# 280103_Worldcoin_Front_Unit_5_2.net
KiCad netlist of a schematic drawn in EAGLE
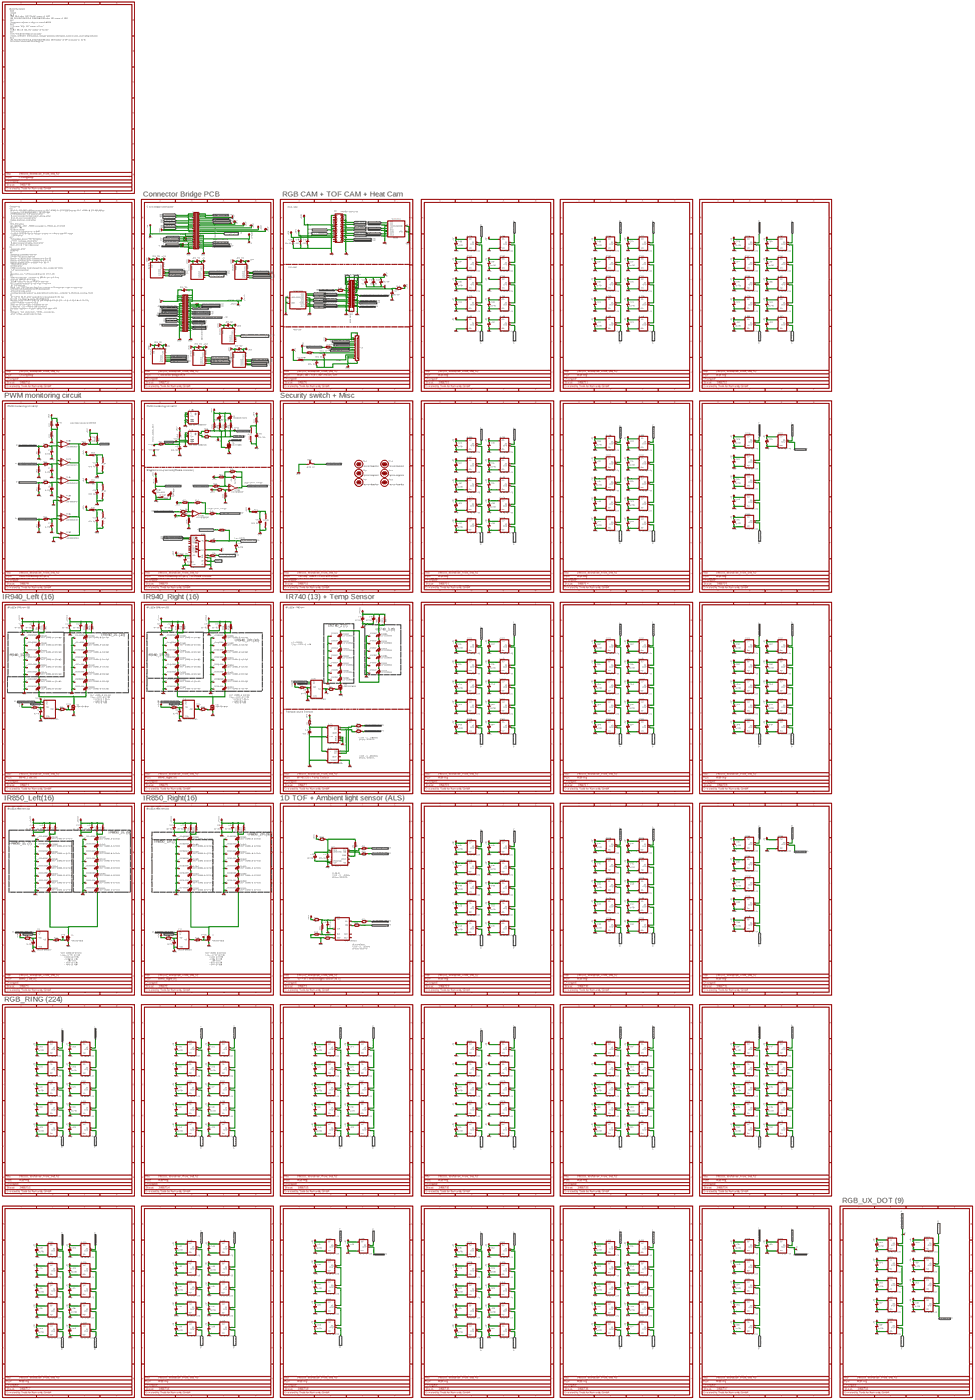
[diagram p0: schematic, sheet 1, overview]
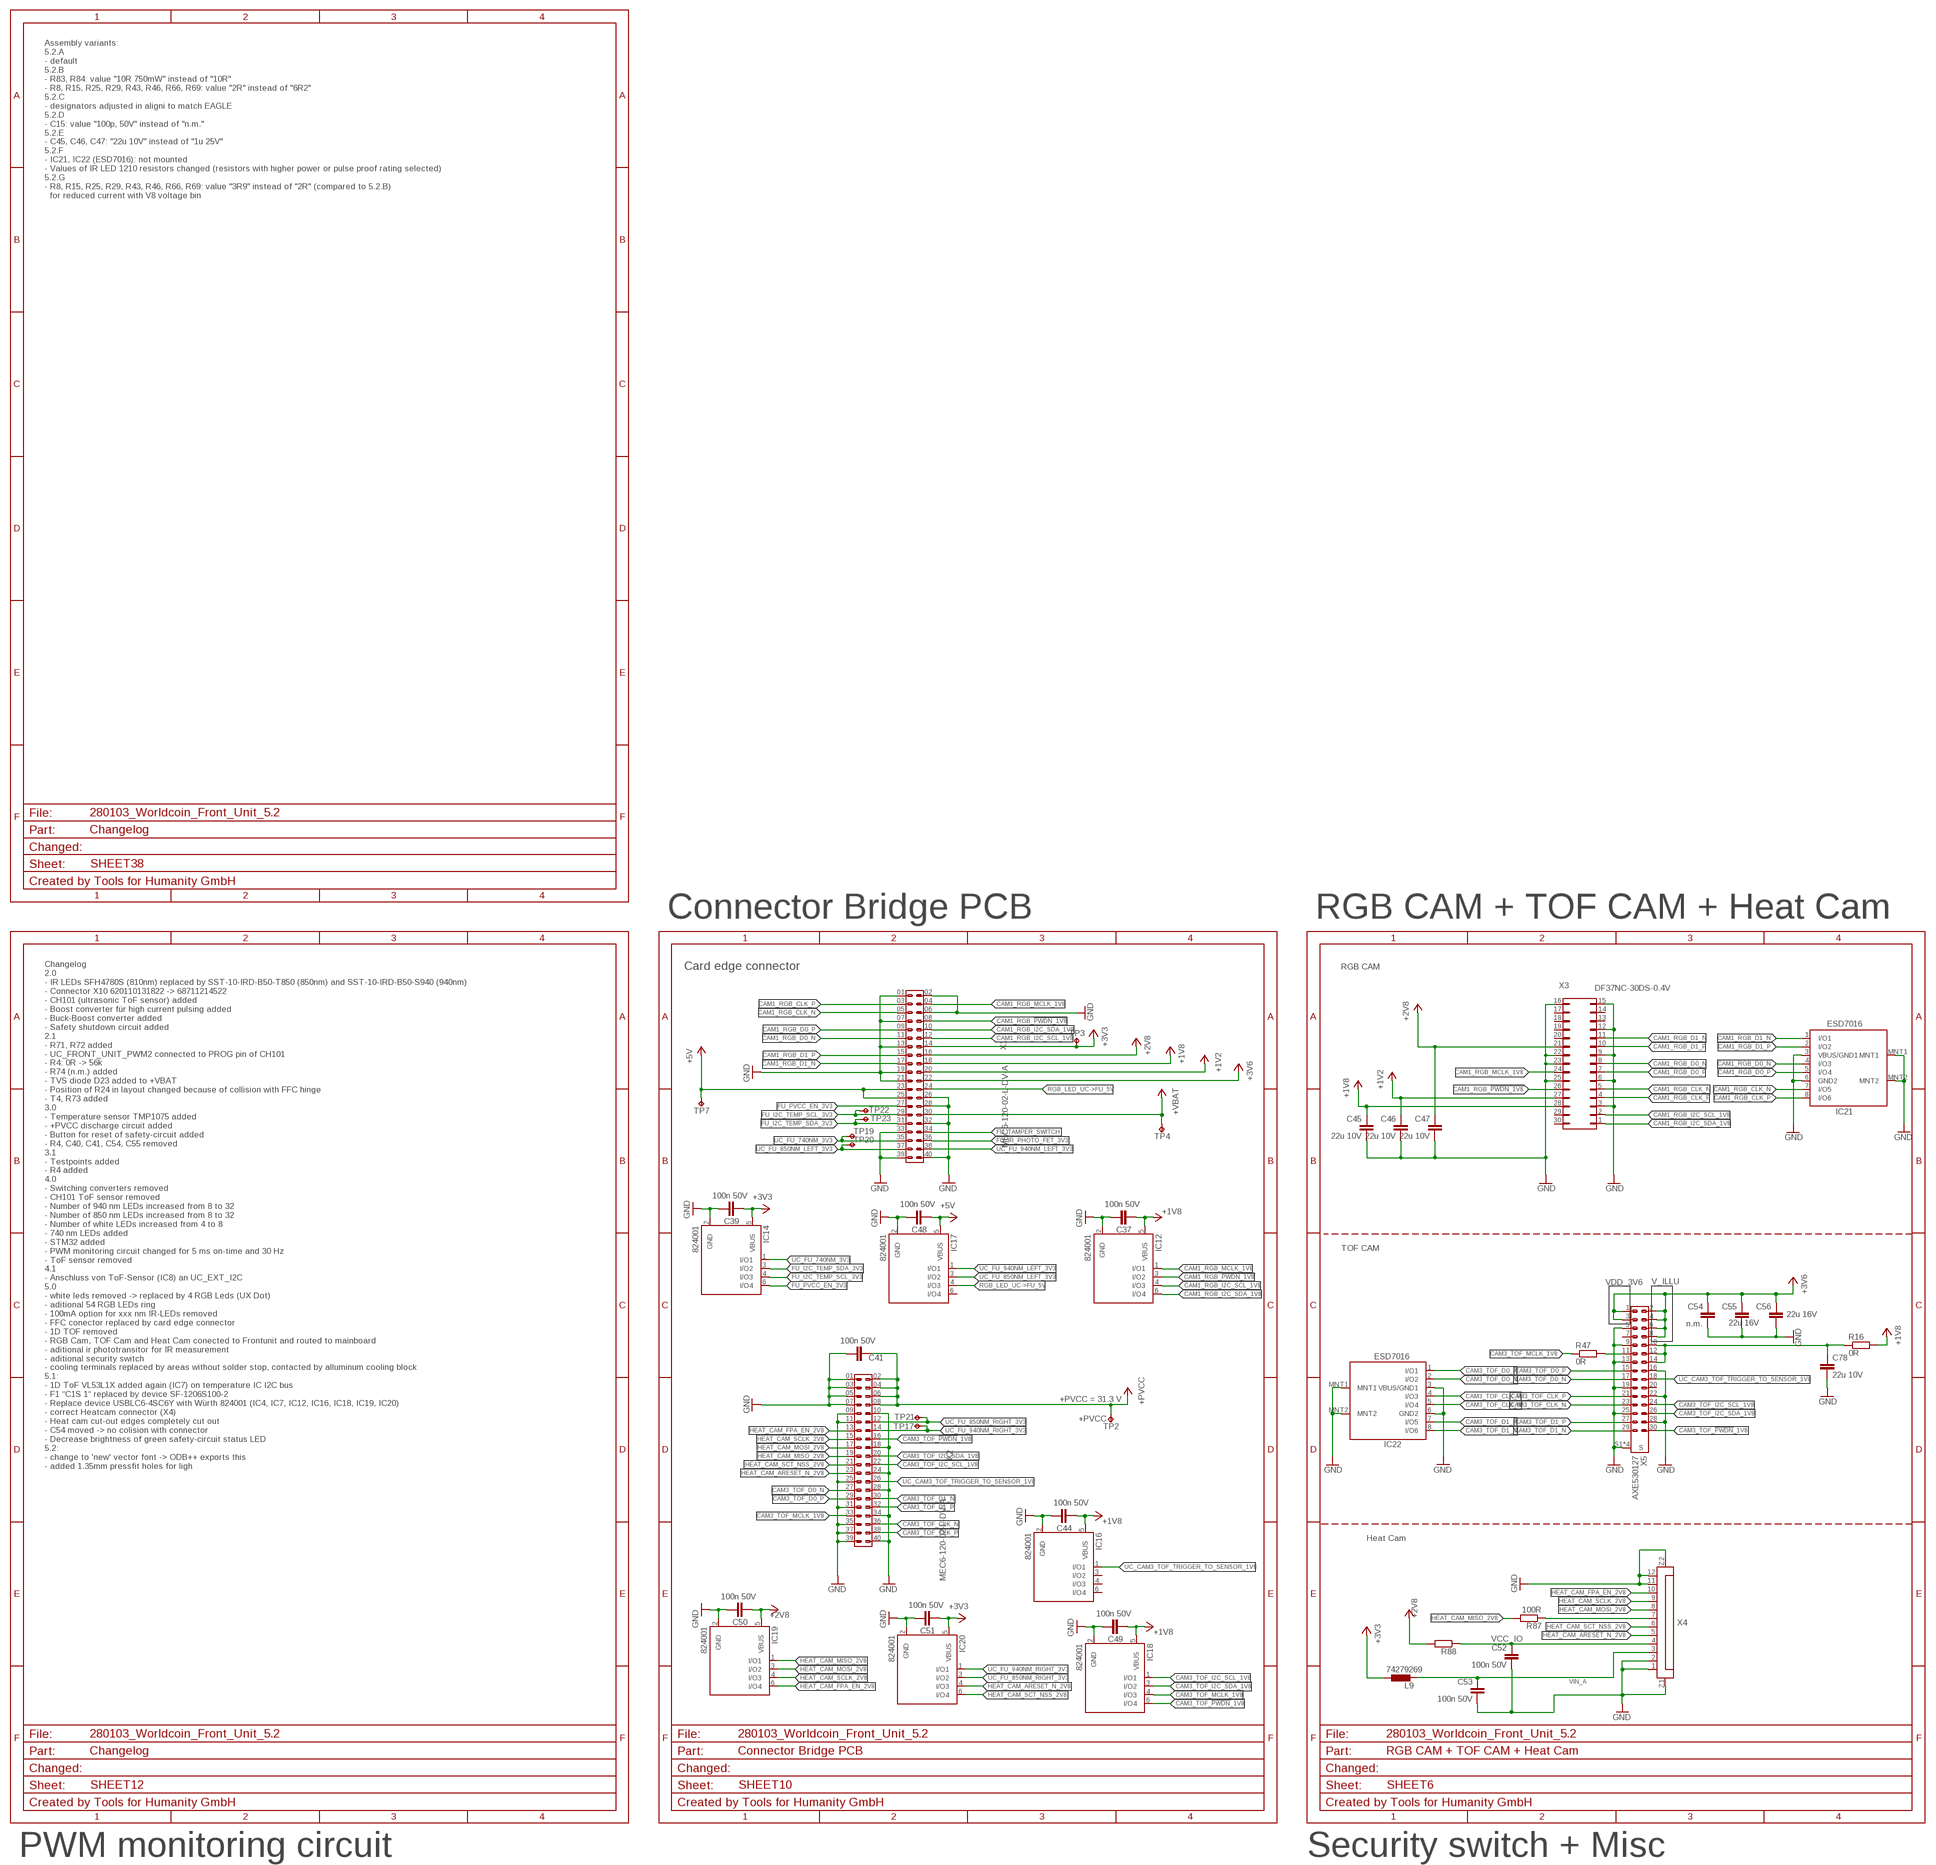
[diagram p1: schematic, sheet 1, part 1 of 8]
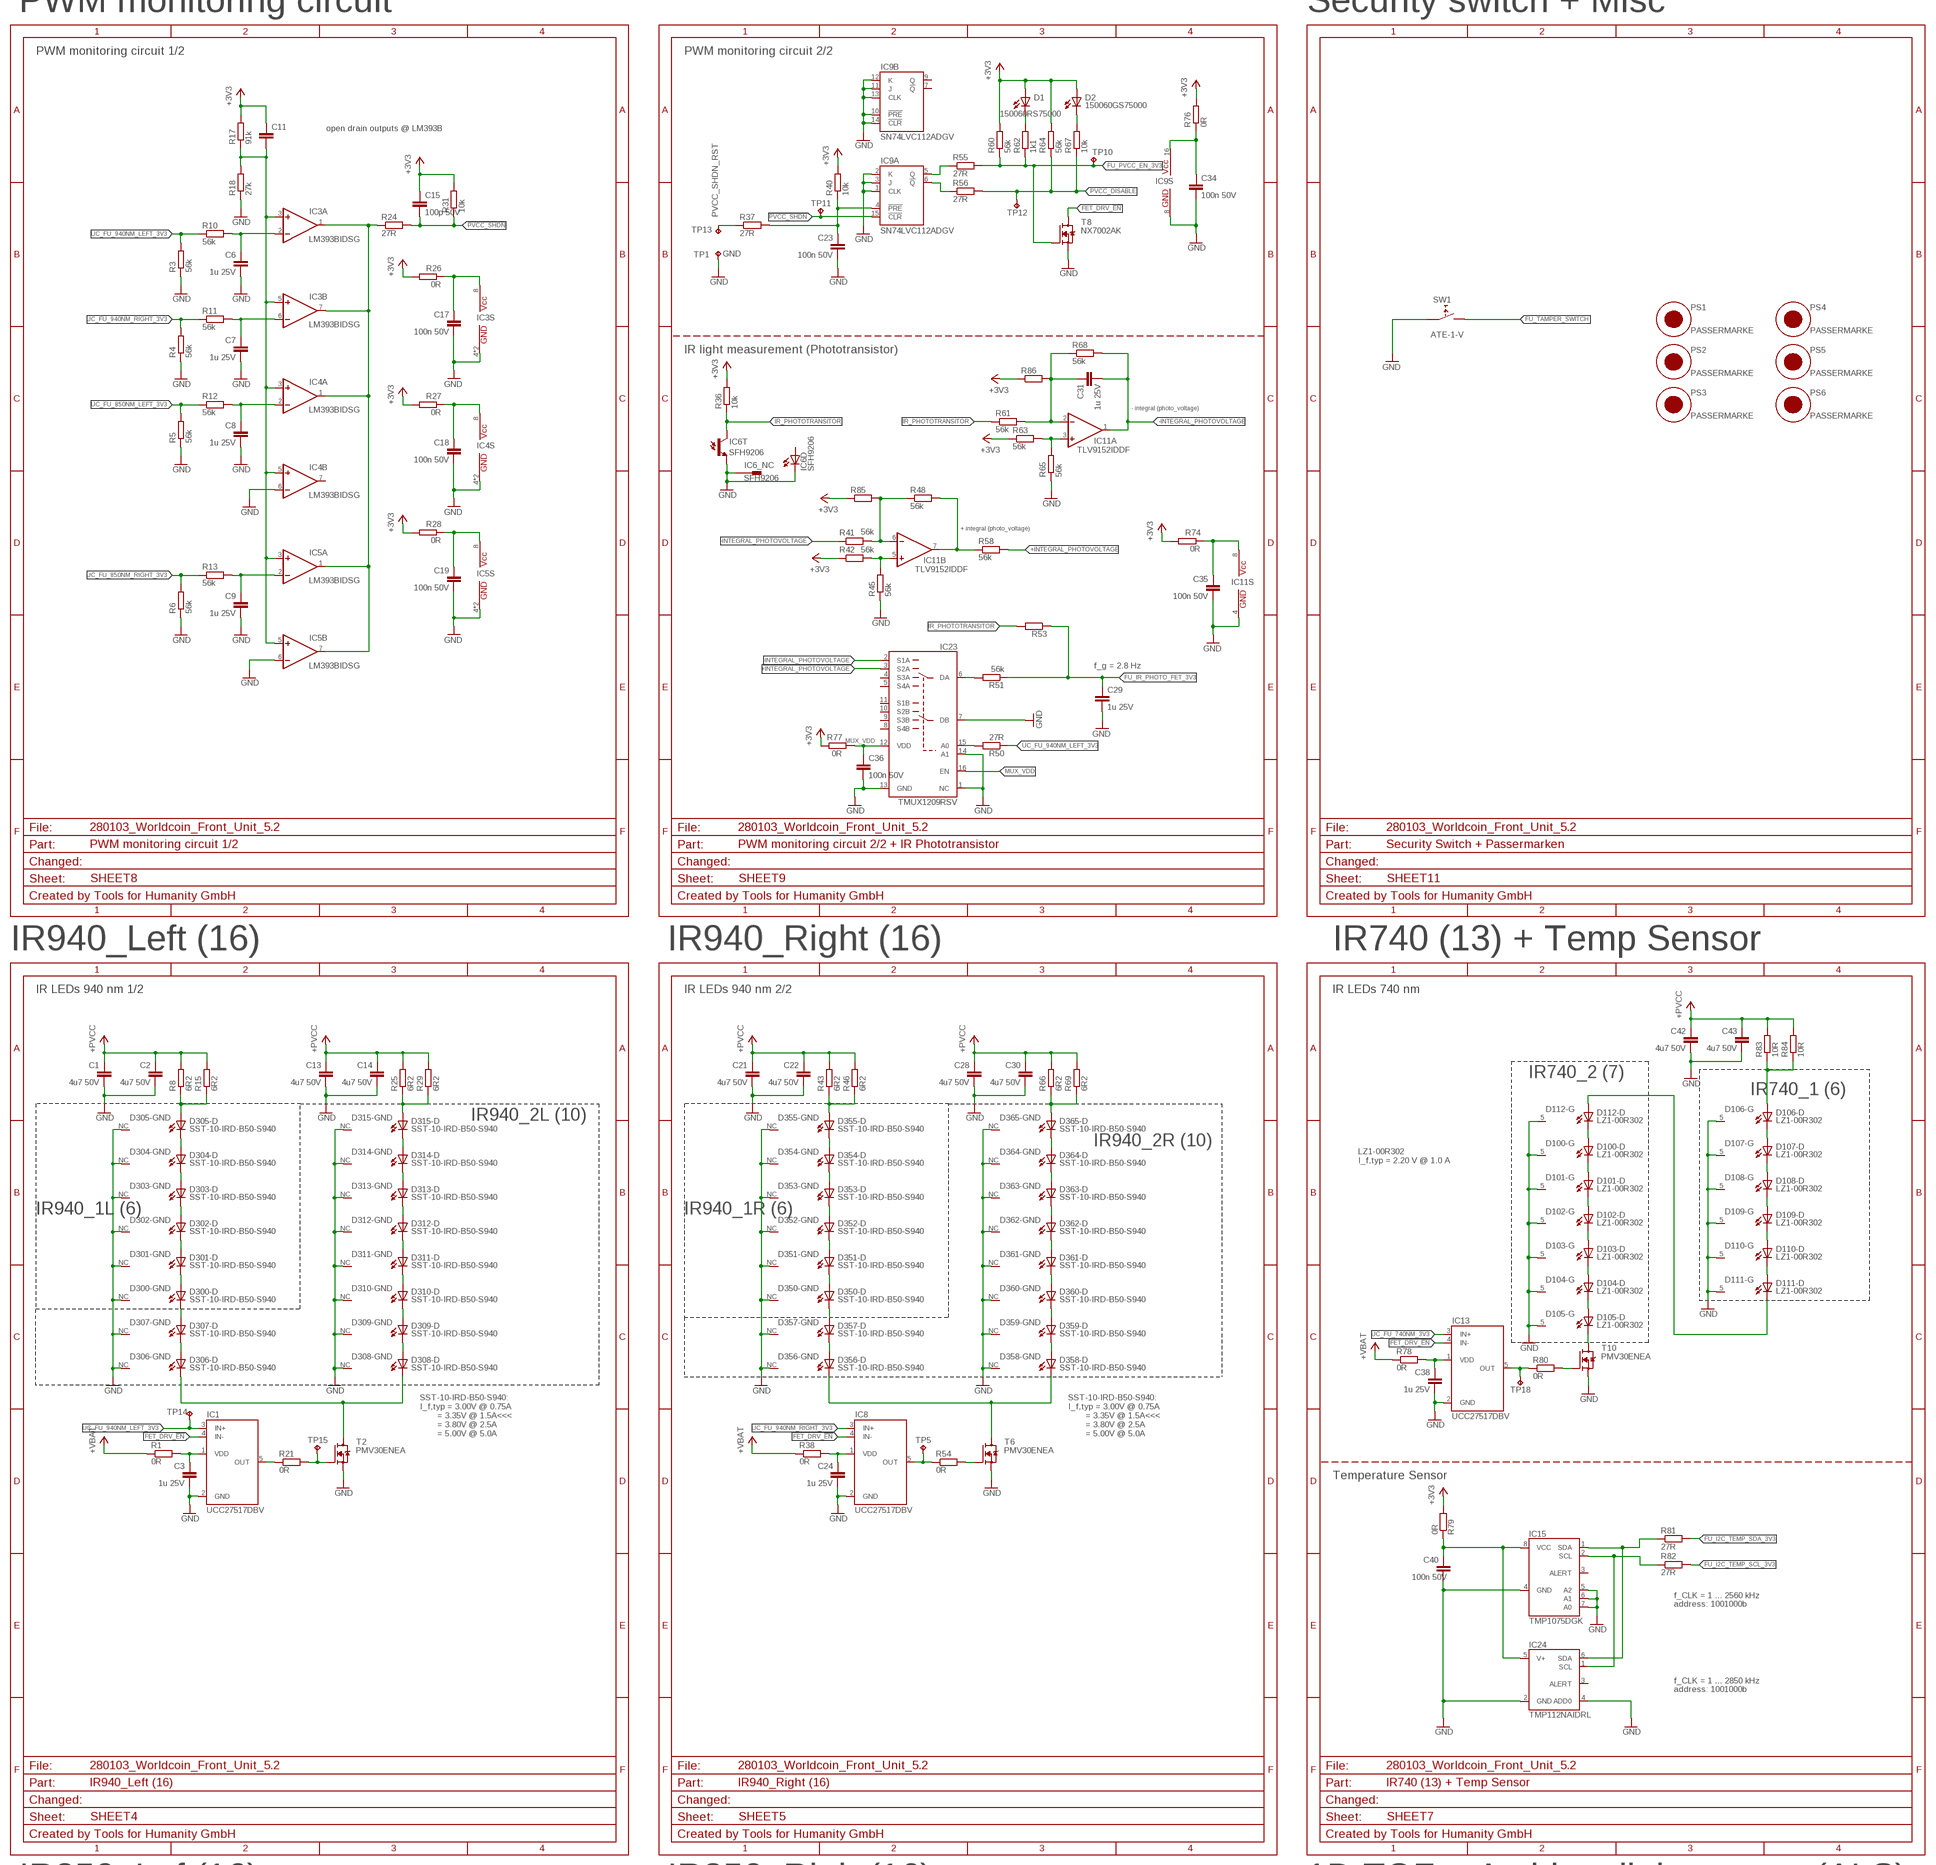
[diagram p2: schematic, sheet 1, part 2 of 8]
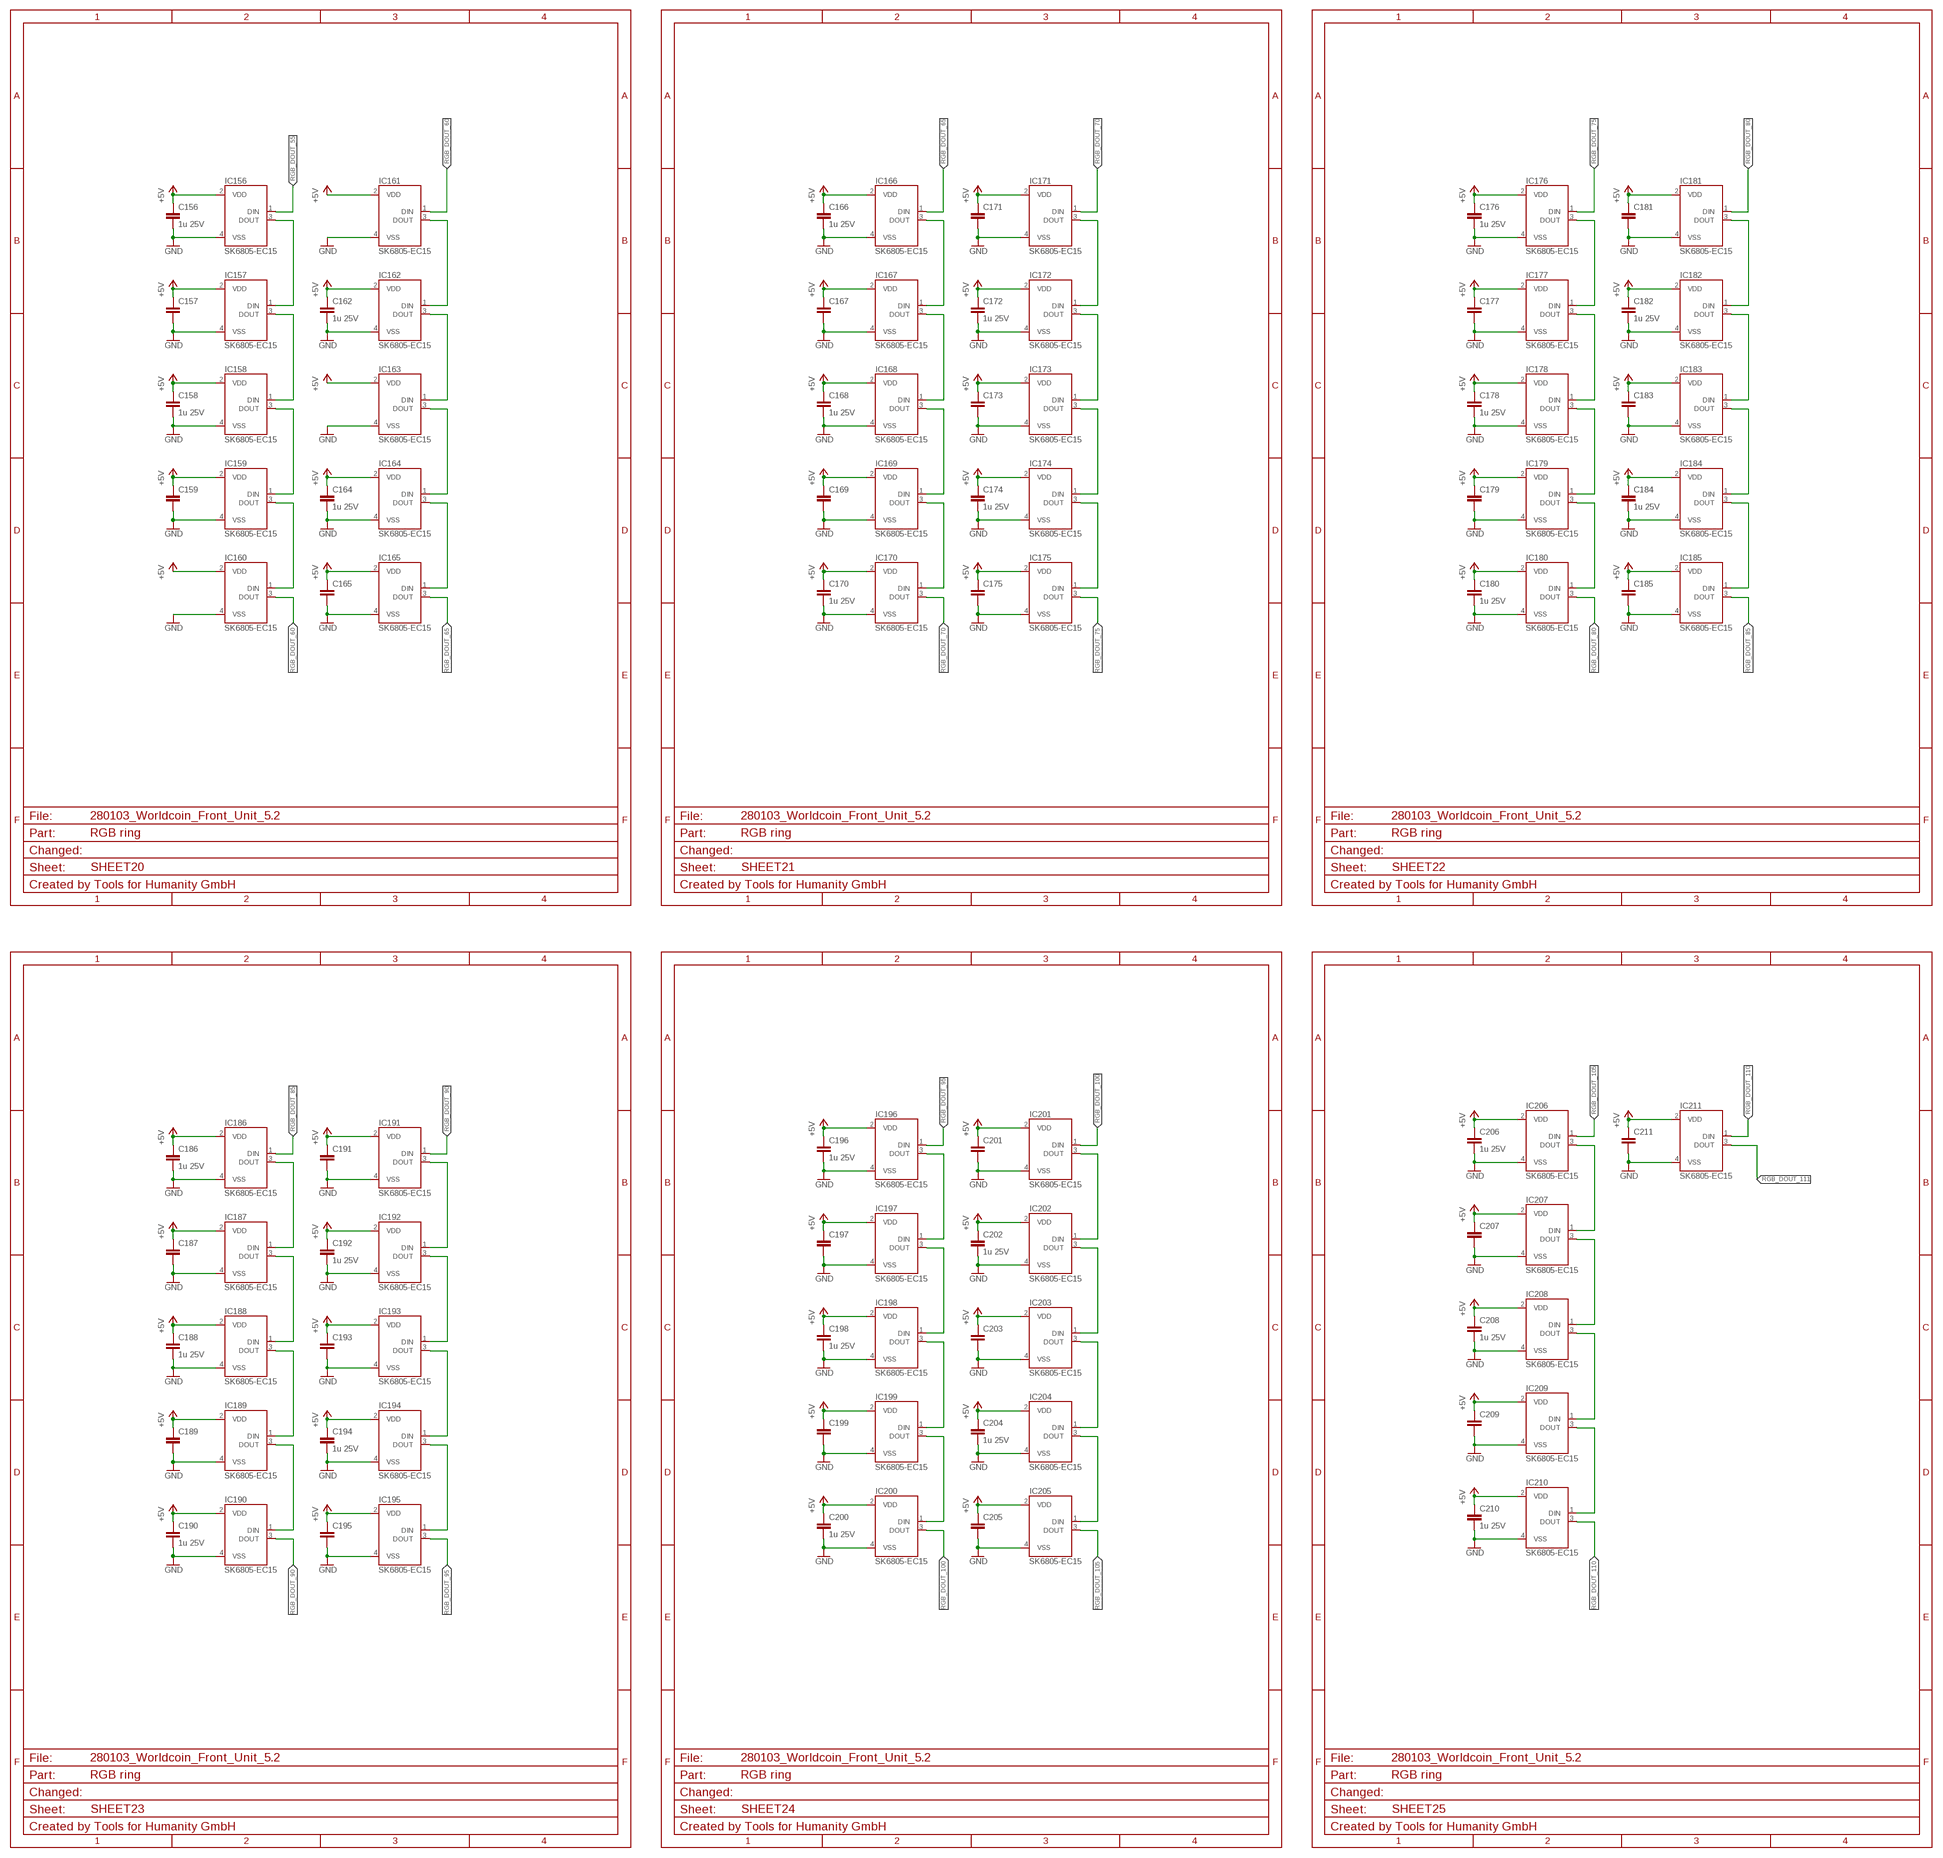
[diagram p3: schematic, sheet 1, part 3 of 8]
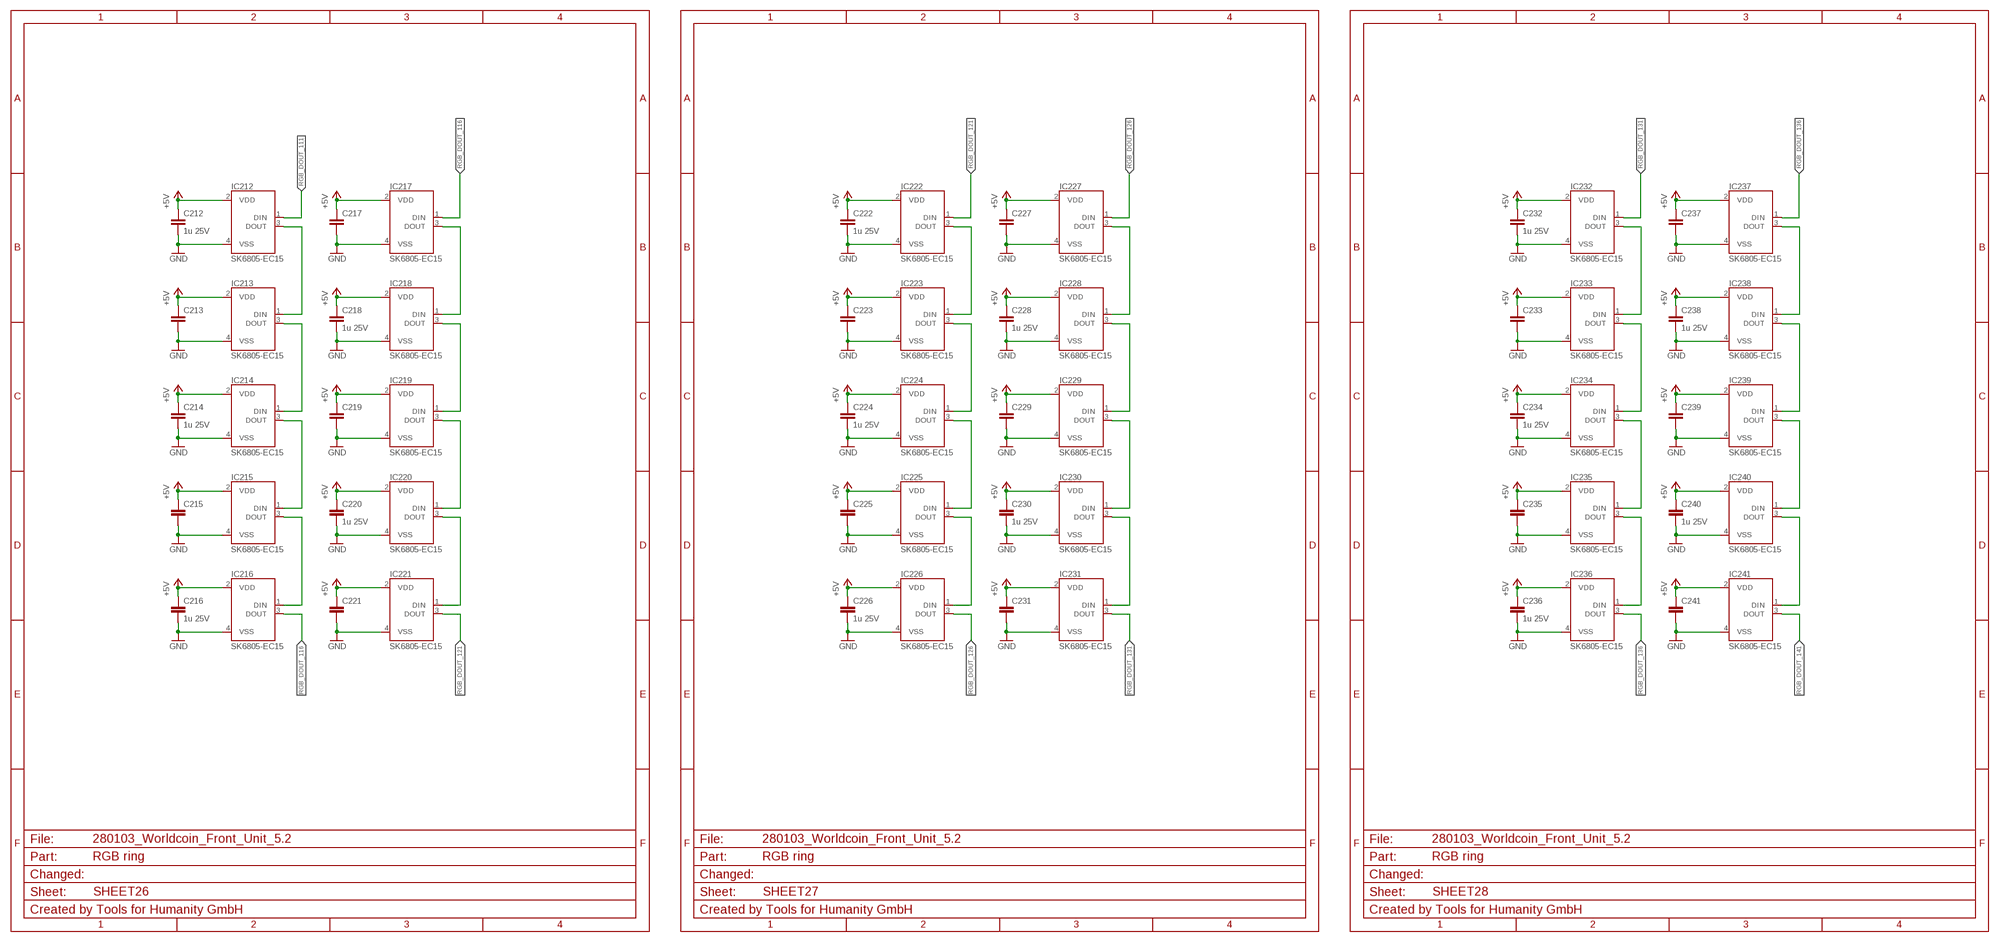
[diagram p4: schematic, sheet 1, part 4 of 8]
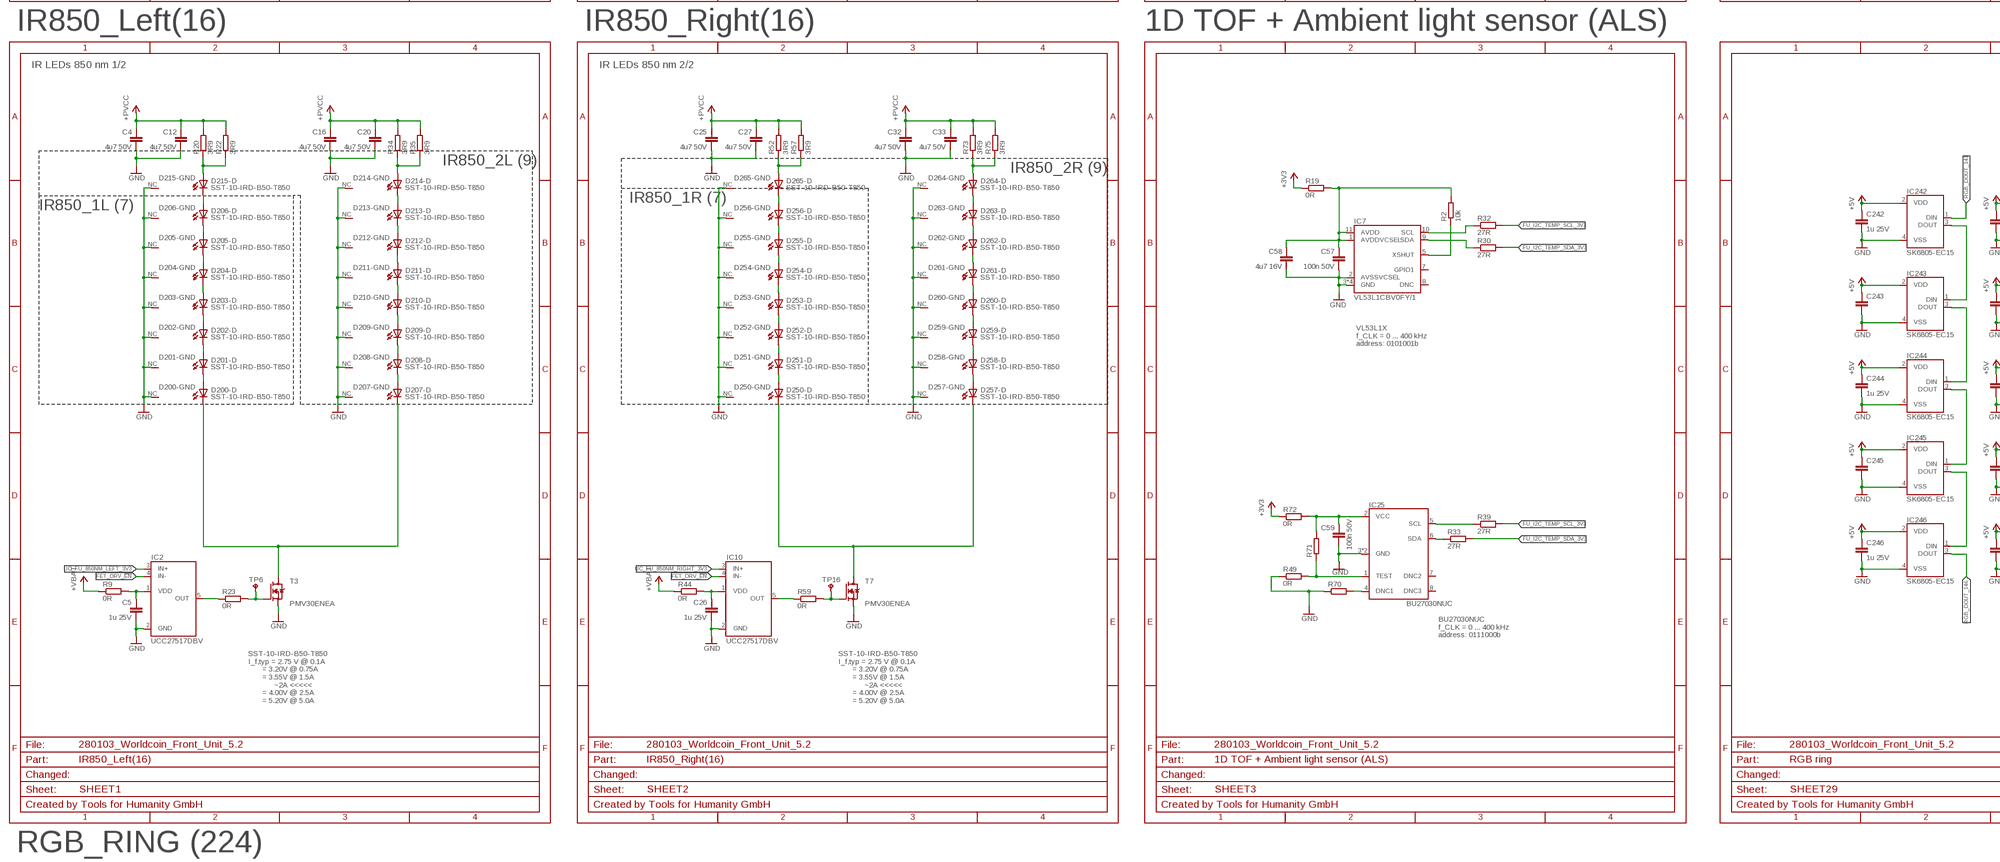
[diagram p5: schematic, sheet 1, part 5 of 8]
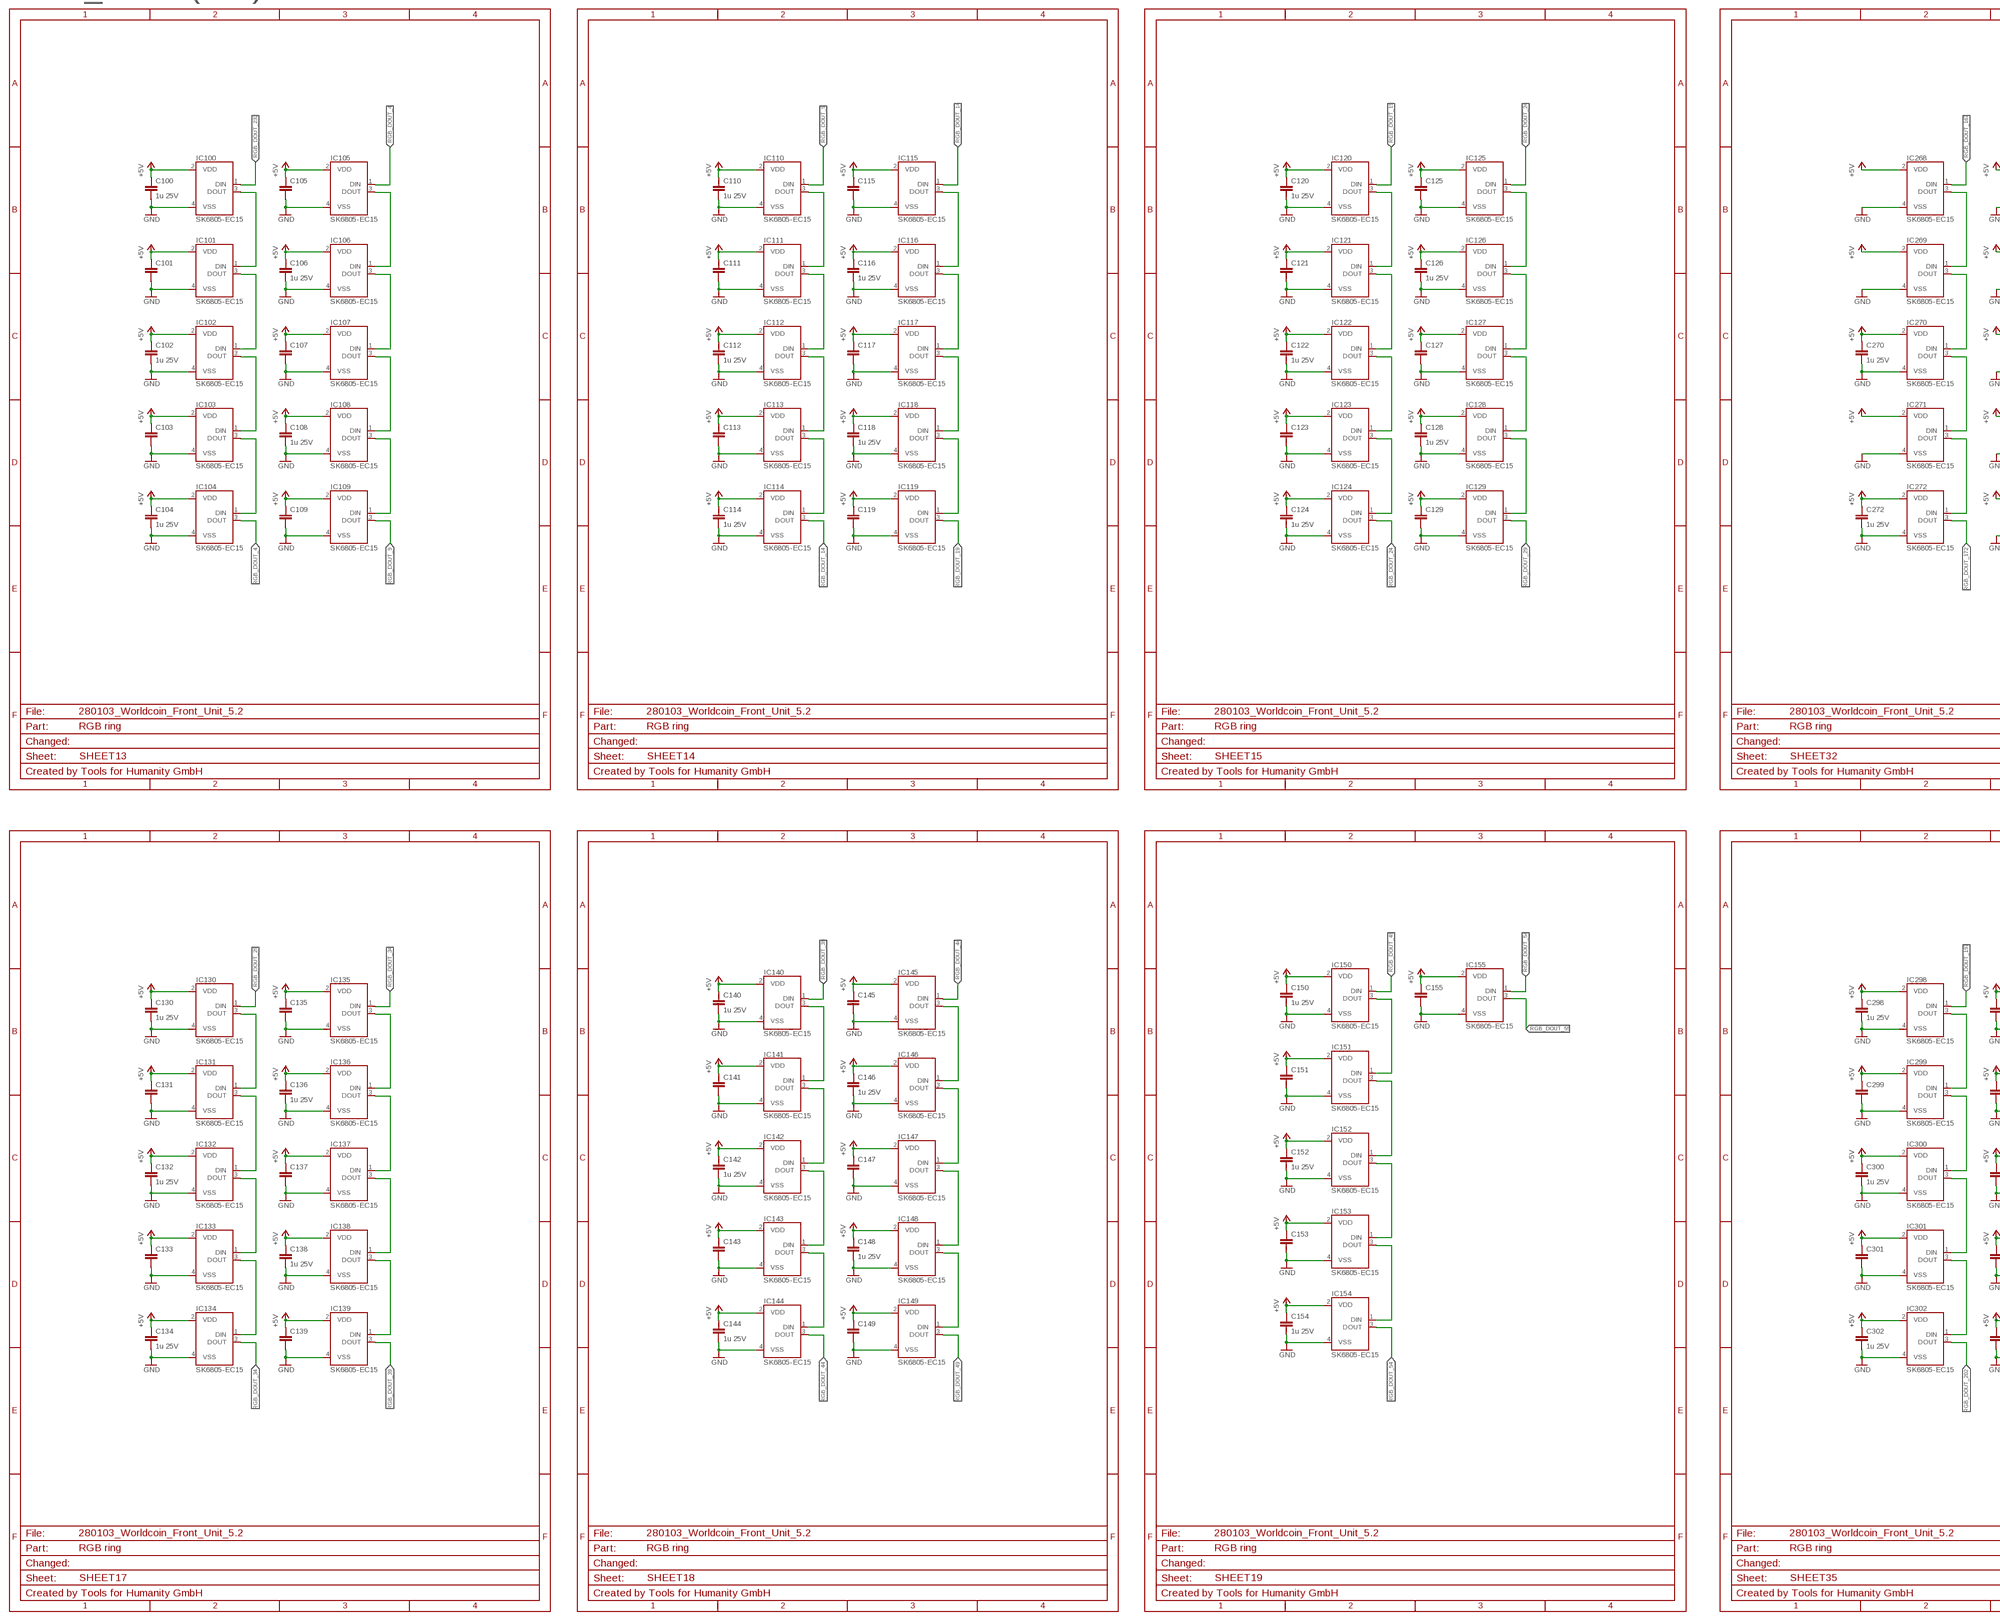
[diagram p6: schematic, sheet 1, part 6 of 8]
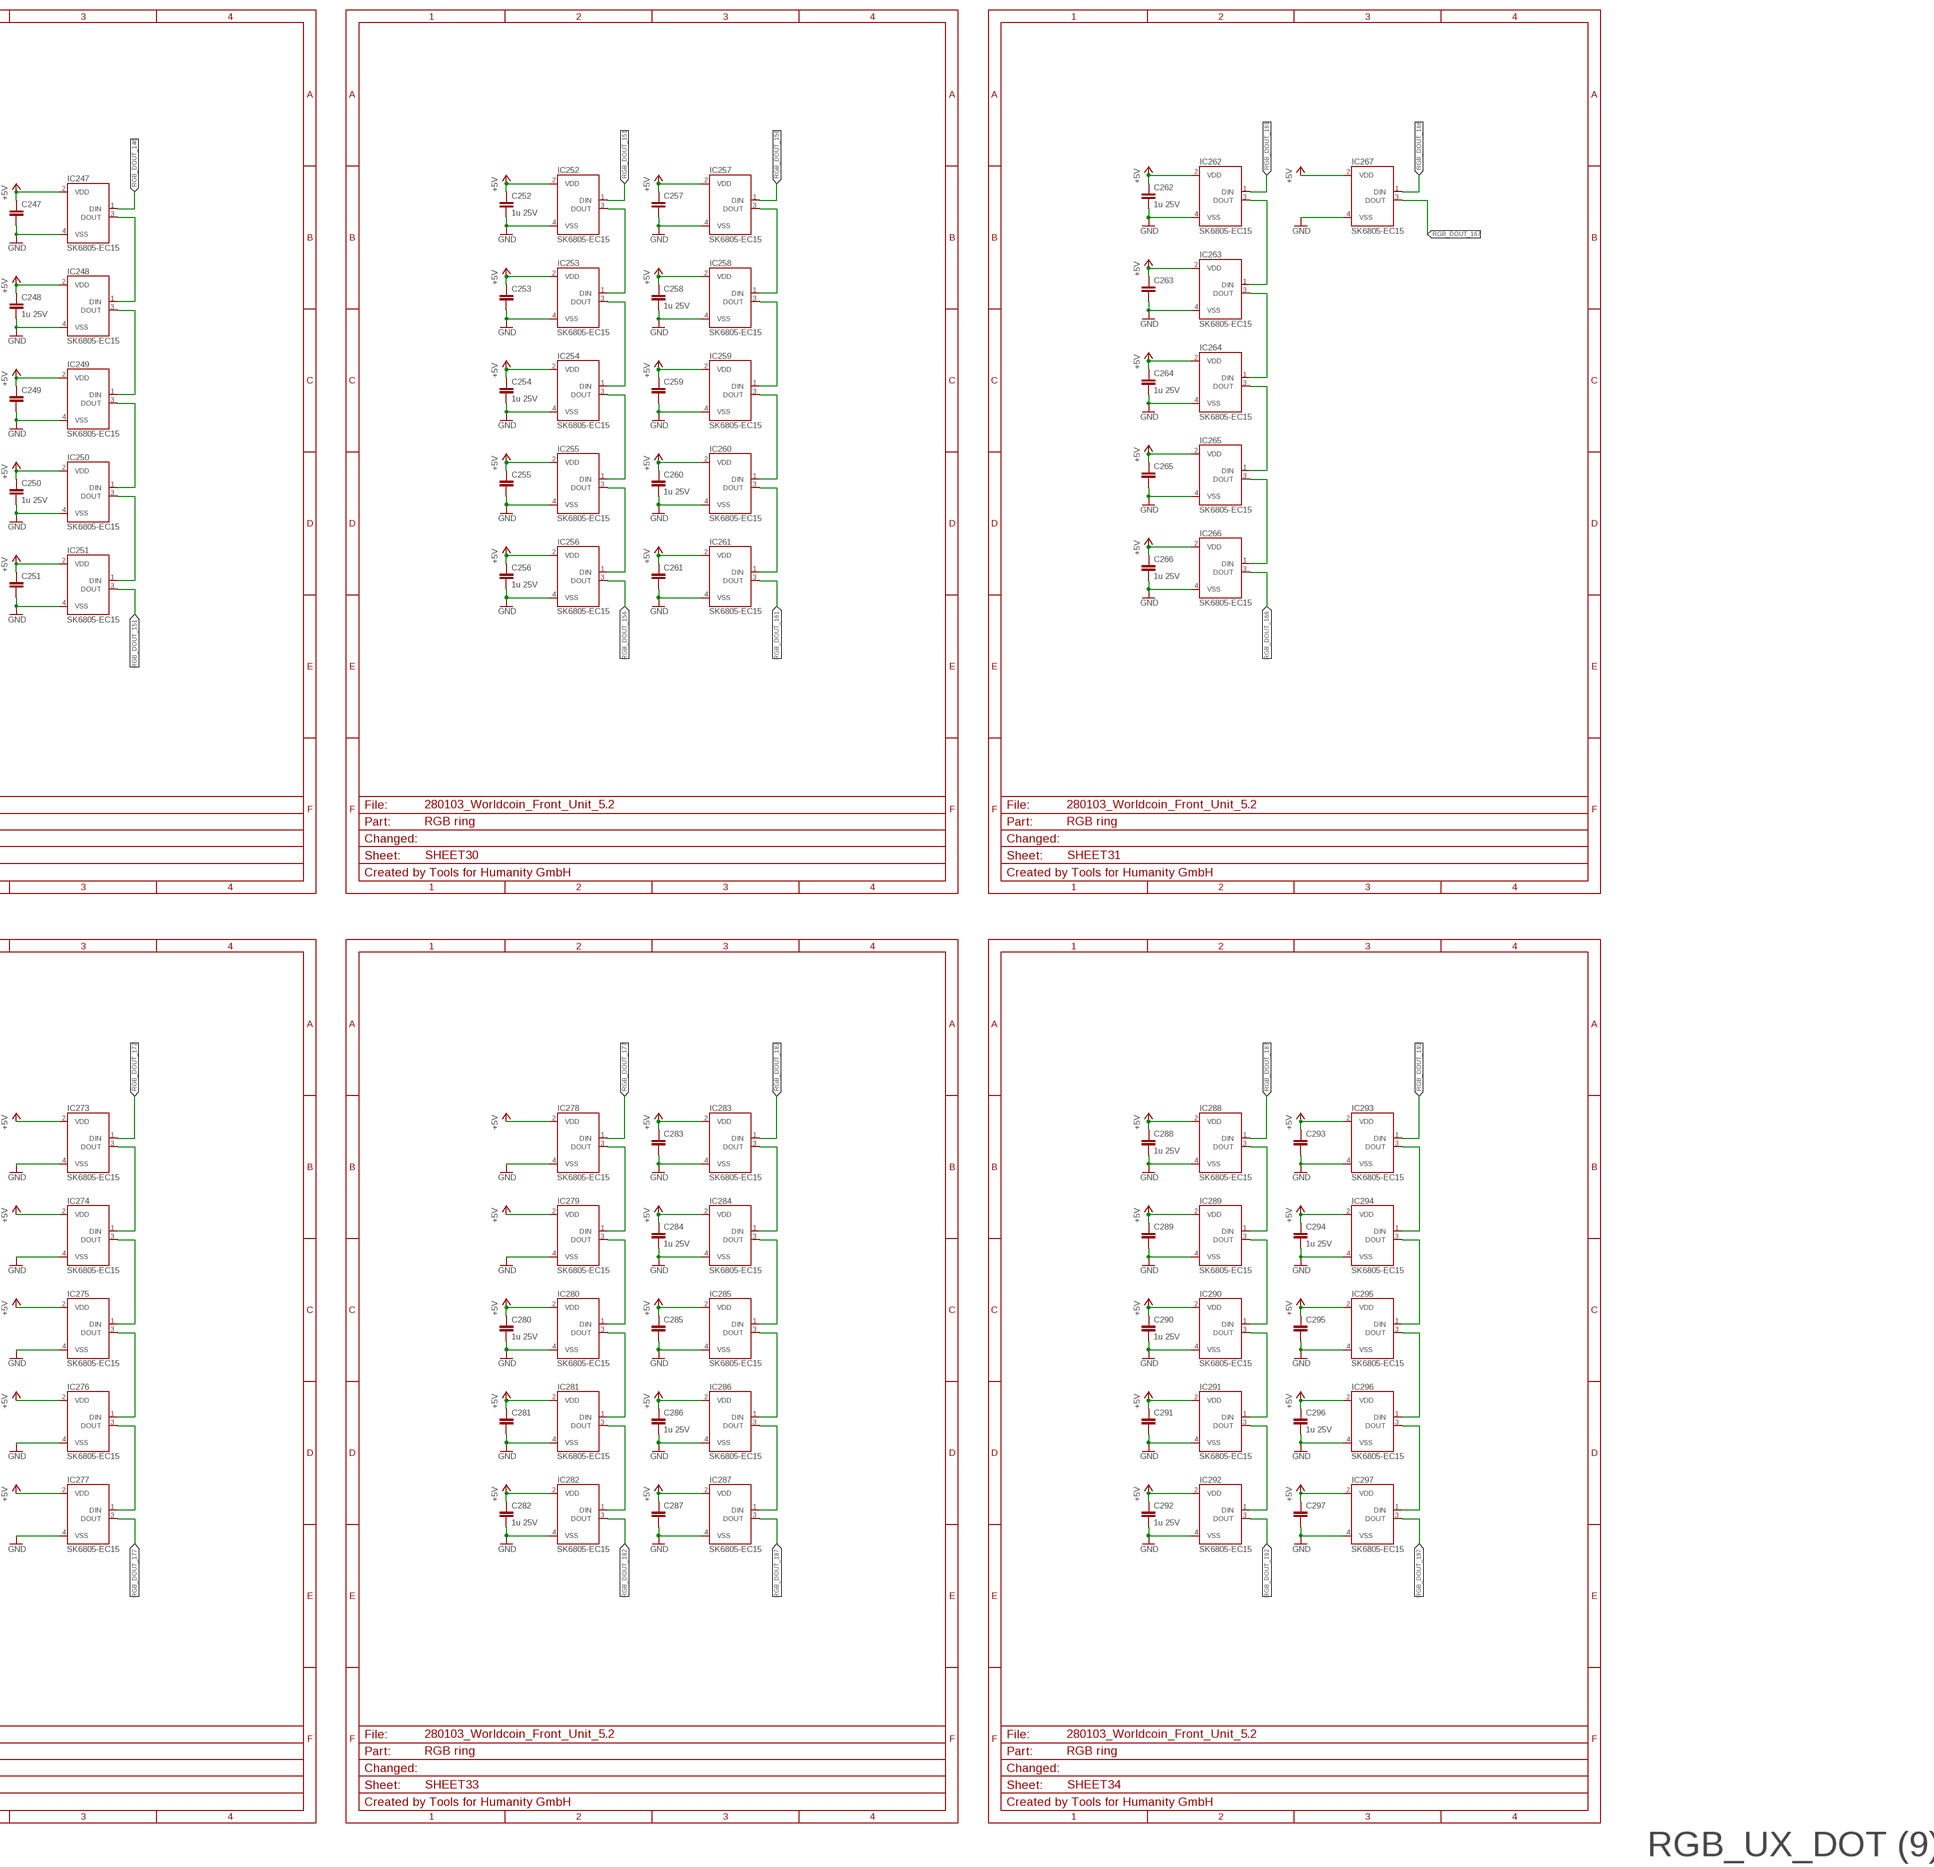
[diagram p7: schematic, sheet 1, part 7 of 8]
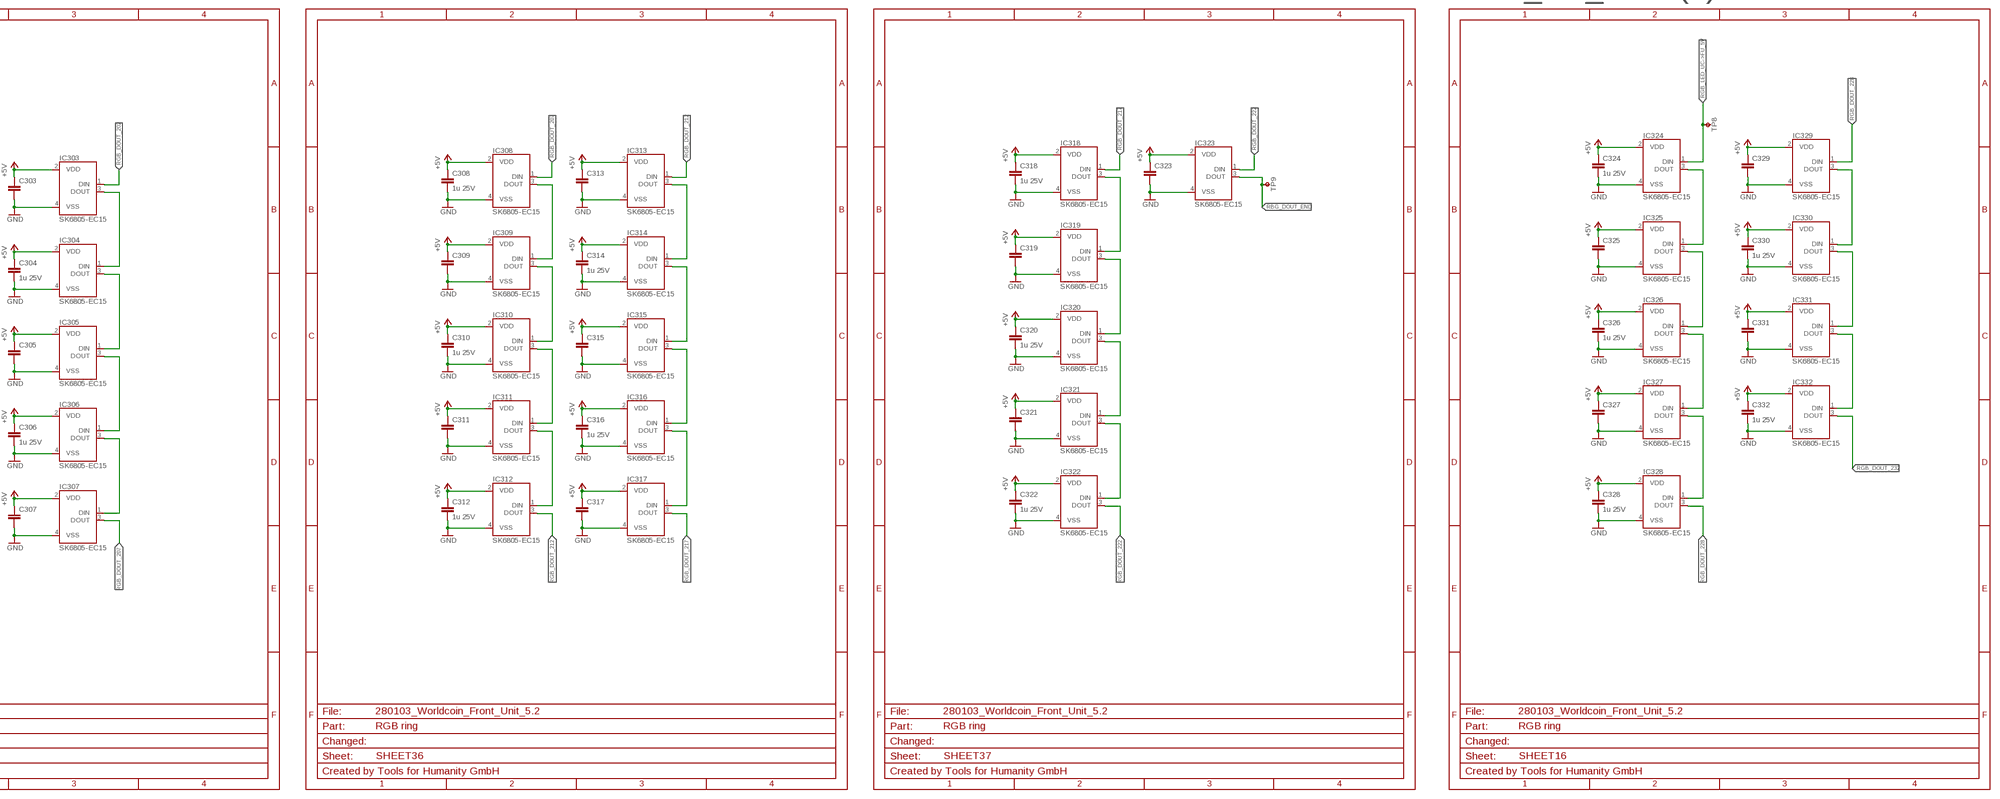
[diagram p8: schematic, sheet 1, part 8 of 8]

(export (version "E")
  (design (tool "Eeschema 10.0.6"))
  (components
    (comp (ref "C1")
      (value "4u7 50V")
      (footprint "eagle-import:C1210")
      (fields (field (name "TOLERANCE") "±20 %") (field (name "VOLTAGE") "50.0 V"))
      (libsource (lib "eagle-import") (part "C-EU-C1210"))
    )
    (comp (ref "C2")
      (value "4u7 50V")
      (footprint "eagle-import:C1210")
      (fields (field (name "TOLERANCE") "±20 %") (field (name "VOLTAGE") "50.0 V"))
      (libsource (lib "eagle-import") (part "C-EU-C1210"))
    )
    (comp (ref "C3")
      (value "1u 25V")
      (footprint "eagle-import:C0805")
      (fields
        (field (name "MANUFACTURER") "free choice")
        (field (name "TOLERANCE") "±20 %")
        (field (name "VOLTAGE") "25.0 V")
      )
      (libsource (lib "eagle-import") (part "C-EU-C0805-1U"))
    )
    (comp (ref "C4")
      (value "4u7 50V")
      (footprint "eagle-import:C1210")
      (fields (field (name "TOLERANCE") "±20 %") (field (name "VOLTAGE") "50.0 V"))
      (libsource (lib "eagle-import") (part "C-EU-C1210"))
    )
    (comp (ref "C5")
      (value "1u 25V")
      (footprint "eagle-import:C0805")
      (fields
        (field (name "MANUFACTURER") "free choice")
        (field (name "TOLERANCE") "±20 %")
        (field (name "VOLTAGE") "25.0 V")
      )
      (libsource (lib "eagle-import") (part "C-EU-C0805-1U"))
    )
    (comp (ref "C6")
      (value "1u 25V")
      (footprint "eagle-import:C0805")
      (fields
        (field (name "MANUFACTURER") "free choice")
        (field (name "TOLERANCE") "±20 %")
        (field (name "VOLTAGE") "25.0 V")
      )
      (libsource (lib "eagle-import") (part "C-EU-C0805-1U"))
    )
    (comp (ref "C7")
      (value "1u 25V")
      (footprint "eagle-import:C0805")
      (fields
        (field (name "MANUFACTURER") "free choice")
        (field (name "TOLERANCE") "±20 %")
        (field (name "VOLTAGE") "25.0 V")
      )
      (libsource (lib "eagle-import") (part "C-EU-C0805-1U"))
    )
    (comp (ref "C8")
      (value "1u 25V")
      (footprint "eagle-import:C0805")
      (fields
        (field (name "MANUFACTURER") "free choice")
        (field (name "TOLERANCE") "±20 %")
        (field (name "VOLTAGE") "25.0 V")
      )
      (libsource (lib "eagle-import") (part "C-EU-C0805-1U"))
    )
    (comp (ref "C9")
      (value "1u 25V")
      (footprint "eagle-import:C0805")
      (fields
        (field (name "MANUFACTURER") "free choice")
        (field (name "TOLERANCE") "±20 %")
        (field (name "VOLTAGE") "25.0 V")
      )
      (libsource (lib "eagle-import") (part "C-EU-C0805-1U"))
    )
    (comp (ref "C11")
      (value "C-EU-C0603")
      (footprint "eagle-import:C0603")
      (fields (field (name "TOLERANCE") "±20 %") (field (name "VOLTAGE") "50.0 V"))
      (libsource (lib "eagle-import") (part "C-EU-C0603"))
    )
    (comp (ref "C12")
      (value "4u7 50V")
      (footprint "eagle-import:C1210")
      (fields (field (name "TOLERANCE") "±20 %") (field (name "VOLTAGE") "50.0 V"))
      (libsource (lib "eagle-import") (part "C-EU-C1210"))
    )
    (comp (ref "C13")
      (value "4u7 50V")
      (footprint "eagle-import:C1210")
      (fields (field (name "TOLERANCE") "±20 %") (field (name "VOLTAGE") "50.0 V"))
      (libsource (lib "eagle-import") (part "C-EU-C1210"))
    )
    (comp (ref "C14")
      (value "4u7 50V")
      (footprint "eagle-import:C1210")
      (fields (field (name "TOLERANCE") "±20 %") (field (name "VOLTAGE") "50.0 V"))
      (libsource (lib "eagle-import") (part "C-EU-C1210"))
    )
    (comp (ref "C15")
      (value "100p 50V")
      (footprint "eagle-import:C0603")
      (fields
        (field (name "MANUFACTURER") "free choice")
        (field (name "TOLERANCE") "±10 %")
        (field (name "VOLTAGE") "50.0 V")
      )
      (libsource (lib "eagle-import") (part "C-EU-C0603-100P"))
    )
    (comp (ref "C16")
      (value "4u7 50V")
      (footprint "eagle-import:C1210")
      (fields (field (name "TOLERANCE") "±20 %") (field (name "VOLTAGE") "50.0 V"))
      (libsource (lib "eagle-import") (part "C-EU-C1210"))
    )
    (comp (ref "C17")
      (value "100n 50V")
      (footprint "eagle-import:C0603")
      (fields
        (field (name "MANUFACTURER") "free choice")
        (field (name "TOLERANCE") "±20 %")
        (field (name "VOLTAGE") "50.0 V")
      )
      (libsource (lib "eagle-import") (part "C-EU-C0603-100N"))
    )
    (comp (ref "C18")
      (value "100n 50V")
      (footprint "eagle-import:C0603")
      (fields
        (field (name "MANUFACTURER") "free choice")
        (field (name "TOLERANCE") "±20 %")
        (field (name "VOLTAGE") "50.0 V")
      )
      (libsource (lib "eagle-import") (part "C-EU-C0603-100N"))
    )
    (comp (ref "C19")
      (value "100n 50V")
      (footprint "eagle-import:C0603")
      (fields
        (field (name "MANUFACTURER") "free choice")
        (field (name "TOLERANCE") "±20 %")
        (field (name "VOLTAGE") "50.0 V")
      )
      (libsource (lib "eagle-import") (part "C-EU-C0603-100N"))
    )
    (comp (ref "C20")
      (value "4u7 50V")
      (footprint "eagle-import:C1210")
      (fields (field (name "TOLERANCE") "±20 %") (field (name "VOLTAGE") "50.0 V"))
      (libsource (lib "eagle-import") (part "C-EU-C1210"))
    )
    (comp (ref "C21")
      (value "4u7 50V")
      (footprint "eagle-import:C1210")
      (fields (field (name "TOLERANCE") "±20 %") (field (name "VOLTAGE") "50.0 V"))
      (libsource (lib "eagle-import") (part "C-EU-C1210"))
    )
    (comp (ref "C22")
      (value "4u7 50V")
      (footprint "eagle-import:C1210")
      (fields (field (name "TOLERANCE") "±20 %") (field (name "VOLTAGE") "50.0 V"))
      (libsource (lib "eagle-import") (part "C-EU-C1210"))
    )
    (comp (ref "C23")
      (value "100n 50V")
      (footprint "eagle-import:C0603")
      (fields
        (field (name "MANUFACTURER") "free choice")
        (field (name "TOLERANCE") "±20 %")
        (field (name "VOLTAGE") "50.0 V")
      )
      (libsource (lib "eagle-import") (part "C-EU-C0603-100N"))
    )
    (comp (ref "C24")
      (value "1u 25V")
      (footprint "eagle-import:C0805")
      (fields
        (field (name "MANUFACTURER") "free choice")
        (field (name "TOLERANCE") "±20 %")
        (field (name "VOLTAGE") "25.0 V")
      )
      (libsource (lib "eagle-import") (part "C-EU-C0805-1U"))
    )
    (comp (ref "C25")
      (value "4u7 50V")
      (footprint "eagle-import:C1210")
      (fields (field (name "TOLERANCE") "±20 %") (field (name "VOLTAGE") "50.0 V"))
      (libsource (lib "eagle-import") (part "C-EU-C1210"))
    )
    (comp (ref "C26")
      (value "1u 25V")
      (footprint "eagle-import:C0805")
      (fields
        (field (name "MANUFACTURER") "free choice")
        (field (name "TOLERANCE") "±20 %")
        (field (name "VOLTAGE") "25.0 V")
      )
      (libsource (lib "eagle-import") (part "C-EU-C0805-1U"))
    )
    (comp (ref "C27")
      (value "4u7 50V")
      (footprint "eagle-import:C1210")
      (fields (field (name "TOLERANCE") "±20 %") (field (name "VOLTAGE") "50.0 V"))
      (libsource (lib "eagle-import") (part "C-EU-C1210"))
    )
    (comp (ref "C28")
      (value "4u7 50V")
      (footprint "eagle-import:C1210")
      (fields (field (name "TOLERANCE") "±20 %") (field (name "VOLTAGE") "50.0 V"))
      (libsource (lib "eagle-import") (part "C-EU-C1210"))
    )
    (comp (ref "C29")
      (value "1u 25V")
      (footprint "eagle-import:C0805")
      (fields
        (field (name "MANUFACTURER") "free choice")
        (field (name "TOLERANCE") "±20 %")
        (field (name "VOLTAGE") "25.0 V")
      )
      (libsource (lib "eagle-import") (part "C-EU-C0805-1U"))
    )
    (comp (ref "C30")
      (value "4u7 50V")
      (footprint "eagle-import:C1210")
      (fields (field (name "TOLERANCE") "±20 %") (field (name "VOLTAGE") "50.0 V"))
      (libsource (lib "eagle-import") (part "C-EU-C1210"))
    )
    (comp (ref "C31")
      (value "1u 25V")
      (footprint "eagle-import:C0805")
      (fields
        (field (name "MANUFACTURER") "free choice")
        (field (name "TOLERANCE") "±20 %")
        (field (name "VOLTAGE") "25.0 V")
      )
      (libsource (lib "eagle-import") (part "C-EU-C0805-1U"))
    )
    (comp (ref "C32")
      (value "4u7 50V")
      (footprint "eagle-import:C1210")
      (fields (field (name "TOLERANCE") "±20 %") (field (name "VOLTAGE") "50.0 V"))
      (libsource (lib "eagle-import") (part "C-EU-C1210"))
    )
    (comp (ref "C33")
      (value "4u7 50V")
      (footprint "eagle-import:C1210")
      (fields (field (name "TOLERANCE") "±20 %") (field (name "VOLTAGE") "50.0 V"))
      (libsource (lib "eagle-import") (part "C-EU-C1210"))
    )
    (comp (ref "C34")
      (value "100n 50V")
      (footprint "eagle-import:C0603")
      (fields
        (field (name "MANUFACTURER") "free choice")
        (field (name "TOLERANCE") "±20 %")
        (field (name "VOLTAGE") "50.0 V")
      )
      (libsource (lib "eagle-import") (part "C-EU-C0603-100N"))
    )
    (comp (ref "C35")
      (value "100n 50V")
      (footprint "eagle-import:C0603")
      (fields
        (field (name "MANUFACTURER") "free choice")
        (field (name "TOLERANCE") "±20 %")
        (field (name "VOLTAGE") "50.0 V")
      )
      (libsource (lib "eagle-import") (part "C-EU-C0603-100N"))
    )
    (comp (ref "C36")
      (value "100n 50V")
      (footprint "eagle-import:C0603")
      (fields
        (field (name "MANUFACTURER") "free choice")
        (field (name "TOLERANCE") "±20 %")
        (field (name "VOLTAGE") "50.0 V")
      )
      (libsource (lib "eagle-import") (part "C-EU-C0603-100N"))
    )
    (comp (ref "C37")
      (value "100n 50V")
      (footprint "eagle-import:C0603")
      (fields
        (field (name "MANUFACTURER") "free choice")
        (field (name "TOLERANCE") "±20 %")
        (field (name "VOLTAGE") "50.0 V")
      )
      (libsource (lib "eagle-import") (part "C-EU-C0603-100N"))
    )
    (comp (ref "C38")
      (value "1u 25V")
      (footprint "eagle-import:C0805")
      (fields
        (field (name "MANUFACTURER") "free choice")
        (field (name "TOLERANCE") "±20 %")
        (field (name "VOLTAGE") "25.0 V")
      )
      (libsource (lib "eagle-import") (part "C-EU-C0805-1U"))
    )
    (comp (ref "C39")
      (value "100n 50V")
      (footprint "eagle-import:C0603")
      (fields
        (field (name "MANUFACTURER") "free choice")
        (field (name "TOLERANCE") "±20 %")
        (field (name "VOLTAGE") "50.0 V")
      )
      (libsource (lib "eagle-import") (part "C-EU-C0603-100N"))
    )
    (comp (ref "C40")
      (value "100n 50V")
      (footprint "eagle-import:C0603")
      (fields
        (field (name "MANUFACTURER") "free choice")
        (field (name "TOLERANCE") "±20 %")
        (field (name "VOLTAGE") "50.0 V")
      )
      (libsource (lib "eagle-import") (part "C-EU-C0603-100N"))
    )
    (comp (ref "C41")
      (value "100n 50V")
      (footprint "eagle-import:C0603")
      (fields
        (field (name "MANUFACTURER") "free choice")
        (field (name "TOLERANCE") "±20 %")
        (field (name "VOLTAGE") "50.0 V")
      )
      (libsource (lib "eagle-import") (part "C-EU-C0603-100N"))
    )
    (comp (ref "C42")
      (value "4u7 50V")
      (footprint "eagle-import:C1210")
      (fields (field (name "TOLERANCE") "±20 %") (field (name "VOLTAGE") "50.0 V"))
      (libsource (lib "eagle-import") (part "C-EU-C1210"))
    )
    (comp (ref "C43")
      (value "4u7 50V")
      (footprint "eagle-import:C1210")
      (fields (field (name "TOLERANCE") "±20 %") (field (name "VOLTAGE") "50.0 V"))
      (libsource (lib "eagle-import") (part "C-EU-C1210"))
    )
    (comp (ref "C44")
      (value "100n 50V")
      (footprint "eagle-import:C0603")
      (fields
        (field (name "MANUFACTURER") "free choice")
        (field (name "TOLERANCE") "±20 %")
        (field (name "VOLTAGE") "50.0 V")
      )
      (libsource (lib "eagle-import") (part "C-EU-C0603-100N"))
    )
    (comp (ref "C45")
      (value "22u 10V")
      (footprint "eagle-import:C0805")
      (fields
        (field (name "MANUFACTURER") "free choice")
        (field (name "TOLERANCE") "±20 %")
        (field (name "VOLTAGE") "10.0 V")
      )
      (libsource (lib "eagle-import") (part "C-EU-C0805-22U"))
    )
    (comp (ref "C46")
      (value "22u 10V")
      (footprint "eagle-import:C0805")
      (fields
        (field (name "MANUFACTURER") "free choice")
        (field (name "TOLERANCE") "±20 %")
        (field (name "VOLTAGE") "10.0 V")
      )
      (libsource (lib "eagle-import") (part "C-EU-C0805-22U"))
    )
    (comp (ref "C47")
      (value "22u 10V")
      (footprint "eagle-import:C0805")
      (fields
        (field (name "MANUFACTURER") "free choice")
        (field (name "TOLERANCE") "±20 %")
        (field (name "VOLTAGE") "10.0 V")
      )
      (libsource (lib "eagle-import") (part "C-EU-C0805-22U"))
    )
    (comp (ref "C48")
      (value "100n 50V")
      (footprint "eagle-import:C0603")
      (fields
        (field (name "MANUFACTURER") "free choice")
        (field (name "TOLERANCE") "±20 %")
        (field (name "VOLTAGE") "50.0 V")
      )
      (libsource (lib "eagle-import") (part "C-EU-C0603-100N"))
    )
    (comp (ref "C49")
      (value "100n 50V")
      (footprint "eagle-import:C0603")
      (fields
        (field (name "MANUFACTURER") "free choice")
        (field (name "TOLERANCE") "±20 %")
        (field (name "VOLTAGE") "50.0 V")
      )
      (libsource (lib "eagle-import") (part "C-EU-C0603-100N"))
    )
    (comp (ref "C50")
      (value "100n 50V")
      (footprint "eagle-import:C0603")
      (fields
        (field (name "MANUFACTURER") "free choice")
        (field (name "TOLERANCE") "±20 %")
        (field (name "VOLTAGE") "50.0 V")
      )
      (libsource (lib "eagle-import") (part "C-EU-C0603-100N"))
    )
    (comp (ref "C51")
      (value "100n 50V")
      (footprint "eagle-import:C0603")
      (fields
        (field (name "MANUFACTURER") "free choice")
        (field (name "TOLERANCE") "±20 %")
        (field (name "VOLTAGE") "50.0 V")
      )
      (libsource (lib "eagle-import") (part "C-EU-C0603-100N"))
    )
    (comp (ref "C52")
      (value "100n 50V")
      (footprint "eagle-import:C0603")
      (fields
        (field (name "MANUFACTURER") "free choice")
        (field (name "TOLERANCE") "±20 %")
        (field (name "VOLTAGE") "50.0 V")
      )
      (libsource (lib "eagle-import") (part "C-EU-C0603-100N"))
    )
    (comp (ref "C53")
      (value "100n 50V")
      (footprint "eagle-import:C0603")
      (fields
        (field (name "MANUFACTURER") "free choice")
        (field (name "TOLERANCE") "±20 %")
        (field (name "VOLTAGE") "50.0 V")
      )
      (libsource (lib "eagle-import") (part "C-EU-C0603-100N"))
    )
    (comp (ref "C54")
      (value "n.m.")
      (footprint "eagle-import:C1206")
      (fields (field (name "TOLERANCE") "±20 %") (field (name "VOLTAGE") "6V3"))
      (libsource (lib "eagle-import") (part "C-EU-C1206"))
    )
    (comp (ref "C55")
      (value "22u 16V")
      (footprint "eagle-import:C1206")
      (fields
        (field (name "MANUFACTURER") "free choice")
        (field (name "TOLERANCE") "±20 %")
        (field (name "VOLTAGE") "16.0 V")
      )
      (libsource (lib "eagle-import") (part "C-EU-C1206-22U"))
    )
    (comp (ref "C56")
      (value "22u 16V")
      (footprint "eagle-import:C1206")
      (fields
        (field (name "MANUFACTURER") "free choice")
        (field (name "TOLERANCE") "±20 %")
        (field (name "VOLTAGE") "16.0 V")
      )
      (libsource (lib "eagle-import") (part "C-EU-C1206-22U"))
    )
    (comp (ref "C57")
      (value "100n 50V")
      (footprint "eagle-import:C0603")
      (fields
        (field (name "MANUFACTURER") "free choice")
        (field (name "TOLERANCE") "±20 %")
        (field (name "VOLTAGE") "50.0 V")
      )
      (libsource (lib "eagle-import") (part "C-EU-C0603-100N"))
    )
    (comp (ref "C58")
      (value "4u7 16V")
      (footprint "eagle-import:C0805")
      (fields
        (field (name "MANUFACTURER") "free choice")
        (field (name "TOLERANCE") "±20 %")
        (field (name "VOLTAGE") "16.0 V")
      )
      (libsource (lib "eagle-import") (part "C-EU-C0805-4U7"))
    )
    (comp (ref "C59")
      (value "100n 50V")
      (footprint "eagle-import:C0603")
      (fields
        (field (name "MANUFACTURER") "free choice")
        (field (name "TOLERANCE") "±20 %")
        (field (name "VOLTAGE") "50.0 V")
      )
      (libsource (lib "eagle-import") (part "C-EU-C0603-100N"))
    )
    (comp (ref "C78")
      (value "22u 10V")
      (footprint "eagle-import:C0805")
      (fields
        (field (name "MANUFACTURER") "free choice")
        (field (name "TOLERANCE") "±20 %")
        (field (name "VOLTAGE") "10.0 V")
      )
      (libsource (lib "eagle-import") (part "C-EU-C0805-22U"))
    )
    (comp (ref "C100")
      (value "1u 25V")
      (footprint "eagle-import:C0603")
      (fields
        (field (name "MANUFACTURER") "free choice")
        (field (name "TOLERANCE") "±20 %")
        (field (name "VOLTAGE") "25.0 V")
      )
      (libsource (lib "eagle-import") (part "C-EU-C0603-1U"))
    )
    (comp (ref "C101")
      (value "C-EU-C0603")
      (footprint "eagle-import:C0603")
      (fields (field (name "TOLERANCE") "±20 %") (field (name "VOLTAGE") "25.0 V"))
      (libsource (lib "eagle-import") (part "C-EU-C0603"))
    )
    (comp (ref "C102")
      (value "1u 25V")
      (footprint "eagle-import:C0603")
      (fields
        (field (name "MANUFACTURER") "free choice")
        (field (name "TOLERANCE") "±20 %")
        (field (name "VOLTAGE") "25.0 V")
      )
      (libsource (lib "eagle-import") (part "C-EU-C0603-1U"))
    )
    (comp (ref "C103")
      (value "C-EU-C0603")
      (footprint "eagle-import:C0603")
      (fields (field (name "TOLERANCE") "±20 %") (field (name "VOLTAGE") "25.0 V"))
      (libsource (lib "eagle-import") (part "C-EU-C0603"))
    )
    (comp (ref "C104")
      (value "1u 25V")
      (footprint "eagle-import:C0603")
      (fields
        (field (name "MANUFACTURER") "free choice")
        (field (name "TOLERANCE") "±20 %")
        (field (name "VOLTAGE") "25.0 V")
      )
      (libsource (lib "eagle-import") (part "C-EU-C0603-1U"))
    )
    (comp (ref "C105")
      (value "C-EU-C0603")
      (footprint "eagle-import:C0603")
      (fields (field (name "TOLERANCE") "±20 %") (field (name "VOLTAGE") "25.0 V"))
      (libsource (lib "eagle-import") (part "C-EU-C0603"))
    )
    (comp (ref "C106")
      (value "1u 25V")
      (footprint "eagle-import:C0603")
      (fields
        (field (name "MANUFACTURER") "free choice")
        (field (name "TOLERANCE") "±20 %")
        (field (name "VOLTAGE") "25.0 V")
      )
      (libsource (lib "eagle-import") (part "C-EU-C0603-1U"))
    )
    (comp (ref "C107")
      (value "C-EU-C0603")
      (footprint "eagle-import:C0603")
      (fields (field (name "TOLERANCE") "±20 %") (field (name "VOLTAGE") "25.0 V"))
      (libsource (lib "eagle-import") (part "C-EU-C0603"))
    )
    (comp (ref "C108")
      (value "1u 25V")
      (footprint "eagle-import:C0603")
      (fields
        (field (name "MANUFACTURER") "free choice")
        (field (name "TOLERANCE") "±20 %")
        (field (name "VOLTAGE") "25.0 V")
      )
      (libsource (lib "eagle-import") (part "C-EU-C0603-1U"))
    )
    (comp (ref "C109")
      (value "C-EU-C0603")
      (footprint "eagle-import:C0603")
      (fields (field (name "TOLERANCE") "±20 %") (field (name "VOLTAGE") "25.0 V"))
      (libsource (lib "eagle-import") (part "C-EU-C0603"))
    )
    (comp (ref "C110")
      (value "1u 25V")
      (footprint "eagle-import:C0603")
      (fields
        (field (name "MANUFACTURER") "free choice")
        (field (name "TOLERANCE") "±20 %")
        (field (name "VOLTAGE") "25.0 V")
      )
      (libsource (lib "eagle-import") (part "C-EU-C0603-1U"))
    )
    (comp (ref "C111")
      (value "C-EU-C0603")
      (footprint "eagle-import:C0603")
      (fields (field (name "TOLERANCE") "±20 %") (field (name "VOLTAGE") "25.0 V"))
      (libsource (lib "eagle-import") (part "C-EU-C0603"))
    )
    (comp (ref "C112")
      (value "1u 25V")
      (footprint "eagle-import:C0603")
      (fields
        (field (name "MANUFACTURER") "free choice")
        (field (name "TOLERANCE") "±20 %")
        (field (name "VOLTAGE") "25.0 V")
      )
      (libsource (lib "eagle-import") (part "C-EU-C0603-1U"))
    )
    (comp (ref "C113")
      (value "C-EU-C0603")
      (footprint "eagle-import:C0603")
      (fields (field (name "TOLERANCE") "±20 %") (field (name "VOLTAGE") "25.0 V"))
      (libsource (lib "eagle-import") (part "C-EU-C0603"))
    )
    (comp (ref "C114")
      (value "1u 25V")
      (footprint "eagle-import:C0603")
      (fields
        (field (name "MANUFACTURER") "free choice")
        (field (name "TOLERANCE") "±20 %")
        (field (name "VOLTAGE") "25.0 V")
      )
      (libsource (lib "eagle-import") (part "C-EU-C0603-1U"))
    )
    (comp (ref "C115")
      (value "C-EU-C0603")
      (footprint "eagle-import:C0603")
      (fields (field (name "TOLERANCE") "±20 %") (field (name "VOLTAGE") "25.0 V"))
      (libsource (lib "eagle-import") (part "C-EU-C0603"))
    )
    (comp (ref "C116")
      (value "1u 25V")
      (footprint "eagle-import:C0603")
      (fields
        (field (name "MANUFACTURER") "free choice")
        (field (name "TOLERANCE") "±20 %")
        (field (name "VOLTAGE") "25.0 V")
      )
      (libsource (lib "eagle-import") (part "C-EU-C0603-1U"))
    )
    (comp (ref "C117")
      (value "C-EU-C0603")
      (footprint "eagle-import:C0603")
      (fields (field (name "TOLERANCE") "±20 %") (field (name "VOLTAGE") "25.0 V"))
      (libsource (lib "eagle-import") (part "C-EU-C0603"))
    )
    (comp (ref "C118")
      (value "1u 25V")
      (footprint "eagle-import:C0603")
      (fields
        (field (name "MANUFACTURER") "free choice")
        (field (name "TOLERANCE") "±20 %")
        (field (name "VOLTAGE") "25.0 V")
      )
      (libsource (lib "eagle-import") (part "C-EU-C0603-1U"))
    )
    (comp (ref "C119")
      (value "C-EU-C0603")
      (footprint "eagle-import:C0603")
      (fields (field (name "TOLERANCE") "±20 %") (field (name "VOLTAGE") "25.0 V"))
      (libsource (lib "eagle-import") (part "C-EU-C0603"))
    )
    (comp (ref "C120")
      (value "1u 25V")
      (footprint "eagle-import:C0603")
      (fields
        (field (name "MANUFACTURER") "free choice")
        (field (name "TOLERANCE") "±20 %")
        (field (name "VOLTAGE") "25.0 V")
      )
      (libsource (lib "eagle-import") (part "C-EU-C0603-1U"))
    )
    (comp (ref "C121")
      (value "C-EU-C0603")
      (footprint "eagle-import:C0603")
      (fields (field (name "TOLERANCE") "±20 %") (field (name "VOLTAGE") "25.0 V"))
      (libsource (lib "eagle-import") (part "C-EU-C0603"))
    )
    (comp (ref "C122")
      (value "1u 25V")
      (footprint "eagle-import:C0603")
      (fields
        (field (name "MANUFACTURER") "free choice")
        (field (name "TOLERANCE") "±20 %")
        (field (name "VOLTAGE") "25.0 V")
      )
      (libsource (lib "eagle-import") (part "C-EU-C0603-1U"))
    )
    (comp (ref "C123")
      (value "C-EU-C0603")
      (footprint "eagle-import:C0603")
      (fields (field (name "TOLERANCE") "±20 %") (field (name "VOLTAGE") "25.0 V"))
      (libsource (lib "eagle-import") (part "C-EU-C0603"))
    )
    (comp (ref "C124")
      (value "1u 25V")
      (footprint "eagle-import:C0603")
      (fields
        (field (name "MANUFACTURER") "free choice")
        (field (name "TOLERANCE") "±20 %")
        (field (name "VOLTAGE") "25.0 V")
      )
      (libsource (lib "eagle-import") (part "C-EU-C0603-1U"))
    )
    (comp (ref "C125")
      (value "C-EU-C0603")
      (footprint "eagle-import:C0603")
      (fields (field (name "TOLERANCE") "±20 %") (field (name "VOLTAGE") "25.0 V"))
      (libsource (lib "eagle-import") (part "C-EU-C0603"))
    )
    (comp (ref "C126")
      (value "1u 25V")
      (footprint "eagle-import:C0603")
      (fields
        (field (name "MANUFACTURER") "free choice")
        (field (name "TOLERANCE") "±20 %")
        (field (name "VOLTAGE") "25.0 V")
      )
      (libsource (lib "eagle-import") (part "C-EU-C0603-1U"))
    )
    (comp (ref "C127")
      (value "C-EU-C0603")
      (footprint "eagle-import:C0603")
      (fields (field (name "TOLERANCE") "±20 %") (field (name "VOLTAGE") "25.0 V"))
      (libsource (lib "eagle-import") (part "C-EU-C0603"))
    )
    (comp (ref "C128")
      (value "1u 25V")
      (footprint "eagle-import:C0603")
      (fields
        (field (name "MANUFACTURER") "free choice")
        (field (name "TOLERANCE") "±20 %")
        (field (name "VOLTAGE") "25.0 V")
      )
      (libsource (lib "eagle-import") (part "C-EU-C0603-1U"))
    )
    (comp (ref "C129")
      (value "C-EU-C0603")
      (footprint "eagle-import:C0603")
      (fields (field (name "TOLERANCE") "±20 %") (field (name "VOLTAGE") "25.0 V"))
      (libsource (lib "eagle-import") (part "C-EU-C0603"))
    )
    (comp (ref "C130")
      (value "1u 25V")
      (footprint "eagle-import:C0603")
      (fields
        (field (name "MANUFACTURER") "free choice")
        (field (name "TOLERANCE") "±20 %")
        (field (name "VOLTAGE") "25.0 V")
      )
      (libsource (lib "eagle-import") (part "C-EU-C0603-1U"))
    )
    (comp (ref "C131")
      (value "C-EU-C0603")
      (footprint "eagle-import:C0603")
      (fields (field (name "TOLERANCE") "±20 %") (field (name "VOLTAGE") "25.0 V"))
      (libsource (lib "eagle-import") (part "C-EU-C0603"))
    )
    (comp (ref "C132")
      (value "1u 25V")
      (footprint "eagle-import:C0603")
      (fields
        (field (name "MANUFACTURER") "free choice")
        (field (name "TOLERANCE") "±20 %")
        (field (name "VOLTAGE") "25.0 V")
      )
      (libsource (lib "eagle-import") (part "C-EU-C0603-1U"))
    )
    (comp (ref "C133")
      (value "C-EU-C0603")
      (footprint "eagle-import:C0603")
      (fields (field (name "TOLERANCE") "±20 %") (field (name "VOLTAGE") "25.0 V"))
      (libsource (lib "eagle-import") (part "C-EU-C0603"))
    )
    (comp (ref "C134")
      (value "1u 25V")
      (footprint "eagle-import:C0603")
      (fields
        (field (name "MANUFACTURER") "free choice")
        (field (name "TOLERANCE") "±20 %")
        (field (name "VOLTAGE") "25.0 V")
      )
      (libsource (lib "eagle-import") (part "C-EU-C0603-1U"))
    )
    (comp (ref "C135")
      (value "C-EU-C0603")
      (footprint "eagle-import:C0603")
      (fields (field (name "TOLERANCE") "±20 %") (field (name "VOLTAGE") "25.0 V"))
      (libsource (lib "eagle-import") (part "C-EU-C0603"))
    )
    (comp (ref "C136")
      (value "1u 25V")
      (footprint "eagle-import:C0603")
      (fields
        (field (name "MANUFACTURER") "free choice")
        (field (name "TOLERANCE") "±20 %")
        (field (name "VOLTAGE") "25.0 V")
      )
      (libsource (lib "eagle-import") (part "C-EU-C0603-1U"))
    )
    (comp (ref "C137")
      (value "C-EU-C0603")
      (footprint "eagle-import:C0603")
      (fields (field (name "TOLERANCE") "±20 %") (field (name "VOLTAGE") "25.0 V"))
      (libsource (lib "eagle-import") (part "C-EU-C0603"))
    )
    (comp (ref "C138")
      (value "1u 25V")
      (footprint "eagle-import:C0603")
      (fields
        (field (name "MANUFACTURER") "free choice")
        (field (name "TOLERANCE") "±20 %")
        (field (name "VOLTAGE") "25.0 V")
      )
      (libsource (lib "eagle-import") (part "C-EU-C0603-1U"))
    )
    (comp (ref "C139")
      (value "C-EU-C0603")
      (footprint "eagle-import:C0603")
      (fields (field (name "TOLERANCE") "±20 %") (field (name "VOLTAGE") "25.0 V"))
      (libsource (lib "eagle-import") (part "C-EU-C0603"))
    )
    (comp (ref "C140")
      (value "1u 25V")
      (footprint "eagle-import:C0603")
      (fields
        (field (name "MANUFACTURER") "free choice")
        (field (name "TOLERANCE") "±20 %")
        (field (name "VOLTAGE") "25.0 V")
      )
      (libsource (lib "eagle-import") (part "C-EU-C0603-1U"))
    )
    (comp (ref "C141")
      (value "C-EU-C0603")
      (footprint "eagle-import:C0603")
      (fields (field (name "TOLERANCE") "±20 %") (field (name "VOLTAGE") "25.0 V"))
      (libsource (lib "eagle-import") (part "C-EU-C0603"))
    )
    (comp (ref "C142")
      (value "1u 25V")
      (footprint "eagle-import:C0603")
      (fields
        (field (name "MANUFACTURER") "free choice")
        (field (name "TOLERANCE") "±20 %")
        (field (name "VOLTAGE") "25.0 V")
      )
      (libsource (lib "eagle-import") (part "C-EU-C0603-1U"))
    )
    (comp (ref "C143")
      (value "C-EU-C0603")
      (footprint "eagle-import:C0603")
      (fields (field (name "TOLERANCE") "±20 %") (field (name "VOLTAGE") "25.0 V"))
      (libsource (lib "eagle-import") (part "C-EU-C0603"))
    )
    (comp (ref "C144")
      (value "1u 25V")
      (footprint "eagle-import:C0603")
      (fields
        (field (name "MANUFACTURER") "free choice")
        (field (name "TOLERANCE") "±20 %")
        (field (name "VOLTAGE") "25.0 V")
      )
      (libsource (lib "eagle-import") (part "C-EU-C0603-1U"))
    )
    (comp (ref "C145")
      (value "C-EU-C0603")
      (footprint "eagle-import:C0603")
      (fields (field (name "TOLERANCE") "±20 %") (field (name "VOLTAGE") "25.0 V"))
      (libsource (lib "eagle-import") (part "C-EU-C0603"))
    )
    (comp (ref "C146")
      (value "1u 25V")
      (footprint "eagle-import:C0603")
      (fields
        (field (name "MANUFACTURER") "free choice")
        (field (name "TOLERANCE") "±20 %")
        (field (name "VOLTAGE") "25.0 V")
      )
      (libsource (lib "eagle-import") (part "C-EU-C0603-1U"))
    )
    (comp (ref "C147")
      (value "C-EU-C0603")
      (footprint "eagle-import:C0603")
      (fields (field (name "TOLERANCE") "±20 %") (field (name "VOLTAGE") "25.0 V"))
      (libsource (lib "eagle-import") (part "C-EU-C0603"))
    )
    (comp (ref "C148")
      (value "1u 25V")
      (footprint "eagle-import:C0603")
      (fields
        (field (name "MANUFACTURER") "free choice")
        (field (name "TOLERANCE") "±20 %")
        (field (name "VOLTAGE") "25.0 V")
      )
      (libsource (lib "eagle-import") (part "C-EU-C0603-1U"))
    )
    (comp (ref "C149")
      (value "C-EU-C0603")
      (footprint "eagle-import:C0603")
      (fields (field (name "TOLERANCE") "±20 %") (field (name "VOLTAGE") "25.0 V"))
      (libsource (lib "eagle-import") (part "C-EU-C0603"))
    )
    (comp (ref "C150")
      (value "1u 25V")
      (footprint "eagle-import:C0603")
      (fields
        (field (name "MANUFACTURER") "free choice")
        (field (name "TOLERANCE") "±20 %")
        (field (name "VOLTAGE") "25.0 V")
      )
      (libsource (lib "eagle-import") (part "C-EU-C0603-1U"))
    )
    (comp (ref "C151")
      (value "C-EU-C0603")
      (footprint "eagle-import:C0603")
      (fields (field (name "TOLERANCE") "±20 %") (field (name "VOLTAGE") "25.0 V"))
      (libsource (lib "eagle-import") (part "C-EU-C0603"))
    )
    (comp (ref "C152")
      (value "1u 25V")
      (footprint "eagle-import:C0603")
      (fields
        (field (name "MANUFACTURER") "free choice")
        (field (name "TOLERANCE") "±20 %")
        (field (name "VOLTAGE") "25.0 V")
      )
      (libsource (lib "eagle-import") (part "C-EU-C0603-1U"))
    )
    (comp (ref "C153")
      (value "C-EU-C0603")
      (footprint "eagle-import:C0603")
      (fields (field (name "TOLERANCE") "±20 %") (field (name "VOLTAGE") "25.0 V"))
      (libsource (lib "eagle-import") (part "C-EU-C0603"))
    )
    (comp (ref "C154")
      (value "1u 25V")
      (footprint "eagle-import:C0603")
      (fields
        (field (name "MANUFACTURER") "free choice")
        (field (name "TOLERANCE") "±20 %")
        (field (name "VOLTAGE") "25.0 V")
      )
      (libsource (lib "eagle-import") (part "C-EU-C0603-1U"))
    )
    (comp (ref "C155")
      (value "C-EU-C0603")
      (footprint "eagle-import:C0603")
      (fields (field (name "TOLERANCE") "±20 %") (field (name "VOLTAGE") "25.0 V"))
      (libsource (lib "eagle-import") (part "C-EU-C0603"))
    )
    (comp (ref "C156")
      (value "1u 25V")
      (footprint "eagle-import:C0603")
      (fields
        (field (name "MANUFACTURER") "free choice")
        (field (name "TOLERANCE") "±20 %")
        (field (name "VOLTAGE") "25.0 V")
      )
      (libsource (lib "eagle-import") (part "C-EU-C0603-1U"))
    )
    (comp (ref "C157")
      (value "C-EU-C0603")
      (footprint "eagle-import:C0603")
      (fields (field (name "TOLERANCE") "±20 %") (field (name "VOLTAGE") "25.0 V"))
      (libsource (lib "eagle-import") (part "C-EU-C0603"))
    )
    (comp (ref "C158")
      (value "1u 25V")
      (footprint "eagle-import:C0603")
      (fields
        (field (name "MANUFACTURER") "free choice")
        (field (name "TOLERANCE") "±20 %")
        (field (name "VOLTAGE") "25.0 V")
      )
      (libsource (lib "eagle-import") (part "C-EU-C0603-1U"))
    )
    (comp (ref "C159")
      (value "C-EU-C0603")
      (footprint "eagle-import:C0603")
      (fields (field (name "TOLERANCE") "±20 %") (field (name "VOLTAGE") "25.0 V"))
      (libsource (lib "eagle-import") (part "C-EU-C0603"))
    )
    (comp (ref "C162")
      (value "1u 25V")
      (footprint "eagle-import:C0603")
      (fields
        (field (name "MANUFACTURER") "free choice")
        (field (name "TOLERANCE") "±20 %")
        (field (name "VOLTAGE") "25.0 V")
      )
      (libsource (lib "eagle-import") (part "C-EU-C0603-1U"))
    )
    (comp (ref "C164")
      (value "1u 25V")
      (footprint "eagle-import:C0603")
      (fields
        (field (name "MANUFACTURER") "free choice")
        (field (name "TOLERANCE") "±20 %")
        (field (name "VOLTAGE") "25.0 V")
      )
      (libsource (lib "eagle-import") (part "C-EU-C0603-1U"))
    )
    (comp (ref "C165")
      (value "C-EU-C0603")
      (footprint "eagle-import:C0603")
      (fields (field (name "TOLERANCE") "±20 %") (field (name "VOLTAGE") "25.0 V"))
      (libsource (lib "eagle-import") (part "C-EU-C0603"))
    )
    (comp (ref "C166")
      (value "1u 25V")
      (footprint "eagle-import:C0603")
      (fields
        (field (name "MANUFACTURER") "free choice")
        (field (name "TOLERANCE") "±20 %")
        (field (name "VOLTAGE") "25.0 V")
      )
      (libsource (lib "eagle-import") (part "C-EU-C0603-1U"))
    )
    (comp (ref "C167")
      (value "C-EU-C0603")
      (footprint "eagle-import:C0603")
      (fields (field (name "TOLERANCE") "±20 %") (field (name "VOLTAGE") "25.0 V"))
      (libsource (lib "eagle-import") (part "C-EU-C0603"))
    )
    (comp (ref "C168")
      (value "1u 25V")
      (footprint "eagle-import:C0603")
      (fields
        (field (name "MANUFACTURER") "free choice")
        (field (name "TOLERANCE") "±20 %")
        (field (name "VOLTAGE") "25.0 V")
      )
      (libsource (lib "eagle-import") (part "C-EU-C0603-1U"))
    )
    (comp (ref "C169")
      (value "C-EU-C0603")
      (footprint "eagle-import:C0603")
      (fields (field (name "TOLERANCE") "±20 %") (field (name "VOLTAGE") "25.0 V"))
      (libsource (lib "eagle-import") (part "C-EU-C0603"))
    )
    (comp (ref "C170")
      (value "1u 25V")
      (footprint "eagle-import:C0603")
      (fields
        (field (name "MANUFACTURER") "free choice")
        (field (name "TOLERANCE") "±20 %")
        (field (name "VOLTAGE") "25.0 V")
      )
      (libsource (lib "eagle-import") (part "C-EU-C0603-1U"))
    )
    (comp (ref "C171")
      (value "C-EU-C0603")
      (footprint "eagle-import:C0603")
      (fields (field (name "TOLERANCE") "±20 %") (field (name "VOLTAGE") "25.0 V"))
      (libsource (lib "eagle-import") (part "C-EU-C0603"))
    )
    (comp (ref "C172")
      (value "1u 25V")
      (footprint "eagle-import:C0603")
      (fields
        (field (name "MANUFACTURER") "free choice")
        (field (name "TOLERANCE") "±20 %")
        (field (name "VOLTAGE") "25.0 V")
      )
      (libsource (lib "eagle-import") (part "C-EU-C0603-1U"))
    )
    (comp (ref "C173")
      (value "C-EU-C0603")
      (footprint "eagle-import:C0603")
      (fields (field (name "TOLERANCE") "±20 %") (field (name "VOLTAGE") "25.0 V"))
      (libsource (lib "eagle-import") (part "C-EU-C0603"))
    )
    (comp (ref "C174")
      (value "1u 25V")
      (footprint "eagle-import:C0603")
      (fields
        (field (name "MANUFACTURER") "free choice")
        (field (name "TOLERANCE") "±20 %")
        (field (name "VOLTAGE") "25.0 V")
      )
      (libsource (lib "eagle-import") (part "C-EU-C0603-1U"))
    )
    (comp (ref "C175")
      (value "C-EU-C0603")
      (footprint "eagle-import:C0603")
      (fields (field (name "TOLERANCE") "±20 %") (field (name "VOLTAGE") "25.0 V"))
      (libsource (lib "eagle-import") (part "C-EU-C0603"))
    )
    (comp (ref "C176")
      (value "1u 25V")
      (footprint "eagle-import:C0603")
      (fields
        (field (name "MANUFACTURER") "free choice")
        (field (name "TOLERANCE") "±20 %")
        (field (name "VOLTAGE") "25.0 V")
      )
      (libsource (lib "eagle-import") (part "C-EU-C0603-1U"))
    )
    (comp (ref "C177")
      (value "C-EU-C0603")
      (footprint "eagle-import:C0603")
      (fields (field (name "TOLERANCE") "±20 %") (field (name "VOLTAGE") "25.0 V"))
      (libsource (lib "eagle-import") (part "C-EU-C0603"))
    )
    (comp (ref "C178")
      (value "1u 25V")
      (footprint "eagle-import:C0603")
      (fields
        (field (name "MANUFACTURER") "free choice")
        (field (name "TOLERANCE") "±20 %")
        (field (name "VOLTAGE") "25.0 V")
      )
      (libsource (lib "eagle-import") (part "C-EU-C0603-1U"))
    )
    (comp (ref "C179")
      (value "C-EU-C0603")
      (footprint "eagle-import:C0603")
      (fields (field (name "TOLERANCE") "±20 %") (field (name "VOLTAGE") "25.0 V"))
      (libsource (lib "eagle-import") (part "C-EU-C0603"))
    )
    (comp (ref "C180")
      (value "1u 25V")
      (footprint "eagle-import:C0603")
      (fields
        (field (name "MANUFACTURER") "free choice")
        (field (name "TOLERANCE") "±20 %")
        (field (name "VOLTAGE") "25.0 V")
      )
      (libsource (lib "eagle-import") (part "C-EU-C0603-1U"))
    )
    (comp (ref "C181")
      (value "C-EU-C0603")
      (footprint "eagle-import:C0603")
      (fields (field (name "TOLERANCE") "±20 %") (field (name "VOLTAGE") "25.0 V"))
      (libsource (lib "eagle-import") (part "C-EU-C0603"))
    )
    (comp (ref "C182")
      (value "1u 25V")
      (footprint "eagle-import:C0603")
      (fields
        (field (name "MANUFACTURER") "free choice")
        (field (name "TOLERANCE") "±20 %")
        (field (name "VOLTAGE") "25.0 V")
      )
      (libsource (lib "eagle-import") (part "C-EU-C0603-1U"))
    )
    (comp (ref "C183")
      (value "C-EU-C0603")
      (footprint "eagle-import:C0603")
      (fields (field (name "TOLERANCE") "±20 %") (field (name "VOLTAGE") "25.0 V"))
      (libsource (lib "eagle-import") (part "C-EU-C0603"))
    )
    (comp (ref "C184")
      (value "1u 25V")
      (footprint "eagle-import:C0603")
      (fields
        (field (name "MANUFACTURER") "free choice")
        (field (name "TOLERANCE") "±20 %")
        (field (name "VOLTAGE") "25.0 V")
      )
      (libsource (lib "eagle-import") (part "C-EU-C0603-1U"))
    )
    (comp (ref "C185")
      (value "C-EU-C0603")
      (footprint "eagle-import:C0603")
      (fields (field (name "TOLERANCE") "±20 %") (field (name "VOLTAGE") "25.0 V"))
      (libsource (lib "eagle-import") (part "C-EU-C0603"))
    )
    (comp (ref "C186")
      (value "1u 25V")
      (footprint "eagle-import:C0603")
      (fields
        (field (name "MANUFACTURER") "free choice")
        (field (name "TOLERANCE") "±20 %")
        (field (name "VOLTAGE") "25.0 V")
      )
      (libsource (lib "eagle-import") (part "C-EU-C0603-1U"))
    )
    (comp (ref "C187")
      (value "C-EU-C0603")
      (footprint "eagle-import:C0603")
      (fields (field (name "TOLERANCE") "±20 %") (field (name "VOLTAGE") "25.0 V"))
      (libsource (lib "eagle-import") (part "C-EU-C0603"))
    )
    (comp (ref "C188")
      (value "1u 25V")
      (footprint "eagle-import:C0603")
      (fields
        (field (name "MANUFACTURER") "free choice")
        (field (name "TOLERANCE") "±20 %")
        (field (name "VOLTAGE") "25.0 V")
      )
      (libsource (lib "eagle-import") (part "C-EU-C0603-1U"))
    )
    (comp (ref "C189")
      (value "C-EU-C0603")
      (footprint "eagle-import:C0603")
      (fields (field (name "TOLERANCE") "±20 %") (field (name "VOLTAGE") "25.0 V"))
      (libsource (lib "eagle-import") (part "C-EU-C0603"))
    )
    (comp (ref "C190")
      (value "1u 25V")
      (footprint "eagle-import:C0603")
      (fields
        (field (name "MANUFACTURER") "free choice")
        (field (name "TOLERANCE") "±20 %")
        (field (name "VOLTAGE") "25.0 V")
      )
      (libsource (lib "eagle-import") (part "C-EU-C0603-1U"))
    )
    (comp (ref "C191")
      (value "C-EU-C0603")
      (footprint "eagle-import:C0603")
      (fields (field (name "TOLERANCE") "±20 %") (field (name "VOLTAGE") "25.0 V"))
      (libsource (lib "eagle-import") (part "C-EU-C0603"))
    )
    (comp (ref "C192")
      (value "1u 25V")
      (footprint "eagle-import:C0603")
      (fields
        (field (name "MANUFACTURER") "free choice")
        (field (name "TOLERANCE") "±20 %")
        (field (name "VOLTAGE") "25.0 V")
      )
      (libsource (lib "eagle-import") (part "C-EU-C0603-1U"))
    )
    (comp (ref "C193")
      (value "C-EU-C0603")
      (footprint "eagle-import:C0603")
      (fields (field (name "TOLERANCE") "±20 %") (field (name "VOLTAGE") "25.0 V"))
      (libsource (lib "eagle-import") (part "C-EU-C0603"))
    )
    (comp (ref "C194")
      (value "1u 25V")
      (footprint "eagle-import:C0603")
      (fields
        (field (name "MANUFACTURER") "free choice")
        (field (name "TOLERANCE") "±20 %")
        (field (name "VOLTAGE") "25.0 V")
      )
      (libsource (lib "eagle-import") (part "C-EU-C0603-1U"))
    )
    (comp (ref "C195")
      (value "C-EU-C0603")
      (footprint "eagle-import:C0603")
      (fields (field (name "TOLERANCE") "±20 %") (field (name "VOLTAGE") "25.0 V"))
      (libsource (lib "eagle-import") (part "C-EU-C0603"))
    )
    (comp (ref "C196")
      (value "1u 25V")
      (footprint "eagle-import:C0603")
      (fields
        (field (name "MANUFACTURER") "free choice")
        (field (name "TOLERANCE") "±20 %")
        (field (name "VOLTAGE") "25.0 V")
      )
      (libsource (lib "eagle-import") (part "C-EU-C0603-1U"))
    )
    (comp (ref "C197")
      (value "C-EU-C0603")
      (footprint "eagle-import:C0603")
      (fields (field (name "TOLERANCE") "±20 %") (field (name "VOLTAGE") "25.0 V"))
      (libsource (lib "eagle-import") (part "C-EU-C0603"))
    )
    (comp (ref "C198")
      (value "1u 25V")
      (footprint "eagle-import:C0603")
      (fields
        (field (name "MANUFACTURER") "free choice")
        (field (name "TOLERANCE") "±20 %")
        (field (name "VOLTAGE") "25.0 V")
      )
      (libsource (lib "eagle-import") (part "C-EU-C0603-1U"))
    )
    (comp (ref "C199")
      (value "C-EU-C0603")
      (footprint "eagle-import:C0603")
      (fields (field (name "TOLERANCE") "±20 %") (field (name "VOLTAGE") "25.0 V"))
      (libsource (lib "eagle-import") (part "C-EU-C0603"))
    )
    (comp (ref "C200")
      (value "1u 25V")
      (footprint "eagle-import:C0603")
      (fields
        (field (name "MANUFACTURER") "free choice")
        (field (name "TOLERANCE") "±20 %")
        (field (name "VOLTAGE") "25.0 V")
      )
      (libsource (lib "eagle-import") (part "C-EU-C0603-1U"))
    )
    (comp (ref "C201")
      (value "C-EU-C0603")
      (footprint "eagle-import:C0603")
      (fields (field (name "TOLERANCE") "±20 %") (field (name "VOLTAGE") "25.0 V"))
      (libsource (lib "eagle-import") (part "C-EU-C0603"))
    )
    (comp (ref "C202")
      (value "1u 25V")
      (footprint "eagle-import:C0603")
      (fields
        (field (name "MANUFACTURER") "free choice")
        (field (name "TOLERANCE") "±20 %")
        (field (name "VOLTAGE") "25.0 V")
      )
      (libsource (lib "eagle-import") (part "C-EU-C0603-1U"))
    )
    (comp (ref "C203")
      (value "C-EU-C0603")
      (footprint "eagle-import:C0603")
      (fields (field (name "TOLERANCE") "±20 %") (field (name "VOLTAGE") "25.0 V"))
      (libsource (lib "eagle-import") (part "C-EU-C0603"))
    )
    (comp (ref "C204")
      (value "1u 25V")
      (footprint "eagle-import:C0603")
      (fields
        (field (name "MANUFACTURER") "free choice")
        (field (name "TOLERANCE") "±20 %")
        (field (name "VOLTAGE") "25.0 V")
      )
      (libsource (lib "eagle-import") (part "C-EU-C0603-1U"))
    )
    (comp (ref "C205")
      (value "C-EU-C0603")
      (footprint "eagle-import:C0603")
      (fields (field (name "TOLERANCE") "±20 %") (field (name "VOLTAGE") "25.0 V"))
      (libsource (lib "eagle-import") (part "C-EU-C0603"))
    )
    (comp (ref "C206")
      (value "1u 25V")
      (footprint "eagle-import:C0603")
      (fields
        (field (name "MANUFACTURER") "free choice")
        (field (name "TOLERANCE") "±20 %")
        (field (name "VOLTAGE") "25.0 V")
      )
      (libsource (lib "eagle-import") (part "C-EU-C0603-1U"))
    )
    (comp (ref "C207")
      (value "C-EU-C0603")
      (footprint "eagle-import:C0603")
      (fields (field (name "TOLERANCE") "±20 %") (field (name "VOLTAGE") "25.0 V"))
      (libsource (lib "eagle-import") (part "C-EU-C0603"))
    )
    (comp (ref "C208")
      (value "1u 25V")
      (footprint "eagle-import:C0603")
      (fields
        (field (name "MANUFACTURER") "free choice")
        (field (name "TOLERANCE") "±20 %")
        (field (name "VOLTAGE") "25.0 V")
      )
      (libsource (lib "eagle-import") (part "C-EU-C0603-1U"))
    )
    (comp (ref "C209")
      (value "C-EU-C0603")
      (footprint "eagle-import:C0603")
      (fields (field (name "TOLERANCE") "±20 %") (field (name "VOLTAGE") "25.0 V"))
      (libsource (lib "eagle-import") (part "C-EU-C0603"))
    )
    (comp (ref "C210")
      (value "1u 25V")
      (footprint "eagle-import:C0603")
      (fields
        (field (name "MANUFACTURER") "free choice")
        (field (name "TOLERANCE") "±20 %")
        (field (name "VOLTAGE") "25.0 V")
      )
      (libsource (lib "eagle-import") (part "C-EU-C0603-1U"))
    )
    (comp (ref "C211")
      (value "C-EU-C0603")
      (footprint "eagle-import:C0603")
      (fields (field (name "TOLERANCE") "±20 %") (field (name "VOLTAGE") "25.0 V"))
      (libsource (lib "eagle-import") (part "C-EU-C0603"))
    )
    (comp (ref "C212")
      (value "1u 25V")
      (footprint "eagle-import:C0603")
      (fields
        (field (name "MANUFACTURER") "free choice")
        (field (name "TOLERANCE") "±20 %")
        (field (name "VOLTAGE") "25.0 V")
      )
      (libsource (lib "eagle-import") (part "C-EU-C0603-1U"))
    )
    (comp (ref "C213")
      (value "C-EU-C0603")
      (footprint "eagle-import:C0603")
      (fields (field (name "TOLERANCE") "±20 %") (field (name "VOLTAGE") "25.0 V"))
      (libsource (lib "eagle-import") (part "C-EU-C0603"))
    )
    (comp (ref "C214")
      (value "1u 25V")
      (footprint "eagle-import:C0603")
      (fields
        (field (name "MANUFACTURER") "free choice")
        (field (name "TOLERANCE") "±20 %")
        (field (name "VOLTAGE") "25.0 V")
      )
      (libsource (lib "eagle-import") (part "C-EU-C0603-1U"))
    )
    (comp (ref "C215")
      (value "C-EU-C0603")
      (footprint "eagle-import:C0603")
      (fields (field (name "TOLERANCE") "±20 %") (field (name "VOLTAGE") "25.0 V"))
      (libsource (lib "eagle-import") (part "C-EU-C0603"))
    )
    (comp (ref "C216")
      (value "1u 25V")
      (footprint "eagle-import:C0603")
      (fields
        (field (name "MANUFACTURER") "free choice")
        (field (name "TOLERANCE") "±20 %")
        (field (name "VOLTAGE") "25.0 V")
      )
      (libsource (lib "eagle-import") (part "C-EU-C0603-1U"))
    )
    (comp (ref "C217")
      (value "C-EU-C0603")
      (footprint "eagle-import:C0603")
      (fields (field (name "TOLERANCE") "±20 %") (field (name "VOLTAGE") "25.0 V"))
      (libsource (lib "eagle-import") (part "C-EU-C0603"))
    )
    (comp (ref "C218")
      (value "1u 25V")
      (footprint "eagle-import:C0603")
      (fields
        (field (name "MANUFACTURER") "free choice")
        (field (name "TOLERANCE") "±20 %")
        (field (name "VOLTAGE") "25.0 V")
      )
      (libsource (lib "eagle-import") (part "C-EU-C0603-1U"))
    )
    (comp (ref "C219")
      (value "C-EU-C0603")
      (footprint "eagle-import:C0603")
      (fields (field (name "TOLERANCE") "±20 %") (field (name "VOLTAGE") "25.0 V"))
      (libsource (lib "eagle-import") (part "C-EU-C0603"))
    )
    (comp (ref "C220")
      (value "1u 25V")
      (footprint "eagle-import:C0603")
      (fields
        (field (name "MANUFACTURER") "free choice")
        (field (name "TOLERANCE") "±20 %")
        (field (name "VOLTAGE") "25.0 V")
      )
      (libsource (lib "eagle-import") (part "C-EU-C0603-1U"))
    )
    (comp (ref "C221")
      (value "C-EU-C0603")
      (footprint "eagle-import:C0603")
      (fields (field (name "TOLERANCE") "±20 %") (field (name "VOLTAGE") "25.0 V"))
      (libsource (lib "eagle-import") (part "C-EU-C0603"))
    )
    (comp (ref "C222")
      (value "1u 25V")
      (footprint "eagle-import:C0603")
      (fields
        (field (name "MANUFACTURER") "free choice")
        (field (name "TOLERANCE") "±20 %")
        (field (name "VOLTAGE") "25.0 V")
      )
      (libsource (lib "eagle-import") (part "C-EU-C0603-1U"))
    )
    (comp (ref "C223")
      (value "C-EU-C0603")
      (footprint "eagle-import:C0603")
      (fields (field (name "TOLERANCE") "±20 %") (field (name "VOLTAGE") "25.0 V"))
      (libsource (lib "eagle-import") (part "C-EU-C0603"))
    )
    (comp (ref "C224")
      (value "1u 25V")
      (footprint "eagle-import:C0603")
      (fields
        (field (name "MANUFACTURER") "free choice")
        (field (name "TOLERANCE") "±20 %")
        (field (name "VOLTAGE") "25.0 V")
      )
      (libsource (lib "eagle-import") (part "C-EU-C0603-1U"))
    )
    (comp (ref "C225")
      (value "C-EU-C0603")
      (footprint "eagle-import:C0603")
      (fields (field (name "TOLERANCE") "±20 %") (field (name "VOLTAGE") "25.0 V"))
      (libsource (lib "eagle-import") (part "C-EU-C0603"))
    )
    (comp (ref "C226")
      (value "1u 25V")
      (footprint "eagle-import:C0603")
      (fields
        (field (name "MANUFACTURER") "free choice")
        (field (name "TOLERANCE") "±20 %")
        (field (name "VOLTAGE") "25.0 V")
      )
      (libsource (lib "eagle-import") (part "C-EU-C0603-1U"))
    )
    (comp (ref "C227")
      (value "C-EU-C0603")
      (footprint "eagle-import:C0603")
      (fields (field (name "TOLERANCE") "±20 %") (field (name "VOLTAGE") "25.0 V"))
      (libsource (lib "eagle-import") (part "C-EU-C0603"))
    )
    (comp (ref "C228")
      (value "1u 25V")
      (footprint "eagle-import:C0603")
      (fields
        (field (name "MANUFACTURER") "free choice")
        (field (name "TOLERANCE") "±20 %")
        (field (name "VOLTAGE") "25.0 V")
      )
      (libsource (lib "eagle-import") (part "C-EU-C0603-1U"))
    )
    (comp (ref "C229")
      (value "C-EU-C0603")
      (footprint "eagle-import:C0603")
      (fields (field (name "TOLERANCE") "±20 %") (field (name "VOLTAGE") "25.0 V"))
      (libsource (lib "eagle-import") (part "C-EU-C0603"))
    )
    (comp (ref "C230")
      (value "1u 25V")
      (footprint "eagle-import:C0603")
      (fields
        (field (name "MANUFACTURER") "free choice")
        (field (name "TOLERANCE") "±20 %")
        (field (name "VOLTAGE") "25.0 V")
      )
      (libsource (lib "eagle-import") (part "C-EU-C0603-1U"))
    )
    (comp (ref "C231")
      (value "C-EU-C0603")
      (footprint "eagle-import:C0603")
      (fields (field (name "TOLERANCE") "±20 %") (field (name "VOLTAGE") "25.0 V"))
      (libsource (lib "eagle-import") (part "C-EU-C0603"))
    )
    (comp (ref "C232")
      (value "1u 25V")
      (footprint "eagle-import:C0603")
      (fields
        (field (name "MANUFACTURER") "free choice")
        (field (name "TOLERANCE") "±20 %")
        (field (name "VOLTAGE") "25.0 V")
      )
      (libsource (lib "eagle-import") (part "C-EU-C0603-1U"))
    )
    (comp (ref "C233")
      (value "C-EU-C0603")
      (footprint "eagle-import:C0603")
      (fields (field (name "TOLERANCE") "±20 %") (field (name "VOLTAGE") "25.0 V"))
      (libsource (lib "eagle-import") (part "C-EU-C0603"))
    )
    (comp (ref "C234")
      (value "1u 25V")
      (footprint "eagle-import:C0603")
      (fields
        (field (name "MANUFACTURER") "free choice")
        (field (name "TOLERANCE") "±20 %")
        (field (name "VOLTAGE") "25.0 V")
      )
      (libsource (lib "eagle-import") (part "C-EU-C0603-1U"))
    )
    (comp (ref "C235")
      (value "C-EU-C0603")
      (footprint "eagle-import:C0603")
      (fields (field (name "TOLERANCE") "±20 %") (field (name "VOLTAGE") "25.0 V"))
      (libsource (lib "eagle-import") (part "C-EU-C0603"))
    )
    (comp (ref "C236")
      (value "1u 25V")
      (footprint "eagle-import:C0603")
      (fields
        (field (name "MANUFACTURER") "free choice")
        (field (name "TOLERANCE") "±20 %")
        (field (name "VOLTAGE") "25.0 V")
      )
      (libsource (lib "eagle-import") (part "C-EU-C0603-1U"))
    )
    (comp (ref "C237")
      (value "C-EU-C0603")
      (footprint "eagle-import:C0603")
      (fields (field (name "TOLERANCE") "±20 %") (field (name "VOLTAGE") "25.0 V"))
      (libsource (lib "eagle-import") (part "C-EU-C0603"))
    )
    (comp (ref "C238")
      (value "1u 25V")
      (footprint "eagle-import:C0603")
      (fields
        (field (name "MANUFACTURER") "free choice")
        (field (name "TOLERANCE") "±20 %")
        (field (name "VOLTAGE") "25.0 V")
      )
      (libsource (lib "eagle-import") (part "C-EU-C0603-1U"))
    )
    (comp (ref "C239")
      (value "C-EU-C0603")
      (footprint "eagle-import:C0603")
      (fields (field (name "TOLERANCE") "±20 %") (field (name "VOLTAGE") "25.0 V"))
      (libsource (lib "eagle-import") (part "C-EU-C0603"))
    )
    (comp (ref "C240")
      (value "1u 25V")
      (footprint "eagle-import:C0603")
      (fields
        (field (name "MANUFACTURER") "free choice")
        (field (name "TOLERANCE") "±20 %")
        (field (name "VOLTAGE") "25.0 V")
      )
      (libsource (lib "eagle-import") (part "C-EU-C0603-1U"))
    )
    (comp (ref "C241")
      (value "C-EU-C0603")
      (footprint "eagle-import:C0603")
      (fields (field (name "TOLERANCE") "±20 %") (field (name "VOLTAGE") "25.0 V"))
      (libsource (lib "eagle-import") (part "C-EU-C0603"))
    )
    (comp (ref "C242")
      (value "1u 25V")
      (footprint "eagle-import:C0603")
      (fields
        (field (name "MANUFACTURER") "free choice")
        (field (name "TOLERANCE") "±20 %")
        (field (name "VOLTAGE") "25.0 V")
      )
      (libsource (lib "eagle-import") (part "C-EU-C0603-1U"))
    )
    (comp (ref "C243")
      (value "C-EU-C0603")
      (footprint "eagle-import:C0603")
      (fields (field (name "TOLERANCE") "±20 %") (field (name "VOLTAGE") "25.0 V"))
      (libsource (lib "eagle-import") (part "C-EU-C0603"))
    )
    (comp (ref "C244")
      (value "1u 25V")
      (footprint "eagle-import:C0603")
      (fields
        (field (name "MANUFACTURER") "free choice")
        (field (name "TOLERANCE") "±20 %")
        (field (name "VOLTAGE") "25.0 V")
      )
      (libsource (lib "eagle-import") (part "C-EU-C0603-1U"))
    )
    (comp (ref "C245")
      (value "C-EU-C0603")
      (footprint "eagle-import:C0603")
      (fields (field (name "TOLERANCE") "±20 %") (field (name "VOLTAGE") "25.0 V"))
      (libsource (lib "eagle-import") (part "C-EU-C0603"))
    )
    (comp (ref "C246")
      (value "1u 25V")
      (footprint "eagle-import:C0603")
      (fields
        (field (name "MANUFACTURER") "free choice")
        (field (name "TOLERANCE") "±20 %")
        (field (name "VOLTAGE") "25.0 V")
      )
      (libsource (lib "eagle-import") (part "C-EU-C0603-1U"))
    )
    (comp (ref "C247")
      (value "C-EU-C0603")
      (footprint "eagle-import:C0603")
      (fields (field (name "TOLERANCE") "±20 %") (field (name "VOLTAGE") "25.0 V"))
      (libsource (lib "eagle-import") (part "C-EU-C0603"))
    )
    (comp (ref "C248")
      (value "1u 25V")
      (footprint "eagle-import:C0603")
      (fields
        (field (name "MANUFACTURER") "free choice")
        (field (name "TOLERANCE") "±20 %")
        (field (name "VOLTAGE") "25.0 V")
      )
      (libsource (lib "eagle-import") (part "C-EU-C0603-1U"))
    )
    (comp (ref "C249")
      (value "C-EU-C0603")
      (footprint "eagle-import:C0603")
      (fields (field (name "TOLERANCE") "±20 %") (field (name "VOLTAGE") "25.0 V"))
      (libsource (lib "eagle-import") (part "C-EU-C0603"))
    )
    (comp (ref "C250")
      (value "1u 25V")
      (footprint "eagle-import:C0603")
      (fields
        (field (name "MANUFACTURER") "free choice")
        (field (name "TOLERANCE") "±20 %")
        (field (name "VOLTAGE") "25.0 V")
      )
      (libsource (lib "eagle-import") (part "C-EU-C0603-1U"))
    )
    (comp (ref "C251")
      (value "C-EU-C0603")
      (footprint "eagle-import:C0603")
      (fields (field (name "TOLERANCE") "±20 %") (field (name "VOLTAGE") "25.0 V"))
      (libsource (lib "eagle-import") (part "C-EU-C0603"))
    )
    (comp (ref "C252")
      (value "1u 25V")
      (footprint "eagle-import:C0603")
      (fields
        (field (name "MANUFACTURER") "free choice")
        (field (name "TOLERANCE") "±20 %")
        (field (name "VOLTAGE") "25.0 V")
      )
      (libsource (lib "eagle-import") (part "C-EU-C0603-1U"))
    )
    (comp (ref "C253")
      (value "C-EU-C0603")
      (footprint "eagle-import:C0603")
      (fields (field (name "TOLERANCE") "±20 %") (field (name "VOLTAGE") "25.0 V"))
      (libsource (lib "eagle-import") (part "C-EU-C0603"))
    )
    (comp (ref "C254")
      (value "1u 25V")
      (footprint "eagle-import:C0603")
      (fields
        (field (name "MANUFACTURER") "free choice")
        (field (name "TOLERANCE") "±20 %")
        (field (name "VOLTAGE") "25.0 V")
      )
      (libsource (lib "eagle-import") (part "C-EU-C0603-1U"))
    )
    (comp (ref "C255")
      (value "C-EU-C0603")
      (footprint "eagle-import:C0603")
      (fields (field (name "TOLERANCE") "±20 %") (field (name "VOLTAGE") "25.0 V"))
      (libsource (lib "eagle-import") (part "C-EU-C0603"))
    )
    (comp (ref "C256")
      (value "1u 25V")
      (footprint "eagle-import:C0603")
      (fields
        (field (name "MANUFACTURER") "free choice")
        (field (name "TOLERANCE") "±20 %")
        (field (name "VOLTAGE") "25.0 V")
      )
      (libsource (lib "eagle-import") (part "C-EU-C0603-1U"))
    )
    (comp (ref "C257")
      (value "C-EU-C0603")
      (footprint "eagle-import:C0603")
      (fields (field (name "TOLERANCE") "±20 %") (field (name "VOLTAGE") "25.0 V"))
      (libsource (lib "eagle-import") (part "C-EU-C0603"))
    )
    (comp (ref "C258")
      (value "1u 25V")
      (footprint "eagle-import:C0603")
      (fields
        (field (name "MANUFACTURER") "free choice")
        (field (name "TOLERANCE") "±20 %")
        (field (name "VOLTAGE") "25.0 V")
      )
      (libsource (lib "eagle-import") (part "C-EU-C0603-1U"))
    )
    (comp (ref "C259")
      (value "C-EU-C0603")
      (footprint "eagle-import:C0603")
      (fields (field (name "TOLERANCE") "±20 %") (field (name "VOLTAGE") "25.0 V"))
      (libsource (lib "eagle-import") (part "C-EU-C0603"))
    )
    (comp (ref "C260")
      (value "1u 25V")
      (footprint "eagle-import:C0603")
      (fields
        (field (name "MANUFACTURER") "free choice")
        (field (name "TOLERANCE") "±20 %")
        (field (name "VOLTAGE") "25.0 V")
      )
      (libsource (lib "eagle-import") (part "C-EU-C0603-1U"))
    )
    (comp (ref "C261")
      (value "C-EU-C0603")
      (footprint "eagle-import:C0603")
      (fields (field (name "TOLERANCE") "±20 %") (field (name "VOLTAGE") "25.0 V"))
      (libsource (lib "eagle-import") (part "C-EU-C0603"))
    )
    (comp (ref "C262")
      (value "1u 25V")
      (footprint "eagle-import:C0603")
      (fields
        (field (name "MANUFACTURER") "free choice")
        (field (name "TOLERANCE") "±20 %")
        (field (name "VOLTAGE") "25.0 V")
      )
      (libsource (lib "eagle-import") (part "C-EU-C0603-1U"))
    )
    (comp (ref "C263")
      (value "C-EU-C0603")
      (footprint "eagle-import:C0603")
      (fields (field (name "TOLERANCE") "±20 %") (field (name "VOLTAGE") "25.0 V"))
      (libsource (lib "eagle-import") (part "C-EU-C0603"))
    )
    (comp (ref "C264")
      (value "1u 25V")
      (footprint "eagle-import:C0603")
      (fields
        (field (name "MANUFACTURER") "free choice")
        (field (name "TOLERANCE") "±20 %")
        (field (name "VOLTAGE") "25.0 V")
      )
      (libsource (lib "eagle-import") (part "C-EU-C0603-1U"))
    )
    (comp (ref "C265")
      (value "C-EU-C0603")
      (footprint "eagle-import:C0603")
      (fields (field (name "TOLERANCE") "±20 %") (field (name "VOLTAGE") "25.0 V"))
      (libsource (lib "eagle-import") (part "C-EU-C0603"))
    )
    (comp (ref "C266")
      (value "1u 25V")
      (footprint "eagle-import:C0603")
      (fields
        (field (name "MANUFACTURER") "free choice")
        (field (name "TOLERANCE") "±20 %")
        (field (name "VOLTAGE") "25.0 V")
      )
      (libsource (lib "eagle-import") (part "C-EU-C0603-1U"))
    )
    (comp (ref "C270")
      (value "1u 25V")
      (footprint "eagle-import:C0603")
      (fields
        (field (name "MANUFACTURER") "free choice")
        (field (name "TOLERANCE") "±20 %")
        (field (name "VOLTAGE") "25.0 V")
      )
      (libsource (lib "eagle-import") (part "C-EU-C0603-1U"))
    )
    (comp (ref "C272")
      (value "1u 25V")
      (footprint "eagle-import:C0603")
      (fields
        (field (name "MANUFACTURER") "free choice")
        (field (name "TOLERANCE") "±20 %")
        (field (name "VOLTAGE") "25.0 V")
      )
      (libsource (lib "eagle-import") (part "C-EU-C0603-1U"))
    )
    (comp (ref "C280")
      (value "1u 25V")
      (footprint "eagle-import:C0603")
      (fields
        (field (name "MANUFACTURER") "free choice")
        (field (name "TOLERANCE") "±20 %")
        (field (name "VOLTAGE") "25.0 V")
      )
      (libsource (lib "eagle-import") (part "C-EU-C0603-1U"))
    )
    (comp (ref "C281")
      (value "C-EU-C0603")
      (footprint "eagle-import:C0603")
      (fields (field (name "TOLERANCE") "±20 %") (field (name "VOLTAGE") "25.0 V"))
      (libsource (lib "eagle-import") (part "C-EU-C0603"))
    )
    (comp (ref "C282")
      (value "1u 25V")
      (footprint "eagle-import:C0603")
      (fields
        (field (name "MANUFACTURER") "free choice")
        (field (name "TOLERANCE") "±20 %")
        (field (name "VOLTAGE") "25.0 V")
      )
      (libsource (lib "eagle-import") (part "C-EU-C0603-1U"))
    )
    (comp (ref "C283")
      (value "C-EU-C0603")
      (footprint "eagle-import:C0603")
      (fields (field (name "TOLERANCE") "±20 %") (field (name "VOLTAGE") "25.0 V"))
      (libsource (lib "eagle-import") (part "C-EU-C0603"))
    )
    (comp (ref "C284")
      (value "1u 25V")
      (footprint "eagle-import:C0603")
      (fields
        (field (name "MANUFACTURER") "free choice")
        (field (name "TOLERANCE") "±20 %")
        (field (name "VOLTAGE") "25.0 V")
      )
      (libsource (lib "eagle-import") (part "C-EU-C0603-1U"))
    )
    (comp (ref "C285")
      (value "C-EU-C0603")
      (footprint "eagle-import:C0603")
      (fields (field (name "TOLERANCE") "±20 %") (field (name "VOLTAGE") "25.0 V"))
      (libsource (lib "eagle-import") (part "C-EU-C0603"))
    )
    (comp (ref "C286")
      (value "1u 25V")
      (footprint "eagle-import:C0603")
      (fields
        (field (name "MANUFACTURER") "free choice")
        (field (name "TOLERANCE") "±20 %")
        (field (name "VOLTAGE") "25.0 V")
      )
      (libsource (lib "eagle-import") (part "C-EU-C0603-1U"))
    )
    (comp (ref "C287")
      (value "C-EU-C0603")
      (footprint "eagle-import:C0603")
      (fields (field (name "TOLERANCE") "±20 %") (field (name "VOLTAGE") "25.0 V"))
      (libsource (lib "eagle-import") (part "C-EU-C0603"))
    )
    (comp (ref "C288")
      (value "1u 25V")
      (footprint "eagle-import:C0603")
      (fields
        (field (name "MANUFACTURER") "free choice")
        (field (name "TOLERANCE") "±20 %")
        (field (name "VOLTAGE") "25.0 V")
      )
      (libsource (lib "eagle-import") (part "C-EU-C0603-1U"))
    )
    (comp (ref "C289")
      (value "C-EU-C0603")
      (footprint "eagle-import:C0603")
      (fields (field (name "TOLERANCE") "±20 %") (field (name "VOLTAGE") "25.0 V"))
      (libsource (lib "eagle-import") (part "C-EU-C0603"))
    )
    (comp (ref "C290")
      (value "1u 25V")
      (footprint "eagle-import:C0603")
      (fields
        (field (name "MANUFACTURER") "free choice")
        (field (name "TOLERANCE") "±20 %")
        (field (name "VOLTAGE") "25.0 V")
      )
      (libsource (lib "eagle-import") (part "C-EU-C0603-1U"))
    )
    (comp (ref "C291")
      (value "C-EU-C0603")
      (footprint "eagle-import:C0603")
      (fields (field (name "TOLERANCE") "±20 %") (field (name "VOLTAGE") "25.0 V"))
      (libsource (lib "eagle-import") (part "C-EU-C0603"))
    )
    (comp (ref "C292")
      (value "1u 25V")
      (footprint "eagle-import:C0603")
      (fields
        (field (name "MANUFACTURER") "free choice")
        (field (name "TOLERANCE") "±20 %")
        (field (name "VOLTAGE") "25.0 V")
      )
      (libsource (lib "eagle-import") (part "C-EU-C0603-1U"))
    )
    (comp (ref "C293")
      (value "C-EU-C0603")
      (footprint "eagle-import:C0603")
      (fields (field (name "TOLERANCE") "±20 %") (field (name "VOLTAGE") "25.0 V"))
      (libsource (lib "eagle-import") (part "C-EU-C0603"))
    )
    (comp (ref "C294")
      (value "1u 25V")
      (footprint "eagle-import:C0603")
      (fields
        (field (name "MANUFACTURER") "free choice")
        (field (name "TOLERANCE") "±20 %")
        (field (name "VOLTAGE") "25.0 V")
      )
      (libsource (lib "eagle-import") (part "C-EU-C0603-1U"))
    )
    (comp (ref "C295")
      (value "C-EU-C0603")
      (footprint "eagle-import:C0603")
      (fields (field (name "TOLERANCE") "±20 %") (field (name "VOLTAGE") "25.0 V"))
      (libsource (lib "eagle-import") (part "C-EU-C0603"))
    )
    (comp (ref "C296")
      (value "1u 25V")
      (footprint "eagle-import:C0603")
      (fields
        (field (name "MANUFACTURER") "free choice")
        (field (name "TOLERANCE") "±20 %")
        (field (name "VOLTAGE") "25.0 V")
      )
      (libsource (lib "eagle-import") (part "C-EU-C0603-1U"))
    )
    (comp (ref "C297")
      (value "C-EU-C0603")
      (footprint "eagle-import:C0603")
      (fields (field (name "TOLERANCE") "±20 %") (field (name "VOLTAGE") "25.0 V"))
      (libsource (lib "eagle-import") (part "C-EU-C0603"))
    )
    (comp (ref "C298")
      (value "1u 25V")
      (footprint "eagle-import:C0603")
      (fields
        (field (name "MANUFACTURER") "free choice")
        (field (name "TOLERANCE") "±20 %")
        (field (name "VOLTAGE") "25.0 V")
      )
      (libsource (lib "eagle-import") (part "C-EU-C0603-1U"))
    )
    (comp (ref "C299")
      (value "C-EU-C0603")
      (footprint "eagle-import:C0603")
      (fields (field (name "TOLERANCE") "±20 %") (field (name "VOLTAGE") "25.0 V"))
      (libsource (lib "eagle-import") (part "C-EU-C0603"))
    )
    (comp (ref "C300")
      (value "1u 25V")
      (footprint "eagle-import:C0603")
      (fields
        (field (name "MANUFACTURER") "free choice")
        (field (name "TOLERANCE") "±20 %")
        (field (name "VOLTAGE") "25.0 V")
      )
      (libsource (lib "eagle-import") (part "C-EU-C0603-1U"))
    )
    (comp (ref "C301")
      (value "C-EU-C0603")
      (footprint "eagle-import:C0603")
      (fields (field (name "TOLERANCE") "±20 %") (field (name "VOLTAGE") "25.0 V"))
      (libsource (lib "eagle-import") (part "C-EU-C0603"))
    )
    (comp (ref "C302")
      (value "1u 25V")
      (footprint "eagle-import:C0603")
      (fields
        (field (name "MANUFACTURER") "free choice")
        (field (name "TOLERANCE") "±20 %")
        (field (name "VOLTAGE") "25.0 V")
      )
      (libsource (lib "eagle-import") (part "C-EU-C0603-1U"))
    )
    (comp (ref "C303")
      (value "C-EU-C0603")
      (footprint "eagle-import:C0603")
      (fields (field (name "TOLERANCE") "±20 %") (field (name "VOLTAGE") "25.0 V"))
      (libsource (lib "eagle-import") (part "C-EU-C0603"))
    )
    (comp (ref "C304")
      (value "1u 25V")
      (footprint "eagle-import:C0603")
      (fields
        (field (name "MANUFACTURER") "free choice")
        (field (name "TOLERANCE") "±20 %")
        (field (name "VOLTAGE") "25.0 V")
      )
      (libsource (lib "eagle-import") (part "C-EU-C0603-1U"))
    )
    (comp (ref "C305")
      (value "C-EU-C0603")
      (footprint "eagle-import:C0603")
      (fields (field (name "TOLERANCE") "±20 %") (field (name "VOLTAGE") "25.0 V"))
      (libsource (lib "eagle-import") (part "C-EU-C0603"))
    )
    (comp (ref "C306")
      (value "1u 25V")
      (footprint "eagle-import:C0603")
      (fields
        (field (name "MANUFACTURER") "free choice")
        (field (name "TOLERANCE") "±20 %")
        (field (name "VOLTAGE") "25.0 V")
      )
      (libsource (lib "eagle-import") (part "C-EU-C0603-1U"))
    )
    (comp (ref "C307")
      (value "C-EU-C0603")
      (footprint "eagle-import:C0603")
      (fields (field (name "TOLERANCE") "±20 %") (field (name "VOLTAGE") "25.0 V"))
      (libsource (lib "eagle-import") (part "C-EU-C0603"))
    )
    (comp (ref "C308")
      (value "1u 25V")
      (footprint "eagle-import:C0603")
      (fields
        (field (name "MANUFACTURER") "free choice")
        (field (name "TOLERANCE") "±20 %")
        (field (name "VOLTAGE") "25.0 V")
      )
      (libsource (lib "eagle-import") (part "C-EU-C0603-1U"))
    )
    (comp (ref "C309")
      (value "C-EU-C0603")
      (footprint "eagle-import:C0603")
      (fields (field (name "TOLERANCE") "±20 %") (field (name "VOLTAGE") "25.0 V"))
      (libsource (lib "eagle-import") (part "C-EU-C0603"))
    )
    (comp (ref "C310")
      (value "1u 25V")
      (footprint "eagle-import:C0603")
      (fields
        (field (name "MANUFACTURER") "free choice")
        (field (name "TOLERANCE") "±20 %")
        (field (name "VOLTAGE") "25.0 V")
      )
      (libsource (lib "eagle-import") (part "C-EU-C0603-1U"))
    )
    (comp (ref "C311")
      (value "C-EU-C0603")
      (footprint "eagle-import:C0603")
      (fields (field (name "TOLERANCE") "±20 %") (field (name "VOLTAGE") "25.0 V"))
      (libsource (lib "eagle-import") (part "C-EU-C0603"))
    )
    (comp (ref "C312")
      (value "1u 25V")
      (footprint "eagle-import:C0603")
      (fields
        (field (name "MANUFACTURER") "free choice")
        (field (name "TOLERANCE") "±20 %")
        (field (name "VOLTAGE") "25.0 V")
      )
      (libsource (lib "eagle-import") (part "C-EU-C0603-1U"))
    )
    (comp (ref "C313")
      (value "C-EU-C0603")
      (footprint "eagle-import:C0603")
      (fields (field (name "TOLERANCE") "±20 %") (field (name "VOLTAGE") "25.0 V"))
      (libsource (lib "eagle-import") (part "C-EU-C0603"))
    )
    (comp (ref "C314")
      (value "1u 25V")
      (footprint "eagle-import:C0603")
      (fields
        (field (name "MANUFACTURER") "free choice")
        (field (name "TOLERANCE") "±20 %")
        (field (name "VOLTAGE") "25.0 V")
      )
      (libsource (lib "eagle-import") (part "C-EU-C0603-1U"))
    )
    (comp (ref "C315")
      (value "C-EU-C0603")
      (footprint "eagle-import:C0603")
      (fields (field (name "TOLERANCE") "±20 %") (field (name "VOLTAGE") "25.0 V"))
      (libsource (lib "eagle-import") (part "C-EU-C0603"))
    )
    (comp (ref "C316")
      (value "1u 25V")
      (footprint "eagle-import:C0603")
      (fields
        (field (name "MANUFACTURER") "free choice")
        (field (name "TOLERANCE") "±20 %")
        (field (name "VOLTAGE") "25.0 V")
      )
      (libsource (lib "eagle-import") (part "C-EU-C0603-1U"))
    )
    (comp (ref "C317")
      (value "C-EU-C0603")
      (footprint "eagle-import:C0603")
      (fields (field (name "TOLERANCE") "±20 %") (field (name "VOLTAGE") "25.0 V"))
      (libsource (lib "eagle-import") (part "C-EU-C0603"))
    )
    (comp (ref "C318")
      (value "1u 25V")
      (footprint "eagle-import:C0603")
      (fields
        (field (name "MANUFACTURER") "free choice")
        (field (name "TOLERANCE") "±20 %")
        (field (name "VOLTAGE") "25.0 V")
      )
      (libsource (lib "eagle-import") (part "C-EU-C0603-1U"))
    )
    (comp (ref "C319")
      (value "C-EU-C0603")
      (footprint "eagle-import:C0603")
      (fields (field (name "TOLERANCE") "±20 %") (field (name "VOLTAGE") "25.0 V"))
      (libsource (lib "eagle-import") (part "C-EU-C0603"))
    )
    (comp (ref "C320")
      (value "1u 25V")
      (footprint "eagle-import:C0603")
      (fields
        (field (name "MANUFACTURER") "free choice")
        (field (name "TOLERANCE") "±20 %")
        (field (name "VOLTAGE") "25.0 V")
      )
      (libsource (lib "eagle-import") (part "C-EU-C0603-1U"))
    )
    (comp (ref "C321")
      (value "C-EU-C0603")
      (footprint "eagle-import:C0603")
      (fields (field (name "TOLERANCE") "±20 %") (field (name "VOLTAGE") "25.0 V"))
      (libsource (lib "eagle-import") (part "C-EU-C0603"))
    )
    (comp (ref "C322")
      (value "1u 25V")
      (footprint "eagle-import:C0603")
      (fields
        (field (name "MANUFACTURER") "free choice")
        (field (name "TOLERANCE") "±20 %")
        (field (name "VOLTAGE") "25.0 V")
      )
      (libsource (lib "eagle-import") (part "C-EU-C0603-1U"))
    )
    (comp (ref "C323")
      (value "C-EU-C0603")
      (footprint "eagle-import:C0603")
      (fields (field (name "TOLERANCE") "±20 %") (field (name "VOLTAGE") "25.0 V"))
      (libsource (lib "eagle-import") (part "C-EU-C0603"))
    )
    (comp (ref "C324")
      (value "1u 25V")
      (footprint "eagle-import:C0603")
      (fields
        (field (name "MANUFACTURER") "free choice")
        (field (name "TOLERANCE") "±20 %")
        (field (name "VOLTAGE") "25.0 V")
      )
      (libsource (lib "eagle-import") (part "C-EU-C0603-1U"))
    )
    (comp (ref "C325")
      (value "C-EU-C0603")
      (footprint "eagle-import:C0603")
      (fields (field (name "TOLERANCE") "±20 %") (field (name "VOLTAGE") "25.0 V"))
      (libsource (lib "eagle-import") (part "C-EU-C0603"))
    )
    (comp (ref "C326")
      (value "1u 25V")
      (footprint "eagle-import:C0603")
      (fields
        (field (name "MANUFACTURER") "free choice")
        (field (name "TOLERANCE") "±20 %")
        (field (name "VOLTAGE") "25.0 V")
      )
      (libsource (lib "eagle-import") (part "C-EU-C0603-1U"))
    )
    (comp (ref "C327")
      (value "C-EU-C0603")
      (footprint "eagle-import:C0603")
      (fields (field (name "TOLERANCE") "±20 %") (field (name "VOLTAGE") "25.0 V"))
      (libsource (lib "eagle-import") (part "C-EU-C0603"))
    )
    (comp (ref "C328")
      (value "1u 25V")
      (footprint "eagle-import:C0603")
      (fields
        (field (name "MANUFACTURER") "free choice")
        (field (name "TOLERANCE") "±20 %")
        (field (name "VOLTAGE") "25.0 V")
      )
      (libsource (lib "eagle-import") (part "C-EU-C0603-1U"))
    )
    (comp (ref "C329")
      (value "C-EU-C0603")
      (footprint "eagle-import:C0603")
      (fields (field (name "TOLERANCE") "±20 %") (field (name "VOLTAGE") "25.0 V"))
      (libsource (lib "eagle-import") (part "C-EU-C0603"))
    )
    (comp (ref "C330")
      (value "1u 25V")
      (footprint "eagle-import:C0603")
      (fields
        (field (name "MANUFACTURER") "free choice")
        (field (name "TOLERANCE") "±20 %")
        (field (name "VOLTAGE") "25.0 V")
      )
      (libsource (lib "eagle-import") (part "C-EU-C0603-1U"))
    )
    (comp (ref "C331")
      (value "C-EU-C0603")
      (footprint "eagle-import:C0603")
      (fields (field (name "TOLERANCE") "±20 %") (field (name "VOLTAGE") "25.0 V"))
      (libsource (lib "eagle-import") (part "C-EU-C0603"))
    )
    (comp (ref "C332")
      (value "1u 25V")
      (footprint "eagle-import:C0603")
      (fields
        (field (name "MANUFACTURER") "free choice")
        (field (name "TOLERANCE") "±20 %")
        (field (name "VOLTAGE") "25.0 V")
      )
      (libsource (lib "eagle-import") (part "C-EU-C0603-1U"))
    )
    (comp (ref "D1")
      (value "150060RS75000")
      (footprint "eagle-import:WL-SMCW_0603_WE")
      (fields (field (name "MANUFACTURER") "Wuerth") (field (name "VOLTAGE") "5.0 V"))
      (libsource (lib "eagle-import") (part "150060RS75000"))
    )
    (comp (ref "D2")
      (value "150060GS75000")
      (footprint "eagle-import:WL-SMCW_0603_WE")
      (fields (field (name "MANUFACTURER") "Wuerth") (field (name "VOLTAGE") "5.0 V"))
      (libsource (lib "eagle-import") (part "150060GS75000"))
    )
    (comp (ref "D100")
      (value "LZ1-00R302")
      (footprint "eagle-import:LZ1_SMALL_LEDENGIN")
      (fields (field (name "MANUFACTURER") "Osram"))
      (libsource (lib "eagle-import") (part "LZ1-00R302-SMALL"))
    )
    (comp (ref "D101")
      (value "LZ1-00R302")
      (footprint "eagle-import:LZ1_SMALL_LEDENGIN")
      (fields (field (name "MANUFACTURER") "Osram"))
      (libsource (lib "eagle-import") (part "LZ1-00R302-SMALL"))
    )
    (comp (ref "D102")
      (value "LZ1-00R302")
      (footprint "eagle-import:LZ1_SMALL_LEDENGIN")
      (fields (field (name "MANUFACTURER") "Osram"))
      (libsource (lib "eagle-import") (part "LZ1-00R302-SMALL"))
    )
    (comp (ref "D103")
      (value "LZ1-00R302")
      (footprint "eagle-import:LZ1_SMALL_LEDENGIN")
      (fields (field (name "MANUFACTURER") "Osram"))
      (libsource (lib "eagle-import") (part "LZ1-00R302-SMALL"))
    )
    (comp (ref "D104")
      (value "LZ1-00R302")
      (footprint "eagle-import:LZ1_SMALL_LEDENGIN")
      (fields (field (name "MANUFACTURER") "Osram"))
      (libsource (lib "eagle-import") (part "LZ1-00R302-SMALL"))
    )
    (comp (ref "D105")
      (value "LZ1-00R302")
      (footprint "eagle-import:LZ1_SMALL_LEDENGIN")
      (fields (field (name "MANUFACTURER") "Osram"))
      (libsource (lib "eagle-import") (part "LZ1-00R302-SMALL"))
    )
    (comp (ref "D106")
      (value "LZ1-00R302")
      (footprint "eagle-import:LZ1_SMALL_LEDENGIN")
      (fields (field (name "MANUFACTURER") "Osram"))
      (libsource (lib "eagle-import") (part "LZ1-00R302-SMALL"))
    )
    (comp (ref "D107")
      (value "LZ1-00R302")
      (footprint "eagle-import:LZ1_SMALL_LEDENGIN")
      (fields (field (name "MANUFACTURER") "Osram"))
      (libsource (lib "eagle-import") (part "LZ1-00R302-SMALL"))
    )
    (comp (ref "D108")
      (value "LZ1-00R302")
      (footprint "eagle-import:LZ1_SMALL_LEDENGIN")
      (fields (field (name "MANUFACTURER") "Osram"))
      (libsource (lib "eagle-import") (part "LZ1-00R302-SMALL"))
    )
    (comp (ref "D109")
      (value "LZ1-00R302")
      (footprint "eagle-import:LZ1_SMALL_LEDENGIN")
      (fields (field (name "MANUFACTURER") "Osram"))
      (libsource (lib "eagle-import") (part "LZ1-00R302-SMALL"))
    )
    (comp (ref "D110")
      (value "LZ1-00R302")
      (footprint "eagle-import:LZ1_SMALL_LEDENGIN")
      (fields (field (name "MANUFACTURER") "Osram"))
      (libsource (lib "eagle-import") (part "LZ1-00R302-SMALL"))
    )
    (comp (ref "D111")
      (value "LZ1-00R302")
      (footprint "eagle-import:LZ1_SMALL_LEDENGIN")
      (fields (field (name "MANUFACTURER") "Osram"))
      (libsource (lib "eagle-import") (part "LZ1-00R302-SMALL"))
    )
    (comp (ref "D112")
      (value "LZ1-00R302")
      (footprint "eagle-import:LZ1_SMALL_LEDENGIN")
      (fields (field (name "MANUFACTURER") "Osram"))
      (libsource (lib "eagle-import") (part "LZ1-00R302-SMALL"))
    )
    (comp (ref "D200")
      (value "SST-10-IRD-B50-T850")
      (footprint "eagle-import:B50_LUMINUS")
      (fields (field (name "MANUFACTURER") "Luminus") (field (name "VOLTAGE") "5.0 V"))
      (libsource (lib "eagle-import") (part "SST-10-IRD-B50-T850"))
    )
    (comp (ref "D201")
      (value "SST-10-IRD-B50-T850")
      (footprint "eagle-import:B50_LUMINUS")
      (fields (field (name "MANUFACTURER") "Luminus") (field (name "VOLTAGE") "5.0 V"))
      (libsource (lib "eagle-import") (part "SST-10-IRD-B50-T850"))
    )
    (comp (ref "D202")
      (value "SST-10-IRD-B50-T850")
      (footprint "eagle-import:B50_LUMINUS")
      (fields (field (name "MANUFACTURER") "Luminus") (field (name "VOLTAGE") "5.0 V"))
      (libsource (lib "eagle-import") (part "SST-10-IRD-B50-T850"))
    )
    (comp (ref "D203")
      (value "SST-10-IRD-B50-T850")
      (footprint "eagle-import:B50_LUMINUS")
      (fields (field (name "MANUFACTURER") "Luminus") (field (name "VOLTAGE") "5.0 V"))
      (libsource (lib "eagle-import") (part "SST-10-IRD-B50-T850"))
    )
    (comp (ref "D204")
      (value "SST-10-IRD-B50-T850")
      (footprint "eagle-import:B50_LUMINUS")
      (fields (field (name "MANUFACTURER") "Luminus") (field (name "VOLTAGE") "5.0 V"))
      (libsource (lib "eagle-import") (part "SST-10-IRD-B50-T850"))
    )
    (comp (ref "D205")
      (value "SST-10-IRD-B50-T850")
      (footprint "eagle-import:B50_LUMINUS")
      (fields (field (name "MANUFACTURER") "Luminus") (field (name "VOLTAGE") "5.0 V"))
      (libsource (lib "eagle-import") (part "SST-10-IRD-B50-T850"))
    )
    (comp (ref "D206")
      (value "SST-10-IRD-B50-T850")
      (footprint "eagle-import:B50_LUMINUS")
      (fields (field (name "MANUFACTURER") "Luminus") (field (name "VOLTAGE") "5.0 V"))
      (libsource (lib "eagle-import") (part "SST-10-IRD-B50-T850"))
    )
    (comp (ref "D207")
      (value "SST-10-IRD-B50-T850")
      (footprint "eagle-import:B50_LUMINUS")
      (fields (field (name "MANUFACTURER") "Luminus") (field (name "VOLTAGE") "5.0 V"))
      (libsource (lib "eagle-import") (part "SST-10-IRD-B50-T850"))
    )
    (comp (ref "D208")
      (value "SST-10-IRD-B50-T850")
      (footprint "eagle-import:B50_LUMINUS")
      (fields (field (name "MANUFACTURER") "Luminus") (field (name "VOLTAGE") "5.0 V"))
      (libsource (lib "eagle-import") (part "SST-10-IRD-B50-T850"))
    )
    (comp (ref "D209")
      (value "SST-10-IRD-B50-T850")
      (footprint "eagle-import:B50_LUMINUS")
      (fields (field (name "MANUFACTURER") "Luminus") (field (name "VOLTAGE") "5.0 V"))
      (libsource (lib "eagle-import") (part "SST-10-IRD-B50-T850"))
    )
    (comp (ref "D210")
      (value "SST-10-IRD-B50-T850")
      (footprint "eagle-import:B50_LUMINUS")
      (fields (field (name "MANUFACTURER") "Luminus") (field (name "VOLTAGE") "5.0 V"))
      (libsource (lib "eagle-import") (part "SST-10-IRD-B50-T850"))
    )
    (comp (ref "D211")
      (value "SST-10-IRD-B50-T850")
      (footprint "eagle-import:B50_LUMINUS")
      (fields (field (name "MANUFACTURER") "Luminus") (field (name "VOLTAGE") "5.0 V"))
      (libsource (lib "eagle-import") (part "SST-10-IRD-B50-T850"))
    )
    (comp (ref "D212")
      (value "SST-10-IRD-B50-T850")
      (footprint "eagle-import:B50_LUMINUS")
      (fields (field (name "MANUFACTURER") "Luminus") (field (name "VOLTAGE") "5.0 V"))
      (libsource (lib "eagle-import") (part "SST-10-IRD-B50-T850"))
    )
    (comp (ref "D213")
      (value "SST-10-IRD-B50-T850")
      (footprint "eagle-import:B50_LUMINUS")
      (fields (field (name "MANUFACTURER") "Luminus") (field (name "VOLTAGE") "5.0 V"))
      (libsource (lib "eagle-import") (part "SST-10-IRD-B50-T850"))
    )
    (comp (ref "D214")
      (value "SST-10-IRD-B50-T850")
      (footprint "eagle-import:B50_LUMINUS")
      (fields (field (name "MANUFACTURER") "Luminus") (field (name "VOLTAGE") "5.0 V"))
      (libsource (lib "eagle-import") (part "SST-10-IRD-B50-T850"))
    )
    (comp (ref "D215")
      (value "SST-10-IRD-B50-T850")
      (footprint "eagle-import:B50_LUMINUS")
      (fields (field (name "MANUFACTURER") "Luminus") (field (name "VOLTAGE") "5.0 V"))
      (libsource (lib "eagle-import") (part "SST-10-IRD-B50-T850"))
    )
    (comp (ref "D250")
      (value "SST-10-IRD-B50-T850")
      (footprint "eagle-import:B50_LUMINUS")
      (fields (field (name "MANUFACTURER") "Luminus") (field (name "VOLTAGE") "5.0 V"))
      (libsource (lib "eagle-import") (part "SST-10-IRD-B50-T850"))
    )
    (comp (ref "D251")
      (value "SST-10-IRD-B50-T850")
      (footprint "eagle-import:B50_LUMINUS")
      (fields (field (name "MANUFACTURER") "Luminus") (field (name "VOLTAGE") "5.0 V"))
      (libsource (lib "eagle-import") (part "SST-10-IRD-B50-T850"))
    )
    (comp (ref "D252")
      (value "SST-10-IRD-B50-T850")
      (footprint "eagle-import:B50_LUMINUS")
      (fields (field (name "MANUFACTURER") "Luminus") (field (name "VOLTAGE") "5.0 V"))
      (libsource (lib "eagle-import") (part "SST-10-IRD-B50-T850"))
    )
    (comp (ref "D253")
      (value "SST-10-IRD-B50-T850")
      (footprint "eagle-import:B50_LUMINUS")
      (fields (field (name "MANUFACTURER") "Luminus") (field (name "VOLTAGE") "5.0 V"))
      (libsource (lib "eagle-import") (part "SST-10-IRD-B50-T850"))
    )
    (comp (ref "D254")
      (value "SST-10-IRD-B50-T850")
      (footprint "eagle-import:B50_LUMINUS")
      (fields (field (name "MANUFACTURER") "Luminus") (field (name "VOLTAGE") "5.0 V"))
      (libsource (lib "eagle-import") (part "SST-10-IRD-B50-T850"))
    )
    (comp (ref "D255")
      (value "SST-10-IRD-B50-T850")
      (footprint "eagle-import:B50_LUMINUS")
      (fields (field (name "MANUFACTURER") "Luminus") (field (name "VOLTAGE") "5.0 V"))
      (libsource (lib "eagle-import") (part "SST-10-IRD-B50-T850"))
    )
    (comp (ref "D256")
      (value "SST-10-IRD-B50-T850")
      (footprint "eagle-import:B50_LUMINUS")
      (fields (field (name "MANUFACTURER") "Luminus") (field (name "VOLTAGE") "5.0 V"))
      (libsource (lib "eagle-import") (part "SST-10-IRD-B50-T850"))
    )
    (comp (ref "D257")
      (value "SST-10-IRD-B50-T850")
      (footprint "eagle-import:B50_LUMINUS")
      (fields (field (name "MANUFACTURER") "Luminus") (field (name "VOLTAGE") "5.0 V"))
      (libsource (lib "eagle-import") (part "SST-10-IRD-B50-T850"))
    )
    (comp (ref "D258")
      (value "SST-10-IRD-B50-T850")
      (footprint "eagle-import:B50_LUMINUS")
      (fields (field (name "MANUFACTURER") "Luminus") (field (name "VOLTAGE") "5.0 V"))
      (libsource (lib "eagle-import") (part "SST-10-IRD-B50-T850"))
    )
    (comp (ref "D259")
      (value "SST-10-IRD-B50-T850")
      (footprint "eagle-import:B50_LUMINUS")
      (fields (field (name "MANUFACTURER") "Luminus") (field (name "VOLTAGE") "5.0 V"))
      (libsource (lib "eagle-import") (part "SST-10-IRD-B50-T850"))
    )
    (comp (ref "D260")
      (value "SST-10-IRD-B50-T850")
      (footprint "eagle-import:B50_LUMINUS")
      (fields (field (name "MANUFACTURER") "Luminus") (field (name "VOLTAGE") "5.0 V"))
      (libsource (lib "eagle-import") (part "SST-10-IRD-B50-T850"))
    )
    (comp (ref "D261")
      (value "SST-10-IRD-B50-T850")
      (footprint "eagle-import:B50_LUMINUS")
      (fields (field (name "MANUFACTURER") "Luminus") (field (name "VOLTAGE") "5.0 V"))
      (libsource (lib "eagle-import") (part "SST-10-IRD-B50-T850"))
    )
    (comp (ref "D262")
      (value "SST-10-IRD-B50-T850")
      (footprint "eagle-import:B50_LUMINUS")
      (fields (field (name "MANUFACTURER") "Luminus") (field (name "VOLTAGE") "5.0 V"))
      (libsource (lib "eagle-import") (part "SST-10-IRD-B50-T850"))
    )
    (comp (ref "D263")
      (value "SST-10-IRD-B50-T850")
      (footprint "eagle-import:B50_LUMINUS")
      (fields (field (name "MANUFACTURER") "Luminus") (field (name "VOLTAGE") "5.0 V"))
      (libsource (lib "eagle-import") (part "SST-10-IRD-B50-T850"))
    )
    (comp (ref "D264")
      (value "SST-10-IRD-B50-T850")
      (footprint "eagle-import:B50_LUMINUS")
      (fields (field (name "MANUFACTURER") "Luminus") (field (name "VOLTAGE") "5.0 V"))
      (libsource (lib "eagle-import") (part "SST-10-IRD-B50-T850"))
    )
    (comp (ref "D265")
      (value "SST-10-IRD-B50-T850")
      (footprint "eagle-import:B50_LUMINUS")
      (fields (field (name "MANUFACTURER") "Luminus") (field (name "VOLTAGE") "5.0 V"))
      (libsource (lib "eagle-import") (part "SST-10-IRD-B50-T850"))
    )
    (comp (ref "D300")
      (value "SST-10-IRD-B50-S940")
      (footprint "eagle-import:B50_LUMINUS")
      (fields (field (name "MANUFACTURER") "Luminus") (field (name "VOLTAGE") "5.0 V"))
      (libsource (lib "eagle-import") (part "SST-10-IRD-B50-S940"))
    )
    (comp (ref "D301")
      (value "SST-10-IRD-B50-S940")
      (footprint "eagle-import:B50_LUMINUS")
      (fields (field (name "MANUFACTURER") "Luminus") (field (name "VOLTAGE") "5.0 V"))
      (libsource (lib "eagle-import") (part "SST-10-IRD-B50-S940"))
    )
    (comp (ref "D302")
      (value "SST-10-IRD-B50-S940")
      (footprint "eagle-import:B50_LUMINUS")
      (fields (field (name "MANUFACTURER") "Luminus") (field (name "VOLTAGE") "5.0 V"))
      (libsource (lib "eagle-import") (part "SST-10-IRD-B50-S940"))
    )
    (comp (ref "D303")
      (value "SST-10-IRD-B50-S940")
      (footprint "eagle-import:B50_LUMINUS")
      (fields (field (name "MANUFACTURER") "Luminus") (field (name "VOLTAGE") "5.0 V"))
      (libsource (lib "eagle-import") (part "SST-10-IRD-B50-S940"))
    )
    (comp (ref "D304")
      (value "SST-10-IRD-B50-S940")
      (footprint "eagle-import:B50_LUMINUS")
      (fields (field (name "MANUFACTURER") "Luminus") (field (name "VOLTAGE") "5.0 V"))
      (libsource (lib "eagle-import") (part "SST-10-IRD-B50-S940"))
    )
    (comp (ref "D305")
      (value "SST-10-IRD-B50-S940")
      (footprint "eagle-import:B50_LUMINUS")
      (fields (field (name "MANUFACTURER") "Luminus") (field (name "VOLTAGE") "5.0 V"))
      (libsource (lib "eagle-import") (part "SST-10-IRD-B50-S940"))
    )
    (comp (ref "D306")
      (value "SST-10-IRD-B50-S940")
      (footprint "eagle-import:B50_LUMINUS")
      (fields (field (name "MANUFACTURER") "Luminus") (field (name "VOLTAGE") "5.0 V"))
      (libsource (lib "eagle-import") (part "SST-10-IRD-B50-S940"))
    )
    (comp (ref "D307")
      (value "SST-10-IRD-B50-S940")
      (footprint "eagle-import:B50_LUMINUS")
      (fields (field (name "MANUFACTURER") "Luminus") (field (name "VOLTAGE") "5.0 V"))
      (libsource (lib "eagle-import") (part "SST-10-IRD-B50-S940"))
    )
    (comp (ref "D308")
      (value "SST-10-IRD-B50-S940")
      (footprint "eagle-import:B50_LUMINUS")
      (fields (field (name "MANUFACTURER") "Luminus") (field (name "VOLTAGE") "5.0 V"))
      (libsource (lib "eagle-import") (part "SST-10-IRD-B50-S940"))
    )
    (comp (ref "D309")
      (value "SST-10-IRD-B50-S940")
      (footprint "eagle-import:B50_LUMINUS")
      (fields (field (name "MANUFACTURER") "Luminus") (field (name "VOLTAGE") "5.0 V"))
      (libsource (lib "eagle-import") (part "SST-10-IRD-B50-S940"))
    )
    (comp (ref "D310")
      (value "SST-10-IRD-B50-S940")
      (footprint "eagle-import:B50_LUMINUS")
      (fields (field (name "MANUFACTURER") "Luminus") (field (name "VOLTAGE") "5.0 V"))
      (libsource (lib "eagle-import") (part "SST-10-IRD-B50-S940"))
    )
    (comp (ref "D311")
      (value "SST-10-IRD-B50-S940")
      (footprint "eagle-import:B50_LUMINUS")
      (fields (field (name "MANUFACTURER") "Luminus") (field (name "VOLTAGE") "5.0 V"))
      (libsource (lib "eagle-import") (part "SST-10-IRD-B50-S940"))
    )
    (comp (ref "D312")
      (value "SST-10-IRD-B50-S940")
      (footprint "eagle-import:B50_LUMINUS")
      (fields (field (name "MANUFACTURER") "Luminus") (field (name "VOLTAGE") "5.0 V"))
      (libsource (lib "eagle-import") (part "SST-10-IRD-B50-S940"))
    )
    (comp (ref "D313")
      (value "SST-10-IRD-B50-S940")
      (footprint "eagle-import:B50_LUMINUS")
      (fields (field (name "MANUFACTURER") "Luminus") (field (name "VOLTAGE") "5.0 V"))
      (libsource (lib "eagle-import") (part "SST-10-IRD-B50-S940"))
    )
    (comp (ref "D314")
      (value "SST-10-IRD-B50-S940")
      (footprint "eagle-import:B50_LUMINUS")
      (fields (field (name "MANUFACTURER") "Luminus") (field (name "VOLTAGE") "5.0 V"))
      (libsource (lib "eagle-import") (part "SST-10-IRD-B50-S940"))
    )
    (comp (ref "D315")
      (value "SST-10-IRD-B50-S940")
      (footprint "eagle-import:B50_LUMINUS")
      (fields (field (name "MANUFACTURER") "Luminus") (field (name "VOLTAGE") "5.0 V"))
      (libsource (lib "eagle-import") (part "SST-10-IRD-B50-S940"))
    )
    (comp (ref "D350")
      (value "SST-10-IRD-B50-S940")
      (footprint "eagle-import:B50_LUMINUS")
      (fields (field (name "MANUFACTURER") "Luminus") (field (name "VOLTAGE") "5.0 V"))
      (libsource (lib "eagle-import") (part "SST-10-IRD-B50-S940"))
    )
    (comp (ref "D351")
      (value "SST-10-IRD-B50-S940")
      (footprint "eagle-import:B50_LUMINUS")
      (fields (field (name "MANUFACTURER") "Luminus") (field (name "VOLTAGE") "5.0 V"))
      (libsource (lib "eagle-import") (part "SST-10-IRD-B50-S940"))
    )
    (comp (ref "D352")
      (value "SST-10-IRD-B50-S940")
      (footprint "eagle-import:B50_LUMINUS")
      (fields (field (name "MANUFACTURER") "Luminus") (field (name "VOLTAGE") "5.0 V"))
      (libsource (lib "eagle-import") (part "SST-10-IRD-B50-S940"))
    )
    (comp (ref "D353")
      (value "SST-10-IRD-B50-S940")
      (footprint "eagle-import:B50_LUMINUS")
      (fields (field (name "MANUFACTURER") "Luminus") (field (name "VOLTAGE") "5.0 V"))
      (libsource (lib "eagle-import") (part "SST-10-IRD-B50-S940"))
    )
    (comp (ref "D354")
      (value "SST-10-IRD-B50-S940")
      (footprint "eagle-import:B50_LUMINUS")
      (fields (field (name "MANUFACTURER") "Luminus") (field (name "VOLTAGE") "5.0 V"))
      (libsource (lib "eagle-import") (part "SST-10-IRD-B50-S940"))
    )
    (comp (ref "D355")
      (value "SST-10-IRD-B50-S940")
      (footprint "eagle-import:B50_LUMINUS")
      (fields (field (name "MANUFACTURER") "Luminus") (field (name "VOLTAGE") "5.0 V"))
      (libsource (lib "eagle-import") (part "SST-10-IRD-B50-S940"))
    )
    (comp (ref "D356")
      (value "SST-10-IRD-B50-S940")
      (footprint "eagle-import:B50_LUMINUS")
      (fields (field (name "MANUFACTURER") "Luminus") (field (name "VOLTAGE") "5.0 V"))
      (libsource (lib "eagle-import") (part "SST-10-IRD-B50-S940"))
    )
    (comp (ref "D357")
      (value "SST-10-IRD-B50-S940")
      (footprint "eagle-import:B50_LUMINUS")
      (fields (field (name "MANUFACTURER") "Luminus") (field (name "VOLTAGE") "5.0 V"))
      (libsource (lib "eagle-import") (part "SST-10-IRD-B50-S940"))
    )
    (comp (ref "D358")
      (value "SST-10-IRD-B50-S940")
      (footprint "eagle-import:B50_LUMINUS")
      (fields (field (name "MANUFACTURER") "Luminus") (field (name "VOLTAGE") "5.0 V"))
      (libsource (lib "eagle-import") (part "SST-10-IRD-B50-S940"))
    )
    (comp (ref "D359")
      (value "SST-10-IRD-B50-S940")
      (footprint "eagle-import:B50_LUMINUS")
      (fields (field (name "MANUFACTURER") "Luminus") (field (name "VOLTAGE") "5.0 V"))
      (libsource (lib "eagle-import") (part "SST-10-IRD-B50-S940"))
    )
    (comp (ref "D360")
      (value "SST-10-IRD-B50-S940")
      (footprint "eagle-import:B50_LUMINUS")
      (fields (field (name "MANUFACTURER") "Luminus") (field (name "VOLTAGE") "5.0 V"))
      (libsource (lib "eagle-import") (part "SST-10-IRD-B50-S940"))
    )
    (comp (ref "D361")
      (value "SST-10-IRD-B50-S940")
      (footprint "eagle-import:B50_LUMINUS")
      (fields (field (name "MANUFACTURER") "Luminus") (field (name "VOLTAGE") "5.0 V"))
      (libsource (lib "eagle-import") (part "SST-10-IRD-B50-S940"))
    )
    (comp (ref "D362")
      (value "SST-10-IRD-B50-S940")
      (footprint "eagle-import:B50_LUMINUS")
      (fields (field (name "MANUFACTURER") "Luminus") (field (name "VOLTAGE") "5.0 V"))
      (libsource (lib "eagle-import") (part "SST-10-IRD-B50-S940"))
    )
    (comp (ref "D363")
      (value "SST-10-IRD-B50-S940")
      (footprint "eagle-import:B50_LUMINUS")
      (fields (field (name "MANUFACTURER") "Luminus") (field (name "VOLTAGE") "5.0 V"))
      (libsource (lib "eagle-import") (part "SST-10-IRD-B50-S940"))
    )
    (comp (ref "D364")
      (value "SST-10-IRD-B50-S940")
      (footprint "eagle-import:B50_LUMINUS")
      (fields (field (name "MANUFACTURER") "Luminus") (field (name "VOLTAGE") "5.0 V"))
      (libsource (lib "eagle-import") (part "SST-10-IRD-B50-S940"))
    )
    (comp (ref "D365")
      (value "SST-10-IRD-B50-S940")
      (footprint "eagle-import:B50_LUMINUS")
      (fields (field (name "MANUFACTURER") "Luminus") (field (name "VOLTAGE") "5.0 V"))
      (libsource (lib "eagle-import") (part "SST-10-IRD-B50-S940"))
    )
    (comp (ref "IC1")
      (value "UCC27517DBV")
      (footprint "eagle-import:DBV0005A_TI")
      (fields (field (name "MANUFACTURER") "TI") (field (name "VOLTAGE") "18.0 V"))
      (libsource (lib "eagle-import") (part "UCC27517DBV"))
    )
    (comp (ref "IC2")
      (value "UCC27517DBV")
      (footprint "eagle-import:DBV0005A_TI")
      (fields (field (name "MANUFACTURER") "TI") (field (name "VOLTAGE") "18.0 V"))
      (libsource (lib "eagle-import") (part "UCC27517DBV"))
    )
    (comp (ref "IC3")
      (value "LM393BIDSG")
      (footprint "eagle-import:DSG0008A_WSON_TI_NO_VIA")
      (fields (field (name "MANUFACTURER") "TI") (field (name "VOLTAGE") "36.0 V"))
      (libsource (lib "eagle-import") (part "LM393BIDSG_NO_VIA"))
    )
    (comp (ref "IC4")
      (value "LM393BIDSG")
      (footprint "eagle-import:DSG0008A_WSON_TI_NO_VIA")
      (fields (field (name "MANUFACTURER") "TI") (field (name "VOLTAGE") "36.0 V"))
      (libsource (lib "eagle-import") (part "LM393BIDSG_NO_VIA"))
    )
    (comp (ref "IC5")
      (value "LM393BIDSG")
      (footprint "eagle-import:DSG0008A_WSON_TI_NO_VIA")
      (fields (field (name "MANUFACTURER") "TI") (field (name "VOLTAGE") "36.0 V"))
      (libsource (lib "eagle-import") (part "LM393BIDSG_NO_VIA"))
    )
    (comp (ref "IC6")
      (value "SFH9206")
      (footprint "eagle-import:SO6_OSRAM")
      (fields (field (name "MANUFACTURER") "Osram"))
      (libsource (lib "eagle-import") (part "SFH9206"))
    )
    (comp (ref "IC7")
      (value "VL53L1CBV0FY/1")
      (footprint "eagle-import:VL53L1X_STM")
      (fields (field (name "MANUFACTURER") "STM") (field (name "VOLTAGE") "3.5 V"))
      (libsource (lib "eagle-import") (part "VL53L1CBV0FY/1"))
    )
    (comp (ref "IC8")
      (value "UCC27517DBV")
      (footprint "eagle-import:DBV0005A_TI")
      (fields (field (name "MANUFACTURER") "TI") (field (name "VOLTAGE") "18.0 V"))
      (libsource (lib "eagle-import") (part "UCC27517DBV"))
    )
    (comp (ref "IC9")
      (value "SN74LVC112ADGV")
      (footprint "eagle-import:TVSOP-16_TI")
      (fields (field (name "MANUFACTURER") "TI") (field (name "VOLTAGE") "3.6 V"))
      (libsource (lib "eagle-import") (part "SN74LVC112ADGV"))
    )
    (comp (ref "IC10")
      (value "UCC27517DBV")
      (footprint "eagle-import:DBV0005A_TI")
      (fields (field (name "MANUFACTURER") "TI") (field (name "VOLTAGE") "18.0 V"))
      (libsource (lib "eagle-import") (part "UCC27517DBV"))
    )
    (comp (ref "IC11")
      (value "TLV9152IDDF")
      (footprint "eagle-import:DDF0008A_TI")
      (fields (field (name "MANUFACTURER") "TI") (field (name "VOLTAGE") "16.0 V"))
      (libsource (lib "eagle-import") (part "TLV9152DDFI"))
    )
    (comp (ref "IC12")
      (value "824001")
      (footprint "eagle-import:SOT23-6L_WE")
      (fields (field (name "MANUFACTURER") "Wuerth") (field (name "VOLTAGE") "5.0 V"))
      (libsource (lib "eagle-import") (part "824001"))
    )
    (comp (ref "IC13")
      (value "UCC27517DBV")
      (footprint "eagle-import:DBV0005A_TI")
      (fields (field (name "MANUFACTURER") "TI") (field (name "VOLTAGE") "18.0 V"))
      (libsource (lib "eagle-import") (part "UCC27517DBV"))
    )
    (comp (ref "IC14")
      (value "824001")
      (footprint "eagle-import:SOT23-6L_WE")
      (fields (field (name "MANUFACTURER") "Wuerth") (field (name "VOLTAGE") "5.0 V"))
      (libsource (lib "eagle-import") (part "824001"))
    )
    (comp (ref "IC15")
      (value "TMP1075DGK")
      (footprint "eagle-import:S-PDSO-G8_DGK_VSSOP_TI")
      (fields (field (name "MANUFACTURER") "TI") (field (name "VOLTAGE") "5.5 V"))
      (libsource (lib "eagle-import") (part "TMP1075DGK"))
    )
    (comp (ref "IC16")
      (value "824001")
      (footprint "eagle-import:SOT23-6L_WE")
      (fields (field (name "MANUFACTURER") "Wuerth") (field (name "VOLTAGE") "5.0 V"))
      (libsource (lib "eagle-import") (part "824001"))
    )
    (comp (ref "IC17")
      (value "824001")
      (footprint "eagle-import:SOT23-6L_WE")
      (fields (field (name "MANUFACTURER") "Wuerth") (field (name "VOLTAGE") "5.0 V"))
      (libsource (lib "eagle-import") (part "824001"))
    )
    (comp (ref "IC18")
      (value "824001")
      (footprint "eagle-import:SOT23-6L_WE")
      (fields (field (name "MANUFACTURER") "Wuerth") (field (name "VOLTAGE") "5.0 V"))
      (libsource (lib "eagle-import") (part "824001"))
    )
    (comp (ref "IC19")
      (value "824001")
      (footprint "eagle-import:SOT23-6L_WE")
      (fields (field (name "MANUFACTURER") "Wuerth") (field (name "VOLTAGE") "5.0 V"))
      (libsource (lib "eagle-import") (part "824001"))
    )
    (comp (ref "IC20")
      (value "824001")
      (footprint "eagle-import:SOT23-6L_WE")
      (fields (field (name "MANUFACTURER") "Wuerth") (field (name "VOLTAGE") "5.0 V"))
      (libsource (lib "eagle-import") (part "824001"))
    )
    (comp (ref "IC21")
      (value "ESD7016")
      (footprint "eagle-import:UDFN8_3.3X1.0_0.4_ONSEMI")
      (fields (field (name "MANUFACTURER") "Onsemi"))
      (libsource (lib "eagle-import") (part "ESD7016"))
    )
    (comp (ref "IC22")
      (value "ESD7016")
      (footprint "eagle-import:UDFN8_3.3X1.0_0.4_ONSEMI")
      (fields (field (name "MANUFACTURER") "Onsemi"))
      (libsource (lib "eagle-import") (part "ESD7016"))
    )
    (comp (ref "IC23")
      (value "TMUX1209RSV")
      (footprint "eagle-import:RSV0016A_TI")
      (fields (field (name "MANUFACTURER") "TI") (field (name "VOLTAGE") "5.5 V"))
      (libsource (lib "eagle-import") (part "TMUX1209RSV"))
    )
    (comp (ref "IC24")
      (value "TMP112NAIDRL")
      (footprint "eagle-import:DRL0006A_TI")
      (fields (field (name "MANUFACTURER") "TI") (field (name "VOLTAGE") "3.6 V"))
      (libsource (lib "eagle-import") (part "TMP112DRLNAI"))
    )
    (comp (ref "IC25")
      (value "BU27030NUC")
      (footprint "eagle-import:WSON008X2120_ROHM")
      (fields (field (name "MANUFACTURER") "Rohm") (field (name "VOLTAGE") "3.6 V"))
      (libsource (lib "eagle-import") (part "BU27030NUC"))
    )
    (comp (ref "IC100")
      (value "SK6805-EC15")
      (footprint "eagle-import:SK6805-EC_IPIXEL")
      (fields (field (name "MANUFACTURER") "iPixel") (field (name "VOLTAGE") "5.5 V"))
      (libsource (lib "eagle-import") (part "SK6805-EC15"))
    )
    (comp (ref "IC101")
      (value "SK6805-EC15")
      (footprint "eagle-import:SK6805-EC_IPIXEL")
      (fields (field (name "MANUFACTURER") "iPixel") (field (name "VOLTAGE") "5.5 V"))
      (libsource (lib "eagle-import") (part "SK6805-EC15"))
    )
    (comp (ref "IC102")
      (value "SK6805-EC15")
      (footprint "eagle-import:SK6805-EC_IPIXEL")
      (fields (field (name "MANUFACTURER") "iPixel") (field (name "VOLTAGE") "5.5 V"))
      (libsource (lib "eagle-import") (part "SK6805-EC15"))
    )
    (comp (ref "IC103")
      (value "SK6805-EC15")
      (footprint "eagle-import:SK6805-EC_IPIXEL")
      (fields (field (name "MANUFACTURER") "iPixel") (field (name "VOLTAGE") "5.5 V"))
      (libsource (lib "eagle-import") (part "SK6805-EC15"))
    )
    (comp (ref "IC104")
      (value "SK6805-EC15")
      (footprint "eagle-import:SK6805-EC_IPIXEL")
      (fields (field (name "MANUFACTURER") "iPixel") (field (name "VOLTAGE") "5.5 V"))
      (libsource (lib "eagle-import") (part "SK6805-EC15"))
    )
    (comp (ref "IC105")
      (value "SK6805-EC15")
      (footprint "eagle-import:SK6805-EC_IPIXEL")
      (fields (field (name "MANUFACTURER") "iPixel") (field (name "VOLTAGE") "5.5 V"))
      (libsource (lib "eagle-import") (part "SK6805-EC15"))
    )
    (comp (ref "IC106")
      (value "SK6805-EC15")
      (footprint "eagle-import:SK6805-EC_IPIXEL")
      (fields (field (name "MANUFACTURER") "iPixel") (field (name "VOLTAGE") "5.5 V"))
      (libsource (lib "eagle-import") (part "SK6805-EC15"))
    )
    (comp (ref "IC107")
      (value "SK6805-EC15")
      (footprint "eagle-import:SK6805-EC_IPIXEL")
      (fields (field (name "MANUFACTURER") "iPixel") (field (name "VOLTAGE") "5.5 V"))
      (libsource (lib "eagle-import") (part "SK6805-EC15"))
    )
    (comp (ref "IC108")
      (value "SK6805-EC15")
      (footprint "eagle-import:SK6805-EC_IPIXEL")
      (fields (field (name "MANUFACTURER") "iPixel") (field (name "VOLTAGE") "5.5 V"))
      (libsource (lib "eagle-import") (part "SK6805-EC15"))
    )
    (comp (ref "IC109")
      (value "SK6805-EC15")
      (footprint "eagle-import:SK6805-EC_IPIXEL")
      (fields (field (name "MANUFACTURER") "iPixel") (field (name "VOLTAGE") "5.5 V"))
      (libsource (lib "eagle-import") (part "SK6805-EC15"))
    )
    (comp (ref "IC110")
      (value "SK6805-EC15")
      (footprint "eagle-import:SK6805-EC_IPIXEL")
      (fields (field (name "MANUFACTURER") "iPixel") (field (name "VOLTAGE") "5.5 V"))
      (libsource (lib "eagle-import") (part "SK6805-EC15"))
    )
    (comp (ref "IC111")
      (value "SK6805-EC15")
      (footprint "eagle-import:SK6805-EC_IPIXEL")
      (fields (field (name "MANUFACTURER") "iPixel") (field (name "VOLTAGE") "5.5 V"))
      (libsource (lib "eagle-import") (part "SK6805-EC15"))
    )
    (comp (ref "IC112")
      (value "SK6805-EC15")
      (footprint "eagle-import:SK6805-EC_IPIXEL")
      (fields (field (name "MANUFACTURER") "iPixel") (field (name "VOLTAGE") "5.5 V"))
      (libsource (lib "eagle-import") (part "SK6805-EC15"))
    )
    (comp (ref "IC113")
      (value "SK6805-EC15")
      (footprint "eagle-import:SK6805-EC_IPIXEL")
      (fields (field (name "MANUFACTURER") "iPixel") (field (name "VOLTAGE") "5.5 V"))
      (libsource (lib "eagle-import") (part "SK6805-EC15"))
    )
    (comp (ref "IC114")
      (value "SK6805-EC15")
      (footprint "eagle-import:SK6805-EC_IPIXEL")
      (fields (field (name "MANUFACTURER") "iPixel") (field (name "VOLTAGE") "5.5 V"))
      (libsource (lib "eagle-import") (part "SK6805-EC15"))
    )
    (comp (ref "IC115")
      (value "SK6805-EC15")
      (footprint "eagle-import:SK6805-EC_IPIXEL")
      (fields (field (name "MANUFACTURER") "iPixel") (field (name "VOLTAGE") "5.5 V"))
      (libsource (lib "eagle-import") (part "SK6805-EC15"))
    )
    (comp (ref "IC116")
      (value "SK6805-EC15")
      (footprint "eagle-import:SK6805-EC_IPIXEL")
      (fields (field (name "MANUFACTURER") "iPixel") (field (name "VOLTAGE") "5.5 V"))
      (libsource (lib "eagle-import") (part "SK6805-EC15"))
    )
    (comp (ref "IC117")
      (value "SK6805-EC15")
      (footprint "eagle-import:SK6805-EC_IPIXEL")
      (fields (field (name "MANUFACTURER") "iPixel") (field (name "VOLTAGE") "5.5 V"))
      (libsource (lib "eagle-import") (part "SK6805-EC15"))
    )
    (comp (ref "IC118")
      (value "SK6805-EC15")
      (footprint "eagle-import:SK6805-EC_IPIXEL")
      (fields (field (name "MANUFACTURER") "iPixel") (field (name "VOLTAGE") "5.5 V"))
      (libsource (lib "eagle-import") (part "SK6805-EC15"))
    )
    (comp (ref "IC119")
      (value "SK6805-EC15")
      (footprint "eagle-import:SK6805-EC_IPIXEL")
      (fields (field (name "MANUFACTURER") "iPixel") (field (name "VOLTAGE") "5.5 V"))
      (libsource (lib "eagle-import") (part "SK6805-EC15"))
    )
    (comp (ref "IC120")
      (value "SK6805-EC15")
      (footprint "eagle-import:SK6805-EC_IPIXEL")
      (fields (field (name "MANUFACTURER") "iPixel") (field (name "VOLTAGE") "5.5 V"))
      (libsource (lib "eagle-import") (part "SK6805-EC15"))
    )
    (comp (ref "IC121")
      (value "SK6805-EC15")
      (footprint "eagle-import:SK6805-EC_IPIXEL")
      (fields (field (name "MANUFACTURER") "iPixel") (field (name "VOLTAGE") "5.5 V"))
      (libsource (lib "eagle-import") (part "SK6805-EC15"))
    )
    (comp (ref "IC122")
      (value "SK6805-EC15")
      (footprint "eagle-import:SK6805-EC_IPIXEL")
      (fields (field (name "MANUFACTURER") "iPixel") (field (name "VOLTAGE") "5.5 V"))
      (libsource (lib "eagle-import") (part "SK6805-EC15"))
    )
    (comp (ref "IC123")
      (value "SK6805-EC15")
      (footprint "eagle-import:SK6805-EC_IPIXEL")
      (fields (field (name "MANUFACTURER") "iPixel") (field (name "VOLTAGE") "5.5 V"))
      (libsource (lib "eagle-import") (part "SK6805-EC15"))
    )
    (comp (ref "IC124")
      (value "SK6805-EC15")
      (footprint "eagle-import:SK6805-EC_IPIXEL")
      (fields (field (name "MANUFACTURER") "iPixel") (field (name "VOLTAGE") "5.5 V"))
      (libsource (lib "eagle-import") (part "SK6805-EC15"))
    )
    (comp (ref "IC125")
      (value "SK6805-EC15")
      (footprint "eagle-import:SK6805-EC_IPIXEL")
      (fields (field (name "MANUFACTURER") "iPixel") (field (name "VOLTAGE") "5.5 V"))
      (libsource (lib "eagle-import") (part "SK6805-EC15"))
    )
    (comp (ref "IC126")
      (value "SK6805-EC15")
      (footprint "eagle-import:SK6805-EC_IPIXEL")
      (fields (field (name "MANUFACTURER") "iPixel") (field (name "VOLTAGE") "5.5 V"))
      (libsource (lib "eagle-import") (part "SK6805-EC15"))
    )
    (comp (ref "IC127")
      (value "SK6805-EC15")
      (footprint "eagle-import:SK6805-EC_IPIXEL")
      (fields (field (name "MANUFACTURER") "iPixel") (field (name "VOLTAGE") "5.5 V"))
      (libsource (lib "eagle-import") (part "SK6805-EC15"))
    )
    (comp (ref "IC128")
      (value "SK6805-EC15")
      (footprint "eagle-import:SK6805-EC_IPIXEL")
      (fields (field (name "MANUFACTURER") "iPixel") (field (name "VOLTAGE") "5.5 V"))
      (libsource (lib "eagle-import") (part "SK6805-EC15"))
    )
    (comp (ref "IC129")
      (value "SK6805-EC15")
      (footprint "eagle-import:SK6805-EC_IPIXEL")
      (fields (field (name "MANUFACTURER") "iPixel") (field (name "VOLTAGE") "5.5 V"))
      (libsource (lib "eagle-import") (part "SK6805-EC15"))
    )
    (comp (ref "IC130")
      (value "SK6805-EC15")
      (footprint "eagle-import:SK6805-EC_IPIXEL")
      (fields (field (name "MANUFACTURER") "iPixel") (field (name "VOLTAGE") "5.5 V"))
      (libsource (lib "eagle-import") (part "SK6805-EC15"))
    )
    (comp (ref "IC131")
      (value "SK6805-EC15")
      (footprint "eagle-import:SK6805-EC_IPIXEL")
      (fields (field (name "MANUFACTURER") "iPixel") (field (name "VOLTAGE") "5.5 V"))
      (libsource (lib "eagle-import") (part "SK6805-EC15"))
    )
    (comp (ref "IC132")
      (value "SK6805-EC15")
      (footprint "eagle-import:SK6805-EC_IPIXEL")
      (fields (field (name "MANUFACTURER") "iPixel") (field (name "VOLTAGE") "5.5 V"))
      (libsource (lib "eagle-import") (part "SK6805-EC15"))
    )
    (comp (ref "IC133")
      (value "SK6805-EC15")
      (footprint "eagle-import:SK6805-EC_IPIXEL")
      (fields (field (name "MANUFACTURER") "iPixel") (field (name "VOLTAGE") "5.5 V"))
      (libsource (lib "eagle-import") (part "SK6805-EC15"))
    )
    (comp (ref "IC134")
      (value "SK6805-EC15")
      (footprint "eagle-import:SK6805-EC_IPIXEL")
      (fields (field (name "MANUFACTURER") "iPixel") (field (name "VOLTAGE") "5.5 V"))
      (libsource (lib "eagle-import") (part "SK6805-EC15"))
    )
    (comp (ref "IC135")
      (value "SK6805-EC15")
      (footprint "eagle-import:SK6805-EC_IPIXEL")
      (fields (field (name "MANUFACTURER") "iPixel") (field (name "VOLTAGE") "5.5 V"))
      (libsource (lib "eagle-import") (part "SK6805-EC15"))
    )
    (comp (ref "IC136")
      (value "SK6805-EC15")
      (footprint "eagle-import:SK6805-EC_IPIXEL")
      (fields (field (name "MANUFACTURER") "iPixel") (field (name "VOLTAGE") "5.5 V"))
      (libsource (lib "eagle-import") (part "SK6805-EC15"))
    )
    (comp (ref "IC137")
      (value "SK6805-EC15")
      (footprint "eagle-import:SK6805-EC_IPIXEL")
      (fields (field (name "MANUFACTURER") "iPixel") (field (name "VOLTAGE") "5.5 V"))
      (libsource (lib "eagle-import") (part "SK6805-EC15"))
    )
    (comp (ref "IC138")
      (value "SK6805-EC15")
      (footprint "eagle-import:SK6805-EC_IPIXEL")
      (fields (field (name "MANUFACTURER") "iPixel") (field (name "VOLTAGE") "5.5 V"))
      (libsource (lib "eagle-import") (part "SK6805-EC15"))
    )
    (comp (ref "IC139")
      (value "SK6805-EC15")
      (footprint "eagle-import:SK6805-EC_IPIXEL")
      (fields (field (name "MANUFACTURER") "iPixel") (field (name "VOLTAGE") "5.5 V"))
      (libsource (lib "eagle-import") (part "SK6805-EC15"))
    )
    (comp (ref "IC140")
      (value "SK6805-EC15")
      (footprint "eagle-import:SK6805-EC_IPIXEL")
      (fields (field (name "MANUFACTURER") "iPixel") (field (name "VOLTAGE") "5.5 V"))
      (libsource (lib "eagle-import") (part "SK6805-EC15"))
    )
    (comp (ref "IC141")
      (value "SK6805-EC15")
      (footprint "eagle-import:SK6805-EC_IPIXEL")
      (fields (field (name "MANUFACTURER") "iPixel") (field (name "VOLTAGE") "5.5 V"))
      (libsource (lib "eagle-import") (part "SK6805-EC15"))
    )
    (comp (ref "IC142")
      (value "SK6805-EC15")
      (footprint "eagle-import:SK6805-EC_IPIXEL")
      (fields (field (name "MANUFACTURER") "iPixel") (field (name "VOLTAGE") "5.5 V"))
      (libsource (lib "eagle-import") (part "SK6805-EC15"))
    )
    (comp (ref "IC143")
      (value "SK6805-EC15")
      (footprint "eagle-import:SK6805-EC_IPIXEL")
      (fields (field (name "MANUFACTURER") "iPixel") (field (name "VOLTAGE") "5.5 V"))
      (libsource (lib "eagle-import") (part "SK6805-EC15"))
    )
    (comp (ref "IC144")
      (value "SK6805-EC15")
      (footprint "eagle-import:SK6805-EC_IPIXEL")
      (fields (field (name "MANUFACTURER") "iPixel") (field (name "VOLTAGE") "5.5 V"))
      (libsource (lib "eagle-import") (part "SK6805-EC15"))
    )
    (comp (ref "IC145")
      (value "SK6805-EC15")
      (footprint "eagle-import:SK6805-EC_IPIXEL")
      (fields (field (name "MANUFACTURER") "iPixel") (field (name "VOLTAGE") "5.5 V"))
      (libsource (lib "eagle-import") (part "SK6805-EC15"))
    )
    (comp (ref "IC146")
      (value "SK6805-EC15")
      (footprint "eagle-import:SK6805-EC_IPIXEL")
      (fields (field (name "MANUFACTURER") "iPixel") (field (name "VOLTAGE") "5.5 V"))
      (libsource (lib "eagle-import") (part "SK6805-EC15"))
    )
    (comp (ref "IC147")
      (value "SK6805-EC15")
      (footprint "eagle-import:SK6805-EC_IPIXEL")
      (fields (field (name "MANUFACTURER") "iPixel") (field (name "VOLTAGE") "5.5 V"))
      (libsource (lib "eagle-import") (part "SK6805-EC15"))
    )
    (comp (ref "IC148")
      (value "SK6805-EC15")
      (footprint "eagle-import:SK6805-EC_IPIXEL")
      (fields (field (name "MANUFACTURER") "iPixel") (field (name "VOLTAGE") "5.5 V"))
      (libsource (lib "eagle-import") (part "SK6805-EC15"))
    )
    (comp (ref "IC149")
      (value "SK6805-EC15")
      (footprint "eagle-import:SK6805-EC_IPIXEL")
      (fields (field (name "MANUFACTURER") "iPixel") (field (name "VOLTAGE") "5.5 V"))
      (libsource (lib "eagle-import") (part "SK6805-EC15"))
    )
    (comp (ref "IC150")
      (value "SK6805-EC15")
      (footprint "eagle-import:SK6805-EC_IPIXEL")
      (fields (field (name "MANUFACTURER") "iPixel") (field (name "VOLTAGE") "5.5 V"))
      (libsource (lib "eagle-import") (part "SK6805-EC15"))
    )
    (comp (ref "IC151")
      (value "SK6805-EC15")
      (footprint "eagle-import:SK6805-EC_IPIXEL")
      (fields (field (name "MANUFACTURER") "iPixel") (field (name "VOLTAGE") "5.5 V"))
      (libsource (lib "eagle-import") (part "SK6805-EC15"))
    )
    (comp (ref "IC152")
      (value "SK6805-EC15")
      (footprint "eagle-import:SK6805-EC_IPIXEL")
      (fields (field (name "MANUFACTURER") "iPixel") (field (name "VOLTAGE") "5.5 V"))
      (libsource (lib "eagle-import") (part "SK6805-EC15"))
    )
    (comp (ref "IC153")
      (value "SK6805-EC15")
      (footprint "eagle-import:SK6805-EC_IPIXEL")
      (fields (field (name "MANUFACTURER") "iPixel") (field (name "VOLTAGE") "5.5 V"))
      (libsource (lib "eagle-import") (part "SK6805-EC15"))
    )
    (comp (ref "IC154")
      (value "SK6805-EC15")
      (footprint "eagle-import:SK6805-EC_IPIXEL")
      (fields (field (name "MANUFACTURER") "iPixel") (field (name "VOLTAGE") "5.5 V"))
      (libsource (lib "eagle-import") (part "SK6805-EC15"))
    )
    (comp (ref "IC155")
      (value "SK6805-EC15")
      (footprint "eagle-import:SK6805-EC_IPIXEL")
      (fields (field (name "MANUFACTURER") "iPixel") (field (name "VOLTAGE") "5.5 V"))
      (libsource (lib "eagle-import") (part "SK6805-EC15"))
    )
    (comp (ref "IC156")
      (value "SK6805-EC15")
      (footprint "eagle-import:SK6805-EC_IPIXEL")
      (fields (field (name "MANUFACTURER") "iPixel") (field (name "VOLTAGE") "5.5 V"))
      (libsource (lib "eagle-import") (part "SK6805-EC15"))
    )
    (comp (ref "IC157")
      (value "SK6805-EC15")
      (footprint "eagle-import:SK6805-EC_IPIXEL")
      (fields (field (name "MANUFACTURER") "iPixel") (field (name "VOLTAGE") "5.5 V"))
      (libsource (lib "eagle-import") (part "SK6805-EC15"))
    )
    (comp (ref "IC158")
      (value "SK6805-EC15")
      (footprint "eagle-import:SK6805-EC_IPIXEL")
      (fields (field (name "MANUFACTURER") "iPixel") (field (name "VOLTAGE") "5.5 V"))
      (libsource (lib "eagle-import") (part "SK6805-EC15"))
    )
    (comp (ref "IC159")
      (value "SK6805-EC15")
      (footprint "eagle-import:SK6805-EC_IPIXEL")
      (fields (field (name "MANUFACTURER") "iPixel") (field (name "VOLTAGE") "5.5 V"))
      (libsource (lib "eagle-import") (part "SK6805-EC15"))
    )
    (comp (ref "IC160")
      (value "SK6805-EC15")
      (footprint "eagle-import:SK6805-EC_IPIXEL")
      (fields (field (name "MANUFACTURER") "iPixel") (field (name "VOLTAGE") "5.5 V"))
      (libsource (lib "eagle-import") (part "SK6805-EC15"))
    )
    (comp (ref "IC161")
      (value "SK6805-EC15")
      (footprint "eagle-import:SK6805-EC_IPIXEL")
      (fields (field (name "MANUFACTURER") "iPixel") (field (name "VOLTAGE") "5.5 V"))
      (libsource (lib "eagle-import") (part "SK6805-EC15"))
    )
    (comp (ref "IC162")
      (value "SK6805-EC15")
      (footprint "eagle-import:SK6805-EC_IPIXEL")
      (fields (field (name "MANUFACTURER") "iPixel") (field (name "VOLTAGE") "5.5 V"))
      (libsource (lib "eagle-import") (part "SK6805-EC15"))
    )
    (comp (ref "IC163")
      (value "SK6805-EC15")
      (footprint "eagle-import:SK6805-EC_IPIXEL")
      (fields (field (name "MANUFACTURER") "iPixel") (field (name "VOLTAGE") "5.5 V"))
      (libsource (lib "eagle-import") (part "SK6805-EC15"))
    )
    (comp (ref "IC164")
      (value "SK6805-EC15")
      (footprint "eagle-import:SK6805-EC_IPIXEL")
      (fields (field (name "MANUFACTURER") "iPixel") (field (name "VOLTAGE") "5.5 V"))
      (libsource (lib "eagle-import") (part "SK6805-EC15"))
    )
    (comp (ref "IC165")
      (value "SK6805-EC15")
      (footprint "eagle-import:SK6805-EC_IPIXEL")
      (fields (field (name "MANUFACTURER") "iPixel") (field (name "VOLTAGE") "5.5 V"))
      (libsource (lib "eagle-import") (part "SK6805-EC15"))
    )
    (comp (ref "IC166")
      (value "SK6805-EC15")
      (footprint "eagle-import:SK6805-EC_IPIXEL")
      (fields (field (name "MANUFACTURER") "iPixel") (field (name "VOLTAGE") "5.5 V"))
      (libsource (lib "eagle-import") (part "SK6805-EC15"))
    )
    (comp (ref "IC167")
      (value "SK6805-EC15")
      (footprint "eagle-import:SK6805-EC_IPIXEL")
      (fields (field (name "MANUFACTURER") "iPixel") (field (name "VOLTAGE") "5.5 V"))
      (libsource (lib "eagle-import") (part "SK6805-EC15"))
    )
    (comp (ref "IC168")
      (value "SK6805-EC15")
      (footprint "eagle-import:SK6805-EC_IPIXEL")
      (fields (field (name "MANUFACTURER") "iPixel") (field (name "VOLTAGE") "5.5 V"))
      (libsource (lib "eagle-import") (part "SK6805-EC15"))
    )
    (comp (ref "IC169")
      (value "SK6805-EC15")
      (footprint "eagle-import:SK6805-EC_IPIXEL")
      (fields (field (name "MANUFACTURER") "iPixel") (field (name "VOLTAGE") "5.5 V"))
      (libsource (lib "eagle-import") (part "SK6805-EC15"))
    )
    (comp (ref "IC170")
      (value "SK6805-EC15")
      (footprint "eagle-import:SK6805-EC_IPIXEL")
      (fields (field (name "MANUFACTURER") "iPixel") (field (name "VOLTAGE") "5.5 V"))
      (libsource (lib "eagle-import") (part "SK6805-EC15"))
    )
    (comp (ref "IC171")
      (value "SK6805-EC15")
      (footprint "eagle-import:SK6805-EC_IPIXEL")
      (fields (field (name "MANUFACTURER") "iPixel") (field (name "VOLTAGE") "5.5 V"))
      (libsource (lib "eagle-import") (part "SK6805-EC15"))
    )
    (comp (ref "IC172")
      (value "SK6805-EC15")
      (footprint "eagle-import:SK6805-EC_IPIXEL")
      (fields (field (name "MANUFACTURER") "iPixel") (field (name "VOLTAGE") "5.5 V"))
      (libsource (lib "eagle-import") (part "SK6805-EC15"))
    )
    (comp (ref "IC173")
      (value "SK6805-EC15")
      (footprint "eagle-import:SK6805-EC_IPIXEL")
      (fields (field (name "MANUFACTURER") "iPixel") (field (name "VOLTAGE") "5.5 V"))
      (libsource (lib "eagle-import") (part "SK6805-EC15"))
    )
    (comp (ref "IC174")
      (value "SK6805-EC15")
      (footprint "eagle-import:SK6805-EC_IPIXEL")
      (fields (field (name "MANUFACTURER") "iPixel") (field (name "VOLTAGE") "5.5 V"))
      (libsource (lib "eagle-import") (part "SK6805-EC15"))
    )
    (comp (ref "IC175")
      (value "SK6805-EC15")
      (footprint "eagle-import:SK6805-EC_IPIXEL")
      (fields (field (name "MANUFACTURER") "iPixel") (field (name "VOLTAGE") "5.5 V"))
      (libsource (lib "eagle-import") (part "SK6805-EC15"))
    )
    (comp (ref "IC176")
      (value "SK6805-EC15")
      (footprint "eagle-import:SK6805-EC_IPIXEL")
      (fields (field (name "MANUFACTURER") "iPixel") (field (name "VOLTAGE") "5.5 V"))
      (libsource (lib "eagle-import") (part "SK6805-EC15"))
    )
    (comp (ref "IC177")
      (value "SK6805-EC15")
      (footprint "eagle-import:SK6805-EC_IPIXEL")
      (fields (field (name "MANUFACTURER") "iPixel") (field (name "VOLTAGE") "5.5 V"))
      (libsource (lib "eagle-import") (part "SK6805-EC15"))
    )
    (comp (ref "IC178")
      (value "SK6805-EC15")
      (footprint "eagle-import:SK6805-EC_IPIXEL")
      (fields (field (name "MANUFACTURER") "iPixel") (field (name "VOLTAGE") "5.5 V"))
      (libsource (lib "eagle-import") (part "SK6805-EC15"))
    )
    (comp (ref "IC179")
      (value "SK6805-EC15")
      (footprint "eagle-import:SK6805-EC_IPIXEL")
      (fields (field (name "MANUFACTURER") "iPixel") (field (name "VOLTAGE") "5.5 V"))
      (libsource (lib "eagle-import") (part "SK6805-EC15"))
    )
    (comp (ref "IC180")
      (value "SK6805-EC15")
      (footprint "eagle-import:SK6805-EC_IPIXEL")
      (fields (field (name "MANUFACTURER") "iPixel") (field (name "VOLTAGE") "5.5 V"))
      (libsource (lib "eagle-import") (part "SK6805-EC15"))
    )
    (comp (ref "IC181")
      (value "SK6805-EC15")
      (footprint "eagle-import:SK6805-EC_IPIXEL")
      (fields (field (name "MANUFACTURER") "iPixel") (field (name "VOLTAGE") "5.5 V"))
      (libsource (lib "eagle-import") (part "SK6805-EC15"))
    )
    (comp (ref "IC182")
      (value "SK6805-EC15")
      (footprint "eagle-import:SK6805-EC_IPIXEL")
      (fields (field (name "MANUFACTURER") "iPixel") (field (name "VOLTAGE") "5.5 V"))
      (libsource (lib "eagle-import") (part "SK6805-EC15"))
    )
    (comp (ref "IC183")
      (value "SK6805-EC15")
      (footprint "eagle-import:SK6805-EC_IPIXEL")
      (fields (field (name "MANUFACTURER") "iPixel") (field (name "VOLTAGE") "5.5 V"))
      (libsource (lib "eagle-import") (part "SK6805-EC15"))
    )
    (comp (ref "IC184")
      (value "SK6805-EC15")
      (footprint "eagle-import:SK6805-EC_IPIXEL")
      (fields (field (name "MANUFACTURER") "iPixel") (field (name "VOLTAGE") "5.5 V"))
      (libsource (lib "eagle-import") (part "SK6805-EC15"))
    )
    (comp (ref "IC185")
      (value "SK6805-EC15")
      (footprint "eagle-import:SK6805-EC_IPIXEL")
      (fields (field (name "MANUFACTURER") "iPixel") (field (name "VOLTAGE") "5.5 V"))
      (libsource (lib "eagle-import") (part "SK6805-EC15"))
    )
    (comp (ref "IC186")
      (value "SK6805-EC15")
      (footprint "eagle-import:SK6805-EC_IPIXEL")
      (fields (field (name "MANUFACTURER") "iPixel") (field (name "VOLTAGE") "5.5 V"))
      (libsource (lib "eagle-import") (part "SK6805-EC15"))
    )
    (comp (ref "IC187")
      (value "SK6805-EC15")
      (footprint "eagle-import:SK6805-EC_IPIXEL")
      (fields (field (name "MANUFACTURER") "iPixel") (field (name "VOLTAGE") "5.5 V"))
      (libsource (lib "eagle-import") (part "SK6805-EC15"))
    )
    (comp (ref "IC188")
      (value "SK6805-EC15")
      (footprint "eagle-import:SK6805-EC_IPIXEL")
      (fields (field (name "MANUFACTURER") "iPixel") (field (name "VOLTAGE") "5.5 V"))
      (libsource (lib "eagle-import") (part "SK6805-EC15"))
    )
    (comp (ref "IC189")
      (value "SK6805-EC15")
      (footprint "eagle-import:SK6805-EC_IPIXEL")
      (fields (field (name "MANUFACTURER") "iPixel") (field (name "VOLTAGE") "5.5 V"))
      (libsource (lib "eagle-import") (part "SK6805-EC15"))
    )
    (comp (ref "IC190")
      (value "SK6805-EC15")
      (footprint "eagle-import:SK6805-EC_IPIXEL")
      (fields (field (name "MANUFACTURER") "iPixel") (field (name "VOLTAGE") "5.5 V"))
      (libsource (lib "eagle-import") (part "SK6805-EC15"))
    )
    (comp (ref "IC191")
      (value "SK6805-EC15")
      (footprint "eagle-import:SK6805-EC_IPIXEL")
      (fields (field (name "MANUFACTURER") "iPixel") (field (name "VOLTAGE") "5.5 V"))
      (libsource (lib "eagle-import") (part "SK6805-EC15"))
    )
    (comp (ref "IC192")
      (value "SK6805-EC15")
      (footprint "eagle-import:SK6805-EC_IPIXEL")
      (fields (field (name "MANUFACTURER") "iPixel") (field (name "VOLTAGE") "5.5 V"))
      (libsource (lib "eagle-import") (part "SK6805-EC15"))
    )
    (comp (ref "IC193")
      (value "SK6805-EC15")
      (footprint "eagle-import:SK6805-EC_IPIXEL")
      (fields (field (name "MANUFACTURER") "iPixel") (field (name "VOLTAGE") "5.5 V"))
      (libsource (lib "eagle-import") (part "SK6805-EC15"))
    )
    (comp (ref "IC194")
      (value "SK6805-EC15")
      (footprint "eagle-import:SK6805-EC_IPIXEL")
      (fields (field (name "MANUFACTURER") "iPixel") (field (name "VOLTAGE") "5.5 V"))
      (libsource (lib "eagle-import") (part "SK6805-EC15"))
    )
    (comp (ref "IC195")
      (value "SK6805-EC15")
      (footprint "eagle-import:SK6805-EC_IPIXEL")
      (fields (field (name "MANUFACTURER") "iPixel") (field (name "VOLTAGE") "5.5 V"))
      (libsource (lib "eagle-import") (part "SK6805-EC15"))
    )
    (comp (ref "IC196")
      (value "SK6805-EC15")
      (footprint "eagle-import:SK6805-EC_IPIXEL")
      (fields (field (name "MANUFACTURER") "iPixel") (field (name "VOLTAGE") "5.5 V"))
      (libsource (lib "eagle-import") (part "SK6805-EC15"))
    )
    (comp (ref "IC197")
      (value "SK6805-EC15")
      (footprint "eagle-import:SK6805-EC_IPIXEL")
      (fields (field (name "MANUFACTURER") "iPixel") (field (name "VOLTAGE") "5.5 V"))
      (libsource (lib "eagle-import") (part "SK6805-EC15"))
    )
    (comp (ref "IC198")
      (value "SK6805-EC15")
      (footprint "eagle-import:SK6805-EC_IPIXEL")
      (fields (field (name "MANUFACTURER") "iPixel") (field (name "VOLTAGE") "5.5 V"))
      (libsource (lib "eagle-import") (part "SK6805-EC15"))
    )
    (comp (ref "IC199")
      (value "SK6805-EC15")
      (footprint "eagle-import:SK6805-EC_IPIXEL")
      (fields (field (name "MANUFACTURER") "iPixel") (field (name "VOLTAGE") "5.5 V"))
      (libsource (lib "eagle-import") (part "SK6805-EC15"))
    )
    (comp (ref "IC200")
      (value "SK6805-EC15")
      (footprint "eagle-import:SK6805-EC_IPIXEL")
      (fields (field (name "MANUFACTURER") "iPixel") (field (name "VOLTAGE") "5.5 V"))
      (libsource (lib "eagle-import") (part "SK6805-EC15"))
    )
    (comp (ref "IC201")
      (value "SK6805-EC15")
      (footprint "eagle-import:SK6805-EC_IPIXEL")
      (fields (field (name "MANUFACTURER") "iPixel") (field (name "VOLTAGE") "5.5 V"))
      (libsource (lib "eagle-import") (part "SK6805-EC15"))
    )
    (comp (ref "IC202")
      (value "SK6805-EC15")
      (footprint "eagle-import:SK6805-EC_IPIXEL")
      (fields (field (name "MANUFACTURER") "iPixel") (field (name "VOLTAGE") "5.5 V"))
      (libsource (lib "eagle-import") (part "SK6805-EC15"))
    )
    (comp (ref "IC203")
      (value "SK6805-EC15")
      (footprint "eagle-import:SK6805-EC_IPIXEL")
      (fields (field (name "MANUFACTURER") "iPixel") (field (name "VOLTAGE") "5.5 V"))
      (libsource (lib "eagle-import") (part "SK6805-EC15"))
    )
    (comp (ref "IC204")
      (value "SK6805-EC15")
      (footprint "eagle-import:SK6805-EC_IPIXEL")
      (fields (field (name "MANUFACTURER") "iPixel") (field (name "VOLTAGE") "5.5 V"))
      (libsource (lib "eagle-import") (part "SK6805-EC15"))
    )
    (comp (ref "IC205")
      (value "SK6805-EC15")
      (footprint "eagle-import:SK6805-EC_IPIXEL")
      (fields (field (name "MANUFACTURER") "iPixel") (field (name "VOLTAGE") "5.5 V"))
      (libsource (lib "eagle-import") (part "SK6805-EC15"))
    )
    (comp (ref "IC206")
      (value "SK6805-EC15")
      (footprint "eagle-import:SK6805-EC_IPIXEL")
      (fields (field (name "MANUFACTURER") "iPixel") (field (name "VOLTAGE") "5.5 V"))
      (libsource (lib "eagle-import") (part "SK6805-EC15"))
    )
    (comp (ref "IC207")
      (value "SK6805-EC15")
      (footprint "eagle-import:SK6805-EC_IPIXEL")
      (fields (field (name "MANUFACTURER") "iPixel") (field (name "VOLTAGE") "5.5 V"))
      (libsource (lib "eagle-import") (part "SK6805-EC15"))
    )
    (comp (ref "IC208")
      (value "SK6805-EC15")
      (footprint "eagle-import:SK6805-EC_IPIXEL")
      (fields (field (name "MANUFACTURER") "iPixel") (field (name "VOLTAGE") "5.5 V"))
      (libsource (lib "eagle-import") (part "SK6805-EC15"))
    )
    (comp (ref "IC209")
      (value "SK6805-EC15")
      (footprint "eagle-import:SK6805-EC_IPIXEL")
      (fields (field (name "MANUFACTURER") "iPixel") (field (name "VOLTAGE") "5.5 V"))
      (libsource (lib "eagle-import") (part "SK6805-EC15"))
    )
    (comp (ref "IC210")
      (value "SK6805-EC15")
      (footprint "eagle-import:SK6805-EC_IPIXEL")
      (fields (field (name "MANUFACTURER") "iPixel") (field (name "VOLTAGE") "5.5 V"))
      (libsource (lib "eagle-import") (part "SK6805-EC15"))
    )
    (comp (ref "IC211")
      (value "SK6805-EC15")
      (footprint "eagle-import:SK6805-EC_IPIXEL")
      (fields (field (name "MANUFACTURER") "iPixel") (field (name "VOLTAGE") "5.5 V"))
      (libsource (lib "eagle-import") (part "SK6805-EC15"))
    )
    (comp (ref "IC212")
      (value "SK6805-EC15")
      (footprint "eagle-import:SK6805-EC_IPIXEL")
      (fields (field (name "MANUFACTURER") "iPixel") (field (name "VOLTAGE") "5.5 V"))
      (libsource (lib "eagle-import") (part "SK6805-EC15"))
    )
    (comp (ref "IC213")
      (value "SK6805-EC15")
      (footprint "eagle-import:SK6805-EC_IPIXEL")
      (fields (field (name "MANUFACTURER") "iPixel") (field (name "VOLTAGE") "5.5 V"))
      (libsource (lib "eagle-import") (part "SK6805-EC15"))
    )
    (comp (ref "IC214")
      (value "SK6805-EC15")
      (footprint "eagle-import:SK6805-EC_IPIXEL")
      (fields (field (name "MANUFACTURER") "iPixel") (field (name "VOLTAGE") "5.5 V"))
      (libsource (lib "eagle-import") (part "SK6805-EC15"))
    )
    (comp (ref "IC215")
      (value "SK6805-EC15")
      (footprint "eagle-import:SK6805-EC_IPIXEL")
      (fields (field (name "MANUFACTURER") "iPixel") (field (name "VOLTAGE") "5.5 V"))
      (libsource (lib "eagle-import") (part "SK6805-EC15"))
    )
    (comp (ref "IC216")
      (value "SK6805-EC15")
      (footprint "eagle-import:SK6805-EC_IPIXEL")
      (fields (field (name "MANUFACTURER") "iPixel") (field (name "VOLTAGE") "5.5 V"))
      (libsource (lib "eagle-import") (part "SK6805-EC15"))
    )
    (comp (ref "IC217")
      (value "SK6805-EC15")
      (footprint "eagle-import:SK6805-EC_IPIXEL")
      (fields (field (name "MANUFACTURER") "iPixel") (field (name "VOLTAGE") "5.5 V"))
      (libsource (lib "eagle-import") (part "SK6805-EC15"))
    )
    (comp (ref "IC218")
      (value "SK6805-EC15")
      (footprint "eagle-import:SK6805-EC_IPIXEL")
      (fields (field (name "MANUFACTURER") "iPixel") (field (name "VOLTAGE") "5.5 V"))
      (libsource (lib "eagle-import") (part "SK6805-EC15"))
    )
    (comp (ref "IC219")
      (value "SK6805-EC15")
      (footprint "eagle-import:SK6805-EC_IPIXEL")
      (fields (field (name "MANUFACTURER") "iPixel") (field (name "VOLTAGE") "5.5 V"))
      (libsource (lib "eagle-import") (part "SK6805-EC15"))
    )
    (comp (ref "IC220")
      (value "SK6805-EC15")
      (footprint "eagle-import:SK6805-EC_IPIXEL")
      (fields (field (name "MANUFACTURER") "iPixel") (field (name "VOLTAGE") "5.5 V"))
      (libsource (lib "eagle-import") (part "SK6805-EC15"))
    )
    (comp (ref "IC221")
      (value "SK6805-EC15")
      (footprint "eagle-import:SK6805-EC_IPIXEL")
      (fields (field (name "MANUFACTURER") "iPixel") (field (name "VOLTAGE") "5.5 V"))
      (libsource (lib "eagle-import") (part "SK6805-EC15"))
    )
    (comp (ref "IC222")
      (value "SK6805-EC15")
      (footprint "eagle-import:SK6805-EC_IPIXEL")
      (fields (field (name "MANUFACTURER") "iPixel") (field (name "VOLTAGE") "5.5 V"))
      (libsource (lib "eagle-import") (part "SK6805-EC15"))
    )
    (comp (ref "IC223")
      (value "SK6805-EC15")
      (footprint "eagle-import:SK6805-EC_IPIXEL")
      (fields (field (name "MANUFACTURER") "iPixel") (field (name "VOLTAGE") "5.5 V"))
      (libsource (lib "eagle-import") (part "SK6805-EC15"))
    )
    (comp (ref "IC224")
      (value "SK6805-EC15")
      (footprint "eagle-import:SK6805-EC_IPIXEL")
      (fields (field (name "MANUFACTURER") "iPixel") (field (name "VOLTAGE") "5.5 V"))
      (libsource (lib "eagle-import") (part "SK6805-EC15"))
    )
    (comp (ref "IC225")
      (value "SK6805-EC15")
      (footprint "eagle-import:SK6805-EC_IPIXEL")
      (fields (field (name "MANUFACTURER") "iPixel") (field (name "VOLTAGE") "5.5 V"))
      (libsource (lib "eagle-import") (part "SK6805-EC15"))
    )
    (comp (ref "IC226")
      (value "SK6805-EC15")
      (footprint "eagle-import:SK6805-EC_IPIXEL")
      (fields (field (name "MANUFACTURER") "iPixel") (field (name "VOLTAGE") "5.5 V"))
      (libsource (lib "eagle-import") (part "SK6805-EC15"))
    )
    (comp (ref "IC227")
      (value "SK6805-EC15")
      (footprint "eagle-import:SK6805-EC_IPIXEL")
      (fields (field (name "MANUFACTURER") "iPixel") (field (name "VOLTAGE") "5.5 V"))
      (libsource (lib "eagle-import") (part "SK6805-EC15"))
    )
    (comp (ref "IC228")
      (value "SK6805-EC15")
      (footprint "eagle-import:SK6805-EC_IPIXEL")
      (fields (field (name "MANUFACTURER") "iPixel") (field (name "VOLTAGE") "5.5 V"))
      (libsource (lib "eagle-import") (part "SK6805-EC15"))
    )
    (comp (ref "IC229")
      (value "SK6805-EC15")
      (footprint "eagle-import:SK6805-EC_IPIXEL")
      (fields (field (name "MANUFACTURER") "iPixel") (field (name "VOLTAGE") "5.5 V"))
      (libsource (lib "eagle-import") (part "SK6805-EC15"))
    )
    (comp (ref "IC230")
      (value "SK6805-EC15")
      (footprint "eagle-import:SK6805-EC_IPIXEL")
      (fields (field (name "MANUFACTURER") "iPixel") (field (name "VOLTAGE") "5.5 V"))
      (libsource (lib "eagle-import") (part "SK6805-EC15"))
    )
    (comp (ref "IC231")
      (value "SK6805-EC15")
      (footprint "eagle-import:SK6805-EC_IPIXEL")
      (fields (field (name "MANUFACTURER") "iPixel") (field (name "VOLTAGE") "5.5 V"))
      (libsource (lib "eagle-import") (part "SK6805-EC15"))
    )
    (comp (ref "IC232")
      (value "SK6805-EC15")
      (footprint "eagle-import:SK6805-EC_IPIXEL")
      (fields (field (name "MANUFACTURER") "iPixel") (field (name "VOLTAGE") "5.5 V"))
      (libsource (lib "eagle-import") (part "SK6805-EC15"))
    )
    (comp (ref "IC233")
      (value "SK6805-EC15")
      (footprint "eagle-import:SK6805-EC_IPIXEL")
      (fields (field (name "MANUFACTURER") "iPixel") (field (name "VOLTAGE") "5.5 V"))
      (libsource (lib "eagle-import") (part "SK6805-EC15"))
    )
    (comp (ref "IC234")
      (value "SK6805-EC15")
      (footprint "eagle-import:SK6805-EC_IPIXEL")
      (fields (field (name "MANUFACTURER") "iPixel") (field (name "VOLTAGE") "5.5 V"))
      (libsource (lib "eagle-import") (part "SK6805-EC15"))
    )
    (comp (ref "IC235")
      (value "SK6805-EC15")
      (footprint "eagle-import:SK6805-EC_IPIXEL")
      (fields (field (name "MANUFACTURER") "iPixel") (field (name "VOLTAGE") "5.5 V"))
      (libsource (lib "eagle-import") (part "SK6805-EC15"))
    )
    (comp (ref "IC236")
      (value "SK6805-EC15")
      (footprint "eagle-import:SK6805-EC_IPIXEL")
      (fields (field (name "MANUFACTURER") "iPixel") (field (name "VOLTAGE") "5.5 V"))
      (libsource (lib "eagle-import") (part "SK6805-EC15"))
    )
    (comp (ref "IC237")
      (value "SK6805-EC15")
      (footprint "eagle-import:SK6805-EC_IPIXEL")
      (fields (field (name "MANUFACTURER") "iPixel") (field (name "VOLTAGE") "5.5 V"))
      (libsource (lib "eagle-import") (part "SK6805-EC15"))
    )
    (comp (ref "IC238")
      (value "SK6805-EC15")
      (footprint "eagle-import:SK6805-EC_IPIXEL")
      (fields (field (name "MANUFACTURER") "iPixel") (field (name "VOLTAGE") "5.5 V"))
      (libsource (lib "eagle-import") (part "SK6805-EC15"))
    )
    (comp (ref "IC239")
      (value "SK6805-EC15")
      (footprint "eagle-import:SK6805-EC_IPIXEL")
      (fields (field (name "MANUFACTURER") "iPixel") (field (name "VOLTAGE") "5.5 V"))
      (libsource (lib "eagle-import") (part "SK6805-EC15"))
    )
    (comp (ref "IC240")
      (value "SK6805-EC15")
      (footprint "eagle-import:SK6805-EC_IPIXEL")
      (fields (field (name "MANUFACTURER") "iPixel") (field (name "VOLTAGE") "5.5 V"))
      (libsource (lib "eagle-import") (part "SK6805-EC15"))
    )
    (comp (ref "IC241")
      (value "SK6805-EC15")
      (footprint "eagle-import:SK6805-EC_IPIXEL")
      (fields (field (name "MANUFACTURER") "iPixel") (field (name "VOLTAGE") "5.5 V"))
      (libsource (lib "eagle-import") (part "SK6805-EC15"))
    )
    (comp (ref "IC242")
      (value "SK6805-EC15")
      (footprint "eagle-import:SK6805-EC_IPIXEL")
      (fields (field (name "MANUFACTURER") "iPixel") (field (name "VOLTAGE") "5.5 V"))
      (libsource (lib "eagle-import") (part "SK6805-EC15"))
    )
    (comp (ref "IC243")
      (value "SK6805-EC15")
      (footprint "eagle-import:SK6805-EC_IPIXEL")
      (fields (field (name "MANUFACTURER") "iPixel") (field (name "VOLTAGE") "5.5 V"))
      (libsource (lib "eagle-import") (part "SK6805-EC15"))
    )
    (comp (ref "IC244")
      (value "SK6805-EC15")
      (footprint "eagle-import:SK6805-EC_IPIXEL")
      (fields (field (name "MANUFACTURER") "iPixel") (field (name "VOLTAGE") "5.5 V"))
      (libsource (lib "eagle-import") (part "SK6805-EC15"))
    )
    (comp (ref "IC245")
      (value "SK6805-EC15")
      (footprint "eagle-import:SK6805-EC_IPIXEL")
      (fields (field (name "MANUFACTURER") "iPixel") (field (name "VOLTAGE") "5.5 V"))
      (libsource (lib "eagle-import") (part "SK6805-EC15"))
    )
    (comp (ref "IC246")
      (value "SK6805-EC15")
      (footprint "eagle-import:SK6805-EC_IPIXEL")
      (fields (field (name "MANUFACTURER") "iPixel") (field (name "VOLTAGE") "5.5 V"))
      (libsource (lib "eagle-import") (part "SK6805-EC15"))
    )
    (comp (ref "IC247")
      (value "SK6805-EC15")
      (footprint "eagle-import:SK6805-EC_IPIXEL")
      (fields (field (name "MANUFACTURER") "iPixel") (field (name "VOLTAGE") "5.5 V"))
      (libsource (lib "eagle-import") (part "SK6805-EC15"))
    )
    (comp (ref "IC248")
      (value "SK6805-EC15")
      (footprint "eagle-import:SK6805-EC_IPIXEL")
      (fields (field (name "MANUFACTURER") "iPixel") (field (name "VOLTAGE") "5.5 V"))
      (libsource (lib "eagle-import") (part "SK6805-EC15"))
    )
    (comp (ref "IC249")
      (value "SK6805-EC15")
      (footprint "eagle-import:SK6805-EC_IPIXEL")
      (fields (field (name "MANUFACTURER") "iPixel") (field (name "VOLTAGE") "5.5 V"))
      (libsource (lib "eagle-import") (part "SK6805-EC15"))
    )
    (comp (ref "IC250")
      (value "SK6805-EC15")
      (footprint "eagle-import:SK6805-EC_IPIXEL")
      (fields (field (name "MANUFACTURER") "iPixel") (field (name "VOLTAGE") "5.5 V"))
      (libsource (lib "eagle-import") (part "SK6805-EC15"))
    )
    (comp (ref "IC251")
      (value "SK6805-EC15")
      (footprint "eagle-import:SK6805-EC_IPIXEL")
      (fields (field (name "MANUFACTURER") "iPixel") (field (name "VOLTAGE") "5.5 V"))
      (libsource (lib "eagle-import") (part "SK6805-EC15"))
    )
    (comp (ref "IC252")
      (value "SK6805-EC15")
      (footprint "eagle-import:SK6805-EC_IPIXEL")
      (fields (field (name "MANUFACTURER") "iPixel") (field (name "VOLTAGE") "5.5 V"))
      (libsource (lib "eagle-import") (part "SK6805-EC15"))
    )
    (comp (ref "IC253")
      (value "SK6805-EC15")
      (footprint "eagle-import:SK6805-EC_IPIXEL")
      (fields (field (name "MANUFACTURER") "iPixel") (field (name "VOLTAGE") "5.5 V"))
      (libsource (lib "eagle-import") (part "SK6805-EC15"))
    )
    (comp (ref "IC254")
      (value "SK6805-EC15")
      (footprint "eagle-import:SK6805-EC_IPIXEL")
      (fields (field (name "MANUFACTURER") "iPixel") (field (name "VOLTAGE") "5.5 V"))
      (libsource (lib "eagle-import") (part "SK6805-EC15"))
    )
    (comp (ref "IC255")
      (value "SK6805-EC15")
      (footprint "eagle-import:SK6805-EC_IPIXEL")
      (fields (field (name "MANUFACTURER") "iPixel") (field (name "VOLTAGE") "5.5 V"))
      (libsource (lib "eagle-import") (part "SK6805-EC15"))
    )
    (comp (ref "IC256")
      (value "SK6805-EC15")
      (footprint "eagle-import:SK6805-EC_IPIXEL")
      (fields (field (name "MANUFACTURER") "iPixel") (field (name "VOLTAGE") "5.5 V"))
      (libsource (lib "eagle-import") (part "SK6805-EC15"))
    )
    (comp (ref "IC257")
      (value "SK6805-EC15")
      (footprint "eagle-import:SK6805-EC_IPIXEL")
      (fields (field (name "MANUFACTURER") "iPixel") (field (name "VOLTAGE") "5.5 V"))
      (libsource (lib "eagle-import") (part "SK6805-EC15"))
    )
    (comp (ref "IC258")
      (value "SK6805-EC15")
      (footprint "eagle-import:SK6805-EC_IPIXEL")
      (fields (field (name "MANUFACTURER") "iPixel") (field (name "VOLTAGE") "5.5 V"))
      (libsource (lib "eagle-import") (part "SK6805-EC15"))
    )
    (comp (ref "IC259")
      (value "SK6805-EC15")
      (footprint "eagle-import:SK6805-EC_IPIXEL")
      (fields (field (name "MANUFACTURER") "iPixel") (field (name "VOLTAGE") "5.5 V"))
      (libsource (lib "eagle-import") (part "SK6805-EC15"))
    )
    (comp (ref "IC260")
      (value "SK6805-EC15")
      (footprint "eagle-import:SK6805-EC_IPIXEL")
      (fields (field (name "MANUFACTURER") "iPixel") (field (name "VOLTAGE") "5.5 V"))
      (libsource (lib "eagle-import") (part "SK6805-EC15"))
    )
    (comp (ref "IC261")
      (value "SK6805-EC15")
      (footprint "eagle-import:SK6805-EC_IPIXEL")
      (fields (field (name "MANUFACTURER") "iPixel") (field (name "VOLTAGE") "5.5 V"))
      (libsource (lib "eagle-import") (part "SK6805-EC15"))
    )
    (comp (ref "IC262")
      (value "SK6805-EC15")
      (footprint "eagle-import:SK6805-EC_IPIXEL")
      (fields (field (name "MANUFACTURER") "iPixel") (field (name "VOLTAGE") "5.5 V"))
      (libsource (lib "eagle-import") (part "SK6805-EC15"))
    )
    (comp (ref "IC263")
      (value "SK6805-EC15")
      (footprint "eagle-import:SK6805-EC_IPIXEL")
      (fields (field (name "MANUFACTURER") "iPixel") (field (name "VOLTAGE") "5.5 V"))
      (libsource (lib "eagle-import") (part "SK6805-EC15"))
    )
    (comp (ref "IC264")
      (value "SK6805-EC15")
      (footprint "eagle-import:SK6805-EC_IPIXEL")
      (fields (field (name "MANUFACTURER") "iPixel") (field (name "VOLTAGE") "5.5 V"))
      (libsource (lib "eagle-import") (part "SK6805-EC15"))
    )
    (comp (ref "IC265")
      (value "SK6805-EC15")
      (footprint "eagle-import:SK6805-EC_IPIXEL")
      (fields (field (name "MANUFACTURER") "iPixel") (field (name "VOLTAGE") "5.5 V"))
      (libsource (lib "eagle-import") (part "SK6805-EC15"))
    )
    (comp (ref "IC266")
      (value "SK6805-EC15")
      (footprint "eagle-import:SK6805-EC_IPIXEL")
      (fields (field (name "MANUFACTURER") "iPixel") (field (name "VOLTAGE") "5.5 V"))
      (libsource (lib "eagle-import") (part "SK6805-EC15"))
    )
    (comp (ref "IC267")
      (value "SK6805-EC15")
      (footprint "eagle-import:SK6805-EC_IPIXEL")
      (fields (field (name "MANUFACTURER") "iPixel") (field (name "VOLTAGE") "5.5 V"))
      (libsource (lib "eagle-import") (part "SK6805-EC15"))
    )
    (comp (ref "IC268")
      (value "SK6805-EC15")
      (footprint "eagle-import:SK6805-EC_IPIXEL")
      (fields (field (name "MANUFACTURER") "iPixel") (field (name "VOLTAGE") "5.5 V"))
      (libsource (lib "eagle-import") (part "SK6805-EC15"))
    )
    (comp (ref "IC269")
      (value "SK6805-EC15")
      (footprint "eagle-import:SK6805-EC_IPIXEL")
      (fields (field (name "MANUFACTURER") "iPixel") (field (name "VOLTAGE") "5.5 V"))
      (libsource (lib "eagle-import") (part "SK6805-EC15"))
    )
    (comp (ref "IC270")
      (value "SK6805-EC15")
      (footprint "eagle-import:SK6805-EC_IPIXEL")
      (fields (field (name "MANUFACTURER") "iPixel") (field (name "VOLTAGE") "5.5 V"))
      (libsource (lib "eagle-import") (part "SK6805-EC15"))
    )
    (comp (ref "IC271")
      (value "SK6805-EC15")
      (footprint "eagle-import:SK6805-EC_IPIXEL")
      (fields (field (name "MANUFACTURER") "iPixel") (field (name "VOLTAGE") "5.5 V"))
      (libsource (lib "eagle-import") (part "SK6805-EC15"))
    )
    (comp (ref "IC272")
      (value "SK6805-EC15")
      (footprint "eagle-import:SK6805-EC_IPIXEL")
      (fields (field (name "MANUFACTURER") "iPixel") (field (name "VOLTAGE") "5.5 V"))
      (libsource (lib "eagle-import") (part "SK6805-EC15"))
    )
    (comp (ref "IC273")
      (value "SK6805-EC15")
      (footprint "eagle-import:SK6805-EC_IPIXEL")
      (fields (field (name "MANUFACTURER") "iPixel") (field (name "VOLTAGE") "5.5 V"))
      (libsource (lib "eagle-import") (part "SK6805-EC15"))
    )
    (comp (ref "IC274")
      (value "SK6805-EC15")
      (footprint "eagle-import:SK6805-EC_IPIXEL")
      (fields (field (name "MANUFACTURER") "iPixel") (field (name "VOLTAGE") "5.5 V"))
      (libsource (lib "eagle-import") (part "SK6805-EC15"))
    )
    (comp (ref "IC275")
      (value "SK6805-EC15")
      (footprint "eagle-import:SK6805-EC_IPIXEL")
      (fields (field (name "MANUFACTURER") "iPixel") (field (name "VOLTAGE") "5.5 V"))
      (libsource (lib "eagle-import") (part "SK6805-EC15"))
    )
    (comp (ref "IC276")
      (value "SK6805-EC15")
      (footprint "eagle-import:SK6805-EC_IPIXEL")
      (fields (field (name "MANUFACTURER") "iPixel") (field (name "VOLTAGE") "5.5 V"))
      (libsource (lib "eagle-import") (part "SK6805-EC15"))
    )
    (comp (ref "IC277")
      (value "SK6805-EC15")
      (footprint "eagle-import:SK6805-EC_IPIXEL")
      (fields (field (name "MANUFACTURER") "iPixel") (field (name "VOLTAGE") "5.5 V"))
      (libsource (lib "eagle-import") (part "SK6805-EC15"))
    )
    (comp (ref "IC278")
      (value "SK6805-EC15")
      (footprint "eagle-import:SK6805-EC_IPIXEL")
      (fields (field (name "MANUFACTURER") "iPixel") (field (name "VOLTAGE") "5.5 V"))
      (libsource (lib "eagle-import") (part "SK6805-EC15"))
    )
    (comp (ref "IC279")
      (value "SK6805-EC15")
      (footprint "eagle-import:SK6805-EC_IPIXEL")
      (fields (field (name "MANUFACTURER") "iPixel") (field (name "VOLTAGE") "5.5 V"))
      (libsource (lib "eagle-import") (part "SK6805-EC15"))
    )
    (comp (ref "IC280")
      (value "SK6805-EC15")
      (footprint "eagle-import:SK6805-EC_IPIXEL")
      (fields (field (name "MANUFACTURER") "iPixel") (field (name "VOLTAGE") "5.5 V"))
      (libsource (lib "eagle-import") (part "SK6805-EC15"))
    )
    (comp (ref "IC281")
      (value "SK6805-EC15")
      (footprint "eagle-import:SK6805-EC_IPIXEL")
      (fields (field (name "MANUFACTURER") "iPixel") (field (name "VOLTAGE") "5.5 V"))
      (libsource (lib "eagle-import") (part "SK6805-EC15"))
    )
    (comp (ref "IC282")
      (value "SK6805-EC15")
      (footprint "eagle-import:SK6805-EC_IPIXEL")
      (fields (field (name "MANUFACTURER") "iPixel") (field (name "VOLTAGE") "5.5 V"))
      (libsource (lib "eagle-import") (part "SK6805-EC15"))
    )
    (comp (ref "IC283")
      (value "SK6805-EC15")
      (footprint "eagle-import:SK6805-EC_IPIXEL")
      (fields (field (name "MANUFACTURER") "iPixel") (field (name "VOLTAGE") "5.5 V"))
      (libsource (lib "eagle-import") (part "SK6805-EC15"))
    )
    (comp (ref "IC284")
      (value "SK6805-EC15")
      (footprint "eagle-import:SK6805-EC_IPIXEL")
      (fields (field (name "MANUFACTURER") "iPixel") (field (name "VOLTAGE") "5.5 V"))
      (libsource (lib "eagle-import") (part "SK6805-EC15"))
    )
    (comp (ref "IC285")
      (value "SK6805-EC15")
      (footprint "eagle-import:SK6805-EC_IPIXEL")
      (fields (field (name "MANUFACTURER") "iPixel") (field (name "VOLTAGE") "5.5 V"))
      (libsource (lib "eagle-import") (part "SK6805-EC15"))
    )
    (comp (ref "IC286")
      (value "SK6805-EC15")
      (footprint "eagle-import:SK6805-EC_IPIXEL")
      (fields (field (name "MANUFACTURER") "iPixel") (field (name "VOLTAGE") "5.5 V"))
      (libsource (lib "eagle-import") (part "SK6805-EC15"))
    )
    (comp (ref "IC287")
      (value "SK6805-EC15")
      (footprint "eagle-import:SK6805-EC_IPIXEL")
      (fields (field (name "MANUFACTURER") "iPixel") (field (name "VOLTAGE") "5.5 V"))
      (libsource (lib "eagle-import") (part "SK6805-EC15"))
    )
    (comp (ref "IC288")
      (value "SK6805-EC15")
      (footprint "eagle-import:SK6805-EC_IPIXEL")
      (fields (field (name "MANUFACTURER") "iPixel") (field (name "VOLTAGE") "5.5 V"))
      (libsource (lib "eagle-import") (part "SK6805-EC15"))
    )
    (comp (ref "IC289")
      (value "SK6805-EC15")
      (footprint "eagle-import:SK6805-EC_IPIXEL")
      (fields (field (name "MANUFACTURER") "iPixel") (field (name "VOLTAGE") "5.5 V"))
      (libsource (lib "eagle-import") (part "SK6805-EC15"))
    )
    (comp (ref "IC290")
      (value "SK6805-EC15")
      (footprint "eagle-import:SK6805-EC_IPIXEL")
      (fields (field (name "MANUFACTURER") "iPixel") (field (name "VOLTAGE") "5.5 V"))
      (libsource (lib "eagle-import") (part "SK6805-EC15"))
    )
    (comp (ref "IC291")
      (value "SK6805-EC15")
      (footprint "eagle-import:SK6805-EC_IPIXEL")
      (fields (field (name "MANUFACTURER") "iPixel") (field (name "VOLTAGE") "5.5 V"))
      (libsource (lib "eagle-import") (part "SK6805-EC15"))
    )
    (comp (ref "IC292")
      (value "SK6805-EC15")
      (footprint "eagle-import:SK6805-EC_IPIXEL")
      (fields (field (name "MANUFACTURER") "iPixel") (field (name "VOLTAGE") "5.5 V"))
      (libsource (lib "eagle-import") (part "SK6805-EC15"))
    )
    (comp (ref "IC293")
      (value "SK6805-EC15")
      (footprint "eagle-import:SK6805-EC_IPIXEL")
      (fields (field (name "MANUFACTURER") "iPixel") (field (name "VOLTAGE") "5.5 V"))
      (libsource (lib "eagle-import") (part "SK6805-EC15"))
    )
    (comp (ref "IC294")
      (value "SK6805-EC15")
      (footprint "eagle-import:SK6805-EC_IPIXEL")
      (fields (field (name "MANUFACTURER") "iPixel") (field (name "VOLTAGE") "5.5 V"))
      (libsource (lib "eagle-import") (part "SK6805-EC15"))
    )
    (comp (ref "IC295")
      (value "SK6805-EC15")
      (footprint "eagle-import:SK6805-EC_IPIXEL")
      (fields (field (name "MANUFACTURER") "iPixel") (field (name "VOLTAGE") "5.5 V"))
      (libsource (lib "eagle-import") (part "SK6805-EC15"))
    )
    (comp (ref "IC296")
      (value "SK6805-EC15")
      (footprint "eagle-import:SK6805-EC_IPIXEL")
      (fields (field (name "MANUFACTURER") "iPixel") (field (name "VOLTAGE") "5.5 V"))
      (libsource (lib "eagle-import") (part "SK6805-EC15"))
    )
    (comp (ref "IC297")
      (value "SK6805-EC15")
      (footprint "eagle-import:SK6805-EC_IPIXEL")
      (fields (field (name "MANUFACTURER") "iPixel") (field (name "VOLTAGE") "5.5 V"))
      (libsource (lib "eagle-import") (part "SK6805-EC15"))
    )
    (comp (ref "IC298")
      (value "SK6805-EC15")
      (footprint "eagle-import:SK6805-EC_IPIXEL")
      (fields (field (name "MANUFACTURER") "iPixel") (field (name "VOLTAGE") "5.5 V"))
      (libsource (lib "eagle-import") (part "SK6805-EC15"))
    )
    (comp (ref "IC299")
      (value "SK6805-EC15")
      (footprint "eagle-import:SK6805-EC_IPIXEL")
      (fields (field (name "MANUFACTURER") "iPixel") (field (name "VOLTAGE") "5.5 V"))
      (libsource (lib "eagle-import") (part "SK6805-EC15"))
    )
    (comp (ref "IC300")
      (value "SK6805-EC15")
      (footprint "eagle-import:SK6805-EC_IPIXEL")
      (fields (field (name "MANUFACTURER") "iPixel") (field (name "VOLTAGE") "5.5 V"))
      (libsource (lib "eagle-import") (part "SK6805-EC15"))
    )
    (comp (ref "IC301")
      (value "SK6805-EC15")
      (footprint "eagle-import:SK6805-EC_IPIXEL")
      (fields (field (name "MANUFACTURER") "iPixel") (field (name "VOLTAGE") "5.5 V"))
      (libsource (lib "eagle-import") (part "SK6805-EC15"))
    )
    (comp (ref "IC302")
      (value "SK6805-EC15")
      (footprint "eagle-import:SK6805-EC_IPIXEL")
      (fields (field (name "MANUFACTURER") "iPixel") (field (name "VOLTAGE") "5.5 V"))
      (libsource (lib "eagle-import") (part "SK6805-EC15"))
    )
    (comp (ref "IC303")
      (value "SK6805-EC15")
      (footprint "eagle-import:SK6805-EC_IPIXEL")
      (fields (field (name "MANUFACTURER") "iPixel") (field (name "VOLTAGE") "5.5 V"))
      (libsource (lib "eagle-import") (part "SK6805-EC15"))
    )
    (comp (ref "IC304")
      (value "SK6805-EC15")
      (footprint "eagle-import:SK6805-EC_IPIXEL")
      (fields (field (name "MANUFACTURER") "iPixel") (field (name "VOLTAGE") "5.5 V"))
      (libsource (lib "eagle-import") (part "SK6805-EC15"))
    )
    (comp (ref "IC305")
      (value "SK6805-EC15")
      (footprint "eagle-import:SK6805-EC_IPIXEL")
      (fields (field (name "MANUFACTURER") "iPixel") (field (name "VOLTAGE") "5.5 V"))
      (libsource (lib "eagle-import") (part "SK6805-EC15"))
    )
    (comp (ref "IC306")
      (value "SK6805-EC15")
      (footprint "eagle-import:SK6805-EC_IPIXEL")
      (fields (field (name "MANUFACTURER") "iPixel") (field (name "VOLTAGE") "5.5 V"))
      (libsource (lib "eagle-import") (part "SK6805-EC15"))
    )
    (comp (ref "IC307")
      (value "SK6805-EC15")
      (footprint "eagle-import:SK6805-EC_IPIXEL")
      (fields (field (name "MANUFACTURER") "iPixel") (field (name "VOLTAGE") "5.5 V"))
      (libsource (lib "eagle-import") (part "SK6805-EC15"))
    )
    (comp (ref "IC308")
      (value "SK6805-EC15")
      (footprint "eagle-import:SK6805-EC_IPIXEL")
      (fields (field (name "MANUFACTURER") "iPixel") (field (name "VOLTAGE") "5.5 V"))
      (libsource (lib "eagle-import") (part "SK6805-EC15"))
    )
    (comp (ref "IC309")
      (value "SK6805-EC15")
      (footprint "eagle-import:SK6805-EC_IPIXEL")
      (fields (field (name "MANUFACTURER") "iPixel") (field (name "VOLTAGE") "5.5 V"))
      (libsource (lib "eagle-import") (part "SK6805-EC15"))
    )
    (comp (ref "IC310")
      (value "SK6805-EC15")
      (footprint "eagle-import:SK6805-EC_IPIXEL")
      (fields (field (name "MANUFACTURER") "iPixel") (field (name "VOLTAGE") "5.5 V"))
      (libsource (lib "eagle-import") (part "SK6805-EC15"))
    )
    (comp (ref "IC311")
      (value "SK6805-EC15")
      (footprint "eagle-import:SK6805-EC_IPIXEL")
      (fields (field (name "MANUFACTURER") "iPixel") (field (name "VOLTAGE") "5.5 V"))
      (libsource (lib "eagle-import") (part "SK6805-EC15"))
    )
    (comp (ref "IC312")
      (value "SK6805-EC15")
      (footprint "eagle-import:SK6805-EC_IPIXEL")
      (fields (field (name "MANUFACTURER") "iPixel") (field (name "VOLTAGE") "5.5 V"))
      (libsource (lib "eagle-import") (part "SK6805-EC15"))
    )
    (comp (ref "IC313")
      (value "SK6805-EC15")
      (footprint "eagle-import:SK6805-EC_IPIXEL")
      (fields (field (name "MANUFACTURER") "iPixel") (field (name "VOLTAGE") "5.5 V"))
      (libsource (lib "eagle-import") (part "SK6805-EC15"))
    )
    (comp (ref "IC314")
      (value "SK6805-EC15")
      (footprint "eagle-import:SK6805-EC_IPIXEL")
      (fields (field (name "MANUFACTURER") "iPixel") (field (name "VOLTAGE") "5.5 V"))
      (libsource (lib "eagle-import") (part "SK6805-EC15"))
    )
    (comp (ref "IC315")
      (value "SK6805-EC15")
      (footprint "eagle-import:SK6805-EC_IPIXEL")
      (fields (field (name "MANUFACTURER") "iPixel") (field (name "VOLTAGE") "5.5 V"))
      (libsource (lib "eagle-import") (part "SK6805-EC15"))
    )
    (comp (ref "IC316")
      (value "SK6805-EC15")
      (footprint "eagle-import:SK6805-EC_IPIXEL")
      (fields (field (name "MANUFACTURER") "iPixel") (field (name "VOLTAGE") "5.5 V"))
      (libsource (lib "eagle-import") (part "SK6805-EC15"))
    )
    (comp (ref "IC317")
      (value "SK6805-EC15")
      (footprint "eagle-import:SK6805-EC_IPIXEL")
      (fields (field (name "MANUFACTURER") "iPixel") (field (name "VOLTAGE") "5.5 V"))
      (libsource (lib "eagle-import") (part "SK6805-EC15"))
    )
    (comp (ref "IC318")
      (value "SK6805-EC15")
      (footprint "eagle-import:SK6805-EC_IPIXEL")
      (fields (field (name "MANUFACTURER") "iPixel") (field (name "VOLTAGE") "5.5 V"))
      (libsource (lib "eagle-import") (part "SK6805-EC15"))
    )
    (comp (ref "IC319")
      (value "SK6805-EC15")
      (footprint "eagle-import:SK6805-EC_IPIXEL")
      (fields (field (name "MANUFACTURER") "iPixel") (field (name "VOLTAGE") "5.5 V"))
      (libsource (lib "eagle-import") (part "SK6805-EC15"))
    )
    (comp (ref "IC320")
      (value "SK6805-EC15")
      (footprint "eagle-import:SK6805-EC_IPIXEL")
      (fields (field (name "MANUFACTURER") "iPixel") (field (name "VOLTAGE") "5.5 V"))
      (libsource (lib "eagle-import") (part "SK6805-EC15"))
    )
    (comp (ref "IC321")
      (value "SK6805-EC15")
      (footprint "eagle-import:SK6805-EC_IPIXEL")
      (fields (field (name "MANUFACTURER") "iPixel") (field (name "VOLTAGE") "5.5 V"))
      (libsource (lib "eagle-import") (part "SK6805-EC15"))
    )
    (comp (ref "IC322")
      (value "SK6805-EC15")
      (footprint "eagle-import:SK6805-EC_IPIXEL")
      (fields (field (name "MANUFACTURER") "iPixel") (field (name "VOLTAGE") "5.5 V"))
      (libsource (lib "eagle-import") (part "SK6805-EC15"))
    )
    (comp (ref "IC323")
      (value "SK6805-EC15")
      (footprint "eagle-import:SK6805-EC_IPIXEL")
      (fields (field (name "MANUFACTURER") "iPixel") (field (name "VOLTAGE") "5.5 V"))
      (libsource (lib "eagle-import") (part "SK6805-EC15"))
    )
    (comp (ref "IC324")
      (value "SK6805-EC15")
      (footprint "eagle-import:SK6805-EC_IPIXEL")
      (fields (field (name "MANUFACTURER") "iPixel") (field (name "VOLTAGE") "5.5 V"))
      (libsource (lib "eagle-import") (part "SK6805-EC15"))
    )
    (comp (ref "IC325")
      (value "SK6805-EC15")
      (footprint "eagle-import:SK6805-EC_IPIXEL")
      (fields (field (name "MANUFACTURER") "iPixel") (field (name "VOLTAGE") "5.5 V"))
      (libsource (lib "eagle-import") (part "SK6805-EC15"))
    )
    (comp (ref "IC326")
      (value "SK6805-EC15")
      (footprint "eagle-import:SK6805-EC_IPIXEL")
      (fields (field (name "MANUFACTURER") "iPixel") (field (name "VOLTAGE") "5.5 V"))
      (libsource (lib "eagle-import") (part "SK6805-EC15"))
    )
    (comp (ref "IC327")
      (value "SK6805-EC15")
      (footprint "eagle-import:SK6805-EC_IPIXEL")
      (fields (field (name "MANUFACTURER") "iPixel") (field (name "VOLTAGE") "5.5 V"))
      (libsource (lib "eagle-import") (part "SK6805-EC15"))
    )
    (comp (ref "IC328")
      (value "SK6805-EC15")
      (footprint "eagle-import:SK6805-EC_IPIXEL")
      (fields (field (name "MANUFACTURER") "iPixel") (field (name "VOLTAGE") "5.5 V"))
      (libsource (lib "eagle-import") (part "SK6805-EC15"))
    )
    (comp (ref "IC329")
      (value "SK6805-EC15")
      (footprint "eagle-import:SK6805-EC_IPIXEL")
      (fields (field (name "MANUFACTURER") "iPixel") (field (name "VOLTAGE") "5.5 V"))
      (libsource (lib "eagle-import") (part "SK6805-EC15"))
    )
    (comp (ref "IC330")
      (value "SK6805-EC15")
      (footprint "eagle-import:SK6805-EC_IPIXEL")
      (fields (field (name "MANUFACTURER") "iPixel") (field (name "VOLTAGE") "5.5 V"))
      (libsource (lib "eagle-import") (part "SK6805-EC15"))
    )
    (comp (ref "IC331")
      (value "SK6805-EC15")
      (footprint "eagle-import:SK6805-EC_IPIXEL")
      (fields (field (name "MANUFACTURER") "iPixel") (field (name "VOLTAGE") "5.5 V"))
      (libsource (lib "eagle-import") (part "SK6805-EC15"))
    )
    (comp (ref "IC332")
      (value "SK6805-EC15")
      (footprint "eagle-import:SK6805-EC_IPIXEL")
      (fields (field (name "MANUFACTURER") "iPixel") (field (name "VOLTAGE") "5.5 V"))
      (libsource (lib "eagle-import") (part "SK6805-EC15"))
    )
    (comp (ref "L9")
      (value "74279269")
      (footprint "eagle-import:FERRIT_0603_WIDE_BAND_WUERTH")
      (fields (field (name "MANUFACTURER") "Wuerth"))
      (libsource (lib "eagle-import") (part "74279269"))
    )
    (comp (ref "PS1")
      (value "PASSERMARKE")
      (footprint "eagle-import:PASSERMARKE")
      (libsource (lib "eagle-import") (part "PASSERMARKE"))
    )
    (comp (ref "PS2")
      (value "PASSERMARKE")
      (footprint "eagle-import:PASSERMARKE")
      (libsource (lib "eagle-import") (part "PASSERMARKE"))
    )
    (comp (ref "PS3")
      (value "PASSERMARKE")
      (footprint "eagle-import:PASSERMARKE")
      (libsource (lib "eagle-import") (part "PASSERMARKE"))
    )
    (comp (ref "PS4")
      (value "PASSERMARKE")
      (footprint "eagle-import:PASSERMARKE")
      (libsource (lib "eagle-import") (part "PASSERMARKE"))
    )
    (comp (ref "PS5")
      (value "PASSERMARKE")
      (footprint "eagle-import:PASSERMARKE")
      (libsource (lib "eagle-import") (part "PASSERMARKE"))
    )
    (comp (ref "PS6")
      (value "PASSERMARKE")
      (footprint "eagle-import:PASSERMARKE")
      (libsource (lib "eagle-import") (part "PASSERMARKE"))
    )
    (comp (ref "R1")
      (value "0R")
      (footprint "eagle-import:R0603")
      (fields
        (field (name "MANUFACTURER") "free choice")
        (field (name "POWER") "63 mW")
        (field (name "VOLTAGE") "50.0 V")
      )
      (libsource (lib "eagle-import") (part "R-EU-R0603-0R"))
    )
    (comp (ref "R2")
      (value "10k")
      (footprint "eagle-import:R0603")
      (fields
        (field (name "MANUFACTURER") "free choice")
        (field (name "POWER") "63 mW")
        (field (name "TOLERANCE") "±1 %")
      )
      (libsource (lib "eagle-import") (part "R-EU-R0603-10K"))
    )
    (comp (ref "R3")
      (value "56k")
      (footprint "eagle-import:R0603")
      (fields
        (field (name "MANUFACTURER") "free choice")
        (field (name "POWER") "63 mW")
        (field (name "TOLERANCE") "±1 %")
      )
      (libsource (lib "eagle-import") (part "R-EU-R0603-56K"))
    )
    (comp (ref "R4")
      (value "56k")
      (footprint "eagle-import:R0603")
      (fields
        (field (name "MANUFACTURER") "free choice")
        (field (name "POWER") "63 mW")
        (field (name "TOLERANCE") "±1 %")
      )
      (libsource (lib "eagle-import") (part "R-EU-R0603-56K"))
    )
    (comp (ref "R5")
      (value "56k")
      (footprint "eagle-import:R0603")
      (fields
        (field (name "MANUFACTURER") "free choice")
        (field (name "POWER") "63 mW")
        (field (name "TOLERANCE") "±1 %")
      )
      (libsource (lib "eagle-import") (part "R-EU-R0603-56K"))
    )
    (comp (ref "R6")
      (value "56k")
      (footprint "eagle-import:R0603")
      (fields
        (field (name "MANUFACTURER") "free choice")
        (field (name "POWER") "63 mW")
        (field (name "TOLERANCE") "±1 %")
      )
      (libsource (lib "eagle-import") (part "R-EU-R0603-56K"))
    )
    (comp (ref "R8")
      (value "6R2")
      (footprint "eagle-import:R1210")
      (fields
        (field (name "MANUFACTURER") "free choice")
        (field (name "POWER") "333 mW")
        (field (name "TOLERANCE") "±1 %")
      )
      (libsource (lib "eagle-import") (part "R-EU-R1210-6R2"))
    )
    (comp (ref "R9")
      (value "0R")
      (footprint "eagle-import:R0603")
      (fields
        (field (name "MANUFACTURER") "free choice")
        (field (name "POWER") "63 mW")
        (field (name "VOLTAGE") "50.0 V")
      )
      (libsource (lib "eagle-import") (part "R-EU-R0603-0R"))
    )
    (comp (ref "R10")
      (value "56k")
      (footprint "eagle-import:R0603")
      (fields
        (field (name "MANUFACTURER") "free choice")
        (field (name "POWER") "63 mW")
        (field (name "TOLERANCE") "±1 %")
      )
      (libsource (lib "eagle-import") (part "R-EU-R0603-56K"))
    )
    (comp (ref "R11")
      (value "56k")
      (footprint "eagle-import:R0603")
      (fields
        (field (name "MANUFACTURER") "free choice")
        (field (name "POWER") "63 mW")
        (field (name "TOLERANCE") "±1 %")
      )
      (libsource (lib "eagle-import") (part "R-EU-R0603-56K"))
    )
    (comp (ref "R12")
      (value "56k")
      (footprint "eagle-import:R0603")
      (fields
        (field (name "MANUFACTURER") "free choice")
        (field (name "POWER") "63 mW")
        (field (name "TOLERANCE") "±1 %")
      )
      (libsource (lib "eagle-import") (part "R-EU-R0603-56K"))
    )
    (comp (ref "R13")
      (value "56k")
      (footprint "eagle-import:R0603")
      (fields
        (field (name "MANUFACTURER") "free choice")
        (field (name "POWER") "63 mW")
        (field (name "TOLERANCE") "±1 %")
      )
      (libsource (lib "eagle-import") (part "R-EU-R0603-56K"))
    )
    (comp (ref "R15")
      (value "6R2")
      (footprint "eagle-import:R1210")
      (fields
        (field (name "MANUFACTURER") "free choice")
        (field (name "POWER") "333 mW")
        (field (name "TOLERANCE") "±1 %")
      )
      (libsource (lib "eagle-import") (part "R-EU-R1210-6R2"))
    )
    (comp (ref "R16")
      (value "0R")
      (footprint "eagle-import:R0603")
      (fields
        (field (name "MANUFACTURER") "free choice")
        (field (name "POWER") "63 mW")
        (field (name "VOLTAGE") "50.0 V")
      )
      (libsource (lib "eagle-import") (part "R-EU-R0603-0R"))
    )
    (comp (ref "R17")
      (value "91k")
      (footprint "eagle-import:R0603")
      (fields
        (field (name "MANUFACTURER") "free choice")
        (field (name "POWER") "63 mW")
        (field (name "TOLERANCE") "±1 %")
      )
      (libsource (lib "eagle-import") (part "R-EU-R0603-91K"))
    )
    (comp (ref "R18")
      (value "27k")
      (footprint "eagle-import:R0603")
      (fields
        (field (name "MANUFACTURER") "free choice")
        (field (name "POWER") "63 mW")
        (field (name "TOLERANCE") "±1 %")
      )
      (libsource (lib "eagle-import") (part "R-EU-R0603-27K"))
    )
    (comp (ref "R19")
      (value "0R")
      (footprint "eagle-import:R0603")
      (fields
        (field (name "MANUFACTURER") "free choice")
        (field (name "POWER") "63 mW")
        (field (name "VOLTAGE") "50.0 V")
      )
      (libsource (lib "eagle-import") (part "R-EU-R0603-0R"))
    )
    (comp (ref "R20")
      (value "3R9")
      (footprint "eagle-import:R1210")
      (fields
        (field (name "MANUFACTURER") "free choice")
        (field (name "POWER") "333 mW")
        (field (name "TOLERANCE") "±1 %")
      )
      (libsource (lib "eagle-import") (part "R-EU-R1210-3R9"))
    )
    (comp (ref "R21")
      (value "0R")
      (footprint "eagle-import:R0603")
      (fields
        (field (name "MANUFACTURER") "free choice")
        (field (name "POWER") "63 mW")
        (field (name "VOLTAGE") "50.0 V")
      )
      (libsource (lib "eagle-import") (part "R-EU-R0603-0R"))
    )
    (comp (ref "R22")
      (value "3R9")
      (footprint "eagle-import:R1210")
      (fields
        (field (name "MANUFACTURER") "free choice")
        (field (name "POWER") "333 mW")
        (field (name "TOLERANCE") "±1 %")
      )
      (libsource (lib "eagle-import") (part "R-EU-R1210-3R9"))
    )
    (comp (ref "R23")
      (value "0R")
      (footprint "eagle-import:R0603")
      (fields
        (field (name "MANUFACTURER") "free choice")
        (field (name "POWER") "63 mW")
        (field (name "VOLTAGE") "50.0 V")
      )
      (libsource (lib "eagle-import") (part "R-EU-R0603-0R"))
    )
    (comp (ref "R24")
      (value "27R")
      (footprint "eagle-import:R0603")
      (fields
        (field (name "MANUFACTURER") "free choice")
        (field (name "POWER") "63 mW")
        (field (name "TOLERANCE") "±1 %")
      )
      (libsource (lib "eagle-import") (part "R-EU-R0603-27R"))
    )
    (comp (ref "R25")
      (value "6R2")
      (footprint "eagle-import:R1210")
      (fields
        (field (name "MANUFACTURER") "free choice")
        (field (name "POWER") "333 mW")
        (field (name "TOLERANCE") "±1 %")
      )
      (libsource (lib "eagle-import") (part "R-EU-R1210-6R2"))
    )
    (comp (ref "R26")
      (value "0R")
      (footprint "eagle-import:R0603")
      (fields
        (field (name "MANUFACTURER") "free choice")
        (field (name "POWER") "63 mW")
        (field (name "VOLTAGE") "50.0 V")
      )
      (libsource (lib "eagle-import") (part "R-EU-R0603-0R"))
    )
    (comp (ref "R27")
      (value "0R")
      (footprint "eagle-import:R0603")
      (fields
        (field (name "MANUFACTURER") "free choice")
        (field (name "POWER") "63 mW")
        (field (name "VOLTAGE") "50.0 V")
      )
      (libsource (lib "eagle-import") (part "R-EU-R0603-0R"))
    )
    (comp (ref "R28")
      (value "0R")
      (footprint "eagle-import:R0603")
      (fields
        (field (name "MANUFACTURER") "free choice")
        (field (name "POWER") "63 mW")
        (field (name "VOLTAGE") "50.0 V")
      )
      (libsource (lib "eagle-import") (part "R-EU-R0603-0R"))
    )
    (comp (ref "R29")
      (value "6R2")
      (footprint "eagle-import:R1210")
      (fields
        (field (name "MANUFACTURER") "free choice")
        (field (name "POWER") "333 mW")
        (field (name "TOLERANCE") "±1 %")
      )
      (libsource (lib "eagle-import") (part "R-EU-R1210-6R2"))
    )
    (comp (ref "R30")
      (value "27R")
      (footprint "eagle-import:R0603")
      (fields
        (field (name "MANUFACTURER") "free choice")
        (field (name "POWER") "63 mW")
        (field (name "TOLERANCE") "±1 %")
      )
      (libsource (lib "eagle-import") (part "R-EU-R0603-27R"))
    )
    (comp (ref "R31")
      (value "10k")
      (footprint "eagle-import:R0603")
      (fields
        (field (name "MANUFACTURER") "free choice")
        (field (name "POWER") "63 mW")
        (field (name "TOLERANCE") "±1 %")
      )
      (libsource (lib "eagle-import") (part "R-EU-R0603-10K"))
    )
    (comp (ref "R32")
      (value "27R")
      (footprint "eagle-import:R0603")
      (fields
        (field (name "MANUFACTURER") "free choice")
        (field (name "POWER") "63 mW")
        (field (name "TOLERANCE") "±1 %")
      )
      (libsource (lib "eagle-import") (part "R-EU-R0603-27R"))
    )
    (comp (ref "R33")
      (value "27R")
      (footprint "eagle-import:R0603")
      (fields
        (field (name "MANUFACTURER") "free choice")
        (field (name "POWER") "63 mW")
        (field (name "TOLERANCE") "±1 %")
      )
      (libsource (lib "eagle-import") (part "R-EU-R0603-27R"))
    )
    (comp (ref "R34")
      (value "3R9")
      (footprint "eagle-import:R1210")
      (fields
        (field (name "MANUFACTURER") "free choice")
        (field (name "POWER") "333 mW")
        (field (name "TOLERANCE") "±1 %")
      )
      (libsource (lib "eagle-import") (part "R-EU-R1210-3R9"))
    )
    (comp (ref "R35")
      (value "3R9")
      (footprint "eagle-import:R1210")
      (fields
        (field (name "MANUFACTURER") "free choice")
        (field (name "POWER") "333 mW")
        (field (name "TOLERANCE") "±1 %")
      )
      (libsource (lib "eagle-import") (part "R-EU-R1210-3R9"))
    )
    (comp (ref "R36")
      (value "10k")
      (footprint "eagle-import:R0603")
      (fields
        (field (name "MANUFACTURER") "free choice")
        (field (name "POWER") "63 mW")
        (field (name "TOLERANCE") "±1 %")
      )
      (libsource (lib "eagle-import") (part "R-EU-R0603-10K"))
    )
    (comp (ref "R37")
      (value "27R")
      (footprint "eagle-import:R0603")
      (fields
        (field (name "MANUFACTURER") "free choice")
        (field (name "POWER") "63 mW")
        (field (name "TOLERANCE") "±1 %")
      )
      (libsource (lib "eagle-import") (part "R-EU-R0603-27R"))
    )
    (comp (ref "R38")
      (value "0R")
      (footprint "eagle-import:R0603")
      (fields
        (field (name "MANUFACTURER") "free choice")
        (field (name "POWER") "63 mW")
        (field (name "VOLTAGE") "50.0 V")
      )
      (libsource (lib "eagle-import") (part "R-EU-R0603-0R"))
    )
    (comp (ref "R39")
      (value "27R")
      (footprint "eagle-import:R0603")
      (fields
        (field (name "MANUFACTURER") "free choice")
        (field (name "POWER") "63 mW")
        (field (name "TOLERANCE") "±1 %")
      )
      (libsource (lib "eagle-import") (part "R-EU-R0603-27R"))
    )
    (comp (ref "R40")
      (value "10k")
      (footprint "eagle-import:R0603")
      (fields
        (field (name "MANUFACTURER") "free choice")
        (field (name "POWER") "63 mW")
        (field (name "TOLERANCE") "±1 %")
      )
      (libsource (lib "eagle-import") (part "R-EU-R0603-10K"))
    )
    (comp (ref "R41")
      (value "56k")
      (footprint "eagle-import:R0603")
      (fields
        (field (name "MANUFACTURER") "free choice")
        (field (name "POWER") "63 mW")
        (field (name "TOLERANCE") "±1 %")
      )
      (libsource (lib "eagle-import") (part "R-EU-R0603-56K"))
    )
    (comp (ref "R42")
      (value "56k")
      (footprint "eagle-import:R0603")
      (fields
        (field (name "MANUFACTURER") "free choice")
        (field (name "POWER") "63 mW")
        (field (name "TOLERANCE") "±1 %")
      )
      (libsource (lib "eagle-import") (part "R-EU-R0603-56K"))
    )
    (comp (ref "R43")
      (value "6R2")
      (footprint "eagle-import:R1210")
      (fields
        (field (name "MANUFACTURER") "free choice")
        (field (name "POWER") "333 mW")
        (field (name "TOLERANCE") "±1 %")
      )
      (libsource (lib "eagle-import") (part "R-EU-R1210-6R2"))
    )
    (comp (ref "R44")
      (value "0R")
      (footprint "eagle-import:R0603")
      (fields
        (field (name "MANUFACTURER") "free choice")
        (field (name "POWER") "63 mW")
        (field (name "VOLTAGE") "50.0 V")
      )
      (libsource (lib "eagle-import") (part "R-EU-R0603-0R"))
    )
    (comp (ref "R45")
      (value "56k")
      (footprint "eagle-import:R0603")
      (fields
        (field (name "MANUFACTURER") "free choice")
        (field (name "POWER") "63 mW")
        (field (name "TOLERANCE") "±1 %")
      )
      (libsource (lib "eagle-import") (part "R-EU-R0603-56K"))
    )
    (comp (ref "R46")
      (value "6R2")
      (footprint "eagle-import:R1210")
      (fields
        (field (name "MANUFACTURER") "free choice")
        (field (name "POWER") "333 mW")
        (field (name "TOLERANCE") "±1 %")
      )
      (libsource (lib "eagle-import") (part "R-EU-R1210-6R2"))
    )
    (comp (ref "R47")
      (value "0R")
      (footprint "eagle-import:R0603")
      (fields
        (field (name "MANUFACTURER") "free choice")
        (field (name "POWER") "63 mW")
        (field (name "VOLTAGE") "50.0 V")
      )
      (libsource (lib "eagle-import") (part "R-EU-R0603-0R"))
    )
    (comp (ref "R48")
      (value "56k")
      (footprint "eagle-import:R0603")
      (fields
        (field (name "MANUFACTURER") "free choice")
        (field (name "POWER") "63 mW")
        (field (name "TOLERANCE") "±1 %")
      )
      (libsource (lib "eagle-import") (part "R-EU-R0603-56K"))
    )
    (comp (ref "R49")
      (value "0R")
      (footprint "eagle-import:R0603")
      (fields
        (field (name "MANUFACTURER") "free choice")
        (field (name "POWER") "63 mW")
        (field (name "VOLTAGE") "50.0 V")
      )
      (libsource (lib "eagle-import") (part "R-EU-R0603-0R"))
    )
    (comp (ref "R50")
      (value "27R")
      (footprint "eagle-import:R0603")
      (fields
        (field (name "MANUFACTURER") "free choice")
        (field (name "POWER") "63 mW")
        (field (name "TOLERANCE") "±1 %")
      )
      (libsource (lib "eagle-import") (part "R-EU-R0603-27R"))
    )
    (comp (ref "R51")
      (value "56k")
      (footprint "eagle-import:R0603")
      (fields
        (field (name "MANUFACTURER") "free choice")
        (field (name "POWER") "63 mW")
        (field (name "TOLERANCE") "±1 %")
      )
      (libsource (lib "eagle-import") (part "R-EU-R0603-56K"))
    )
    (comp (ref "R52")
      (value "3R9")
      (footprint "eagle-import:R1210")
      (fields
        (field (name "MANUFACTURER") "free choice")
        (field (name "POWER") "333 mW")
        (field (name "TOLERANCE") "±1 %")
      )
      (libsource (lib "eagle-import") (part "R-EU-R1210-3R9"))
    )
    (comp (ref "R53")
      (value "R-EU-R0603")
      (footprint "eagle-import:R0603")
      (fields
        (field (name "POWER") "63 mW")
        (field (name "TOLERANCE") "±1 %")
        (field (name "VOLTAGE") "50 V")
      )
      (libsource (lib "eagle-import") (part "R-EU-R0603"))
    )
    (comp (ref "R54")
      (value "0R")
      (footprint "eagle-import:R0603")
      (fields
        (field (name "MANUFACTURER") "free choice")
        (field (name "POWER") "63 mW")
        (field (name "VOLTAGE") "50.0 V")
      )
      (libsource (lib "eagle-import") (part "R-EU-R0603-0R"))
    )
    (comp (ref "R55")
      (value "27R")
      (footprint "eagle-import:R0603")
      (fields
        (field (name "MANUFACTURER") "free choice")
        (field (name "POWER") "63 mW")
        (field (name "TOLERANCE") "±1 %")
      )
      (libsource (lib "eagle-import") (part "R-EU-R0603-27R"))
    )
    (comp (ref "R56")
      (value "27R")
      (footprint "eagle-import:R0603")
      (fields
        (field (name "MANUFACTURER") "free choice")
        (field (name "POWER") "63 mW")
        (field (name "TOLERANCE") "±1 %")
      )
      (libsource (lib "eagle-import") (part "R-EU-R0603-27R"))
    )
    (comp (ref "R57")
      (value "3R9")
      (footprint "eagle-import:R1210")
      (fields
        (field (name "MANUFACTURER") "free choice")
        (field (name "POWER") "333 mW")
        (field (name "TOLERANCE") "±1 %")
      )
      (libsource (lib "eagle-import") (part "R-EU-R1210-3R9"))
    )
    (comp (ref "R58")
      (value "56k")
      (footprint "eagle-import:R0603")
      (fields
        (field (name "MANUFACTURER") "free choice")
        (field (name "POWER") "63 mW")
        (field (name "TOLERANCE") "±1 %")
      )
      (libsource (lib "eagle-import") (part "R-EU-R0603-56K"))
    )
    (comp (ref "R59")
      (value "0R")
      (footprint "eagle-import:R0603")
      (fields
        (field (name "MANUFACTURER") "free choice")
        (field (name "POWER") "63 mW")
        (field (name "VOLTAGE") "50.0 V")
      )
      (libsource (lib "eagle-import") (part "R-EU-R0603-0R"))
    )
    (comp (ref "R60")
      (value "56k")
      (footprint "eagle-import:R0603")
      (fields
        (field (name "MANUFACTURER") "free choice")
        (field (name "POWER") "63 mW")
        (field (name "TOLERANCE") "±1 %")
      )
      (libsource (lib "eagle-import") (part "R-EU-R0603-56K"))
    )
    (comp (ref "R61")
      (value "56k")
      (footprint "eagle-import:R0603")
      (fields
        (field (name "MANUFACTURER") "free choice")
        (field (name "POWER") "63 mW")
        (field (name "TOLERANCE") "±1 %")
      )
      (libsource (lib "eagle-import") (part "R-EU-R0603-56K"))
    )
    (comp (ref "R62")
      (value "1k1")
      (footprint "eagle-import:R0603")
      (fields
        (field (name "MANUFACTURER") "free choice")
        (field (name "POWER") "63 mW")
        (field (name "TOLERANCE") "±1 %")
      )
      (libsource (lib "eagle-import") (part "R-EU-R0603-1K1"))
    )
    (comp (ref "R63")
      (value "56k")
      (footprint "eagle-import:R0603")
      (fields
        (field (name "MANUFACTURER") "free choice")
        (field (name "POWER") "63 mW")
        (field (name "TOLERANCE") "±1 %")
      )
      (libsource (lib "eagle-import") (part "R-EU-R0603-56K"))
    )
    (comp (ref "R64")
      (value "56k")
      (footprint "eagle-import:R0603")
      (fields
        (field (name "MANUFACTURER") "free choice")
        (field (name "POWER") "63 mW")
        (field (name "TOLERANCE") "±1 %")
      )
      (libsource (lib "eagle-import") (part "R-EU-R0603-56K"))
    )
    (comp (ref "R65")
      (value "56k")
      (footprint "eagle-import:R0603")
      (fields
        (field (name "MANUFACTURER") "free choice")
        (field (name "POWER") "63 mW")
        (field (name "TOLERANCE") "±1 %")
      )
      (libsource (lib "eagle-import") (part "R-EU-R0603-56K"))
    )
    (comp (ref "R66")
      (value "6R2")
      (footprint "eagle-import:R1210")
      (fields
        (field (name "MANUFACTURER") "free choice")
        (field (name "POWER") "333 mW")
        (field (name "TOLERANCE") "±1 %")
      )
      (libsource (lib "eagle-import") (part "R-EU-R1210-6R2"))
    )
    (comp (ref "R67")
      (value "10k")
      (footprint "eagle-import:R0603")
      (fields
        (field (name "MANUFACTURER") "free choice")
        (field (name "POWER") "63 mW")
        (field (name "TOLERANCE") "±1 %")
      )
      (libsource (lib "eagle-import") (part "R-EU-R0603-10K"))
    )
    (comp (ref "R68")
      (value "56k")
      (footprint "eagle-import:R0603")
      (fields
        (field (name "MANUFACTURER") "free choice")
        (field (name "POWER") "63 mW")
        (field (name "TOLERANCE") "±1 %")
      )
      (libsource (lib "eagle-import") (part "R-EU-R0603-56K"))
    )
    (comp (ref "R69")
      (value "6R2")
      (footprint "eagle-import:R1210")
      (fields
        (field (name "MANUFACTURER") "free choice")
        (field (name "POWER") "333 mW")
        (field (name "TOLERANCE") "±1 %")
      )
      (libsource (lib "eagle-import") (part "R-EU-R1210-6R2"))
    )
    (comp (ref "R70")
      (value "R-EU-R0603")
      (footprint "eagle-import:R0603")
      (fields
        (field (name "POWER") "63 mW")
        (field (name "TOLERANCE") "±1 %")
        (field (name "VOLTAGE") "50 V")
      )
      (libsource (lib "eagle-import") (part "R-EU-R0603"))
    )
    (comp (ref "R71")
      (value "R-EU-R0603")
      (footprint "eagle-import:R0603")
      (fields
        (field (name "POWER") "63 mW")
        (field (name "TOLERANCE") "±1 %")
        (field (name "VOLTAGE") "50 V")
      )
      (libsource (lib "eagle-import") (part "R-EU-R0603"))
    )
    (comp (ref "R72")
      (value "0R")
      (footprint "eagle-import:R0603")
      (fields
        (field (name "MANUFACTURER") "free choice")
        (field (name "POWER") "63 mW")
        (field (name "VOLTAGE") "50.0 V")
      )
      (libsource (lib "eagle-import") (part "R-EU-R0603-0R"))
    )
    (comp (ref "R73")
      (value "3R9")
      (footprint "eagle-import:R1210")
      (fields
        (field (name "MANUFACTURER") "free choice")
        (field (name "POWER") "333 mW")
        (field (name "TOLERANCE") "±1 %")
      )
      (libsource (lib "eagle-import") (part "R-EU-R1210-3R9"))
    )
    (comp (ref "R74")
      (value "0R")
      (footprint "eagle-import:R0603")
      (fields
        (field (name "MANUFACTURER") "free choice")
        (field (name "POWER") "63 mW")
        (field (name "VOLTAGE") "50.0 V")
      )
      (libsource (lib "eagle-import") (part "R-EU-R0603-0R"))
    )
    (comp (ref "R75")
      (value "3R9")
      (footprint "eagle-import:R1210")
      (fields
        (field (name "MANUFACTURER") "free choice")
        (field (name "POWER") "333 mW")
        (field (name "TOLERANCE") "±1 %")
      )
      (libsource (lib "eagle-import") (part "R-EU-R1210-3R9"))
    )
    (comp (ref "R76")
      (value "0R")
      (footprint "eagle-import:R0603")
      (fields
        (field (name "MANUFACTURER") "free choice")
        (field (name "POWER") "63 mW")
        (field (name "VOLTAGE") "50.0 V")
      )
      (libsource (lib "eagle-import") (part "R-EU-R0603-0R"))
    )
    (comp (ref "R77")
      (value "0R")
      (footprint "eagle-import:R0603")
      (fields
        (field (name "MANUFACTURER") "free choice")
        (field (name "POWER") "63 mW")
        (field (name "VOLTAGE") "50.0 V")
      )
      (libsource (lib "eagle-import") (part "R-EU-R0603-0R"))
    )
    (comp (ref "R78")
      (value "0R")
      (footprint "eagle-import:R0603")
      (fields
        (field (name "MANUFACTURER") "free choice")
        (field (name "POWER") "63 mW")
        (field (name "VOLTAGE") "50.0 V")
      )
      (libsource (lib "eagle-import") (part "R-EU-R0603-0R"))
    )
    (comp (ref "R79")
      (value "0R")
      (footprint "eagle-import:R0603")
      (fields
        (field (name "MANUFACTURER") "free choice")
        (field (name "POWER") "63 mW")
        (field (name "VOLTAGE") "50.0 V")
      )
      (libsource (lib "eagle-import") (part "R-EU-R0603-0R"))
    )
    (comp (ref "R80")
      (value "0R")
      (footprint "eagle-import:R0603")
      (fields
        (field (name "MANUFACTURER") "free choice")
        (field (name "POWER") "63 mW")
        (field (name "VOLTAGE") "50.0 V")
      )
      (libsource (lib "eagle-import") (part "R-EU-R0603-0R"))
    )
    (comp (ref "R81")
      (value "27R")
      (footprint "eagle-import:R0603")
      (fields
        (field (name "MANUFACTURER") "free choice")
        (field (name "POWER") "63 mW")
        (field (name "TOLERANCE") "±1 %")
      )
      (libsource (lib "eagle-import") (part "R-EU-R0603-27R"))
    )
    (comp (ref "R82")
      (value "27R")
      (footprint "eagle-import:R0603")
      (fields
        (field (name "MANUFACTURER") "free choice")
        (field (name "POWER") "63 mW")
        (field (name "TOLERANCE") "±1 %")
      )
      (libsource (lib "eagle-import") (part "R-EU-R0603-27R"))
    )
    (comp (ref "R83")
      (value "10R")
      (footprint "eagle-import:R1210")
      (fields
        (field (name "MANUFACTURER") "free choice")
        (field (name "POWER") "333 mW")
        (field (name "TOLERANCE") "±1 %")
      )
      (libsource (lib "eagle-import") (part "R-EU-R1210-10R"))
    )
    (comp (ref "R84")
      (value "10R")
      (footprint "eagle-import:R1210")
      (fields
        (field (name "MANUFACTURER") "free choice")
        (field (name "POWER") "333 mW")
        (field (name "TOLERANCE") "±1 %")
      )
      (libsource (lib "eagle-import") (part "R-EU-R1210-10R"))
    )
    (comp (ref "R85")
      (value "R-EU-R0603")
      (footprint "eagle-import:R0603")
      (fields
        (field (name "POWER") "63 mW")
        (field (name "TOLERANCE") "±1 %")
        (field (name "VOLTAGE") "50 V")
      )
      (libsource (lib "eagle-import") (part "R-EU-R0603"))
    )
    (comp (ref "R86")
      (value "R-EU-R0603")
      (footprint "eagle-import:R0603")
      (fields
        (field (name "POWER") "63 mW")
        (field (name "TOLERANCE") "±1 %")
        (field (name "VOLTAGE") "50 V")
      )
      (libsource (lib "eagle-import") (part "R-EU-R0603"))
    )
    (comp (ref "R87")
      (value "100R")
      (footprint "eagle-import:R0603")
      (fields
        (field (name "MANUFACTURER") "free choice")
        (field (name "POWER") "63 mW")
        (field (name "TOLERANCE") "±1 %")
      )
      (libsource (lib "eagle-import") (part "R-EU-R0603-100R"))
    )
    (comp (ref "R88")
      (value "R-EU-R0603")
      (footprint "eagle-import:R0603")
      (fields
        (field (name "POWER") "63 mW")
        (field (name "TOLERANCE") "±1 %")
        (field (name "VOLTAGE") "50 V")
      )
      (libsource (lib "eagle-import") (part "R-EU-R0603"))
    )
    (comp (ref "SW1")
      (value "ATE-1-V")
      (footprint "eagle-import:ATE-1_DIPTRONICS")
      (fields (field (name "MANUFACTURER") "Diptronics"))
      (libsource (lib "eagle-import") (part "ATE-1-V"))
    )
    (comp (ref "T2")
      (value "PMV30ENEA")
      (footprint "eagle-import:SOT-23_NXP")
      (fields (field (name "MANUFACTURER") "Nexperia"))
      (libsource (lib "eagle-import") (part "PMV30ENEA"))
    )
    (comp (ref "T3")
      (value "PMV30ENEA")
      (footprint "eagle-import:SOT-23_NXP")
      (fields (field (name "MANUFACTURER") "Nexperia"))
      (libsource (lib "eagle-import") (part "PMV30ENEA"))
    )
    (comp (ref "T6")
      (value "PMV30ENEA")
      (footprint "eagle-import:SOT-23_NXP")
      (fields (field (name "MANUFACTURER") "Nexperia"))
      (libsource (lib "eagle-import") (part "PMV30ENEA"))
    )
    (comp (ref "T7")
      (value "PMV30ENEA")
      (footprint "eagle-import:SOT-23_NXP")
      (fields (field (name "MANUFACTURER") "Nexperia"))
      (libsource (lib "eagle-import") (part "PMV30ENEA"))
    )
    (comp (ref "T8")
      (value "NX7002AK")
      (footprint "eagle-import:SOT-23_NXP")
      (fields (field (name "MANUFACTURER") "Nexperia"))
      (libsource (lib "eagle-import") (part "NX7002AK"))
    )
    (comp (ref "T10")
      (value "PMV30ENEA")
      (footprint "eagle-import:SOT-23_NXP")
      (fields (field (name "MANUFACTURER") "Nexperia"))
      (libsource (lib "eagle-import") (part "PMV30ENEA"))
    )
    (comp (ref "TP1")
      (value "GND")
      (footprint "eagle-import:TESTPAD_ROUND_1.5MM")
      (libsource (lib "eagle-import") (part "TESTPOINT_ROUND_1.5MM"))
    )
    (comp (ref "TP2")
      (value "+PVCC")
      (footprint "eagle-import:TESTPAD_ROUND_1.5MM")
      (libsource (lib "eagle-import") (part "TESTPOINT_ROUND_1.5MM"))
    )
    (comp (ref "TP3")
      (value "TESTPOINT_ROUND_1.5MM")
      (footprint "eagle-import:TESTPAD_ROUND_1.5MM")
      (libsource (lib "eagle-import") (part "TESTPOINT_ROUND_1.5MM"))
    )
    (comp (ref "TP4")
      (value "TESTPOINT_ROUND_1.5MM")
      (footprint "eagle-import:TESTPAD_ROUND_1.5MM")
      (libsource (lib "eagle-import") (part "TESTPOINT_ROUND_1.5MM"))
    )
    (comp (ref "TP5")
      (value "TESTPOINT_ROUND_1.5MM")
      (footprint "eagle-import:TESTPAD_ROUND_1.5MM")
      (libsource (lib "eagle-import") (part "TESTPOINT_ROUND_1.5MM"))
    )
    (comp (ref "TP6")
      (value "TESTPOINT_ROUND_1.5MM")
      (footprint "eagle-import:TESTPAD_ROUND_1.5MM")
      (libsource (lib "eagle-import") (part "TESTPOINT_ROUND_1.5MM"))
    )
    (comp (ref "TP7")
      (value "TESTPOINT_ROUND_1.5MM")
      (footprint "eagle-import:TESTPAD_ROUND_1.5MM")
      (libsource (lib "eagle-import") (part "TESTPOINT_ROUND_1.5MM"))
    )
    (comp (ref "TP8")
      (value "TESTPOINT_ROUND_1.5MM")
      (footprint "eagle-import:TESTPAD_ROUND_1.5MM")
      (libsource (lib "eagle-import") (part "TESTPOINT_ROUND_1.5MM"))
    )
    (comp (ref "TP9")
      (value "TESTPOINT_ROUND_1.5MM")
      (footprint "eagle-import:TESTPAD_ROUND_1.5MM")
      (libsource (lib "eagle-import") (part "TESTPOINT_ROUND_1.5MM"))
    )
    (comp (ref "TP10")
      (value "TESTPOINT_ROUND_1.5MM")
      (footprint "eagle-import:TESTPAD_ROUND_1.5MM")
      (libsource (lib "eagle-import") (part "TESTPOINT_ROUND_1.5MM"))
    )
    (comp (ref "TP11")
      (value "TESTPOINT_ROUND_1.5MM")
      (footprint "eagle-import:TESTPAD_ROUND_1.5MM")
      (libsource (lib "eagle-import") (part "TESTPOINT_ROUND_1.5MM"))
    )
    (comp (ref "TP12")
      (value "TESTPOINT_ROUND_1.5MM")
      (footprint "eagle-import:TESTPAD_ROUND_1.5MM")
      (libsource (lib "eagle-import") (part "TESTPOINT_ROUND_1.5MM"))
    )
    (comp (ref "TP13")
      (value "SAFETY_SHDN_RST")
      (footprint "eagle-import:TESTPAD_ROUND_1.5MM")
      (libsource (lib "eagle-import") (part "TESTPOINT_ROUND_1.5MM"))
    )
    (comp (ref "TP14")
      (value "TESTPOINT_ROUND_1.5MM")
      (footprint "eagle-import:TESTPAD_ROUND_1.5MM")
      (libsource (lib "eagle-import") (part "TESTPOINT_ROUND_1.5MM"))
    )
    (comp (ref "TP15")
      (value "TESTPOINT_ROUND_1.5MM")
      (footprint "eagle-import:TESTPAD_ROUND_1.5MM")
      (libsource (lib "eagle-import") (part "TESTPOINT_ROUND_1.5MM"))
    )
    (comp (ref "TP16")
      (value "TESTPOINT_ROUND_1.5MM")
      (footprint "eagle-import:TESTPAD_ROUND_1.5MM")
      (libsource (lib "eagle-import") (part "TESTPOINT_ROUND_1.5MM"))
    )
    (comp (ref "TP17")
      (value "TESTPOINT_ROUND_1.5MM")
      (footprint "eagle-import:TESTPAD_ROUND_1.5MM")
      (libsource (lib "eagle-import") (part "TESTPOINT_ROUND_1.5MM"))
    )
    (comp (ref "TP18")
      (value "TESTPOINT_ROUND_1.5MM")
      (footprint "eagle-import:TESTPAD_ROUND_1.5MM")
      (libsource (lib "eagle-import") (part "TESTPOINT_ROUND_1.5MM"))
    )
    (comp (ref "TP19")
      (value "TESTPOINT_ROUND_1.5MM")
      (footprint "eagle-import:TESTPAD_ROUND_1.5MM")
      (libsource (lib "eagle-import") (part "TESTPOINT_ROUND_1.5MM"))
    )
    (comp (ref "TP20")
      (value "TESTPOINT_ROUND_1.5MM")
      (footprint "eagle-import:TESTPAD_ROUND_1.5MM")
      (libsource (lib "eagle-import") (part "TESTPOINT_ROUND_1.5MM"))
    )
    (comp (ref "TP21")
      (value "TESTPOINT_ROUND_1.5MM")
      (footprint "eagle-import:TESTPAD_ROUND_1.5MM")
      (libsource (lib "eagle-import") (part "TESTPOINT_ROUND_1.5MM"))
    )
    (comp (ref "TP22")
      (value "TESTPOINT_ROUND_1.5MM")
      (footprint "eagle-import:TESTPAD_ROUND_1.5MM")
      (libsource (lib "eagle-import") (part "TESTPOINT_ROUND_1.5MM"))
    )
    (comp (ref "TP23")
      (value "TESTPOINT_ROUND_1.5MM")
      (footprint "eagle-import:TESTPAD_ROUND_1.5MM")
      (libsource (lib "eagle-import") (part "TESTPOINT_ROUND_1.5MM"))
    )
    (comp (ref "X1")
      (value "MEC6-120-02-L-DV-A")
      (footprint "eagle-import:MEC6-120-02")
      (fields (field (name "MANUFACTURER") "Samtec"))
      (libsource (lib "eagle-import") (part "MEC6-120-02-L-DV-A"))
    )
    (comp (ref "X2")
      (value "MEC6-120-02-L-DV-A")
      (footprint "eagle-import:MEC6-120-02")
      (fields (field (name "MANUFACTURER") "Samtec"))
      (libsource (lib "eagle-import") (part "MEC6-120-02-L-DV-A"))
    )
    (comp (ref "X3")
      (value "DF37NC-30DS-0.4V")
      (footprint "eagle-import:DF37NC-30DS-0.4V")
      (fields (field (name "MANUFACTURER") "Hirose"))
      (libsource (lib "eagle-import") (part "DF37NC-30DS-0.4V"))
    )
    (comp (ref "X4")
      (value "687112182122")
      (footprint "eagle-import:687112182122_WUERTH")
      (fields (field (name "MANUFACTURER") "Wuerth"))
      (libsource (lib "eagle-import") (part "687112182122"))
    )
    (comp (ref "X5")
      (value "AXE530127")
      (footprint "eagle-import:AXE530127_PANASONIC")
      (fields (field (name "MANUFACTURER") "Panasonic") (field (name "VOLTAGE") "60.0 V"))
      (libsource (lib "eagle-import") (part "AXE530127"))
    )
  )
  (nets
    (net (code "1") (name "+1V2") (class "Default")
      (node (ref "C46") (pin "1") (pinfunction "1_1") (pintype "passive"))
      (node (ref "X1") (pin "20") (pinfunction "20_20") (pintype "passive"))
      (node (ref "X3") (pin "27") (pinfunction "27_27") (pintype "bidirectional"))
    )
    (net (code "2") (name "+1V8") (class "Default")
      (node (ref "C37") (pin "1") (pinfunction "1_1") (pintype "passive"))
      (node (ref "C44") (pin "1") (pinfunction "1_1") (pintype "passive"))
      (node (ref "C45") (pin "1") (pinfunction "1_1") (pintype "passive"))
      (node (ref "C49") (pin "1") (pinfunction "1_1") (pintype "passive"))
      (node (ref "IC12") (pin "5") (pinfunction "VBUS_5") (pintype "input"))
      (node (ref "IC16") (pin "5") (pinfunction "VBUS_5") (pintype "input"))
      (node (ref "IC18") (pin "5") (pinfunction "VBUS_5") (pintype "input"))
      (node (ref "R16") (pin "2") (pinfunction "2_2") (pintype "passive"))
      (node (ref "X1") (pin "18") (pinfunction "18_18") (pintype "passive"))
      (node (ref "X3") (pin "28") (pinfunction "28_28") (pintype "bidirectional"))
    )
    (net (code "3") (name "+2V8") (class "Default")
      (node (ref "C47") (pin "1") (pinfunction "1_1") (pintype "passive"))
      (node (ref "C50") (pin "1") (pinfunction "1_1") (pintype "passive"))
      (node (ref "IC19") (pin "5") (pinfunction "VBUS_5") (pintype "input"))
      (node (ref "R88") (pin "2") (pinfunction "2_2") (pintype "passive"))
      (node (ref "X1") (pin "16") (pinfunction "16_16") (pintype "passive"))
      (node (ref "X3") (pin "21") (pinfunction "21_21") (pintype "bidirectional"))
    )
    (net (code "4") (name "+3V3") (class "Default")
      (node (ref "C11") (pin "1") (pinfunction "1_1") (pintype "passive"))
      (node (ref "C15") (pin "1") (pinfunction "1_1") (pintype "passive"))
      (node (ref "C39") (pin "1") (pinfunction "1_1") (pintype "passive"))
      (node (ref "C51") (pin "1") (pinfunction "1_1") (pintype "passive"))
      (node (ref "D1") (pin "A") (pinfunction "A_A") (pintype "passive"))
      (node (ref "D2") (pin "A") (pinfunction "A_A") (pintype "passive"))
      (node (ref "IC14") (pin "5") (pinfunction "VBUS_5") (pintype "input"))
      (node (ref "IC20") (pin "5") (pinfunction "VBUS_5") (pintype "input"))
      (node (ref "L9") (pin "1") (pinfunction "1_1") (pintype "passive"))
      (node (ref "R17") (pin "2") (pinfunction "2_2") (pintype "passive"))
      (node (ref "R19") (pin "1") (pinfunction "1_1") (pintype "passive"))
      (node (ref "R26") (pin "2") (pinfunction "2_2") (pintype "passive"))
      (node (ref "R27") (pin "2") (pinfunction "2_2") (pintype "passive"))
      (node (ref "R28") (pin "2") (pinfunction "2_2") (pintype "passive"))
      (node (ref "R31") (pin "2") (pinfunction "2_2") (pintype "passive"))
      (node (ref "R36") (pin "2") (pinfunction "2_2") (pintype "passive"))
      (node (ref "R40") (pin "2") (pinfunction "2_2") (pintype "passive"))
      (node (ref "R42") (pin "1") (pinfunction "1_1") (pintype "passive"))
      (node (ref "R60") (pin "2") (pinfunction "2_2") (pintype "passive"))
      (node (ref "R63") (pin "1") (pinfunction "1_1") (pintype "passive"))
      (node (ref "R64") (pin "2") (pinfunction "2_2") (pintype "passive"))
      (node (ref "R72") (pin "1") (pinfunction "1_1") (pintype "passive"))
      (node (ref "R74") (pin "2") (pinfunction "2_2") (pintype "passive"))
      (node (ref "R76") (pin "2") (pinfunction "2_2") (pintype "passive"))
      (node (ref "R77") (pin "2") (pinfunction "2_2") (pintype "passive"))
      (node (ref "R79") (pin "2") (pinfunction "2_2") (pintype "passive"))
      (node (ref "R85") (pin "1") (pinfunction "1_1") (pintype "passive"))
      (node (ref "R86") (pin "1") (pinfunction "1_1") (pintype "passive"))
      (node (ref "TP3") (pin "TP") (pinfunction "TP_TP") (pintype "input"))
      (node (ref "X1") (pin "14") (pinfunction "14_14") (pintype "passive"))
    )
    (net (code "5") (name "+3V6") (class "Default")
      (node (ref "C54") (pin "1") (pinfunction "1_1") (pintype "passive"))
      (node (ref "C55") (pin "1") (pinfunction "1_1") (pintype "passive"))
      (node (ref "C56") (pin "1") (pinfunction "1_1") (pintype "passive"))
      (node (ref "X1") (pin "22") (pinfunction "22_22") (pintype "passive"))
      (node (ref "X5") (pin "1") (pinfunction "1_1") (pintype "passive"))
      (node (ref "X5") (pin "2") (pinfunction "2_2") (pintype "passive"))
      (node (ref "X5") (pin "3") (pinfunction "3_3") (pintype "passive"))
      (node (ref "X5") (pin "4") (pinfunction "4_4") (pintype "passive"))
      (node (ref "X5") (pin "6") (pinfunction "6_6") (pintype "passive"))
      (node (ref "X5") (pin "8") (pinfunction "8_8") (pintype "passive"))
    )
    (net (code "6") (name "+5V") (class "Default")
      (node (ref "C100") (pin "1") (pinfunction "1_1") (pintype "passive"))
      (node (ref "C101") (pin "1") (pinfunction "1_1") (pintype "passive"))
      (node (ref "C102") (pin "1") (pinfunction "1_1") (pintype "passive"))
      (node (ref "C103") (pin "1") (pinfunction "1_1") (pintype "passive"))
      (node (ref "C104") (pin "1") (pinfunction "1_1") (pintype "passive"))
      (node (ref "C105") (pin "1") (pinfunction "1_1") (pintype "passive"))
      (node (ref "C106") (pin "1") (pinfunction "1_1") (pintype "passive"))
      (node (ref "C107") (pin "1") (pinfunction "1_1") (pintype "passive"))
      (node (ref "C108") (pin "1") (pinfunction "1_1") (pintype "passive"))
      (node (ref "C109") (pin "1") (pinfunction "1_1") (pintype "passive"))
      (node (ref "C110") (pin "1") (pinfunction "1_1") (pintype "passive"))
      (node (ref "C111") (pin "1") (pinfunction "1_1") (pintype "passive"))
      (node (ref "C112") (pin "1") (pinfunction "1_1") (pintype "passive"))
      (node (ref "C113") (pin "1") (pinfunction "1_1") (pintype "passive"))
      (node (ref "C114") (pin "1") (pinfunction "1_1") (pintype "passive"))
      (node (ref "C115") (pin "1") (pinfunction "1_1") (pintype "passive"))
      (node (ref "C116") (pin "1") (pinfunction "1_1") (pintype "passive"))
      (node (ref "C117") (pin "1") (pinfunction "1_1") (pintype "passive"))
      (node (ref "C118") (pin "1") (pinfunction "1_1") (pintype "passive"))
      (node (ref "C119") (pin "1") (pinfunction "1_1") (pintype "passive"))
      (node (ref "C120") (pin "1") (pinfunction "1_1") (pintype "passive"))
      (node (ref "C121") (pin "1") (pinfunction "1_1") (pintype "passive"))
      (node (ref "C122") (pin "1") (pinfunction "1_1") (pintype "passive"))
      (node (ref "C123") (pin "1") (pinfunction "1_1") (pintype "passive"))
      (node (ref "C124") (pin "1") (pinfunction "1_1") (pintype "passive"))
      (node (ref "C125") (pin "1") (pinfunction "1_1") (pintype "passive"))
      (node (ref "C126") (pin "1") (pinfunction "1_1") (pintype "passive"))
      (node (ref "C127") (pin "1") (pinfunction "1_1") (pintype "passive"))
      (node (ref "C128") (pin "1") (pinfunction "1_1") (pintype "passive"))
      (node (ref "C129") (pin "1") (pinfunction "1_1") (pintype "passive"))
      (node (ref "C130") (pin "1") (pinfunction "1_1") (pintype "passive"))
      (node (ref "C131") (pin "1") (pinfunction "1_1") (pintype "passive"))
      (node (ref "C132") (pin "1") (pinfunction "1_1") (pintype "passive"))
      (node (ref "C133") (pin "1") (pinfunction "1_1") (pintype "passive"))
      (node (ref "C134") (pin "1") (pinfunction "1_1") (pintype "passive"))
      (node (ref "C135") (pin "1") (pinfunction "1_1") (pintype "passive"))
      (node (ref "C136") (pin "1") (pinfunction "1_1") (pintype "passive"))
      (node (ref "C137") (pin "1") (pinfunction "1_1") (pintype "passive"))
      (node (ref "C138") (pin "1") (pinfunction "1_1") (pintype "passive"))
      (node (ref "C139") (pin "1") (pinfunction "1_1") (pintype "passive"))
      (node (ref "C140") (pin "1") (pinfunction "1_1") (pintype "passive"))
      (node (ref "C141") (pin "1") (pinfunction "1_1") (pintype "passive"))
      (node (ref "C142") (pin "1") (pinfunction "1_1") (pintype "passive"))
      (node (ref "C143") (pin "1") (pinfunction "1_1") (pintype "passive"))
      (node (ref "C144") (pin "1") (pinfunction "1_1") (pintype "passive"))
      (node (ref "C145") (pin "1") (pinfunction "1_1") (pintype "passive"))
      (node (ref "C146") (pin "1") (pinfunction "1_1") (pintype "passive"))
      (node (ref "C147") (pin "1") (pinfunction "1_1") (pintype "passive"))
      (node (ref "C148") (pin "1") (pinfunction "1_1") (pintype "passive"))
      (node (ref "C149") (pin "1") (pinfunction "1_1") (pintype "passive"))
      (node (ref "C150") (pin "1") (pinfunction "1_1") (pintype "passive"))
      (node (ref "C151") (pin "1") (pinfunction "1_1") (pintype "passive"))
      (node (ref "C152") (pin "1") (pinfunction "1_1") (pintype "passive"))
      (node (ref "C153") (pin "1") (pinfunction "1_1") (pintype "passive"))
      (node (ref "C154") (pin "1") (pinfunction "1_1") (pintype "passive"))
      (node (ref "C155") (pin "1") (pinfunction "1_1") (pintype "passive"))
      (node (ref "C156") (pin "1") (pinfunction "1_1") (pintype "passive"))
      (node (ref "C157") (pin "1") (pinfunction "1_1") (pintype "passive"))
      (node (ref "C158") (pin "1") (pinfunction "1_1") (pintype "passive"))
      (node (ref "C159") (pin "1") (pinfunction "1_1") (pintype "passive"))
      (node (ref "C162") (pin "1") (pinfunction "1_1") (pintype "passive"))
      (node (ref "C164") (pin "1") (pinfunction "1_1") (pintype "passive"))
      (node (ref "C165") (pin "1") (pinfunction "1_1") (pintype "passive"))
      (node (ref "C166") (pin "1") (pinfunction "1_1") (pintype "passive"))
      (node (ref "C167") (pin "1") (pinfunction "1_1") (pintype "passive"))
      (node (ref "C168") (pin "1") (pinfunction "1_1") (pintype "passive"))
      (node (ref "C169") (pin "1") (pinfunction "1_1") (pintype "passive"))
      (node (ref "C170") (pin "1") (pinfunction "1_1") (pintype "passive"))
      (node (ref "C171") (pin "1") (pinfunction "1_1") (pintype "passive"))
      (node (ref "C172") (pin "1") (pinfunction "1_1") (pintype "passive"))
      (node (ref "C173") (pin "1") (pinfunction "1_1") (pintype "passive"))
      (node (ref "C174") (pin "1") (pinfunction "1_1") (pintype "passive"))
      (node (ref "C175") (pin "1") (pinfunction "1_1") (pintype "passive"))
      (node (ref "C176") (pin "1") (pinfunction "1_1") (pintype "passive"))
      (node (ref "C177") (pin "1") (pinfunction "1_1") (pintype "passive"))
      (node (ref "C178") (pin "1") (pinfunction "1_1") (pintype "passive"))
      (node (ref "C179") (pin "1") (pinfunction "1_1") (pintype "passive"))
      (node (ref "C180") (pin "1") (pinfunction "1_1") (pintype "passive"))
      (node (ref "C181") (pin "1") (pinfunction "1_1") (pintype "passive"))
      (node (ref "C182") (pin "1") (pinfunction "1_1") (pintype "passive"))
      (node (ref "C183") (pin "1") (pinfunction "1_1") (pintype "passive"))
      (node (ref "C184") (pin "1") (pinfunction "1_1") (pintype "passive"))
      (node (ref "C185") (pin "1") (pinfunction "1_1") (pintype "passive"))
      (node (ref "C186") (pin "1") (pinfunction "1_1") (pintype "passive"))
      (node (ref "C187") (pin "1") (pinfunction "1_1") (pintype "passive"))
      (node (ref "C188") (pin "1") (pinfunction "1_1") (pintype "passive"))
      (node (ref "C189") (pin "1") (pinfunction "1_1") (pintype "passive"))
      (node (ref "C190") (pin "1") (pinfunction "1_1") (pintype "passive"))
      (node (ref "C191") (pin "1") (pinfunction "1_1") (pintype "passive"))
      (node (ref "C192") (pin "1") (pinfunction "1_1") (pintype "passive"))
      (node (ref "C193") (pin "1") (pinfunction "1_1") (pintype "passive"))
      (node (ref "C194") (pin "1") (pinfunction "1_1") (pintype "passive"))
      (node (ref "C195") (pin "1") (pinfunction "1_1") (pintype "passive"))
      (node (ref "C196") (pin "1") (pinfunction "1_1") (pintype "passive"))
      (node (ref "C197") (pin "1") (pinfunction "1_1") (pintype "passive"))
      (node (ref "C198") (pin "1") (pinfunction "1_1") (pintype "passive"))
      (node (ref "C199") (pin "1") (pinfunction "1_1") (pintype "passive"))
      (node (ref "C200") (pin "1") (pinfunction "1_1") (pintype "passive"))
      (node (ref "C201") (pin "1") (pinfunction "1_1") (pintype "passive"))
      (node (ref "C202") (pin "1") (pinfunction "1_1") (pintype "passive"))
      (node (ref "C203") (pin "1") (pinfunction "1_1") (pintype "passive"))
      (node (ref "C204") (pin "1") (pinfunction "1_1") (pintype "passive"))
      (node (ref "C205") (pin "1") (pinfunction "1_1") (pintype "passive"))
      (node (ref "C206") (pin "1") (pinfunction "1_1") (pintype "passive"))
      (node (ref "C207") (pin "1") (pinfunction "1_1") (pintype "passive"))
      (node (ref "C208") (pin "1") (pinfunction "1_1") (pintype "passive"))
      (node (ref "C209") (pin "1") (pinfunction "1_1") (pintype "passive"))
      (node (ref "C210") (pin "1") (pinfunction "1_1") (pintype "passive"))
      (node (ref "C211") (pin "1") (pinfunction "1_1") (pintype "passive"))
      (node (ref "C212") (pin "1") (pinfunction "1_1") (pintype "passive"))
      (node (ref "C213") (pin "1") (pinfunction "1_1") (pintype "passive"))
      (node (ref "C214") (pin "1") (pinfunction "1_1") (pintype "passive"))
      (node (ref "C215") (pin "1") (pinfunction "1_1") (pintype "passive"))
      (node (ref "C216") (pin "1") (pinfunction "1_1") (pintype "passive"))
      (node (ref "C217") (pin "1") (pinfunction "1_1") (pintype "passive"))
      (node (ref "C218") (pin "1") (pinfunction "1_1") (pintype "passive"))
      (node (ref "C219") (pin "1") (pinfunction "1_1") (pintype "passive"))
      (node (ref "C220") (pin "1") (pinfunction "1_1") (pintype "passive"))
      (node (ref "C221") (pin "1") (pinfunction "1_1") (pintype "passive"))
      (node (ref "C222") (pin "1") (pinfunction "1_1") (pintype "passive"))
      (node (ref "C223") (pin "1") (pinfunction "1_1") (pintype "passive"))
      (node (ref "C224") (pin "1") (pinfunction "1_1") (pintype "passive"))
      (node (ref "C225") (pin "1") (pinfunction "1_1") (pintype "passive"))
      (node (ref "C226") (pin "1") (pinfunction "1_1") (pintype "passive"))
      (node (ref "C227") (pin "1") (pinfunction "1_1") (pintype "passive"))
      (node (ref "C228") (pin "1") (pinfunction "1_1") (pintype "passive"))
      (node (ref "C229") (pin "1") (pinfunction "1_1") (pintype "passive"))
      (node (ref "C230") (pin "1") (pinfunction "1_1") (pintype "passive"))
      (node (ref "C231") (pin "1") (pinfunction "1_1") (pintype "passive"))
      (node (ref "C232") (pin "1") (pinfunction "1_1") (pintype "passive"))
      (node (ref "C233") (pin "1") (pinfunction "1_1") (pintype "passive"))
      (node (ref "C234") (pin "1") (pinfunction "1_1") (pintype "passive"))
      (node (ref "C235") (pin "1") (pinfunction "1_1") (pintype "passive"))
      (node (ref "C236") (pin "1") (pinfunction "1_1") (pintype "passive"))
      (node (ref "C237") (pin "1") (pinfunction "1_1") (pintype "passive"))
      (node (ref "C238") (pin "1") (pinfunction "1_1") (pintype "passive"))
      (node (ref "C239") (pin "1") (pinfunction "1_1") (pintype "passive"))
      (node (ref "C240") (pin "1") (pinfunction "1_1") (pintype "passive"))
      (node (ref "C241") (pin "1") (pinfunction "1_1") (pintype "passive"))
      (node (ref "C242") (pin "1") (pinfunction "1_1") (pintype "passive"))
      (node (ref "C243") (pin "1") (pinfunction "1_1") (pintype "passive"))
      (node (ref "C244") (pin "1") (pinfunction "1_1") (pintype "passive"))
      (node (ref "C245") (pin "1") (pinfunction "1_1") (pintype "passive"))
      (node (ref "C246") (pin "1") (pinfunction "1_1") (pintype "passive"))
      (node (ref "C247") (pin "1") (pinfunction "1_1") (pintype "passive"))
      (node (ref "C248") (pin "1") (pinfunction "1_1") (pintype "passive"))
      (node (ref "C249") (pin "1") (pinfunction "1_1") (pintype "passive"))
      (node (ref "C250") (pin "1") (pinfunction "1_1") (pintype "passive"))
      (node (ref "C251") (pin "1") (pinfunction "1_1") (pintype "passive"))
      (node (ref "C252") (pin "1") (pinfunction "1_1") (pintype "passive"))
      (node (ref "C253") (pin "1") (pinfunction "1_1") (pintype "passive"))
      (node (ref "C254") (pin "1") (pinfunction "1_1") (pintype "passive"))
      (node (ref "C255") (pin "1") (pinfunction "1_1") (pintype "passive"))
      (node (ref "C256") (pin "1") (pinfunction "1_1") (pintype "passive"))
      (node (ref "C257") (pin "1") (pinfunction "1_1") (pintype "passive"))
      (node (ref "C258") (pin "1") (pinfunction "1_1") (pintype "passive"))
      (node (ref "C259") (pin "1") (pinfunction "1_1") (pintype "passive"))
      (node (ref "C260") (pin "1") (pinfunction "1_1") (pintype "passive"))
      (node (ref "C261") (pin "1") (pinfunction "1_1") (pintype "passive"))
      (node (ref "C262") (pin "1") (pinfunction "1_1") (pintype "passive"))
      (node (ref "C263") (pin "1") (pinfunction "1_1") (pintype "passive"))
      (node (ref "C264") (pin "1") (pinfunction "1_1") (pintype "passive"))
      (node (ref "C265") (pin "1") (pinfunction "1_1") (pintype "passive"))
      (node (ref "C266") (pin "1") (pinfunction "1_1") (pintype "passive"))
      (node (ref "C270") (pin "1") (pinfunction "1_1") (pintype "passive"))
      (node (ref "C272") (pin "1") (pinfunction "1_1") (pintype "passive"))
      (node (ref "C280") (pin "1") (pinfunction "1_1") (pintype "passive"))
      (node (ref "C281") (pin "1") (pinfunction "1_1") (pintype "passive"))
      (node (ref "C282") (pin "1") (pinfunction "1_1") (pintype "passive"))
      (node (ref "C283") (pin "1") (pinfunction "1_1") (pintype "passive"))
      (node (ref "C284") (pin "1") (pinfunction "1_1") (pintype "passive"))
      (node (ref "C285") (pin "1") (pinfunction "1_1") (pintype "passive"))
      (node (ref "C286") (pin "1") (pinfunction "1_1") (pintype "passive"))
      (node (ref "C287") (pin "1") (pinfunction "1_1") (pintype "passive"))
      (node (ref "C288") (pin "1") (pinfunction "1_1") (pintype "passive"))
      (node (ref "C289") (pin "1") (pinfunction "1_1") (pintype "passive"))
      (node (ref "C290") (pin "1") (pinfunction "1_1") (pintype "passive"))
      (node (ref "C291") (pin "1") (pinfunction "1_1") (pintype "passive"))
      (node (ref "C292") (pin "1") (pinfunction "1_1") (pintype "passive"))
      (node (ref "C293") (pin "1") (pinfunction "1_1") (pintype "passive"))
      (node (ref "C294") (pin "1") (pinfunction "1_1") (pintype "passive"))
      (node (ref "C295") (pin "1") (pinfunction "1_1") (pintype "passive"))
      (node (ref "C296") (pin "1") (pinfunction "1_1") (pintype "passive"))
      (node (ref "C297") (pin "1") (pinfunction "1_1") (pintype "passive"))
      (node (ref "C298") (pin "1") (pinfunction "1_1") (pintype "passive"))
      (node (ref "C299") (pin "1") (pinfunction "1_1") (pintype "passive"))
      (node (ref "C300") (pin "1") (pinfunction "1_1") (pintype "passive"))
      (node (ref "C301") (pin "1") (pinfunction "1_1") (pintype "passive"))
      (node (ref "C302") (pin "1") (pinfunction "1_1") (pintype "passive"))
      (node (ref "C303") (pin "1") (pinfunction "1_1") (pintype "passive"))
      (node (ref "C304") (pin "1") (pinfunction "1_1") (pintype "passive"))
      (node (ref "C305") (pin "1") (pinfunction "1_1") (pintype "passive"))
      (node (ref "C306") (pin "1") (pinfunction "1_1") (pintype "passive"))
      (node (ref "C307") (pin "1") (pinfunction "1_1") (pintype "passive"))
      (node (ref "C308") (pin "1") (pinfunction "1_1") (pintype "passive"))
      (node (ref "C309") (pin "1") (pinfunction "1_1") (pintype "passive"))
      (node (ref "C310") (pin "1") (pinfunction "1_1") (pintype "passive"))
      (node (ref "C311") (pin "1") (pinfunction "1_1") (pintype "passive"))
      (node (ref "C312") (pin "1") (pinfunction "1_1") (pintype "passive"))
      (node (ref "C313") (pin "1") (pinfunction "1_1") (pintype "passive"))
      (node (ref "C314") (pin "1") (pinfunction "1_1") (pintype "passive"))
      (node (ref "C315") (pin "1") (pinfunction "1_1") (pintype "passive"))
      (node (ref "C316") (pin "1") (pinfunction "1_1") (pintype "passive"))
      (node (ref "C317") (pin "1") (pinfunction "1_1") (pintype "passive"))
      (node (ref "C318") (pin "1") (pinfunction "1_1") (pintype "passive"))
      (node (ref "C319") (pin "1") (pinfunction "1_1") (pintype "passive"))
      (node (ref "C320") (pin "1") (pinfunction "1_1") (pintype "passive"))
      (node (ref "C321") (pin "1") (pinfunction "1_1") (pintype "passive"))
      (node (ref "C322") (pin "1") (pinfunction "1_1") (pintype "passive"))
      (node (ref "C323") (pin "1") (pinfunction "1_1") (pintype "passive"))
      (node (ref "C324") (pin "1") (pinfunction "1_1") (pintype "passive"))
      (node (ref "C325") (pin "1") (pinfunction "1_1") (pintype "passive"))
      (node (ref "C326") (pin "1") (pinfunction "1_1") (pintype "passive"))
      (node (ref "C327") (pin "1") (pinfunction "1_1") (pintype "passive"))
      (node (ref "C328") (pin "1") (pinfunction "1_1") (pintype "passive"))
      (node (ref "C329") (pin "1") (pinfunction "1_1") (pintype "passive"))
      (node (ref "C330") (pin "1") (pinfunction "1_1") (pintype "passive"))
      (node (ref "C331") (pin "1") (pinfunction "1_1") (pintype "passive"))
      (node (ref "C332") (pin "1") (pinfunction "1_1") (pintype "passive"))
      (node (ref "C48") (pin "1") (pinfunction "1_1") (pintype "passive"))
      (node (ref "IC100") (pin "2") (pinfunction "VDD_2") (pintype "input"))
      (node (ref "IC101") (pin "2") (pinfunction "VDD_2") (pintype "input"))
      (node (ref "IC102") (pin "2") (pinfunction "VDD_2") (pintype "input"))
      (node (ref "IC103") (pin "2") (pinfunction "VDD_2") (pintype "input"))
      (node (ref "IC104") (pin "2") (pinfunction "VDD_2") (pintype "input"))
      (node (ref "IC105") (pin "2") (pinfunction "VDD_2") (pintype "input"))
      (node (ref "IC106") (pin "2") (pinfunction "VDD_2") (pintype "input"))
      (node (ref "IC107") (pin "2") (pinfunction "VDD_2") (pintype "input"))
      (node (ref "IC108") (pin "2") (pinfunction "VDD_2") (pintype "input"))
      (node (ref "IC109") (pin "2") (pinfunction "VDD_2") (pintype "input"))
      (node (ref "IC110") (pin "2") (pinfunction "VDD_2") (pintype "input"))
      (node (ref "IC111") (pin "2") (pinfunction "VDD_2") (pintype "input"))
      (node (ref "IC112") (pin "2") (pinfunction "VDD_2") (pintype "input"))
      (node (ref "IC113") (pin "2") (pinfunction "VDD_2") (pintype "input"))
      (node (ref "IC114") (pin "2") (pinfunction "VDD_2") (pintype "input"))
      (node (ref "IC115") (pin "2") (pinfunction "VDD_2") (pintype "input"))
      (node (ref "IC116") (pin "2") (pinfunction "VDD_2") (pintype "input"))
      (node (ref "IC117") (pin "2") (pinfunction "VDD_2") (pintype "input"))
      (node (ref "IC118") (pin "2") (pinfunction "VDD_2") (pintype "input"))
      (node (ref "IC119") (pin "2") (pinfunction "VDD_2") (pintype "input"))
      (node (ref "IC120") (pin "2") (pinfunction "VDD_2") (pintype "input"))
      (node (ref "IC121") (pin "2") (pinfunction "VDD_2") (pintype "input"))
      (node (ref "IC122") (pin "2") (pinfunction "VDD_2") (pintype "input"))
      (node (ref "IC123") (pin "2") (pinfunction "VDD_2") (pintype "input"))
      (node (ref "IC124") (pin "2") (pinfunction "VDD_2") (pintype "input"))
      (node (ref "IC125") (pin "2") (pinfunction "VDD_2") (pintype "input"))
      (node (ref "IC126") (pin "2") (pinfunction "VDD_2") (pintype "input"))
      (node (ref "IC127") (pin "2") (pinfunction "VDD_2") (pintype "input"))
      (node (ref "IC128") (pin "2") (pinfunction "VDD_2") (pintype "input"))
      (node (ref "IC129") (pin "2") (pinfunction "VDD_2") (pintype "input"))
      (node (ref "IC130") (pin "2") (pinfunction "VDD_2") (pintype "input"))
      (node (ref "IC131") (pin "2") (pinfunction "VDD_2") (pintype "input"))
      (node (ref "IC132") (pin "2") (pinfunction "VDD_2") (pintype "input"))
      (node (ref "IC133") (pin "2") (pinfunction "VDD_2") (pintype "input"))
      (node (ref "IC134") (pin "2") (pinfunction "VDD_2") (pintype "input"))
      (node (ref "IC135") (pin "2") (pinfunction "VDD_2") (pintype "input"))
      (node (ref "IC136") (pin "2") (pinfunction "VDD_2") (pintype "input"))
      (node (ref "IC137") (pin "2") (pinfunction "VDD_2") (pintype "input"))
      (node (ref "IC138") (pin "2") (pinfunction "VDD_2") (pintype "input"))
      (node (ref "IC139") (pin "2") (pinfunction "VDD_2") (pintype "input"))
      (node (ref "IC140") (pin "2") (pinfunction "VDD_2") (pintype "input"))
      (node (ref "IC141") (pin "2") (pinfunction "VDD_2") (pintype "input"))
      (node (ref "IC142") (pin "2") (pinfunction "VDD_2") (pintype "input"))
      (node (ref "IC143") (pin "2") (pinfunction "VDD_2") (pintype "input"))
      (node (ref "IC144") (pin "2") (pinfunction "VDD_2") (pintype "input"))
      (node (ref "IC145") (pin "2") (pinfunction "VDD_2") (pintype "input"))
      (node (ref "IC146") (pin "2") (pinfunction "VDD_2") (pintype "input"))
      (node (ref "IC147") (pin "2") (pinfunction "VDD_2") (pintype "input"))
      (node (ref "IC148") (pin "2") (pinfunction "VDD_2") (pintype "input"))
      (node (ref "IC149") (pin "2") (pinfunction "VDD_2") (pintype "input"))
      (node (ref "IC150") (pin "2") (pinfunction "VDD_2") (pintype "input"))
      (node (ref "IC151") (pin "2") (pinfunction "VDD_2") (pintype "input"))
      (node (ref "IC152") (pin "2") (pinfunction "VDD_2") (pintype "input"))
      (node (ref "IC153") (pin "2") (pinfunction "VDD_2") (pintype "input"))
      (node (ref "IC154") (pin "2") (pinfunction "VDD_2") (pintype "input"))
      (node (ref "IC155") (pin "2") (pinfunction "VDD_2") (pintype "input"))
      (node (ref "IC156") (pin "2") (pinfunction "VDD_2") (pintype "input"))
      (node (ref "IC157") (pin "2") (pinfunction "VDD_2") (pintype "input"))
      (node (ref "IC158") (pin "2") (pinfunction "VDD_2") (pintype "input"))
      (node (ref "IC159") (pin "2") (pinfunction "VDD_2") (pintype "input"))
      (node (ref "IC160") (pin "2") (pinfunction "VDD_2") (pintype "input"))
      (node (ref "IC161") (pin "2") (pinfunction "VDD_2") (pintype "input"))
      (node (ref "IC162") (pin "2") (pinfunction "VDD_2") (pintype "input"))
      (node (ref "IC163") (pin "2") (pinfunction "VDD_2") (pintype "input"))
      (node (ref "IC164") (pin "2") (pinfunction "VDD_2") (pintype "input"))
      (node (ref "IC165") (pin "2") (pinfunction "VDD_2") (pintype "input"))
      (node (ref "IC166") (pin "2") (pinfunction "VDD_2") (pintype "input"))
      (node (ref "IC167") (pin "2") (pinfunction "VDD_2") (pintype "input"))
      (node (ref "IC168") (pin "2") (pinfunction "VDD_2") (pintype "input"))
      (node (ref "IC169") (pin "2") (pinfunction "VDD_2") (pintype "input"))
      (node (ref "IC17") (pin "5") (pinfunction "VBUS_5") (pintype "input"))
      (node (ref "IC170") (pin "2") (pinfunction "VDD_2") (pintype "input"))
      (node (ref "IC171") (pin "2") (pinfunction "VDD_2") (pintype "input"))
      (node (ref "IC172") (pin "2") (pinfunction "VDD_2") (pintype "input"))
      (node (ref "IC173") (pin "2") (pinfunction "VDD_2") (pintype "input"))
      (node (ref "IC174") (pin "2") (pinfunction "VDD_2") (pintype "input"))
      (node (ref "IC175") (pin "2") (pinfunction "VDD_2") (pintype "input"))
      (node (ref "IC176") (pin "2") (pinfunction "VDD_2") (pintype "input"))
      (node (ref "IC177") (pin "2") (pinfunction "VDD_2") (pintype "input"))
      (node (ref "IC178") (pin "2") (pinfunction "VDD_2") (pintype "input"))
      (node (ref "IC179") (pin "2") (pinfunction "VDD_2") (pintype "input"))
      (node (ref "IC180") (pin "2") (pinfunction "VDD_2") (pintype "input"))
      (node (ref "IC181") (pin "2") (pinfunction "VDD_2") (pintype "input"))
      (node (ref "IC182") (pin "2") (pinfunction "VDD_2") (pintype "input"))
      (node (ref "IC183") (pin "2") (pinfunction "VDD_2") (pintype "input"))
      (node (ref "IC184") (pin "2") (pinfunction "VDD_2") (pintype "input"))
      (node (ref "IC185") (pin "2") (pinfunction "VDD_2") (pintype "input"))
      (node (ref "IC186") (pin "2") (pinfunction "VDD_2") (pintype "input"))
      (node (ref "IC187") (pin "2") (pinfunction "VDD_2") (pintype "input"))
      (node (ref "IC188") (pin "2") (pinfunction "VDD_2") (pintype "input"))
      (node (ref "IC189") (pin "2") (pinfunction "VDD_2") (pintype "input"))
      (node (ref "IC190") (pin "2") (pinfunction "VDD_2") (pintype "input"))
      (node (ref "IC191") (pin "2") (pinfunction "VDD_2") (pintype "input"))
      (node (ref "IC192") (pin "2") (pinfunction "VDD_2") (pintype "input"))
      (node (ref "IC193") (pin "2") (pinfunction "VDD_2") (pintype "input"))
      (node (ref "IC194") (pin "2") (pinfunction "VDD_2") (pintype "input"))
      (node (ref "IC195") (pin "2") (pinfunction "VDD_2") (pintype "input"))
      (node (ref "IC196") (pin "2") (pinfunction "VDD_2") (pintype "input"))
      (node (ref "IC197") (pin "2") (pinfunction "VDD_2") (pintype "input"))
      (node (ref "IC198") (pin "2") (pinfunction "VDD_2") (pintype "input"))
      (node (ref "IC199") (pin "2") (pinfunction "VDD_2") (pintype "input"))
      (node (ref "IC200") (pin "2") (pinfunction "VDD_2") (pintype "input"))
      (node (ref "IC201") (pin "2") (pinfunction "VDD_2") (pintype "input"))
      (node (ref "IC202") (pin "2") (pinfunction "VDD_2") (pintype "input"))
      (node (ref "IC203") (pin "2") (pinfunction "VDD_2") (pintype "input"))
      (node (ref "IC204") (pin "2") (pinfunction "VDD_2") (pintype "input"))
      (node (ref "IC205") (pin "2") (pinfunction "VDD_2") (pintype "input"))
      (node (ref "IC206") (pin "2") (pinfunction "VDD_2") (pintype "input"))
      (node (ref "IC207") (pin "2") (pinfunction "VDD_2") (pintype "input"))
      (node (ref "IC208") (pin "2") (pinfunction "VDD_2") (pintype "input"))
      (node (ref "IC209") (pin "2") (pinfunction "VDD_2") (pintype "input"))
      (node (ref "IC210") (pin "2") (pinfunction "VDD_2") (pintype "input"))
      (node (ref "IC211") (pin "2") (pinfunction "VDD_2") (pintype "input"))
      (node (ref "IC212") (pin "2") (pinfunction "VDD_2") (pintype "input"))
      (node (ref "IC213") (pin "2") (pinfunction "VDD_2") (pintype "input"))
      (node (ref "IC214") (pin "2") (pinfunction "VDD_2") (pintype "input"))
      (node (ref "IC215") (pin "2") (pinfunction "VDD_2") (pintype "input"))
      (node (ref "IC216") (pin "2") (pinfunction "VDD_2") (pintype "input"))
      (node (ref "IC217") (pin "2") (pinfunction "VDD_2") (pintype "input"))
      (node (ref "IC218") (pin "2") (pinfunction "VDD_2") (pintype "input"))
      (node (ref "IC219") (pin "2") (pinfunction "VDD_2") (pintype "input"))
      (node (ref "IC220") (pin "2") (pinfunction "VDD_2") (pintype "input"))
      (node (ref "IC221") (pin "2") (pinfunction "VDD_2") (pintype "input"))
      (node (ref "IC222") (pin "2") (pinfunction "VDD_2") (pintype "input"))
      (node (ref "IC223") (pin "2") (pinfunction "VDD_2") (pintype "input"))
      (node (ref "IC224") (pin "2") (pinfunction "VDD_2") (pintype "input"))
      (node (ref "IC225") (pin "2") (pinfunction "VDD_2") (pintype "input"))
      (node (ref "IC226") (pin "2") (pinfunction "VDD_2") (pintype "input"))
      (node (ref "IC227") (pin "2") (pinfunction "VDD_2") (pintype "input"))
      (node (ref "IC228") (pin "2") (pinfunction "VDD_2") (pintype "input"))
      (node (ref "IC229") (pin "2") (pinfunction "VDD_2") (pintype "input"))
      (node (ref "IC230") (pin "2") (pinfunction "VDD_2") (pintype "input"))
      (node (ref "IC231") (pin "2") (pinfunction "VDD_2") (pintype "input"))
      (node (ref "IC232") (pin "2") (pinfunction "VDD_2") (pintype "input"))
      (node (ref "IC233") (pin "2") (pinfunction "VDD_2") (pintype "input"))
      (node (ref "IC234") (pin "2") (pinfunction "VDD_2") (pintype "input"))
      (node (ref "IC235") (pin "2") (pinfunction "VDD_2") (pintype "input"))
      (node (ref "IC236") (pin "2") (pinfunction "VDD_2") (pintype "input"))
      (node (ref "IC237") (pin "2") (pinfunction "VDD_2") (pintype "input"))
      (node (ref "IC238") (pin "2") (pinfunction "VDD_2") (pintype "input"))
      (node (ref "IC239") (pin "2") (pinfunction "VDD_2") (pintype "input"))
      (node (ref "IC240") (pin "2") (pinfunction "VDD_2") (pintype "input"))
      (node (ref "IC241") (pin "2") (pinfunction "VDD_2") (pintype "input"))
      (node (ref "IC242") (pin "2") (pinfunction "VDD_2") (pintype "input"))
      (node (ref "IC243") (pin "2") (pinfunction "VDD_2") (pintype "input"))
      (node (ref "IC244") (pin "2") (pinfunction "VDD_2") (pintype "input"))
      (node (ref "IC245") (pin "2") (pinfunction "VDD_2") (pintype "input"))
      (node (ref "IC246") (pin "2") (pinfunction "VDD_2") (pintype "input"))
      (node (ref "IC247") (pin "2") (pinfunction "VDD_2") (pintype "input"))
      (node (ref "IC248") (pin "2") (pinfunction "VDD_2") (pintype "input"))
      (node (ref "IC249") (pin "2") (pinfunction "VDD_2") (pintype "input"))
      (node (ref "IC250") (pin "2") (pinfunction "VDD_2") (pintype "input"))
      (node (ref "IC251") (pin "2") (pinfunction "VDD_2") (pintype "input"))
      (node (ref "IC252") (pin "2") (pinfunction "VDD_2") (pintype "input"))
      (node (ref "IC253") (pin "2") (pinfunction "VDD_2") (pintype "input"))
      (node (ref "IC254") (pin "2") (pinfunction "VDD_2") (pintype "input"))
      (node (ref "IC255") (pin "2") (pinfunction "VDD_2") (pintype "input"))
      (node (ref "IC256") (pin "2") (pinfunction "VDD_2") (pintype "input"))
      (node (ref "IC257") (pin "2") (pinfunction "VDD_2") (pintype "input"))
      (node (ref "IC258") (pin "2") (pinfunction "VDD_2") (pintype "input"))
      (node (ref "IC259") (pin "2") (pinfunction "VDD_2") (pintype "input"))
      (node (ref "IC260") (pin "2") (pinfunction "VDD_2") (pintype "input"))
      (node (ref "IC261") (pin "2") (pinfunction "VDD_2") (pintype "input"))
      (node (ref "IC262") (pin "2") (pinfunction "VDD_2") (pintype "input"))
      (node (ref "IC263") (pin "2") (pinfunction "VDD_2") (pintype "input"))
      (node (ref "IC264") (pin "2") (pinfunction "VDD_2") (pintype "input"))
      (node (ref "IC265") (pin "2") (pinfunction "VDD_2") (pintype "input"))
      (node (ref "IC266") (pin "2") (pinfunction "VDD_2") (pintype "input"))
      (node (ref "IC267") (pin "2") (pinfunction "VDD_2") (pintype "input"))
      (node (ref "IC268") (pin "2") (pinfunction "VDD_2") (pintype "input"))
      (node (ref "IC269") (pin "2") (pinfunction "VDD_2") (pintype "input"))
      (node (ref "IC270") (pin "2") (pinfunction "VDD_2") (pintype "input"))
      (node (ref "IC271") (pin "2") (pinfunction "VDD_2") (pintype "input"))
      (node (ref "IC272") (pin "2") (pinfunction "VDD_2") (pintype "input"))
      (node (ref "IC273") (pin "2") (pinfunction "VDD_2") (pintype "input"))
      (node (ref "IC274") (pin "2") (pinfunction "VDD_2") (pintype "input"))
      (node (ref "IC275") (pin "2") (pinfunction "VDD_2") (pintype "input"))
      (node (ref "IC276") (pin "2") (pinfunction "VDD_2") (pintype "input"))
      (node (ref "IC277") (pin "2") (pinfunction "VDD_2") (pintype "input"))
      (node (ref "IC278") (pin "2") (pinfunction "VDD_2") (pintype "input"))
      (node (ref "IC279") (pin "2") (pinfunction "VDD_2") (pintype "input"))
      (node (ref "IC280") (pin "2") (pinfunction "VDD_2") (pintype "input"))
      (node (ref "IC281") (pin "2") (pinfunction "VDD_2") (pintype "input"))
      (node (ref "IC282") (pin "2") (pinfunction "VDD_2") (pintype "input"))
      (node (ref "IC283") (pin "2") (pinfunction "VDD_2") (pintype "input"))
      (node (ref "IC284") (pin "2") (pinfunction "VDD_2") (pintype "input"))
      (node (ref "IC285") (pin "2") (pinfunction "VDD_2") (pintype "input"))
      (node (ref "IC286") (pin "2") (pinfunction "VDD_2") (pintype "input"))
      (node (ref "IC287") (pin "2") (pinfunction "VDD_2") (pintype "input"))
      (node (ref "IC288") (pin "2") (pinfunction "VDD_2") (pintype "input"))
      (node (ref "IC289") (pin "2") (pinfunction "VDD_2") (pintype "input"))
      (node (ref "IC290") (pin "2") (pinfunction "VDD_2") (pintype "input"))
      (node (ref "IC291") (pin "2") (pinfunction "VDD_2") (pintype "input"))
      (node (ref "IC292") (pin "2") (pinfunction "VDD_2") (pintype "input"))
      (node (ref "IC293") (pin "2") (pinfunction "VDD_2") (pintype "input"))
      (node (ref "IC294") (pin "2") (pinfunction "VDD_2") (pintype "input"))
      (node (ref "IC295") (pin "2") (pinfunction "VDD_2") (pintype "input"))
      (node (ref "IC296") (pin "2") (pinfunction "VDD_2") (pintype "input"))
      (node (ref "IC297") (pin "2") (pinfunction "VDD_2") (pintype "input"))
      (node (ref "IC298") (pin "2") (pinfunction "VDD_2") (pintype "input"))
      (node (ref "IC299") (pin "2") (pinfunction "VDD_2") (pintype "input"))
      (node (ref "IC300") (pin "2") (pinfunction "VDD_2") (pintype "input"))
      (node (ref "IC301") (pin "2") (pinfunction "VDD_2") (pintype "input"))
      (node (ref "IC302") (pin "2") (pinfunction "VDD_2") (pintype "input"))
      (node (ref "IC303") (pin "2") (pinfunction "VDD_2") (pintype "input"))
      (node (ref "IC304") (pin "2") (pinfunction "VDD_2") (pintype "input"))
      (node (ref "IC305") (pin "2") (pinfunction "VDD_2") (pintype "input"))
      (node (ref "IC306") (pin "2") (pinfunction "VDD_2") (pintype "input"))
      (node (ref "IC307") (pin "2") (pinfunction "VDD_2") (pintype "input"))
      (node (ref "IC308") (pin "2") (pinfunction "VDD_2") (pintype "input"))
      (node (ref "IC309") (pin "2") (pinfunction "VDD_2") (pintype "input"))
      (node (ref "IC310") (pin "2") (pinfunction "VDD_2") (pintype "input"))
      (node (ref "IC311") (pin "2") (pinfunction "VDD_2") (pintype "input"))
      (node (ref "IC312") (pin "2") (pinfunction "VDD_2") (pintype "input"))
      (node (ref "IC313") (pin "2") (pinfunction "VDD_2") (pintype "input"))
      (node (ref "IC314") (pin "2") (pinfunction "VDD_2") (pintype "input"))
      (node (ref "IC315") (pin "2") (pinfunction "VDD_2") (pintype "input"))
      (node (ref "IC316") (pin "2") (pinfunction "VDD_2") (pintype "input"))
      (node (ref "IC317") (pin "2") (pinfunction "VDD_2") (pintype "input"))
      (node (ref "IC318") (pin "2") (pinfunction "VDD_2") (pintype "input"))
      (node (ref "IC319") (pin "2") (pinfunction "VDD_2") (pintype "input"))
      (node (ref "IC320") (pin "2") (pinfunction "VDD_2") (pintype "input"))
      (node (ref "IC321") (pin "2") (pinfunction "VDD_2") (pintype "input"))
      (node (ref "IC322") (pin "2") (pinfunction "VDD_2") (pintype "input"))
      (node (ref "IC323") (pin "2") (pinfunction "VDD_2") (pintype "input"))
      (node (ref "IC324") (pin "2") (pinfunction "VDD_2") (pintype "input"))
      (node (ref "IC325") (pin "2") (pinfunction "VDD_2") (pintype "input"))
      (node (ref "IC326") (pin "2") (pinfunction "VDD_2") (pintype "input"))
      (node (ref "IC327") (pin "2") (pinfunction "VDD_2") (pintype "input"))
      (node (ref "IC328") (pin "2") (pinfunction "VDD_2") (pintype "input"))
      (node (ref "IC329") (pin "2") (pinfunction "VDD_2") (pintype "input"))
      (node (ref "IC330") (pin "2") (pinfunction "VDD_2") (pintype "input"))
      (node (ref "IC331") (pin "2") (pinfunction "VDD_2") (pintype "input"))
      (node (ref "IC332") (pin "2") (pinfunction "VDD_2") (pintype "input"))
      (node (ref "TP7") (pin "TP") (pinfunction "TP_TP") (pintype "input"))
      (node (ref "X1") (pin "23") (pinfunction "23_23") (pintype "passive"))
      (node (ref "X1") (pin "25") (pinfunction "25_25") (pintype "passive"))
    )
    (net (code "7") (name "+INTEGRAL_PHOTOVOLTAGE") (class "Default")
      (node (ref "IC23") (pin "3") (pinfunction "S2A_3") (pintype "passive"))
      (node (ref "R58") (pin "2") (pinfunction "2_2") (pintype "passive"))
    )
    (net (code "8") (name "+PVCC") (class "Default")
      (node (ref "C1") (pin "1") (pinfunction "1_1") (pintype "passive"))
      (node (ref "C12") (pin "1") (pinfunction "1_1") (pintype "passive"))
      (node (ref "C13") (pin "1") (pinfunction "1_1") (pintype "passive"))
      (node (ref "C14") (pin "1") (pinfunction "1_1") (pintype "passive"))
      (node (ref "C16") (pin "1") (pinfunction "1_1") (pintype "passive"))
      (node (ref "C2") (pin "1") (pinfunction "1_1") (pintype "passive"))
      (node (ref "C20") (pin "1") (pinfunction "1_1") (pintype "passive"))
      (node (ref "C21") (pin "1") (pinfunction "1_1") (pintype "passive"))
      (node (ref "C22") (pin "1") (pinfunction "1_1") (pintype "passive"))
      (node (ref "C25") (pin "1") (pinfunction "1_1") (pintype "passive"))
      (node (ref "C27") (pin "1") (pinfunction "1_1") (pintype "passive"))
      (node (ref "C28") (pin "1") (pinfunction "1_1") (pintype "passive"))
      (node (ref "C30") (pin "1") (pinfunction "1_1") (pintype "passive"))
      (node (ref "C32") (pin "1") (pinfunction "1_1") (pintype "passive"))
      (node (ref "C33") (pin "1") (pinfunction "1_1") (pintype "passive"))
      (node (ref "C4") (pin "1") (pinfunction "1_1") (pintype "passive"))
      (node (ref "C41") (pin "1") (pinfunction "1_1") (pintype "passive"))
      (node (ref "C42") (pin "1") (pinfunction "1_1") (pintype "passive"))
      (node (ref "C43") (pin "1") (pinfunction "1_1") (pintype "passive"))
      (node (ref "R15") (pin "2") (pinfunction "2_2") (pintype "passive"))
      (node (ref "R20") (pin "2") (pinfunction "2_2") (pintype "passive"))
      (node (ref "R22") (pin "2") (pinfunction "2_2") (pintype "passive"))
      (node (ref "R25") (pin "2") (pinfunction "2_2") (pintype "passive"))
      (node (ref "R29") (pin "2") (pinfunction "2_2") (pintype "passive"))
      (node (ref "R34") (pin "2") (pinfunction "2_2") (pintype "passive"))
      (node (ref "R35") (pin "2") (pinfunction "2_2") (pintype "passive"))
      (node (ref "R43") (pin "2") (pinfunction "2_2") (pintype "passive"))
      (node (ref "R46") (pin "2") (pinfunction "2_2") (pintype "passive"))
      (node (ref "R52") (pin "2") (pinfunction "2_2") (pintype "passive"))
      (node (ref "R57") (pin "2") (pinfunction "2_2") (pintype "passive"))
      (node (ref "R66") (pin "2") (pinfunction "2_2") (pintype "passive"))
      (node (ref "R69") (pin "2") (pinfunction "2_2") (pintype "passive"))
      (node (ref "R73") (pin "2") (pinfunction "2_2") (pintype "passive"))
      (node (ref "R75") (pin "2") (pinfunction "2_2") (pintype "passive"))
      (node (ref "R8") (pin "2") (pinfunction "2_2") (pintype "passive"))
      (node (ref "R83") (pin "2") (pinfunction "2_2") (pintype "passive"))
      (node (ref "R84") (pin "2") (pinfunction "2_2") (pintype "passive"))
      (node (ref "TP2") (pin "TP") (pinfunction "TP_TP") (pintype "input"))
      (node (ref "X2") (pin "02") (pinfunction "2_02") (pintype "passive"))
      (node (ref "X2") (pin "04") (pinfunction "4_04") (pintype "passive"))
      (node (ref "X2") (pin "06") (pinfunction "6_06") (pintype "passive"))
      (node (ref "X2") (pin "08") (pinfunction "8_08") (pintype "passive"))
    )
    (net (code "9") (name "+VBAT") (class "Default")
      (node (ref "R1") (pin "1") (pinfunction "1_1") (pintype "passive"))
      (node (ref "R38") (pin "1") (pinfunction "1_1") (pintype "passive"))
      (node (ref "R44") (pin "1") (pinfunction "1_1") (pintype "passive"))
      (node (ref "R78") (pin "1") (pinfunction "1_1") (pintype "passive"))
      (node (ref "R9") (pin "1") (pinfunction "1_1") (pintype "passive"))
      (node (ref "TP4") (pin "TP") (pinfunction "TP_TP") (pintype "input"))
      (node (ref "X1") (pin "30") (pinfunction "30_30") (pintype "passive"))
    )
    (net (code "10") (name "-INTEGRAL_PHOTOVOLTAGE") (class "Default")
      (node (ref "C31") (pin "2") (pinfunction "2_2") (pintype "passive"))
      (node (ref "IC11") (pin "1") (pinfunction "OUT_1") (pintype "output"))
      (node (ref "IC23") (pin "2") (pinfunction "S1A_2") (pintype "passive"))
      (node (ref "R41") (pin "1") (pinfunction "1_1") (pintype "passive"))
      (node (ref "R68") (pin "2") (pinfunction "2_2") (pintype "passive"))
    )
    (net (code "11") (name "/CAM1_RGB_~{PWDN_1V8}") (class "Default")
      (node (ref "IC12") (pin "3") (pinfunction "I/O2_3") (pintype "passive"))
      (node (ref "X1") (pin "08") (pinfunction "8_08") (pintype "passive"))
      (node (ref "X3") (pin "26") (pinfunction "26_26") (pintype "bidirectional"))
    )
    (net (code "12") (name "/CAM3_TOF_~{PWDN}_1V8") (class "Default")
      (node (ref "IC18") (pin "6") (pinfunction "I/O4_6") (pintype "passive"))
      (node (ref "X2") (pin "16") (pinfunction "16_16") (pintype "passive"))
      (node (ref "X5") (pin "30") (pinfunction "30_30") (pintype "passive"))
    )
    (net (code "13") (name "/FET_DRV_~{EN}") (class "Default")
      (node (ref "IC1") (pin "4") (pinfunction "IN-_4") (pintype "input"))
      (node (ref "IC10") (pin "4") (pinfunction "IN-_4") (pintype "input"))
      (node (ref "IC13") (pin "4") (pinfunction "IN-_4") (pintype "input"))
      (node (ref "IC2") (pin "4") (pinfunction "IN-_4") (pintype "input"))
      (node (ref "IC8") (pin "4") (pinfunction "IN-_4") (pintype "input"))
      (node (ref "T8") (pin "3") (pinfunction "D_3") (pintype "passive"))
    )
    (net (code "14") (name "/PVCC_SHDN_RST") (class "Default")
      (node (ref "R37") (pin "1") (pinfunction "1_1") (pintype "passive"))
      (node (ref "TP13") (pin "TP") (pinfunction "TP_TP") (pintype "input"))
    )
    (net (code "15") (name "/VCC_IO") (class "Default")
      (node (ref "C52") (pin "1") (pinfunction "1_1") (pintype "passive"))
      (node (ref "R88") (pin "1") (pinfunction "1_1") (pintype "passive"))
      (node (ref "X4") (pin "4") (pinfunction "4_4") (pintype "passive"))
    )
    (net (code "16") (name "/VIN_A") (class "Default")
      (node (ref "C53") (pin "1") (pinfunction "1_1") (pintype "passive"))
      (node (ref "L9") (pin "2") (pinfunction "2_2") (pintype "passive"))
      (node (ref "X4") (pin "3") (pinfunction "3_3") (pintype "passive"))
    )
    (net (code "17") (name "/~{PVCC_SHDN}") (class "Default")
      (node (ref "C15") (pin "2") (pinfunction "2_2") (pintype "passive"))
      (node (ref "IC9") (pin "15") (pinfunction "~{CLR}_15") (pintype "input"))
      (node (ref "R24") (pin "2") (pinfunction "2_2") (pintype "passive"))
      (node (ref "R31") (pin "1") (pinfunction "1_1") (pintype "passive"))
      (node (ref "TP11") (pin "TP") (pinfunction "TP_TP") (pintype "input"))
    )
    (net (code "18") (name "CAM1_RGB_CLK_N") (class "Default")
      (node (ref "IC21") (pin "7") (pinfunction "I/O5_7") (pintype "passive"))
      (node (ref "X1") (pin "05") (pinfunction "5_05") (pintype "passive"))
      (node (ref "X3") (pin "5") (pinfunction "5_5") (pintype "bidirectional"))
    )
    (net (code "19") (name "CAM1_RGB_CLK_P") (class "Default")
      (node (ref "IC21") (pin "8") (pinfunction "I/O6_8") (pintype "passive"))
      (node (ref "X1") (pin "03") (pinfunction "3_03") (pintype "passive"))
      (node (ref "X3") (pin "4") (pinfunction "4_4") (pintype "bidirectional"))
    )
    (net (code "20") (name "CAM1_RGB_D0_N") (class "Default")
      (node (ref "IC21") (pin "4") (pinfunction "I/O3_4") (pintype "passive"))
      (node (ref "X1") (pin "11") (pinfunction "11_11") (pintype "passive"))
      (node (ref "X3") (pin "8") (pinfunction "8_8") (pintype "bidirectional"))
    )
    (net (code "21") (name "CAM1_RGB_D0_P") (class "Default")
      (node (ref "IC21") (pin "5") (pinfunction "I/O4_5") (pintype "passive"))
      (node (ref "X1") (pin "09") (pinfunction "9_09") (pintype "passive"))
      (node (ref "X3") (pin "7") (pinfunction "7_7") (pintype "bidirectional"))
    )
    (net (code "22") (name "CAM1_RGB_D1_N") (class "Default")
      (node (ref "IC21") (pin "1") (pinfunction "I/O1_1") (pintype "passive"))
      (node (ref "X1") (pin "17") (pinfunction "17_17") (pintype "passive"))
      (node (ref "X3") (pin "11") (pinfunction "11_11") (pintype "bidirectional"))
    )
    (net (code "23") (name "CAM1_RGB_D1_P") (class "Default")
      (node (ref "IC21") (pin "2") (pinfunction "I/O2_2") (pintype "passive"))
      (node (ref "X1") (pin "15") (pinfunction "15_15") (pintype "passive"))
      (node (ref "X3") (pin "10") (pinfunction "10_10") (pintype "bidirectional"))
    )
    (net (code "24") (name "CAM1_RGB_I2C_SCL_1V8") (class "Default")
      (node (ref "IC12") (pin "4") (pinfunction "I/O3_4") (pintype "passive"))
      (node (ref "X1") (pin "12") (pinfunction "12_12") (pintype "passive"))
      (node (ref "X3") (pin "2") (pinfunction "2_2") (pintype "bidirectional"))
    )
    (net (code "25") (name "CAM1_RGB_I2C_SDA_1V8") (class "Default")
      (node (ref "IC12") (pin "6") (pinfunction "I/O4_6") (pintype "passive"))
      (node (ref "X1") (pin "10") (pinfunction "10_10") (pintype "passive"))
      (node (ref "X3") (pin "1") (pinfunction "1_1") (pintype "bidirectional"))
    )
    (net (code "26") (name "CAM1_RGB_MCLK_1V8") (class "Default")
      (node (ref "IC12") (pin "1") (pinfunction "I/O1_1") (pintype "passive"))
      (node (ref "X1") (pin "04") (pinfunction "4_04") (pintype "passive"))
      (node (ref "X3") (pin "24") (pinfunction "24_24") (pintype "bidirectional"))
    )
    (net (code "27") (name "CAM3_TOF_CLK_N") (class "Default")
      (node (ref "IC22") (pin "5") (pinfunction "I/O4_5") (pintype "passive"))
      (node (ref "X2") (pin "36") (pinfunction "36_36") (pintype "passive"))
      (node (ref "X5") (pin "23") (pinfunction "23_23") (pintype "passive"))
    )
    (net (code "28") (name "CAM3_TOF_CLK_P") (class "Default")
      (node (ref "IC22") (pin "4") (pinfunction "I/O3_4") (pintype "passive"))
      (node (ref "X2") (pin "38") (pinfunction "38_38") (pintype "passive"))
      (node (ref "X5") (pin "21") (pinfunction "21_21") (pintype "passive"))
    )
    (net (code "29") (name "CAM3_TOF_D0_N") (class "Default")
      (node (ref "IC22") (pin "2") (pinfunction "I/O2_2") (pintype "passive"))
      (node (ref "X2") (pin "27") (pinfunction "27_27") (pintype "passive"))
      (node (ref "X5") (pin "17") (pinfunction "17_17") (pintype "passive"))
    )
    (net (code "30") (name "CAM3_TOF_D0_P") (class "Default")
      (node (ref "IC22") (pin "1") (pinfunction "I/O1_1") (pintype "passive"))
      (node (ref "X2") (pin "29") (pinfunction "29_29") (pintype "passive"))
      (node (ref "X5") (pin "15") (pinfunction "15_15") (pintype "passive"))
    )
    (net (code "31") (name "CAM3_TOF_D1_N") (class "Default")
      (node (ref "IC22") (pin "8") (pinfunction "I/O6_8") (pintype "passive"))
      (node (ref "X2") (pin "30") (pinfunction "30_30") (pintype "passive"))
      (node (ref "X5") (pin "29") (pinfunction "29_29") (pintype "passive"))
    )
    (net (code "32") (name "CAM3_TOF_D1_P") (class "Default")
      (node (ref "IC22") (pin "7") (pinfunction "I/O5_7") (pintype "passive"))
      (node (ref "X2") (pin "32") (pinfunction "32_32") (pintype "passive"))
      (node (ref "X5") (pin "27") (pinfunction "27_27") (pintype "passive"))
    )
    (net (code "33") (name "CAM3_TOF_I2C_SCL_1V8") (class "Default")
      (node (ref "IC18") (pin "1") (pinfunction "I/O1_1") (pintype "passive"))
      (node (ref "X2") (pin "22") (pinfunction "22_22") (pintype "passive"))
      (node (ref "X5") (pin "24") (pinfunction "24_24") (pintype "passive"))
    )
    (net (code "34") (name "CAM3_TOF_I2C_SDA_1V8") (class "Default")
      (node (ref "IC18") (pin "3") (pinfunction "I/O2_3") (pintype "passive"))
      (node (ref "X2") (pin "20") (pinfunction "20_20") (pintype "passive"))
      (node (ref "X5") (pin "26") (pinfunction "26_26") (pintype "passive"))
    )
    (net (code "35") (name "CAM3_TOF_MCLK_1V8") (class "Default")
      (node (ref "IC18") (pin "4") (pinfunction "I/O3_4") (pintype "passive"))
      (node (ref "R47") (pin "1") (pinfunction "1_1") (pintype "passive"))
      (node (ref "X2") (pin "33") (pinfunction "33_33") (pintype "passive"))
    )
    (net (code "36") (name "FU_I2C_TEMP_SCL_3V3") (class "Default")
      (node (ref "IC14") (pin "4") (pinfunction "I/O3_4") (pintype "passive"))
      (node (ref "R32") (pin "2") (pinfunction "2_2") (pintype "passive"))
      (node (ref "R39") (pin "2") (pinfunction "2_2") (pintype "passive"))
      (node (ref "R82") (pin "2") (pinfunction "2_2") (pintype "passive"))
      (node (ref "TP22") (pin "TP") (pinfunction "TP_TP") (pintype "input"))
      (node (ref "X1") (pin "29") (pinfunction "29_29") (pintype "passive"))
    )
    (net (code "37") (name "FU_I2C_TEMP_SDA_3V3") (class "Default")
      (node (ref "IC14") (pin "3") (pinfunction "I/O2_3") (pintype "passive"))
      (node (ref "R30") (pin "2") (pinfunction "2_2") (pintype "passive"))
      (node (ref "R33") (pin "2") (pinfunction "2_2") (pintype "passive"))
      (node (ref "R81") (pin "2") (pinfunction "2_2") (pintype "passive"))
      (node (ref "TP23") (pin "TP") (pinfunction "TP_TP") (pintype "input"))
      (node (ref "X1") (pin "31") (pinfunction "31_31") (pintype "passive"))
    )
    (net (code "38") (name "FU_IR_PHOTO_FET_3V3") (class "Default")
      (node (ref "C29") (pin "1") (pinfunction "1_1") (pintype "passive"))
      (node (ref "R51") (pin "1") (pinfunction "1_1") (pintype "passive"))
      (node (ref "R53") (pin "1") (pinfunction "1_1") (pintype "passive"))
      (node (ref "X1") (pin "36") (pinfunction "36_36") (pintype "passive"))
    )
    (net (code "39") (name "FU_PVCC_EN_3V3") (class "Default")
      (node (ref "IC14") (pin "6") (pinfunction "I/O4_6") (pintype "passive"))
      (node (ref "R55") (pin "2") (pinfunction "2_2") (pintype "passive"))
      (node (ref "R60") (pin "1") (pinfunction "1_1") (pintype "passive"))
      (node (ref "R62") (pin "1") (pinfunction "1_1") (pintype "passive"))
      (node (ref "T8") (pin "1") (pinfunction "G_1") (pintype "passive"))
      (node (ref "TP10") (pin "TP") (pinfunction "TP_TP") (pintype "input"))
      (node (ref "X1") (pin "27") (pinfunction "27_27") (pintype "passive"))
    )
    (net (code "40") (name "FU_TAMPER_SWITCH") (class "Default")
      (node (ref "SW1") (pin "3") (pinfunction "NO_3") (pintype "passive"))
      (node (ref "SW1") (pin "4") (pinfunction "NO_4") (pintype "passive"))
      (node (ref "X1") (pin "34") (pinfunction "34_34") (pintype "passive"))
    )
    (net (code "41") (name "GND") (class "Default")
      (node (ref "C1") (pin "2") (pinfunction "2_2") (pintype "passive"))
      (node (ref "C100") (pin "2") (pinfunction "2_2") (pintype "passive"))
      (node (ref "C101") (pin "2") (pinfunction "2_2") (pintype "passive"))
      (node (ref "C102") (pin "2") (pinfunction "2_2") (pintype "passive"))
      (node (ref "C103") (pin "2") (pinfunction "2_2") (pintype "passive"))
      (node (ref "C104") (pin "2") (pinfunction "2_2") (pintype "passive"))
      (node (ref "C105") (pin "2") (pinfunction "2_2") (pintype "passive"))
      (node (ref "C106") (pin "2") (pinfunction "2_2") (pintype "passive"))
      (node (ref "C107") (pin "2") (pinfunction "2_2") (pintype "passive"))
      (node (ref "C108") (pin "2") (pinfunction "2_2") (pintype "passive"))
      (node (ref "C109") (pin "2") (pinfunction "2_2") (pintype "passive"))
      (node (ref "C110") (pin "2") (pinfunction "2_2") (pintype "passive"))
      (node (ref "C111") (pin "2") (pinfunction "2_2") (pintype "passive"))
      (node (ref "C112") (pin "2") (pinfunction "2_2") (pintype "passive"))
      (node (ref "C113") (pin "2") (pinfunction "2_2") (pintype "passive"))
      (node (ref "C114") (pin "2") (pinfunction "2_2") (pintype "passive"))
      (node (ref "C115") (pin "2") (pinfunction "2_2") (pintype "passive"))
      (node (ref "C116") (pin "2") (pinfunction "2_2") (pintype "passive"))
      (node (ref "C117") (pin "2") (pinfunction "2_2") (pintype "passive"))
      (node (ref "C118") (pin "2") (pinfunction "2_2") (pintype "passive"))
      (node (ref "C119") (pin "2") (pinfunction "2_2") (pintype "passive"))
      (node (ref "C12") (pin "2") (pinfunction "2_2") (pintype "passive"))
      (node (ref "C120") (pin "2") (pinfunction "2_2") (pintype "passive"))
      (node (ref "C121") (pin "2") (pinfunction "2_2") (pintype "passive"))
      (node (ref "C122") (pin "2") (pinfunction "2_2") (pintype "passive"))
      (node (ref "C123") (pin "2") (pinfunction "2_2") (pintype "passive"))
      (node (ref "C124") (pin "2") (pinfunction "2_2") (pintype "passive"))
      (node (ref "C125") (pin "2") (pinfunction "2_2") (pintype "passive"))
      (node (ref "C126") (pin "2") (pinfunction "2_2") (pintype "passive"))
      (node (ref "C127") (pin "2") (pinfunction "2_2") (pintype "passive"))
      (node (ref "C128") (pin "2") (pinfunction "2_2") (pintype "passive"))
      (node (ref "C129") (pin "2") (pinfunction "2_2") (pintype "passive"))
      (node (ref "C13") (pin "2") (pinfunction "2_2") (pintype "passive"))
      (node (ref "C130") (pin "2") (pinfunction "2_2") (pintype "passive"))
      (node (ref "C131") (pin "2") (pinfunction "2_2") (pintype "passive"))
      (node (ref "C132") (pin "2") (pinfunction "2_2") (pintype "passive"))
      (node (ref "C133") (pin "2") (pinfunction "2_2") (pintype "passive"))
      (node (ref "C134") (pin "2") (pinfunction "2_2") (pintype "passive"))
      (node (ref "C135") (pin "2") (pinfunction "2_2") (pintype "passive"))
      (node (ref "C136") (pin "2") (pinfunction "2_2") (pintype "passive"))
      (node (ref "C137") (pin "2") (pinfunction "2_2") (pintype "passive"))
      (node (ref "C138") (pin "2") (pinfunction "2_2") (pintype "passive"))
      (node (ref "C139") (pin "2") (pinfunction "2_2") (pintype "passive"))
      (node (ref "C14") (pin "2") (pinfunction "2_2") (pintype "passive"))
      (node (ref "C140") (pin "2") (pinfunction "2_2") (pintype "passive"))
      (node (ref "C141") (pin "2") (pinfunction "2_2") (pintype "passive"))
      (node (ref "C142") (pin "2") (pinfunction "2_2") (pintype "passive"))
      (node (ref "C143") (pin "2") (pinfunction "2_2") (pintype "passive"))
      (node (ref "C144") (pin "2") (pinfunction "2_2") (pintype "passive"))
      (node (ref "C145") (pin "2") (pinfunction "2_2") (pintype "passive"))
      (node (ref "C146") (pin "2") (pinfunction "2_2") (pintype "passive"))
      (node (ref "C147") (pin "2") (pinfunction "2_2") (pintype "passive"))
      (node (ref "C148") (pin "2") (pinfunction "2_2") (pintype "passive"))
      (node (ref "C149") (pin "2") (pinfunction "2_2") (pintype "passive"))
      (node (ref "C150") (pin "2") (pinfunction "2_2") (pintype "passive"))
      (node (ref "C151") (pin "2") (pinfunction "2_2") (pintype "passive"))
      (node (ref "C152") (pin "2") (pinfunction "2_2") (pintype "passive"))
      (node (ref "C153") (pin "2") (pinfunction "2_2") (pintype "passive"))
      (node (ref "C154") (pin "2") (pinfunction "2_2") (pintype "passive"))
      (node (ref "C155") (pin "2") (pinfunction "2_2") (pintype "passive"))
      (node (ref "C156") (pin "2") (pinfunction "2_2") (pintype "passive"))
      (node (ref "C157") (pin "2") (pinfunction "2_2") (pintype "passive"))
      (node (ref "C158") (pin "2") (pinfunction "2_2") (pintype "passive"))
      (node (ref "C159") (pin "2") (pinfunction "2_2") (pintype "passive"))
      (node (ref "C16") (pin "2") (pinfunction "2_2") (pintype "passive"))
      (node (ref "C162") (pin "2") (pinfunction "2_2") (pintype "passive"))
      (node (ref "C164") (pin "2") (pinfunction "2_2") (pintype "passive"))
      (node (ref "C165") (pin "2") (pinfunction "2_2") (pintype "passive"))
      (node (ref "C166") (pin "2") (pinfunction "2_2") (pintype "passive"))
      (node (ref "C167") (pin "2") (pinfunction "2_2") (pintype "passive"))
      (node (ref "C168") (pin "2") (pinfunction "2_2") (pintype "passive"))
      (node (ref "C169") (pin "2") (pinfunction "2_2") (pintype "passive"))
      (node (ref "C17") (pin "2") (pinfunction "2_2") (pintype "passive"))
      (node (ref "C170") (pin "2") (pinfunction "2_2") (pintype "passive"))
      (node (ref "C171") (pin "2") (pinfunction "2_2") (pintype "passive"))
      (node (ref "C172") (pin "2") (pinfunction "2_2") (pintype "passive"))
      (node (ref "C173") (pin "2") (pinfunction "2_2") (pintype "passive"))
      (node (ref "C174") (pin "2") (pinfunction "2_2") (pintype "passive"))
      (node (ref "C175") (pin "2") (pinfunction "2_2") (pintype "passive"))
      (node (ref "C176") (pin "2") (pinfunction "2_2") (pintype "passive"))
      (node (ref "C177") (pin "2") (pinfunction "2_2") (pintype "passive"))
      (node (ref "C178") (pin "2") (pinfunction "2_2") (pintype "passive"))
      (node (ref "C179") (pin "2") (pinfunction "2_2") (pintype "passive"))
      (node (ref "C18") (pin "2") (pinfunction "2_2") (pintype "passive"))
      (node (ref "C180") (pin "2") (pinfunction "2_2") (pintype "passive"))
      (node (ref "C181") (pin "2") (pinfunction "2_2") (pintype "passive"))
      (node (ref "C182") (pin "2") (pinfunction "2_2") (pintype "passive"))
      (node (ref "C183") (pin "2") (pinfunction "2_2") (pintype "passive"))
      (node (ref "C184") (pin "2") (pinfunction "2_2") (pintype "passive"))
      (node (ref "C185") (pin "2") (pinfunction "2_2") (pintype "passive"))
      (node (ref "C186") (pin "2") (pinfunction "2_2") (pintype "passive"))
      (node (ref "C187") (pin "2") (pinfunction "2_2") (pintype "passive"))
      (node (ref "C188") (pin "2") (pinfunction "2_2") (pintype "passive"))
      (node (ref "C189") (pin "2") (pinfunction "2_2") (pintype "passive"))
      (node (ref "C19") (pin "2") (pinfunction "2_2") (pintype "passive"))
      (node (ref "C190") (pin "2") (pinfunction "2_2") (pintype "passive"))
      (node (ref "C191") (pin "2") (pinfunction "2_2") (pintype "passive"))
      (node (ref "C192") (pin "2") (pinfunction "2_2") (pintype "passive"))
      (node (ref "C193") (pin "2") (pinfunction "2_2") (pintype "passive"))
      (node (ref "C194") (pin "2") (pinfunction "2_2") (pintype "passive"))
      (node (ref "C195") (pin "2") (pinfunction "2_2") (pintype "passive"))
      (node (ref "C196") (pin "2") (pinfunction "2_2") (pintype "passive"))
      (node (ref "C197") (pin "2") (pinfunction "2_2") (pintype "passive"))
      (node (ref "C198") (pin "2") (pinfunction "2_2") (pintype "passive"))
      (node (ref "C199") (pin "2") (pinfunction "2_2") (pintype "passive"))
      (node (ref "C2") (pin "2") (pinfunction "2_2") (pintype "passive"))
      (node (ref "C20") (pin "2") (pinfunction "2_2") (pintype "passive"))
      (node (ref "C200") (pin "2") (pinfunction "2_2") (pintype "passive"))
      (node (ref "C201") (pin "2") (pinfunction "2_2") (pintype "passive"))
      (node (ref "C202") (pin "2") (pinfunction "2_2") (pintype "passive"))
      (node (ref "C203") (pin "2") (pinfunction "2_2") (pintype "passive"))
      (node (ref "C204") (pin "2") (pinfunction "2_2") (pintype "passive"))
      (node (ref "C205") (pin "2") (pinfunction "2_2") (pintype "passive"))
      (node (ref "C206") (pin "2") (pinfunction "2_2") (pintype "passive"))
      (node (ref "C207") (pin "2") (pinfunction "2_2") (pintype "passive"))
      (node (ref "C208") (pin "2") (pinfunction "2_2") (pintype "passive"))
      (node (ref "C209") (pin "2") (pinfunction "2_2") (pintype "passive"))
      (node (ref "C21") (pin "2") (pinfunction "2_2") (pintype "passive"))
      (node (ref "C210") (pin "2") (pinfunction "2_2") (pintype "passive"))
      (node (ref "C211") (pin "2") (pinfunction "2_2") (pintype "passive"))
      (node (ref "C212") (pin "2") (pinfunction "2_2") (pintype "passive"))
      (node (ref "C213") (pin "2") (pinfunction "2_2") (pintype "passive"))
      (node (ref "C214") (pin "2") (pinfunction "2_2") (pintype "passive"))
      (node (ref "C215") (pin "2") (pinfunction "2_2") (pintype "passive"))
      (node (ref "C216") (pin "2") (pinfunction "2_2") (pintype "passive"))
      (node (ref "C217") (pin "2") (pinfunction "2_2") (pintype "passive"))
      (node (ref "C218") (pin "2") (pinfunction "2_2") (pintype "passive"))
      (node (ref "C219") (pin "2") (pinfunction "2_2") (pintype "passive"))
      (node (ref "C22") (pin "2") (pinfunction "2_2") (pintype "passive"))
      (node (ref "C220") (pin "2") (pinfunction "2_2") (pintype "passive"))
      (node (ref "C221") (pin "2") (pinfunction "2_2") (pintype "passive"))
      (node (ref "C222") (pin "2") (pinfunction "2_2") (pintype "passive"))
      (node (ref "C223") (pin "2") (pinfunction "2_2") (pintype "passive"))
      (node (ref "C224") (pin "2") (pinfunction "2_2") (pintype "passive"))
      (node (ref "C225") (pin "2") (pinfunction "2_2") (pintype "passive"))
      (node (ref "C226") (pin "2") (pinfunction "2_2") (pintype "passive"))
      (node (ref "C227") (pin "2") (pinfunction "2_2") (pintype "passive"))
      (node (ref "C228") (pin "2") (pinfunction "2_2") (pintype "passive"))
      (node (ref "C229") (pin "2") (pinfunction "2_2") (pintype "passive"))
      (node (ref "C23") (pin "2") (pinfunction "2_2") (pintype "passive"))
      (node (ref "C230") (pin "2") (pinfunction "2_2") (pintype "passive"))
      (node (ref "C231") (pin "2") (pinfunction "2_2") (pintype "passive"))
      (node (ref "C232") (pin "2") (pinfunction "2_2") (pintype "passive"))
      (node (ref "C233") (pin "2") (pinfunction "2_2") (pintype "passive"))
      (node (ref "C234") (pin "2") (pinfunction "2_2") (pintype "passive"))
      (node (ref "C235") (pin "2") (pinfunction "2_2") (pintype "passive"))
      (node (ref "C236") (pin "2") (pinfunction "2_2") (pintype "passive"))
      (node (ref "C237") (pin "2") (pinfunction "2_2") (pintype "passive"))
      (node (ref "C238") (pin "2") (pinfunction "2_2") (pintype "passive"))
      (node (ref "C239") (pin "2") (pinfunction "2_2") (pintype "passive"))
      (node (ref "C24") (pin "2") (pinfunction "2_2") (pintype "passive"))
      (node (ref "C240") (pin "2") (pinfunction "2_2") (pintype "passive"))
      (node (ref "C241") (pin "2") (pinfunction "2_2") (pintype "passive"))
      (node (ref "C242") (pin "2") (pinfunction "2_2") (pintype "passive"))
      (node (ref "C243") (pin "2") (pinfunction "2_2") (pintype "passive"))
      (node (ref "C244") (pin "2") (pinfunction "2_2") (pintype "passive"))
      (node (ref "C245") (pin "2") (pinfunction "2_2") (pintype "passive"))
      (node (ref "C246") (pin "2") (pinfunction "2_2") (pintype "passive"))
      (node (ref "C247") (pin "2") (pinfunction "2_2") (pintype "passive"))
      (node (ref "C248") (pin "2") (pinfunction "2_2") (pintype "passive"))
      (node (ref "C249") (pin "2") (pinfunction "2_2") (pintype "passive"))
      (node (ref "C25") (pin "2") (pinfunction "2_2") (pintype "passive"))
      (node (ref "C250") (pin "2") (pinfunction "2_2") (pintype "passive"))
      (node (ref "C251") (pin "2") (pinfunction "2_2") (pintype "passive"))
      (node (ref "C252") (pin "2") (pinfunction "2_2") (pintype "passive"))
      (node (ref "C253") (pin "2") (pinfunction "2_2") (pintype "passive"))
      (node (ref "C254") (pin "2") (pinfunction "2_2") (pintype "passive"))
      (node (ref "C255") (pin "2") (pinfunction "2_2") (pintype "passive"))
      (node (ref "C256") (pin "2") (pinfunction "2_2") (pintype "passive"))
      (node (ref "C257") (pin "2") (pinfunction "2_2") (pintype "passive"))
      (node (ref "C258") (pin "2") (pinfunction "2_2") (pintype "passive"))
      (node (ref "C259") (pin "2") (pinfunction "2_2") (pintype "passive"))
      (node (ref "C26") (pin "2") (pinfunction "2_2") (pintype "passive"))
      (node (ref "C260") (pin "2") (pinfunction "2_2") (pintype "passive"))
      (node (ref "C261") (pin "2") (pinfunction "2_2") (pintype "passive"))
      (node (ref "C262") (pin "2") (pinfunction "2_2") (pintype "passive"))
      (node (ref "C263") (pin "2") (pinfunction "2_2") (pintype "passive"))
      (node (ref "C264") (pin "2") (pinfunction "2_2") (pintype "passive"))
      (node (ref "C265") (pin "2") (pinfunction "2_2") (pintype "passive"))
      (node (ref "C266") (pin "2") (pinfunction "2_2") (pintype "passive"))
      (node (ref "C27") (pin "2") (pinfunction "2_2") (pintype "passive"))
      (node (ref "C270") (pin "2") (pinfunction "2_2") (pintype "passive"))
      (node (ref "C272") (pin "2") (pinfunction "2_2") (pintype "passive"))
      (node (ref "C28") (pin "2") (pinfunction "2_2") (pintype "passive"))
      (node (ref "C280") (pin "2") (pinfunction "2_2") (pintype "passive"))
      (node (ref "C281") (pin "2") (pinfunction "2_2") (pintype "passive"))
      (node (ref "C282") (pin "2") (pinfunction "2_2") (pintype "passive"))
      (node (ref "C283") (pin "2") (pinfunction "2_2") (pintype "passive"))
      (node (ref "C284") (pin "2") (pinfunction "2_2") (pintype "passive"))
      (node (ref "C285") (pin "2") (pinfunction "2_2") (pintype "passive"))
      (node (ref "C286") (pin "2") (pinfunction "2_2") (pintype "passive"))
      (node (ref "C287") (pin "2") (pinfunction "2_2") (pintype "passive"))
      (node (ref "C288") (pin "2") (pinfunction "2_2") (pintype "passive"))
      (node (ref "C289") (pin "2") (pinfunction "2_2") (pintype "passive"))
      (node (ref "C29") (pin "2") (pinfunction "2_2") (pintype "passive"))
      (node (ref "C290") (pin "2") (pinfunction "2_2") (pintype "passive"))
      (node (ref "C291") (pin "2") (pinfunction "2_2") (pintype "passive"))
      (node (ref "C292") (pin "2") (pinfunction "2_2") (pintype "passive"))
      (node (ref "C293") (pin "2") (pinfunction "2_2") (pintype "passive"))
      (node (ref "C294") (pin "2") (pinfunction "2_2") (pintype "passive"))
      (node (ref "C295") (pin "2") (pinfunction "2_2") (pintype "passive"))
      (node (ref "C296") (pin "2") (pinfunction "2_2") (pintype "passive"))
      (node (ref "C297") (pin "2") (pinfunction "2_2") (pintype "passive"))
      (node (ref "C298") (pin "2") (pinfunction "2_2") (pintype "passive"))
      (node (ref "C299") (pin "2") (pinfunction "2_2") (pintype "passive"))
      (node (ref "C3") (pin "2") (pinfunction "2_2") (pintype "passive"))
      (node (ref "C30") (pin "2") (pinfunction "2_2") (pintype "passive"))
      (node (ref "C300") (pin "2") (pinfunction "2_2") (pintype "passive"))
      (node (ref "C301") (pin "2") (pinfunction "2_2") (pintype "passive"))
      (node (ref "C302") (pin "2") (pinfunction "2_2") (pintype "passive"))
      (node (ref "C303") (pin "2") (pinfunction "2_2") (pintype "passive"))
      (node (ref "C304") (pin "2") (pinfunction "2_2") (pintype "passive"))
      (node (ref "C305") (pin "2") (pinfunction "2_2") (pintype "passive"))
      (node (ref "C306") (pin "2") (pinfunction "2_2") (pintype "passive"))
      (node (ref "C307") (pin "2") (pinfunction "2_2") (pintype "passive"))
      (node (ref "C308") (pin "2") (pinfunction "2_2") (pintype "passive"))
      (node (ref "C309") (pin "2") (pinfunction "2_2") (pintype "passive"))
      (node (ref "C310") (pin "2") (pinfunction "2_2") (pintype "passive"))
      (node (ref "C311") (pin "2") (pinfunction "2_2") (pintype "passive"))
      (node (ref "C312") (pin "2") (pinfunction "2_2") (pintype "passive"))
      (node (ref "C313") (pin "2") (pinfunction "2_2") (pintype "passive"))
      (node (ref "C314") (pin "2") (pinfunction "2_2") (pintype "passive"))
      (node (ref "C315") (pin "2") (pinfunction "2_2") (pintype "passive"))
      (node (ref "C316") (pin "2") (pinfunction "2_2") (pintype "passive"))
      (node (ref "C317") (pin "2") (pinfunction "2_2") (pintype "passive"))
      (node (ref "C318") (pin "2") (pinfunction "2_2") (pintype "passive"))
      (node (ref "C319") (pin "2") (pinfunction "2_2") (pintype "passive"))
      (node (ref "C32") (pin "2") (pinfunction "2_2") (pintype "passive"))
      (node (ref "C320") (pin "2") (pinfunction "2_2") (pintype "passive"))
      (node (ref "C321") (pin "2") (pinfunction "2_2") (pintype "passive"))
      (node (ref "C322") (pin "2") (pinfunction "2_2") (pintype "passive"))
      (node (ref "C323") (pin "2") (pinfunction "2_2") (pintype "passive"))
      (node (ref "C324") (pin "2") (pinfunction "2_2") (pintype "passive"))
      (node (ref "C325") (pin "2") (pinfunction "2_2") (pintype "passive"))
      (node (ref "C326") (pin "2") (pinfunction "2_2") (pintype "passive"))
      (node (ref "C327") (pin "2") (pinfunction "2_2") (pintype "passive"))
      (node (ref "C328") (pin "2") (pinfunction "2_2") (pintype "passive"))
      (node (ref "C329") (pin "2") (pinfunction "2_2") (pintype "passive"))
      (node (ref "C33") (pin "2") (pinfunction "2_2") (pintype "passive"))
      (node (ref "C330") (pin "2") (pinfunction "2_2") (pintype "passive"))
      (node (ref "C331") (pin "2") (pinfunction "2_2") (pintype "passive"))
      (node (ref "C332") (pin "2") (pinfunction "2_2") (pintype "passive"))
      (node (ref "C34") (pin "2") (pinfunction "2_2") (pintype "passive"))
      (node (ref "C35") (pin "2") (pinfunction "2_2") (pintype "passive"))
      (node (ref "C36") (pin "2") (pinfunction "2_2") (pintype "passive"))
      (node (ref "C37") (pin "2") (pinfunction "2_2") (pintype "passive"))
      (node (ref "C38") (pin "2") (pinfunction "2_2") (pintype "passive"))
      (node (ref "C39") (pin "2") (pinfunction "2_2") (pintype "passive"))
      (node (ref "C4") (pin "2") (pinfunction "2_2") (pintype "passive"))
      (node (ref "C40") (pin "2") (pinfunction "2_2") (pintype "passive"))
      (node (ref "C41") (pin "2") (pinfunction "2_2") (pintype "passive"))
      (node (ref "C42") (pin "2") (pinfunction "2_2") (pintype "passive"))
      (node (ref "C43") (pin "2") (pinfunction "2_2") (pintype "passive"))
      (node (ref "C44") (pin "2") (pinfunction "2_2") (pintype "passive"))
      (node (ref "C45") (pin "2") (pinfunction "2_2") (pintype "passive"))
      (node (ref "C46") (pin "2") (pinfunction "2_2") (pintype "passive"))
      (node (ref "C47") (pin "2") (pinfunction "2_2") (pintype "passive"))
      (node (ref "C48") (pin "2") (pinfunction "2_2") (pintype "passive"))
      (node (ref "C49") (pin "2") (pinfunction "2_2") (pintype "passive"))
      (node (ref "C5") (pin "2") (pinfunction "2_2") (pintype "passive"))
      (node (ref "C50") (pin "2") (pinfunction "2_2") (pintype "passive"))
      (node (ref "C51") (pin "2") (pinfunction "2_2") (pintype "passive"))
      (node (ref "C52") (pin "2") (pinfunction "2_2") (pintype "passive"))
      (node (ref "C53") (pin "2") (pinfunction "2_2") (pintype "passive"))
      (node (ref "C54") (pin "2") (pinfunction "2_2") (pintype "passive"))
      (node (ref "C55") (pin "2") (pinfunction "2_2") (pintype "passive"))
      (node (ref "C56") (pin "2") (pinfunction "2_2") (pintype "passive"))
      (node (ref "C57") (pin "2") (pinfunction "2_2") (pintype "passive"))
      (node (ref "C58") (pin "2") (pinfunction "2_2") (pintype "passive"))
      (node (ref "C59") (pin "2") (pinfunction "2_2") (pintype "passive"))
      (node (ref "C6") (pin "2") (pinfunction "2_2") (pintype "passive"))
      (node (ref "C7") (pin "2") (pinfunction "2_2") (pintype "passive"))
      (node (ref "C78") (pin "2") (pinfunction "2_2") (pintype "passive"))
      (node (ref "C8") (pin "2") (pinfunction "2_2") (pintype "passive"))
      (node (ref "C9") (pin "2") (pinfunction "2_2") (pintype "passive"))
      (node (ref "D100") (pin "5") (pinfunction "P$1_5") (pintype "passive"))
      (node (ref "D101") (pin "5") (pinfunction "P$1_5") (pintype "passive"))
      (node (ref "D102") (pin "5") (pinfunction "P$1_5") (pintype "passive"))
      (node (ref "D103") (pin "5") (pinfunction "P$1_5") (pintype "passive"))
      (node (ref "D104") (pin "5") (pinfunction "P$1_5") (pintype "passive"))
      (node (ref "D105") (pin "5") (pinfunction "P$1_5") (pintype "passive"))
      (node (ref "D106") (pin "5") (pinfunction "P$1_5") (pintype "passive"))
      (node (ref "D107") (pin "5") (pinfunction "P$1_5") (pintype "passive"))
      (node (ref "D108") (pin "5") (pinfunction "P$1_5") (pintype "passive"))
      (node (ref "D109") (pin "5") (pinfunction "P$1_5") (pintype "passive"))
      (node (ref "D110") (pin "5") (pinfunction "P$1_5") (pintype "passive"))
      (node (ref "D111") (pin "5") (pinfunction "P$1_5") (pintype "passive"))
      (node (ref "D112") (pin "5") (pinfunction "P$1_5") (pintype "passive"))
      (node (ref "D200") (pin "NC") (pinfunction "P$1_NC") (pintype "passive"))
      (node (ref "D201") (pin "NC") (pinfunction "P$1_NC") (pintype "passive"))
      (node (ref "D202") (pin "NC") (pinfunction "P$1_NC") (pintype "passive"))
      (node (ref "D203") (pin "NC") (pinfunction "P$1_NC") (pintype "passive"))
      (node (ref "D204") (pin "NC") (pinfunction "P$1_NC") (pintype "passive"))
      (node (ref "D205") (pin "NC") (pinfunction "P$1_NC") (pintype "passive"))
      (node (ref "D206") (pin "NC") (pinfunction "P$1_NC") (pintype "passive"))
      (node (ref "D207") (pin "NC") (pinfunction "P$1_NC") (pintype "passive"))
      (node (ref "D208") (pin "NC") (pinfunction "P$1_NC") (pintype "passive"))
      (node (ref "D209") (pin "NC") (pinfunction "P$1_NC") (pintype "passive"))
      (node (ref "D210") (pin "NC") (pinfunction "P$1_NC") (pintype "passive"))
      (node (ref "D211") (pin "NC") (pinfunction "P$1_NC") (pintype "passive"))
      (node (ref "D212") (pin "NC") (pinfunction "P$1_NC") (pintype "passive"))
      (node (ref "D213") (pin "NC") (pinfunction "P$1_NC") (pintype "passive"))
      (node (ref "D214") (pin "NC") (pinfunction "P$1_NC") (pintype "passive"))
      (node (ref "D215") (pin "NC") (pinfunction "P$1_NC") (pintype "passive"))
      (node (ref "D250") (pin "NC") (pinfunction "P$1_NC") (pintype "passive"))
      (node (ref "D251") (pin "NC") (pinfunction "P$1_NC") (pintype "passive"))
      (node (ref "D252") (pin "NC") (pinfunction "P$1_NC") (pintype "passive"))
      (node (ref "D253") (pin "NC") (pinfunction "P$1_NC") (pintype "passive"))
      (node (ref "D254") (pin "NC") (pinfunction "P$1_NC") (pintype "passive"))
      (node (ref "D255") (pin "NC") (pinfunction "P$1_NC") (pintype "passive"))
      (node (ref "D256") (pin "NC") (pinfunction "P$1_NC") (pintype "passive"))
      (node (ref "D257") (pin "NC") (pinfunction "P$1_NC") (pintype "passive"))
      (node (ref "D258") (pin "NC") (pinfunction "P$1_NC") (pintype "passive"))
      (node (ref "D259") (pin "NC") (pinfunction "P$1_NC") (pintype "passive"))
      (node (ref "D260") (pin "NC") (pinfunction "P$1_NC") (pintype "passive"))
      (node (ref "D261") (pin "NC") (pinfunction "P$1_NC") (pintype "passive"))
      (node (ref "D262") (pin "NC") (pinfunction "P$1_NC") (pintype "passive"))
      (node (ref "D263") (pin "NC") (pinfunction "P$1_NC") (pintype "passive"))
      (node (ref "D264") (pin "NC") (pinfunction "P$1_NC") (pintype "passive"))
      (node (ref "D265") (pin "NC") (pinfunction "P$1_NC") (pintype "passive"))
      (node (ref "D300") (pin "NC") (pinfunction "P$1_NC") (pintype "passive"))
      (node (ref "D301") (pin "NC") (pinfunction "P$1_NC") (pintype "passive"))
      (node (ref "D302") (pin "NC") (pinfunction "P$1_NC") (pintype "passive"))
      (node (ref "D303") (pin "NC") (pinfunction "P$1_NC") (pintype "passive"))
      (node (ref "D304") (pin "NC") (pinfunction "P$1_NC") (pintype "passive"))
      (node (ref "D305") (pin "NC") (pinfunction "P$1_NC") (pintype "passive"))
      (node (ref "D306") (pin "NC") (pinfunction "P$1_NC") (pintype "passive"))
      (node (ref "D307") (pin "NC") (pinfunction "P$1_NC") (pintype "passive"))
      (node (ref "D308") (pin "NC") (pinfunction "P$1_NC") (pintype "passive"))
      (node (ref "D309") (pin "NC") (pinfunction "P$1_NC") (pintype "passive"))
      (node (ref "D310") (pin "NC") (pinfunction "P$1_NC") (pintype "passive"))
      (node (ref "D311") (pin "NC") (pinfunction "P$1_NC") (pintype "passive"))
      (node (ref "D312") (pin "NC") (pinfunction "P$1_NC") (pintype "passive"))
      (node (ref "D313") (pin "NC") (pinfunction "P$1_NC") (pintype "passive"))
      (node (ref "D314") (pin "NC") (pinfunction "P$1_NC") (pintype "passive"))
      (node (ref "D315") (pin "NC") (pinfunction "P$1_NC") (pintype "passive"))
      (node (ref "D350") (pin "NC") (pinfunction "P$1_NC") (pintype "passive"))
      (node (ref "D351") (pin "NC") (pinfunction "P$1_NC") (pintype "passive"))
      (node (ref "D352") (pin "NC") (pinfunction "P$1_NC") (pintype "passive"))
      (node (ref "D353") (pin "NC") (pinfunction "P$1_NC") (pintype "passive"))
      (node (ref "D354") (pin "NC") (pinfunction "P$1_NC") (pintype "passive"))
      (node (ref "D355") (pin "NC") (pinfunction "P$1_NC") (pintype "passive"))
      (node (ref "D356") (pin "NC") (pinfunction "P$1_NC") (pintype "passive"))
      (node (ref "D357") (pin "NC") (pinfunction "P$1_NC") (pintype "passive"))
      (node (ref "D358") (pin "NC") (pinfunction "P$1_NC") (pintype "passive"))
      (node (ref "D359") (pin "NC") (pinfunction "P$1_NC") (pintype "passive"))
      (node (ref "D360") (pin "NC") (pinfunction "P$1_NC") (pintype "passive"))
      (node (ref "D361") (pin "NC") (pinfunction "P$1_NC") (pintype "passive"))
      (node (ref "D362") (pin "NC") (pinfunction "P$1_NC") (pintype "passive"))
      (node (ref "D363") (pin "NC") (pinfunction "P$1_NC") (pintype "passive"))
      (node (ref "D364") (pin "NC") (pinfunction "P$1_NC") (pintype "passive"))
      (node (ref "D365") (pin "NC") (pinfunction "P$1_NC") (pintype "passive"))
      (node (ref "IC1") (pin "2") (pinfunction "GND_2") (pintype "input"))
      (node (ref "IC10") (pin "2") (pinfunction "GND_2") (pintype "input"))
      (node (ref "IC100") (pin "4") (pinfunction "VSS_4") (pintype "input"))
      (node (ref "IC101") (pin "4") (pinfunction "VSS_4") (pintype "input"))
      (node (ref "IC102") (pin "4") (pinfunction "VSS_4") (pintype "input"))
      (node (ref "IC103") (pin "4") (pinfunction "VSS_4") (pintype "input"))
      (node (ref "IC104") (pin "4") (pinfunction "VSS_4") (pintype "input"))
      (node (ref "IC105") (pin "4") (pinfunction "VSS_4") (pintype "input"))
      (node (ref "IC106") (pin "4") (pinfunction "VSS_4") (pintype "input"))
      (node (ref "IC107") (pin "4") (pinfunction "VSS_4") (pintype "input"))
      (node (ref "IC108") (pin "4") (pinfunction "VSS_4") (pintype "input"))
      (node (ref "IC109") (pin "4") (pinfunction "VSS_4") (pintype "input"))
      (node (ref "IC11") (pin "4") (pinfunction "GND_4") (pintype "input"))
      (node (ref "IC110") (pin "4") (pinfunction "VSS_4") (pintype "input"))
      (node (ref "IC111") (pin "4") (pinfunction "VSS_4") (pintype "input"))
      (node (ref "IC112") (pin "4") (pinfunction "VSS_4") (pintype "input"))
      (node (ref "IC113") (pin "4") (pinfunction "VSS_4") (pintype "input"))
      (node (ref "IC114") (pin "4") (pinfunction "VSS_4") (pintype "input"))
      (node (ref "IC115") (pin "4") (pinfunction "VSS_4") (pintype "input"))
      (node (ref "IC116") (pin "4") (pinfunction "VSS_4") (pintype "input"))
      (node (ref "IC117") (pin "4") (pinfunction "VSS_4") (pintype "input"))
      (node (ref "IC118") (pin "4") (pinfunction "VSS_4") (pintype "input"))
      (node (ref "IC119") (pin "4") (pinfunction "VSS_4") (pintype "input"))
      (node (ref "IC12") (pin "2") (pinfunction "GND_2") (pintype "input"))
      (node (ref "IC120") (pin "4") (pinfunction "VSS_4") (pintype "input"))
      (node (ref "IC121") (pin "4") (pinfunction "VSS_4") (pintype "input"))
      (node (ref "IC122") (pin "4") (pinfunction "VSS_4") (pintype "input"))
      (node (ref "IC123") (pin "4") (pinfunction "VSS_4") (pintype "input"))
      (node (ref "IC124") (pin "4") (pinfunction "VSS_4") (pintype "input"))
      (node (ref "IC125") (pin "4") (pinfunction "VSS_4") (pintype "input"))
      (node (ref "IC126") (pin "4") (pinfunction "VSS_4") (pintype "input"))
      (node (ref "IC127") (pin "4") (pinfunction "VSS_4") (pintype "input"))
      (node (ref "IC128") (pin "4") (pinfunction "VSS_4") (pintype "input"))
      (node (ref "IC129") (pin "4") (pinfunction "VSS_4") (pintype "input"))
      (node (ref "IC13") (pin "2") (pinfunction "GND_2") (pintype "input"))
      (node (ref "IC130") (pin "4") (pinfunction "VSS_4") (pintype "input"))
      (node (ref "IC131") (pin "4") (pinfunction "VSS_4") (pintype "input"))
      (node (ref "IC132") (pin "4") (pinfunction "VSS_4") (pintype "input"))
      (node (ref "IC133") (pin "4") (pinfunction "VSS_4") (pintype "input"))
      (node (ref "IC134") (pin "4") (pinfunction "VSS_4") (pintype "input"))
      (node (ref "IC135") (pin "4") (pinfunction "VSS_4") (pintype "input"))
      (node (ref "IC136") (pin "4") (pinfunction "VSS_4") (pintype "input"))
      (node (ref "IC137") (pin "4") (pinfunction "VSS_4") (pintype "input"))
      (node (ref "IC138") (pin "4") (pinfunction "VSS_4") (pintype "input"))
      (node (ref "IC139") (pin "4") (pinfunction "VSS_4") (pintype "input"))
      (node (ref "IC14") (pin "2") (pinfunction "GND_2") (pintype "input"))
      (node (ref "IC140") (pin "4") (pinfunction "VSS_4") (pintype "input"))
      (node (ref "IC141") (pin "4") (pinfunction "VSS_4") (pintype "input"))
      (node (ref "IC142") (pin "4") (pinfunction "VSS_4") (pintype "input"))
      (node (ref "IC143") (pin "4") (pinfunction "VSS_4") (pintype "input"))
      (node (ref "IC144") (pin "4") (pinfunction "VSS_4") (pintype "input"))
      (node (ref "IC145") (pin "4") (pinfunction "VSS_4") (pintype "input"))
      (node (ref "IC146") (pin "4") (pinfunction "VSS_4") (pintype "input"))
      (node (ref "IC147") (pin "4") (pinfunction "VSS_4") (pintype "input"))
      (node (ref "IC148") (pin "4") (pinfunction "VSS_4") (pintype "input"))
      (node (ref "IC149") (pin "4") (pinfunction "VSS_4") (pintype "input"))
      (node (ref "IC15") (pin "4") (pinfunction "GND_4") (pintype "input"))
      (node (ref "IC15") (pin "5") (pinfunction "A2_5") (pintype "input"))
      (node (ref "IC15") (pin "6") (pinfunction "A1_6") (pintype "input"))
      (node (ref "IC15") (pin "7") (pinfunction "A0_7") (pintype "input"))
      (node (ref "IC150") (pin "4") (pinfunction "VSS_4") (pintype "input"))
      (node (ref "IC151") (pin "4") (pinfunction "VSS_4") (pintype "input"))
      (node (ref "IC152") (pin "4") (pinfunction "VSS_4") (pintype "input"))
      (node (ref "IC153") (pin "4") (pinfunction "VSS_4") (pintype "input"))
      (node (ref "IC154") (pin "4") (pinfunction "VSS_4") (pintype "input"))
      (node (ref "IC155") (pin "4") (pinfunction "VSS_4") (pintype "input"))
      (node (ref "IC156") (pin "4") (pinfunction "VSS_4") (pintype "input"))
      (node (ref "IC157") (pin "4") (pinfunction "VSS_4") (pintype "input"))
      (node (ref "IC158") (pin "4") (pinfunction "VSS_4") (pintype "input"))
      (node (ref "IC159") (pin "4") (pinfunction "VSS_4") (pintype "input"))
      (node (ref "IC16") (pin "2") (pinfunction "GND_2") (pintype "input"))
      (node (ref "IC160") (pin "4") (pinfunction "VSS_4") (pintype "input"))
      (node (ref "IC161") (pin "4") (pinfunction "VSS_4") (pintype "input"))
      (node (ref "IC162") (pin "4") (pinfunction "VSS_4") (pintype "input"))
      (node (ref "IC163") (pin "4") (pinfunction "VSS_4") (pintype "input"))
      (node (ref "IC164") (pin "4") (pinfunction "VSS_4") (pintype "input"))
      (node (ref "IC165") (pin "4") (pinfunction "VSS_4") (pintype "input"))
      (node (ref "IC166") (pin "4") (pinfunction "VSS_4") (pintype "input"))
      (node (ref "IC167") (pin "4") (pinfunction "VSS_4") (pintype "input"))
      (node (ref "IC168") (pin "4") (pinfunction "VSS_4") (pintype "input"))
      (node (ref "IC169") (pin "4") (pinfunction "VSS_4") (pintype "input"))
      (node (ref "IC17") (pin "2") (pinfunction "GND_2") (pintype "input"))
      (node (ref "IC170") (pin "4") (pinfunction "VSS_4") (pintype "input"))
      (node (ref "IC171") (pin "4") (pinfunction "VSS_4") (pintype "input"))
      (node (ref "IC172") (pin "4") (pinfunction "VSS_4") (pintype "input"))
      (node (ref "IC173") (pin "4") (pinfunction "VSS_4") (pintype "input"))
      (node (ref "IC174") (pin "4") (pinfunction "VSS_4") (pintype "input"))
      (node (ref "IC175") (pin "4") (pinfunction "VSS_4") (pintype "input"))
      (node (ref "IC176") (pin "4") (pinfunction "VSS_4") (pintype "input"))
      (node (ref "IC177") (pin "4") (pinfunction "VSS_4") (pintype "input"))
      (node (ref "IC178") (pin "4") (pinfunction "VSS_4") (pintype "input"))
      (node (ref "IC179") (pin "4") (pinfunction "VSS_4") (pintype "input"))
      (node (ref "IC18") (pin "2") (pinfunction "GND_2") (pintype "input"))
      (node (ref "IC180") (pin "4") (pinfunction "VSS_4") (pintype "input"))
      (node (ref "IC181") (pin "4") (pinfunction "VSS_4") (pintype "input"))
      (node (ref "IC182") (pin "4") (pinfunction "VSS_4") (pintype "input"))
      (node (ref "IC183") (pin "4") (pinfunction "VSS_4") (pintype "input"))
      (node (ref "IC184") (pin "4") (pinfunction "VSS_4") (pintype "input"))
      (node (ref "IC185") (pin "4") (pinfunction "VSS_4") (pintype "input"))
      (node (ref "IC186") (pin "4") (pinfunction "VSS_4") (pintype "input"))
      (node (ref "IC187") (pin "4") (pinfunction "VSS_4") (pintype "input"))
      (node (ref "IC188") (pin "4") (pinfunction "VSS_4") (pintype "input"))
      (node (ref "IC189") (pin "4") (pinfunction "VSS_4") (pintype "input"))
      (node (ref "IC19") (pin "2") (pinfunction "GND_2") (pintype "input"))
      (node (ref "IC190") (pin "4") (pinfunction "VSS_4") (pintype "input"))
      (node (ref "IC191") (pin "4") (pinfunction "VSS_4") (pintype "input"))
      (node (ref "IC192") (pin "4") (pinfunction "VSS_4") (pintype "input"))
      (node (ref "IC193") (pin "4") (pinfunction "VSS_4") (pintype "input"))
      (node (ref "IC194") (pin "4") (pinfunction "VSS_4") (pintype "input"))
      (node (ref "IC195") (pin "4") (pinfunction "VSS_4") (pintype "input"))
      (node (ref "IC196") (pin "4") (pinfunction "VSS_4") (pintype "input"))
      (node (ref "IC197") (pin "4") (pinfunction "VSS_4") (pintype "input"))
      (node (ref "IC198") (pin "4") (pinfunction "VSS_4") (pintype "input"))
      (node (ref "IC199") (pin "4") (pinfunction "VSS_4") (pintype "input"))
      (node (ref "IC2") (pin "2") (pinfunction "GND_2") (pintype "input"))
      (node (ref "IC20") (pin "2") (pinfunction "GND_2") (pintype "input"))
      (node (ref "IC200") (pin "4") (pinfunction "VSS_4") (pintype "input"))
      (node (ref "IC201") (pin "4") (pinfunction "VSS_4") (pintype "input"))
      (node (ref "IC202") (pin "4") (pinfunction "VSS_4") (pintype "input"))
      (node (ref "IC203") (pin "4") (pinfunction "VSS_4") (pintype "input"))
      (node (ref "IC204") (pin "4") (pinfunction "VSS_4") (pintype "input"))
      (node (ref "IC205") (pin "4") (pinfunction "VSS_4") (pintype "input"))
      (node (ref "IC206") (pin "4") (pinfunction "VSS_4") (pintype "input"))
      (node (ref "IC207") (pin "4") (pinfunction "VSS_4") (pintype "input"))
      (node (ref "IC208") (pin "4") (pinfunction "VSS_4") (pintype "input"))
      (node (ref "IC209") (pin "4") (pinfunction "VSS_4") (pintype "input"))
      (node (ref "IC21") (pin "3") (pinfunction "VBUS/GND1_3") (pintype "input"))
      (node (ref "IC21") (pin "6") (pinfunction "GND2_6") (pintype "input"))
      (node (ref "IC21") (pin "MNT1") (pinfunction "MNT1_MNT1") (pintype "passive"))
      (node (ref "IC21") (pin "MNT2") (pinfunction "MNT2_MNT2") (pintype "passive"))
      (node (ref "IC210") (pin "4") (pinfunction "VSS_4") (pintype "input"))
      (node (ref "IC211") (pin "4") (pinfunction "VSS_4") (pintype "input"))
      (node (ref "IC212") (pin "4") (pinfunction "VSS_4") (pintype "input"))
      (node (ref "IC213") (pin "4") (pinfunction "VSS_4") (pintype "input"))
      (node (ref "IC214") (pin "4") (pinfunction "VSS_4") (pintype "input"))
      (node (ref "IC215") (pin "4") (pinfunction "VSS_4") (pintype "input"))
      (node (ref "IC216") (pin "4") (pinfunction "VSS_4") (pintype "input"))
      (node (ref "IC217") (pin "4") (pinfunction "VSS_4") (pintype "input"))
      (node (ref "IC218") (pin "4") (pinfunction "VSS_4") (pintype "input"))
      (node (ref "IC219") (pin "4") (pinfunction "VSS_4") (pintype "input"))
      (node (ref "IC22") (pin "3") (pinfunction "VBUS/GND1_3") (pintype "input"))
      (node (ref "IC22") (pin "6") (pinfunction "GND2_6") (pintype "input"))
      (node (ref "IC22") (pin "MNT1") (pinfunction "MNT1_MNT1") (pintype "passive"))
      (node (ref "IC22") (pin "MNT2") (pinfunction "MNT2_MNT2") (pintype "passive"))
      (node (ref "IC220") (pin "4") (pinfunction "VSS_4") (pintype "input"))
      (node (ref "IC221") (pin "4") (pinfunction "VSS_4") (pintype "input"))
      (node (ref "IC222") (pin "4") (pinfunction "VSS_4") (pintype "input"))
      (node (ref "IC223") (pin "4") (pinfunction "VSS_4") (pintype "input"))
      (node (ref "IC224") (pin "4") (pinfunction "VSS_4") (pintype "input"))
      (node (ref "IC225") (pin "4") (pinfunction "VSS_4") (pintype "input"))
      (node (ref "IC226") (pin "4") (pinfunction "VSS_4") (pintype "input"))
      (node (ref "IC227") (pin "4") (pinfunction "VSS_4") (pintype "input"))
      (node (ref "IC228") (pin "4") (pinfunction "VSS_4") (pintype "input"))
      (node (ref "IC229") (pin "4") (pinfunction "VSS_4") (pintype "input"))
      (node (ref "IC23") (pin "1") (pinfunction "NC_1") (pintype "passive"))
      (node (ref "IC23") (pin "13") (pinfunction "GND_13") (pintype "input"))
      (node (ref "IC23") (pin "14") (pinfunction "A1_14") (pintype "input"))
      (node (ref "IC23") (pin "7") (pinfunction "DB_7") (pintype "passive"))
      (node (ref "IC230") (pin "4") (pinfunction "VSS_4") (pintype "input"))
      (node (ref "IC231") (pin "4") (pinfunction "VSS_4") (pintype "input"))
      (node (ref "IC232") (pin "4") (pinfunction "VSS_4") (pintype "input"))
      (node (ref "IC233") (pin "4") (pinfunction "VSS_4") (pintype "input"))
      (node (ref "IC234") (pin "4") (pinfunction "VSS_4") (pintype "input"))
      (node (ref "IC235") (pin "4") (pinfunction "VSS_4") (pintype "input"))
      (node (ref "IC236") (pin "4") (pinfunction "VSS_4") (pintype "input"))
      (node (ref "IC237") (pin "4") (pinfunction "VSS_4") (pintype "input"))
      (node (ref "IC238") (pin "4") (pinfunction "VSS_4") (pintype "input"))
      (node (ref "IC239") (pin "4") (pinfunction "VSS_4") (pintype "input"))
      (node (ref "IC24") (pin "2") (pinfunction "GND_2") (pintype "input"))
      (node (ref "IC24") (pin "4") (pinfunction "ADD0_4") (pintype "input"))
      (node (ref "IC240") (pin "4") (pinfunction "VSS_4") (pintype "input"))
      (node (ref "IC241") (pin "4") (pinfunction "VSS_4") (pintype "input"))
      (node (ref "IC242") (pin "4") (pinfunction "VSS_4") (pintype "input"))
      (node (ref "IC243") (pin "4") (pinfunction "VSS_4") (pintype "input"))
      (node (ref "IC244") (pin "4") (pinfunction "VSS_4") (pintype "input"))
      (node (ref "IC245") (pin "4") (pinfunction "VSS_4") (pintype "input"))
      (node (ref "IC246") (pin "4") (pinfunction "VSS_4") (pintype "input"))
      (node (ref "IC247") (pin "4") (pinfunction "VSS_4") (pintype "input"))
      (node (ref "IC248") (pin "4") (pinfunction "VSS_4") (pintype "input"))
      (node (ref "IC249") (pin "4") (pinfunction "VSS_4") (pintype "input"))
      (node (ref "IC25") (pin "3") (pinfunction "GND_3") (pintype "input"))
      (node (ref "IC25") (pin "PAD") (pinfunction "GND_PAD") (pintype "input"))
      (node (ref "IC250") (pin "4") (pinfunction "VSS_4") (pintype "input"))
      (node (ref "IC251") (pin "4") (pinfunction "VSS_4") (pintype "input"))
      (node (ref "IC252") (pin "4") (pinfunction "VSS_4") (pintype "input"))
      (node (ref "IC253") (pin "4") (pinfunction "VSS_4") (pintype "input"))
      (node (ref "IC254") (pin "4") (pinfunction "VSS_4") (pintype "input"))
      (node (ref "IC255") (pin "4") (pinfunction "VSS_4") (pintype "input"))
      (node (ref "IC256") (pin "4") (pinfunction "VSS_4") (pintype "input"))
      (node (ref "IC257") (pin "4") (pinfunction "VSS_4") (pintype "input"))
      (node (ref "IC258") (pin "4") (pinfunction "VSS_4") (pintype "input"))
      (node (ref "IC259") (pin "4") (pinfunction "VSS_4") (pintype "input"))
      (node (ref "IC260") (pin "4") (pinfunction "VSS_4") (pintype "input"))
      (node (ref "IC261") (pin "4") (pinfunction "VSS_4") (pintype "input"))
      (node (ref "IC262") (pin "4") (pinfunction "VSS_4") (pintype "input"))
      (node (ref "IC263") (pin "4") (pinfunction "VSS_4") (pintype "input"))
      (node (ref "IC264") (pin "4") (pinfunction "VSS_4") (pintype "input"))
      (node (ref "IC265") (pin "4") (pinfunction "VSS_4") (pintype "input"))
      (node (ref "IC266") (pin "4") (pinfunction "VSS_4") (pintype "input"))
      (node (ref "IC267") (pin "4") (pinfunction "VSS_4") (pintype "input"))
      (node (ref "IC268") (pin "4") (pinfunction "VSS_4") (pintype "input"))
      (node (ref "IC269") (pin "4") (pinfunction "VSS_4") (pintype "input"))
      (node (ref "IC270") (pin "4") (pinfunction "VSS_4") (pintype "input"))
      (node (ref "IC271") (pin "4") (pinfunction "VSS_4") (pintype "input"))
      (node (ref "IC272") (pin "4") (pinfunction "VSS_4") (pintype "input"))
      (node (ref "IC273") (pin "4") (pinfunction "VSS_4") (pintype "input"))
      (node (ref "IC274") (pin "4") (pinfunction "VSS_4") (pintype "input"))
      (node (ref "IC275") (pin "4") (pinfunction "VSS_4") (pintype "input"))
      (node (ref "IC276") (pin "4") (pinfunction "VSS_4") (pintype "input"))
      (node (ref "IC277") (pin "4") (pinfunction "VSS_4") (pintype "input"))
      (node (ref "IC278") (pin "4") (pinfunction "VSS_4") (pintype "input"))
      (node (ref "IC279") (pin "4") (pinfunction "VSS_4") (pintype "input"))
      (node (ref "IC280") (pin "4") (pinfunction "VSS_4") (pintype "input"))
      (node (ref "IC281") (pin "4") (pinfunction "VSS_4") (pintype "input"))
      (node (ref "IC282") (pin "4") (pinfunction "VSS_4") (pintype "input"))
      (node (ref "IC283") (pin "4") (pinfunction "VSS_4") (pintype "input"))
      (node (ref "IC284") (pin "4") (pinfunction "VSS_4") (pintype "input"))
      (node (ref "IC285") (pin "4") (pinfunction "VSS_4") (pintype "input"))
      (node (ref "IC286") (pin "4") (pinfunction "VSS_4") (pintype "input"))
      (node (ref "IC287") (pin "4") (pinfunction "VSS_4") (pintype "input"))
      (node (ref "IC288") (pin "4") (pinfunction "VSS_4") (pintype "input"))
      (node (ref "IC289") (pin "4") (pinfunction "VSS_4") (pintype "input"))
      (node (ref "IC290") (pin "4") (pinfunction "VSS_4") (pintype "input"))
      (node (ref "IC291") (pin "4") (pinfunction "VSS_4") (pintype "input"))
      (node (ref "IC292") (pin "4") (pinfunction "VSS_4") (pintype "input"))
      (node (ref "IC293") (pin "4") (pinfunction "VSS_4") (pintype "input"))
      (node (ref "IC294") (pin "4") (pinfunction "VSS_4") (pintype "input"))
      (node (ref "IC295") (pin "4") (pinfunction "VSS_4") (pintype "input"))
      (node (ref "IC296") (pin "4") (pinfunction "VSS_4") (pintype "input"))
      (node (ref "IC297") (pin "4") (pinfunction "VSS_4") (pintype "input"))
      (node (ref "IC298") (pin "4") (pinfunction "VSS_4") (pintype "input"))
      (node (ref "IC299") (pin "4") (pinfunction "VSS_4") (pintype "input"))
      (node (ref "IC3") (pin "4") (pinfunction "GND_4") (pintype "input"))
      (node (ref "IC3") (pin "PAD") (pinfunction "GND_PAD") (pintype "input"))
      (node (ref "IC300") (pin "4") (pinfunction "VSS_4") (pintype "input"))
      (node (ref "IC301") (pin "4") (pinfunction "VSS_4") (pintype "input"))
      (node (ref "IC302") (pin "4") (pinfunction "VSS_4") (pintype "input"))
      (node (ref "IC303") (pin "4") (pinfunction "VSS_4") (pintype "input"))
      (node (ref "IC304") (pin "4") (pinfunction "VSS_4") (pintype "input"))
      (node (ref "IC305") (pin "4") (pinfunction "VSS_4") (pintype "input"))
      (node (ref "IC306") (pin "4") (pinfunction "VSS_4") (pintype "input"))
      (node (ref "IC307") (pin "4") (pinfunction "VSS_4") (pintype "input"))
      (node (ref "IC308") (pin "4") (pinfunction "VSS_4") (pintype "input"))
      (node (ref "IC309") (pin "4") (pinfunction "VSS_4") (pintype "input"))
      (node (ref "IC310") (pin "4") (pinfunction "VSS_4") (pintype "input"))
      (node (ref "IC311") (pin "4") (pinfunction "VSS_4") (pintype "input"))
      (node (ref "IC312") (pin "4") (pinfunction "VSS_4") (pintype "input"))
      (node (ref "IC313") (pin "4") (pinfunction "VSS_4") (pintype "input"))
      (node (ref "IC314") (pin "4") (pinfunction "VSS_4") (pintype "input"))
      (node (ref "IC315") (pin "4") (pinfunction "VSS_4") (pintype "input"))
      (node (ref "IC316") (pin "4") (pinfunction "VSS_4") (pintype "input"))
      (node (ref "IC317") (pin "4") (pinfunction "VSS_4") (pintype "input"))
      (node (ref "IC318") (pin "4") (pinfunction "VSS_4") (pintype "input"))
      (node (ref "IC319") (pin "4") (pinfunction "VSS_4") (pintype "input"))
      (node (ref "IC320") (pin "4") (pinfunction "VSS_4") (pintype "input"))
      (node (ref "IC321") (pin "4") (pinfunction "VSS_4") (pintype "input"))
      (node (ref "IC322") (pin "4") (pinfunction "VSS_4") (pintype "input"))
      (node (ref "IC323") (pin "4") (pinfunction "VSS_4") (pintype "input"))
      (node (ref "IC324") (pin "4") (pinfunction "VSS_4") (pintype "input"))
      (node (ref "IC325") (pin "4") (pinfunction "VSS_4") (pintype "input"))
      (node (ref "IC326") (pin "4") (pinfunction "VSS_4") (pintype "input"))
      (node (ref "IC327") (pin "4") (pinfunction "VSS_4") (pintype "input"))
      (node (ref "IC328") (pin "4") (pinfunction "VSS_4") (pintype "input"))
      (node (ref "IC329") (pin "4") (pinfunction "VSS_4") (pintype "input"))
      (node (ref "IC330") (pin "4") (pinfunction "VSS_4") (pintype "input"))
      (node (ref "IC331") (pin "4") (pinfunction "VSS_4") (pintype "input"))
      (node (ref "IC332") (pin "4") (pinfunction "VSS_4") (pintype "input"))
      (node (ref "IC4") (pin "4") (pinfunction "GND_4") (pintype "input"))
      (node (ref "IC4") (pin "6") (pinfunction "-IN_6") (pintype "input"))
      (node (ref "IC4") (pin "PAD") (pinfunction "GND_PAD") (pintype "input"))
      (node (ref "IC5") (pin "4") (pinfunction "GND_4") (pintype "input"))
      (node (ref "IC5") (pin "6") (pinfunction "-IN_6") (pintype "input"))
      (node (ref "IC5") (pin "PAD") (pinfunction "GND_PAD") (pintype "input"))
      (node (ref "IC6") (pin "2") (pinfunction "1_2") (pintype "passive"))
      (node (ref "IC6") (pin "3") (pinfunction "E_3") (pintype "passive"))
      (node (ref "IC6") (pin "5") (pinfunction "1_5") (pintype "passive"))
      (node (ref "IC6") (pin "6") (pinfunction "C_6") (pintype "passive"))
      (node (ref "IC7") (pin "12") (pinfunction "GND_12") (pintype "input"))
      (node (ref "IC7") (pin "2") (pinfunction "AVSSVCSEL_2") (pintype "input"))
      (node (ref "IC7") (pin "3") (pinfunction "GND_3") (pintype "input"))
      (node (ref "IC7") (pin "4") (pinfunction "GND_4") (pintype "input"))
      (node (ref "IC7") (pin "6") (pinfunction "GND_6") (pintype "input"))
      (node (ref "IC8") (pin "2") (pinfunction "GND_2") (pintype "input"))
      (node (ref "IC9") (pin "1") (pinfunction "CLK_1") (pintype "input"))
      (node (ref "IC9") (pin "10") (pinfunction "~{PRE}_10") (pintype "input"))
      (node (ref "IC9") (pin "11") (pinfunction "J_11") (pintype "input"))
      (node (ref "IC9") (pin "12") (pinfunction "K_12") (pintype "input"))
      (node (ref "IC9") (pin "13") (pinfunction "CLK_13") (pintype "input"))
      (node (ref "IC9") (pin "14") (pinfunction "~{CLR}_14") (pintype "input"))
      (node (ref "IC9") (pin "2") (pinfunction "K_2") (pintype "input"))
      (node (ref "IC9") (pin "3") (pinfunction "J_3") (pintype "input"))
      (node (ref "IC9") (pin "8") (pinfunction "GND_8") (pintype "input"))
      (node (ref "R18") (pin "1") (pinfunction "1_1") (pintype "passive"))
      (node (ref "R3") (pin "1") (pinfunction "1_1") (pintype "passive"))
      (node (ref "R4") (pin "1") (pinfunction "1_1") (pintype "passive"))
      (node (ref "R45") (pin "1") (pinfunction "1_1") (pintype "passive"))
      (node (ref "R49") (pin "1") (pinfunction "1_1") (pintype "passive"))
      (node (ref "R5") (pin "1") (pinfunction "1_1") (pintype "passive"))
      (node (ref "R6") (pin "1") (pinfunction "1_1") (pintype "passive"))
      (node (ref "R65") (pin "1") (pinfunction "1_1") (pintype "passive"))
      (node (ref "R70") (pin "1") (pinfunction "1_1") (pintype "passive"))
      (node (ref "SW1") (pin "1") (pinfunction "1A_1") (pintype "passive"))
      (node (ref "SW1") (pin "2") (pinfunction "1A_2") (pintype "passive"))
      (node (ref "T10") (pin "2") (pinfunction "S_2") (pintype "passive"))
      (node (ref "T2") (pin "2") (pinfunction "S_2") (pintype "passive"))
      (node (ref "T3") (pin "2") (pinfunction "S_2") (pintype "passive"))
      (node (ref "T6") (pin "2") (pinfunction "S_2") (pintype "passive"))
      (node (ref "T7") (pin "2") (pinfunction "S_2") (pintype "passive"))
      (node (ref "T8") (pin "2") (pinfunction "S_2") (pintype "passive"))
      (node (ref "TP1") (pin "TP") (pinfunction "TP_TP") (pintype "input"))
      (node (ref "X1") (pin "01") (pinfunction "1_01") (pintype "passive"))
      (node (ref "X1") (pin "02") (pinfunction "2_02") (pintype "passive"))
      (node (ref "X1") (pin "06") (pinfunction "6_06") (pintype "passive"))
      (node (ref "X1") (pin "07") (pinfunction "7_07") (pintype "passive"))
      (node (ref "X1") (pin "13") (pinfunction "13_13") (pintype "passive"))
      (node (ref "X1") (pin "19") (pinfunction "19_19") (pintype "passive"))
      (node (ref "X1") (pin "21") (pinfunction "21_21") (pintype "passive"))
      (node (ref "X1") (pin "26") (pinfunction "26_26") (pintype "passive"))
      (node (ref "X1") (pin "28") (pinfunction "28_28") (pintype "passive"))
      (node (ref "X1") (pin "32") (pinfunction "32_32") (pintype "passive"))
      (node (ref "X1") (pin "33") (pinfunction "33_33") (pintype "passive"))
      (node (ref "X1") (pin "39") (pinfunction "39_39") (pintype "passive"))
      (node (ref "X1") (pin "40") (pinfunction "40_40") (pintype "passive"))
      (node (ref "X2") (pin "01") (pinfunction "1_01") (pintype "passive"))
      (node (ref "X2") (pin "03") (pinfunction "3_03") (pintype "passive"))
      (node (ref "X2") (pin "05") (pinfunction "5_05") (pintype "passive"))
      (node (ref "X2") (pin "07") (pinfunction "7_07") (pintype "passive"))
      (node (ref "X2") (pin "09") (pinfunction "9_09") (pintype "passive"))
      (node (ref "X2") (pin "10") (pinfunction "10_10") (pintype "passive"))
      (node (ref "X2") (pin "11") (pinfunction "11_11") (pintype "passive"))
      (node (ref "X2") (pin "18") (pinfunction "18_18") (pintype "passive"))
      (node (ref "X2") (pin "24") (pinfunction "24_24") (pintype "passive"))
      (node (ref "X2") (pin "25") (pinfunction "25_25") (pintype "passive"))
      (node (ref "X2") (pin "28") (pinfunction "28_28") (pintype "passive"))
      (node (ref "X2") (pin "31") (pinfunction "31_31") (pintype "passive"))
      (node (ref "X2") (pin "34") (pinfunction "34_34") (pintype "passive"))
      (node (ref "X2") (pin "35") (pinfunction "35_35") (pintype "passive"))
      (node (ref "X2") (pin "37") (pinfunction "37_37") (pintype "passive"))
      (node (ref "X2") (pin "39") (pinfunction "39_39") (pintype "passive"))
      (node (ref "X2") (pin "40") (pinfunction "40_40") (pintype "passive"))
      (node (ref "X3") (pin "12") (pinfunction "12_12") (pintype "bidirectional"))
      (node (ref "X3") (pin "15") (pinfunction "15_15") (pintype "bidirectional"))
      (node (ref "X3") (pin "16") (pinfunction "16_16") (pintype "bidirectional"))
      (node (ref "X3") (pin "22") (pinfunction "22_22") (pintype "bidirectional"))
      (node (ref "X3") (pin "23") (pinfunction "23_23") (pintype "bidirectional"))
      (node (ref "X3") (pin "25") (pinfunction "25_25") (pintype "bidirectional"))
      (node (ref "X3") (pin "3") (pinfunction "3_3") (pintype "bidirectional"))
      (node (ref "X3") (pin "6") (pinfunction "6_6") (pintype "bidirectional"))
      (node (ref "X3") (pin "9") (pinfunction "9_9") (pintype "bidirectional"))
      (node (ref "X4") (pin "1") (pinfunction "1_1") (pintype "passive"))
      (node (ref "X4") (pin "11") (pinfunction "11_11") (pintype "passive"))
      (node (ref "X4") (pin "12") (pinfunction "12_12") (pintype "passive"))
      (node (ref "X4") (pin "2") (pinfunction "2_2") (pintype "passive"))
      (node (ref "X4") (pin "Z1") (pinfunction "Z1_Z1") (pintype "passive"))
      (node (ref "X4") (pin "Z2") (pinfunction "Z2_Z2") (pintype "passive"))
      (node (ref "X5") (pin "13") (pinfunction "13_13") (pintype "passive"))
      (node (ref "X5") (pin "16") (pinfunction "16_16") (pintype "passive"))
      (node (ref "X5") (pin "19") (pinfunction "19_19") (pintype "passive"))
      (node (ref "X5") (pin "22") (pinfunction "22_22") (pintype "passive"))
      (node (ref "X5") (pin "25") (pinfunction "25_25") (pintype "passive"))
      (node (ref "X5") (pin "28") (pinfunction "28_28") (pintype "passive"))
      (node (ref "X5") (pin "5") (pinfunction "5_5") (pintype "passive"))
      (node (ref "X5") (pin "9") (pinfunction "9_9") (pintype "passive"))
      (node (ref "X5") (pin "S1") (pinfunction "S_S1") (pintype "passive"))
      (node (ref "X5") (pin "S2") (pinfunction "S_S2") (pintype "passive"))
      (node (ref "X5") (pin "S3") (pinfunction "S_S3") (pintype "passive"))
      (node (ref "X5") (pin "S4") (pinfunction "S_S4") (pintype "passive"))
    )
    (net (code "42") (name "HEAT_CAM_ARESET_N_2V8") (class "Default")
      (node (ref "IC20") (pin "4") (pinfunction "I/O3_4") (pintype "passive"))
      (node (ref "X2") (pin "23") (pinfunction "23_23") (pintype "passive"))
      (node (ref "X4") (pin "5") (pinfunction "5_5") (pintype "passive"))
    )
    (net (code "43") (name "HEAT_CAM_FPA_EN_2V8") (class "Default")
      (node (ref "IC19") (pin "6") (pinfunction "I/O4_6") (pintype "passive"))
      (node (ref "X2") (pin "13") (pinfunction "13_13") (pintype "passive"))
      (node (ref "X4") (pin "10") (pinfunction "10_10") (pintype "passive"))
    )
    (net (code "44") (name "HEAT_CAM_MISO_2V8") (class "Default")
      (node (ref "IC19") (pin "1") (pinfunction "I/O1_1") (pintype "passive"))
      (node (ref "R87") (pin "2") (pinfunction "2_2") (pintype "passive"))
      (node (ref "X2") (pin "19") (pinfunction "19_19") (pintype "passive"))
    )
    (net (code "45") (name "HEAT_CAM_MOSI_2V8") (class "Default")
      (node (ref "IC19") (pin "3") (pinfunction "I/O2_3") (pintype "passive"))
      (node (ref "X2") (pin "17") (pinfunction "17_17") (pintype "passive"))
      (node (ref "X4") (pin "8") (pinfunction "8_8") (pintype "passive"))
    )
    (net (code "46") (name "HEAT_CAM_SCLK_2V8") (class "Default")
      (node (ref "IC19") (pin "4") (pinfunction "I/O3_4") (pintype "passive"))
      (node (ref "X2") (pin "15") (pinfunction "15_15") (pintype "passive"))
      (node (ref "X4") (pin "9") (pinfunction "9_9") (pintype "passive"))
    )
    (net (code "47") (name "HEAT_CAM_SCT_NSS_2V8") (class "Default")
      (node (ref "IC20") (pin "6") (pinfunction "I/O4_6") (pintype "passive"))
      (node (ref "X2") (pin "21") (pinfunction "21_21") (pintype "passive"))
      (node (ref "X4") (pin "6") (pinfunction "6_6") (pintype "passive"))
    )
    (net (code "48") (name "IR_PHOTOTRANSITOR") (class "Default")
      (node (ref "IC6") (pin "4") (pinfunction "C_4") (pintype "passive"))
      (node (ref "R36") (pin "1") (pinfunction "1_1") (pintype "passive"))
      (node (ref "R53") (pin "2") (pinfunction "2_2") (pintype "passive"))
      (node (ref "R61") (pin "1") (pinfunction "1_1") (pintype "passive"))
    )
    (net (code "49") (name "MUX_VDD") (class "Default")
      (node (ref "C36") (pin "1") (pinfunction "1_1") (pintype "passive"))
      (node (ref "IC23") (pin "12") (pinfunction "VDD_12") (pintype "input"))
      (node (ref "IC23") (pin "16") (pinfunction "EN_16") (pintype "input"))
      (node (ref "R77") (pin "1") (pinfunction "1_1") (pintype "passive"))
    )
    (net (code "50") (name "Net-(C78-Pad1)") (class "Default")
      (node (ref "C78") (pin "1") (pinfunction "1_1") (pintype "passive"))
      (node (ref "R16") (pin "1") (pinfunction "1_1") (pintype "passive"))
      (node (ref "X5") (pin "10") (pinfunction "10_10") (pintype "passive"))
      (node (ref "X5") (pin "12") (pinfunction "12_12") (pintype "passive"))
      (node (ref "X5") (pin "14") (pinfunction "14_14") (pintype "passive"))
    )
    (net (code "51") (name "Net-(D1-PadC)") (class "Default")
      (node (ref "D1") (pin "C") (pinfunction "C_C") (pintype "passive"))
      (node (ref "R62") (pin "2") (pinfunction "2_2") (pintype "passive"))
    )
    (net (code "52") (name "Net-(D2-PadC)") (class "Default")
      (node (ref "D2") (pin "C") (pinfunction "C_C") (pintype "passive"))
      (node (ref "R67") (pin "2") (pinfunction "2_2") (pintype "passive"))
    )
    (net (code "53") (name "Net-(D100A-A-Pad2)") (class "Default")
      (node (ref "D100") (pin "2") (pinfunction "A_2") (pintype "passive"))
      (node (ref "D100") (pin "3") (pinfunction "A_3") (pintype "passive"))
      (node (ref "D112") (pin "1") (pinfunction "C_1") (pintype "passive"))
      (node (ref "D112") (pin "4") (pinfunction "C_4") (pintype "passive"))
    )
    (net (code "54") (name "Net-(D100A-C-Pad1)") (class "Default")
      (node (ref "D100") (pin "1") (pinfunction "C_1") (pintype "passive"))
      (node (ref "D100") (pin "4") (pinfunction "C_4") (pintype "passive"))
      (node (ref "D101") (pin "2") (pinfunction "A_2") (pintype "passive"))
      (node (ref "D101") (pin "3") (pinfunction "A_3") (pintype "passive"))
    )
    (net (code "55") (name "Net-(D101A-C-Pad1)") (class "Default")
      (node (ref "D101") (pin "1") (pinfunction "C_1") (pintype "passive"))
      (node (ref "D101") (pin "4") (pinfunction "C_4") (pintype "passive"))
      (node (ref "D102") (pin "2") (pinfunction "A_2") (pintype "passive"))
      (node (ref "D102") (pin "3") (pinfunction "A_3") (pintype "passive"))
    )
    (net (code "56") (name "Net-(D102A-C-Pad1)") (class "Default")
      (node (ref "D102") (pin "1") (pinfunction "C_1") (pintype "passive"))
      (node (ref "D102") (pin "4") (pinfunction "C_4") (pintype "passive"))
      (node (ref "D103") (pin "2") (pinfunction "A_2") (pintype "passive"))
      (node (ref "D103") (pin "3") (pinfunction "A_3") (pintype "passive"))
    )
    (net (code "57") (name "Net-(D103A-C-Pad1)") (class "Default")
      (node (ref "D103") (pin "1") (pinfunction "C_1") (pintype "passive"))
      (node (ref "D103") (pin "4") (pinfunction "C_4") (pintype "passive"))
      (node (ref "D104") (pin "2") (pinfunction "A_2") (pintype "passive"))
      (node (ref "D104") (pin "3") (pinfunction "A_3") (pintype "passive"))
    )
    (net (code "58") (name "Net-(D104A-C-Pad1)") (class "Default")
      (node (ref "D104") (pin "1") (pinfunction "C_1") (pintype "passive"))
      (node (ref "D104") (pin "4") (pinfunction "C_4") (pintype "passive"))
      (node (ref "D105") (pin "2") (pinfunction "A_2") (pintype "passive"))
      (node (ref "D105") (pin "3") (pinfunction "A_3") (pintype "passive"))
    )
    (net (code "59") (name "Net-(D106A-A-Pad2)") (class "Default")
      (node (ref "D106") (pin "2") (pinfunction "A_2") (pintype "passive"))
      (node (ref "D106") (pin "3") (pinfunction "A_3") (pintype "passive"))
      (node (ref "R83") (pin "1") (pinfunction "1_1") (pintype "passive"))
      (node (ref "R84") (pin "1") (pinfunction "1_1") (pintype "passive"))
    )
    (net (code "60") (name "Net-(D106A-C-Pad1)") (class "Default")
      (node (ref "D106") (pin "1") (pinfunction "C_1") (pintype "passive"))
      (node (ref "D106") (pin "4") (pinfunction "C_4") (pintype "passive"))
      (node (ref "D107") (pin "2") (pinfunction "A_2") (pintype "passive"))
      (node (ref "D107") (pin "3") (pinfunction "A_3") (pintype "passive"))
    )
    (net (code "61") (name "Net-(D107A-C-Pad1)") (class "Default")
      (node (ref "D107") (pin "1") (pinfunction "C_1") (pintype "passive"))
      (node (ref "D107") (pin "4") (pinfunction "C_4") (pintype "passive"))
      (node (ref "D108") (pin "2") (pinfunction "A_2") (pintype "passive"))
      (node (ref "D108") (pin "3") (pinfunction "A_3") (pintype "passive"))
    )
    (net (code "62") (name "Net-(D108A-C-Pad1)") (class "Default")
      (node (ref "D108") (pin "1") (pinfunction "C_1") (pintype "passive"))
      (node (ref "D108") (pin "4") (pinfunction "C_4") (pintype "passive"))
      (node (ref "D109") (pin "2") (pinfunction "A_2") (pintype "passive"))
      (node (ref "D109") (pin "3") (pinfunction "A_3") (pintype "passive"))
    )
    (net (code "63") (name "Net-(D109A-C-Pad1)") (class "Default")
      (node (ref "D109") (pin "1") (pinfunction "C_1") (pintype "passive"))
      (node (ref "D109") (pin "4") (pinfunction "C_4") (pintype "passive"))
      (node (ref "D110") (pin "2") (pinfunction "A_2") (pintype "passive"))
      (node (ref "D110") (pin "3") (pinfunction "A_3") (pintype "passive"))
    )
    (net (code "64") (name "Net-(D110A-C-Pad1)") (class "Default")
      (node (ref "D110") (pin "1") (pinfunction "C_1") (pintype "passive"))
      (node (ref "D110") (pin "4") (pinfunction "C_4") (pintype "passive"))
      (node (ref "D111") (pin "2") (pinfunction "A_2") (pintype "passive"))
      (node (ref "D111") (pin "3") (pinfunction "A_3") (pintype "passive"))
    )
    (net (code "65") (name "Net-(D111A-C-Pad1)") (class "Default")
      (node (ref "D111") (pin "1") (pinfunction "C_1") (pintype "passive"))
      (node (ref "D111") (pin "4") (pinfunction "C_4") (pintype "passive"))
      (node (ref "D112") (pin "2") (pinfunction "A_2") (pintype "passive"))
      (node (ref "D112") (pin "3") (pinfunction "A_3") (pintype "passive"))
    )
    (net (code "66") (name "Net-(D200-PadA)") (class "Default")
      (node (ref "D200") (pin "A") (pinfunction "A_A") (pintype "passive"))
      (node (ref "D201") (pin "C") (pinfunction "C_C") (pintype "passive"))
    )
    (net (code "67") (name "Net-(D201-PadA)") (class "Default")
      (node (ref "D201") (pin "A") (pinfunction "A_A") (pintype "passive"))
      (node (ref "D202") (pin "C") (pinfunction "C_C") (pintype "passive"))
    )
    (net (code "68") (name "Net-(D202-PadA)") (class "Default")
      (node (ref "D202") (pin "A") (pinfunction "A_A") (pintype "passive"))
      (node (ref "D203") (pin "C") (pinfunction "C_C") (pintype "passive"))
    )
    (net (code "69") (name "Net-(D203-PadA)") (class "Default")
      (node (ref "D203") (pin "A") (pinfunction "A_A") (pintype "passive"))
      (node (ref "D204") (pin "C") (pinfunction "C_C") (pintype "passive"))
    )
    (net (code "70") (name "Net-(D204-PadA)") (class "Default")
      (node (ref "D204") (pin "A") (pinfunction "A_A") (pintype "passive"))
      (node (ref "D205") (pin "C") (pinfunction "C_C") (pintype "passive"))
    )
    (net (code "71") (name "Net-(D205-PadA)") (class "Default")
      (node (ref "D205") (pin "A") (pinfunction "A_A") (pintype "passive"))
      (node (ref "D206") (pin "C") (pinfunction "C_C") (pintype "passive"))
    )
    (net (code "72") (name "Net-(D206-PadA)") (class "Default")
      (node (ref "D206") (pin "A") (pinfunction "A_A") (pintype "passive"))
      (node (ref "D215") (pin "C") (pinfunction "C_C") (pintype "passive"))
    )
    (net (code "73") (name "Net-(D207-PadA)") (class "Default")
      (node (ref "D207") (pin "A") (pinfunction "A_A") (pintype "passive"))
      (node (ref "D208") (pin "C") (pinfunction "C_C") (pintype "passive"))
    )
    (net (code "74") (name "Net-(D208-PadA)") (class "Default")
      (node (ref "D208") (pin "A") (pinfunction "A_A") (pintype "passive"))
      (node (ref "D209") (pin "C") (pinfunction "C_C") (pintype "passive"))
    )
    (net (code "75") (name "Net-(D209-PadA)") (class "Default")
      (node (ref "D209") (pin "A") (pinfunction "A_A") (pintype "passive"))
      (node (ref "D210") (pin "C") (pinfunction "C_C") (pintype "passive"))
    )
    (net (code "76") (name "Net-(D210-PadA)") (class "Default")
      (node (ref "D210") (pin "A") (pinfunction "A_A") (pintype "passive"))
      (node (ref "D211") (pin "C") (pinfunction "C_C") (pintype "passive"))
    )
    (net (code "77") (name "Net-(D211-PadA)") (class "Default")
      (node (ref "D211") (pin "A") (pinfunction "A_A") (pintype "passive"))
      (node (ref "D212") (pin "C") (pinfunction "C_C") (pintype "passive"))
    )
    (net (code "78") (name "Net-(D212-PadA)") (class "Default")
      (node (ref "D212") (pin "A") (pinfunction "A_A") (pintype "passive"))
      (node (ref "D213") (pin "C") (pinfunction "C_C") (pintype "passive"))
    )
    (net (code "79") (name "Net-(D213-PadA)") (class "Default")
      (node (ref "D213") (pin "A") (pinfunction "A_A") (pintype "passive"))
      (node (ref "D214") (pin "C") (pinfunction "C_C") (pintype "passive"))
    )
    (net (code "80") (name "Net-(D214-PadA)") (class "Default")
      (node (ref "D214") (pin "A") (pinfunction "A_A") (pintype "passive"))
      (node (ref "R34") (pin "1") (pinfunction "1_1") (pintype "passive"))
      (node (ref "R35") (pin "1") (pinfunction "1_1") (pintype "passive"))
    )
    (net (code "81") (name "Net-(D215-PadA)") (class "Default")
      (node (ref "D215") (pin "A") (pinfunction "A_A") (pintype "passive"))
      (node (ref "R20") (pin "1") (pinfunction "1_1") (pintype "passive"))
      (node (ref "R22") (pin "1") (pinfunction "1_1") (pintype "passive"))
    )
    (net (code "82") (name "Net-(D250-PadA)") (class "Default")
      (node (ref "D250") (pin "A") (pinfunction "A_A") (pintype "passive"))
      (node (ref "D251") (pin "C") (pinfunction "C_C") (pintype "passive"))
    )
    (net (code "83") (name "Net-(D251-PadA)") (class "Default")
      (node (ref "D251") (pin "A") (pinfunction "A_A") (pintype "passive"))
      (node (ref "D252") (pin "C") (pinfunction "C_C") (pintype "passive"))
    )
    (net (code "84") (name "Net-(D252-PadA)") (class "Default")
      (node (ref "D252") (pin "A") (pinfunction "A_A") (pintype "passive"))
      (node (ref "D253") (pin "C") (pinfunction "C_C") (pintype "passive"))
    )
    (net (code "85") (name "Net-(D253-PadA)") (class "Default")
      (node (ref "D253") (pin "A") (pinfunction "A_A") (pintype "passive"))
      (node (ref "D254") (pin "C") (pinfunction "C_C") (pintype "passive"))
    )
    (net (code "86") (name "Net-(D254-PadA)") (class "Default")
      (node (ref "D254") (pin "A") (pinfunction "A_A") (pintype "passive"))
      (node (ref "D255") (pin "C") (pinfunction "C_C") (pintype "passive"))
    )
    (net (code "87") (name "Net-(D255-PadA)") (class "Default")
      (node (ref "D255") (pin "A") (pinfunction "A_A") (pintype "passive"))
      (node (ref "D256") (pin "C") (pinfunction "C_C") (pintype "passive"))
    )
    (net (code "88") (name "Net-(D256-PadA)") (class "Default")
      (node (ref "D256") (pin "A") (pinfunction "A_A") (pintype "passive"))
      (node (ref "D265") (pin "C") (pinfunction "C_C") (pintype "passive"))
    )
    (net (code "89") (name "Net-(D257-PadA)") (class "Default")
      (node (ref "D257") (pin "A") (pinfunction "A_A") (pintype "passive"))
      (node (ref "D258") (pin "C") (pinfunction "C_C") (pintype "passive"))
    )
    (net (code "90") (name "Net-(D258-PadA)") (class "Default")
      (node (ref "D258") (pin "A") (pinfunction "A_A") (pintype "passive"))
      (node (ref "D259") (pin "C") (pinfunction "C_C") (pintype "passive"))
    )
    (net (code "91") (name "Net-(D259-PadA)") (class "Default")
      (node (ref "D259") (pin "A") (pinfunction "A_A") (pintype "passive"))
      (node (ref "D260") (pin "C") (pinfunction "C_C") (pintype "passive"))
    )
    (net (code "92") (name "Net-(D260-PadA)") (class "Default")
      (node (ref "D260") (pin "A") (pinfunction "A_A") (pintype "passive"))
      (node (ref "D261") (pin "C") (pinfunction "C_C") (pintype "passive"))
    )
    (net (code "93") (name "Net-(D261-PadA)") (class "Default")
      (node (ref "D261") (pin "A") (pinfunction "A_A") (pintype "passive"))
      (node (ref "D262") (pin "C") (pinfunction "C_C") (pintype "passive"))
    )
    (net (code "94") (name "Net-(D262-PadA)") (class "Default")
      (node (ref "D262") (pin "A") (pinfunction "A_A") (pintype "passive"))
      (node (ref "D263") (pin "C") (pinfunction "C_C") (pintype "passive"))
    )
    (net (code "95") (name "Net-(D263-PadA)") (class "Default")
      (node (ref "D263") (pin "A") (pinfunction "A_A") (pintype "passive"))
      (node (ref "D264") (pin "C") (pinfunction "C_C") (pintype "passive"))
    )
    (net (code "96") (name "Net-(D264-PadA)") (class "Default")
      (node (ref "D264") (pin "A") (pinfunction "A_A") (pintype "passive"))
      (node (ref "R73") (pin "1") (pinfunction "1_1") (pintype "passive"))
      (node (ref "R75") (pin "1") (pinfunction "1_1") (pintype "passive"))
    )
    (net (code "97") (name "Net-(D265-PadA)") (class "Default")
      (node (ref "D265") (pin "A") (pinfunction "A_A") (pintype "passive"))
      (node (ref "R52") (pin "1") (pinfunction "1_1") (pintype "passive"))
      (node (ref "R57") (pin "1") (pinfunction "1_1") (pintype "passive"))
    )
    (net (code "98") (name "Net-(D300-PadA)") (class "Default")
      (node (ref "D300") (pin "A") (pinfunction "A_A") (pintype "passive"))
      (node (ref "D301") (pin "C") (pinfunction "C_C") (pintype "passive"))
    )
    (net (code "99") (name "Net-(D300-PadC)") (class "Default")
      (node (ref "D300") (pin "C") (pinfunction "C_C") (pintype "passive"))
      (node (ref "D307") (pin "A") (pinfunction "A_A") (pintype "passive"))
    )
    (net (code "100") (name "Net-(D301-PadA)") (class "Default")
      (node (ref "D301") (pin "A") (pinfunction "A_A") (pintype "passive"))
      (node (ref "D302") (pin "C") (pinfunction "C_C") (pintype "passive"))
    )
    (net (code "101") (name "Net-(D302-PadA)") (class "Default")
      (node (ref "D302") (pin "A") (pinfunction "A_A") (pintype "passive"))
      (node (ref "D303") (pin "C") (pinfunction "C_C") (pintype "passive"))
    )
    (net (code "102") (name "Net-(D303-PadA)") (class "Default")
      (node (ref "D303") (pin "A") (pinfunction "A_A") (pintype "passive"))
      (node (ref "D304") (pin "C") (pinfunction "C_C") (pintype "passive"))
    )
    (net (code "103") (name "Net-(D304-PadA)") (class "Default")
      (node (ref "D304") (pin "A") (pinfunction "A_A") (pintype "passive"))
      (node (ref "D305") (pin "C") (pinfunction "C_C") (pintype "passive"))
    )
    (net (code "104") (name "Net-(D305-PadA)") (class "Default")
      (node (ref "D305") (pin "A") (pinfunction "A_A") (pintype "passive"))
      (node (ref "R15") (pin "1") (pinfunction "1_1") (pintype "passive"))
      (node (ref "R8") (pin "1") (pinfunction "1_1") (pintype "passive"))
    )
    (net (code "105") (name "Net-(D306-PadA)") (class "Default")
      (node (ref "D306") (pin "A") (pinfunction "A_A") (pintype "passive"))
      (node (ref "D307") (pin "C") (pinfunction "C_C") (pintype "passive"))
    )
    (net (code "106") (name "Net-(D308-PadA)") (class "Default")
      (node (ref "D308") (pin "A") (pinfunction "A_A") (pintype "passive"))
      (node (ref "D309") (pin "C") (pinfunction "C_C") (pintype "passive"))
    )
    (net (code "107") (name "Net-(D309-PadA)") (class "Default")
      (node (ref "D309") (pin "A") (pinfunction "A_A") (pintype "passive"))
      (node (ref "D310") (pin "C") (pinfunction "C_C") (pintype "passive"))
    )
    (net (code "108") (name "Net-(D310-PadA)") (class "Default")
      (node (ref "D310") (pin "A") (pinfunction "A_A") (pintype "passive"))
      (node (ref "D311") (pin "C") (pinfunction "C_C") (pintype "passive"))
    )
    (net (code "109") (name "Net-(D311-PadA)") (class "Default")
      (node (ref "D311") (pin "A") (pinfunction "A_A") (pintype "passive"))
      (node (ref "D312") (pin "C") (pinfunction "C_C") (pintype "passive"))
    )
    (net (code "110") (name "Net-(D312-PadA)") (class "Default")
      (node (ref "D312") (pin "A") (pinfunction "A_A") (pintype "passive"))
      (node (ref "D313") (pin "C") (pinfunction "C_C") (pintype "passive"))
    )
    (net (code "111") (name "Net-(D313-PadA)") (class "Default")
      (node (ref "D313") (pin "A") (pinfunction "A_A") (pintype "passive"))
      (node (ref "D314") (pin "C") (pinfunction "C_C") (pintype "passive"))
    )
    (net (code "112") (name "Net-(D314-PadA)") (class "Default")
      (node (ref "D314") (pin "A") (pinfunction "A_A") (pintype "passive"))
      (node (ref "D315") (pin "C") (pinfunction "C_C") (pintype "passive"))
    )
    (net (code "113") (name "Net-(D315-PadA)") (class "Default")
      (node (ref "D315") (pin "A") (pinfunction "A_A") (pintype "passive"))
      (node (ref "R25") (pin "1") (pinfunction "1_1") (pintype "passive"))
      (node (ref "R29") (pin "1") (pinfunction "1_1") (pintype "passive"))
    )
    (net (code "114") (name "Net-(D350-PadA)") (class "Default")
      (node (ref "D350") (pin "A") (pinfunction "A_A") (pintype "passive"))
      (node (ref "D351") (pin "C") (pinfunction "C_C") (pintype "passive"))
    )
    (net (code "115") (name "Net-(D350-PadC)") (class "Default")
      (node (ref "D350") (pin "C") (pinfunction "C_C") (pintype "passive"))
      (node (ref "D357") (pin "A") (pinfunction "A_A") (pintype "passive"))
    )
    (net (code "116") (name "Net-(D351-PadA)") (class "Default")
      (node (ref "D351") (pin "A") (pinfunction "A_A") (pintype "passive"))
      (node (ref "D352") (pin "C") (pinfunction "C_C") (pintype "passive"))
    )
    (net (code "117") (name "Net-(D352-PadA)") (class "Default")
      (node (ref "D352") (pin "A") (pinfunction "A_A") (pintype "passive"))
      (node (ref "D353") (pin "C") (pinfunction "C_C") (pintype "passive"))
    )
    (net (code "118") (name "Net-(D353-PadA)") (class "Default")
      (node (ref "D353") (pin "A") (pinfunction "A_A") (pintype "passive"))
      (node (ref "D354") (pin "C") (pinfunction "C_C") (pintype "passive"))
    )
    (net (code "119") (name "Net-(D354-PadA)") (class "Default")
      (node (ref "D354") (pin "A") (pinfunction "A_A") (pintype "passive"))
      (node (ref "D355") (pin "C") (pinfunction "C_C") (pintype "passive"))
    )
    (net (code "120") (name "Net-(D355-PadA)") (class "Default")
      (node (ref "D355") (pin "A") (pinfunction "A_A") (pintype "passive"))
      (node (ref "R43") (pin "1") (pinfunction "1_1") (pintype "passive"))
      (node (ref "R46") (pin "1") (pinfunction "1_1") (pintype "passive"))
    )
    (net (code "121") (name "Net-(D356-PadA)") (class "Default")
      (node (ref "D356") (pin "A") (pinfunction "A_A") (pintype "passive"))
      (node (ref "D357") (pin "C") (pinfunction "C_C") (pintype "passive"))
    )
    (net (code "122") (name "Net-(D358-PadA)") (class "Default")
      (node (ref "D358") (pin "A") (pinfunction "A_A") (pintype "passive"))
      (node (ref "D359") (pin "C") (pinfunction "C_C") (pintype "passive"))
    )
    (net (code "123") (name "Net-(D359-PadA)") (class "Default")
      (node (ref "D359") (pin "A") (pinfunction "A_A") (pintype "passive"))
      (node (ref "D360") (pin "C") (pinfunction "C_C") (pintype "passive"))
    )
    (net (code "124") (name "Net-(D360-PadA)") (class "Default")
      (node (ref "D360") (pin "A") (pinfunction "A_A") (pintype "passive"))
      (node (ref "D361") (pin "C") (pinfunction "C_C") (pintype "passive"))
    )
    (net (code "125") (name "Net-(D361-PadA)") (class "Default")
      (node (ref "D361") (pin "A") (pinfunction "A_A") (pintype "passive"))
      (node (ref "D362") (pin "C") (pinfunction "C_C") (pintype "passive"))
    )
    (net (code "126") (name "Net-(D362-PadA)") (class "Default")
      (node (ref "D362") (pin "A") (pinfunction "A_A") (pintype "passive"))
      (node (ref "D363") (pin "C") (pinfunction "C_C") (pintype "passive"))
    )
    (net (code "127") (name "Net-(D363-PadA)") (class "Default")
      (node (ref "D363") (pin "A") (pinfunction "A_A") (pintype "passive"))
      (node (ref "D364") (pin "C") (pinfunction "C_C") (pintype "passive"))
    )
    (net (code "128") (name "Net-(D364-PadA)") (class "Default")
      (node (ref "D364") (pin "A") (pinfunction "A_A") (pintype "passive"))
      (node (ref "D365") (pin "C") (pinfunction "C_C") (pintype "passive"))
    )
    (net (code "129") (name "Net-(D365-PadA)") (class "Default")
      (node (ref "D365") (pin "A") (pinfunction "A_A") (pintype "passive"))
      (node (ref "R66") (pin "1") (pinfunction "1_1") (pintype "passive"))
      (node (ref "R69") (pin "1") (pinfunction "1_1") (pintype "passive"))
    )
    (net (code "130") (name "Net-(IC1-OUT)") (class "Default")
      (node (ref "IC1") (pin "5") (pinfunction "OUT_5") (pintype "output"))
      (node (ref "R21") (pin "1") (pinfunction "1_1") (pintype "passive"))
    )
    (net (code "131") (name "Net-(IC1-VDD)") (class "Default")
      (node (ref "C3") (pin "1") (pinfunction "1_1") (pintype "passive"))
      (node (ref "IC1") (pin "1") (pinfunction "VDD_1") (pintype "input"))
      (node (ref "R1") (pin "2") (pinfunction "2_2") (pintype "passive"))
    )
    (net (code "132") (name "Net-(IC2-OUT)") (class "Default")
      (node (ref "IC2") (pin "5") (pinfunction "OUT_5") (pintype "output"))
      (node (ref "R23") (pin "1") (pinfunction "1_1") (pintype "passive"))
    )
    (net (code "133") (name "Net-(IC2-VDD)") (class "Default")
      (node (ref "C5") (pin "1") (pinfunction "1_1") (pintype "passive"))
      (node (ref "IC2") (pin "1") (pinfunction "VDD_1") (pintype "input"))
      (node (ref "R9") (pin "2") (pinfunction "2_2") (pintype "passive"))
    )
    (net (code "134") (name "Net-(IC3A-+IN)") (class "Default")
      (node (ref "C11") (pin "2") (pinfunction "2_2") (pintype "passive"))
      (node (ref "IC3") (pin "3") (pinfunction "+IN_3") (pintype "input"))
      (node (ref "IC3") (pin "5") (pinfunction "+IN_5") (pintype "input"))
      (node (ref "IC4") (pin "3") (pinfunction "+IN_3") (pintype "input"))
      (node (ref "IC4") (pin "5") (pinfunction "+IN_5") (pintype "input"))
      (node (ref "IC5") (pin "3") (pinfunction "+IN_3") (pintype "input"))
      (node (ref "IC5") (pin "5") (pinfunction "+IN_5") (pintype "input"))
      (node (ref "R17") (pin "1") (pinfunction "1_1") (pintype "passive"))
      (node (ref "R18") (pin "2") (pinfunction "2_2") (pintype "passive"))
    )
    (net (code "135") (name "Net-(IC3A--IN)") (class "Default")
      (node (ref "C6") (pin "1") (pinfunction "1_1") (pintype "passive"))
      (node (ref "IC3") (pin "2") (pinfunction "-IN_2") (pintype "input"))
      (node (ref "R10") (pin "2") (pinfunction "2_2") (pintype "passive"))
    )
    (net (code "136") (name "Net-(IC3A-OUT)") (class "Default")
      (node (ref "IC3") (pin "1") (pinfunction "OUT_1") (pintype "output"))
      (node (ref "IC3") (pin "7") (pinfunction "OUT_7") (pintype "output"))
      (node (ref "IC4") (pin "1") (pinfunction "OUT_1") (pintype "output"))
      (node (ref "IC5") (pin "1") (pinfunction "OUT_1") (pintype "output"))
      (node (ref "IC5") (pin "7") (pinfunction "OUT_7") (pintype "output"))
      (node (ref "R24") (pin "1") (pinfunction "1_1") (pintype "passive"))
    )
    (net (code "137") (name "Net-(IC3B--IN)") (class "Default")
      (node (ref "C7") (pin "1") (pinfunction "1_1") (pintype "passive"))
      (node (ref "IC3") (pin "6") (pinfunction "-IN_6") (pintype "input"))
      (node (ref "R11") (pin "2") (pinfunction "2_2") (pintype "passive"))
    )
    (net (code "138") (name "Net-(IC3C-VCC)") (class "Default")
      (node (ref "C17") (pin "1") (pinfunction "1_1") (pintype "passive"))
      (node (ref "IC3") (pin "8") (pinfunction "VCC_8") (pintype "input"))
      (node (ref "R26") (pin "1") (pinfunction "1_1") (pintype "passive"))
    )
    (net (code "139") (name "Net-(IC4A--IN)") (class "Default")
      (node (ref "C8") (pin "1") (pinfunction "1_1") (pintype "passive"))
      (node (ref "IC4") (pin "2") (pinfunction "-IN_2") (pintype "input"))
      (node (ref "R12") (pin "2") (pinfunction "2_2") (pintype "passive"))
    )
    (net (code "140") (name "Net-(IC4C-VCC)") (class "Default")
      (node (ref "C18") (pin "1") (pinfunction "1_1") (pintype "passive"))
      (node (ref "IC4") (pin "8") (pinfunction "VCC_8") (pintype "input"))
      (node (ref "R27") (pin "1") (pinfunction "1_1") (pintype "passive"))
    )
    (net (code "141") (name "Net-(IC5A--IN)") (class "Default")
      (node (ref "C9") (pin "1") (pinfunction "1_1") (pintype "passive"))
      (node (ref "IC5") (pin "2") (pinfunction "-IN_2") (pintype "input"))
      (node (ref "R13") (pin "2") (pinfunction "2_2") (pintype "passive"))
    )
    (net (code "142") (name "Net-(IC5C-VCC)") (class "Default")
      (node (ref "C19") (pin "1") (pinfunction "1_1") (pintype "passive"))
      (node (ref "IC5") (pin "8") (pinfunction "VCC_8") (pintype "input"))
      (node (ref "R28") (pin "1") (pinfunction "1_1") (pintype "passive"))
    )
    (net (code "143") (name "Net-(IC7-AVDD)") (class "Default")
      (node (ref "C57") (pin "1") (pinfunction "1_1") (pintype "passive"))
      (node (ref "C58") (pin "1") (pinfunction "1_1") (pintype "passive"))
      (node (ref "IC7") (pin "1") (pinfunction "AVDDVCSEL_1") (pintype "input"))
      (node (ref "IC7") (pin "11") (pinfunction "AVDD_11") (pintype "input"))
      (node (ref "R19") (pin "2") (pinfunction "2_2") (pintype "passive"))
      (node (ref "R2") (pin "2") (pinfunction "2_2") (pintype "passive"))
    )
    (net (code "144") (name "Net-(IC7-SCL)") (class "Default")
      (node (ref "IC7") (pin "10") (pinfunction "SCL_10") (pintype "input"))
      (node (ref "R32") (pin "1") (pinfunction "1_1") (pintype "passive"))
    )
    (net (code "145") (name "Net-(IC7-SDA)") (class "Default")
      (node (ref "IC7") (pin "9") (pinfunction "SDA_9") (pintype "open_collector"))
      (node (ref "R30") (pin "1") (pinfunction "1_1") (pintype "passive"))
    )
    (net (code "146") (name "Net-(IC7-XSHUT)") (class "Default")
      (node (ref "IC7") (pin "5") (pinfunction "XSHUT_5") (pintype "input"))
      (node (ref "R2") (pin "1") (pinfunction "1_1") (pintype "passive"))
    )
    (net (code "147") (name "Net-(IC8-OUT)") (class "Default")
      (node (ref "IC8") (pin "5") (pinfunction "OUT_5") (pintype "output"))
      (node (ref "R54") (pin "1") (pinfunction "1_1") (pintype "passive"))
      (node (ref "TP5") (pin "TP") (pinfunction "TP_TP") (pintype "input"))
    )
    (net (code "148") (name "Net-(IC8-VDD)") (class "Default")
      (node (ref "C24") (pin "1") (pinfunction "1_1") (pintype "passive"))
      (node (ref "IC8") (pin "1") (pinfunction "VDD_1") (pintype "input"))
      (node (ref "R38") (pin "2") (pinfunction "2_2") (pintype "passive"))
    )
    (net (code "149") (name "Net-(IC9A-Q)") (class "Default")
      (node (ref "IC9") (pin "5") (pinfunction "Q_5") (pintype "output"))
      (node (ref "R55") (pin "1") (pinfunction "1_1") (pintype "passive"))
    )
    (net (code "150") (name "Net-(IC9A-~{PRE})") (class "Default")
      (node (ref "C23") (pin "1") (pinfunction "1_1") (pintype "passive"))
      (node (ref "IC9") (pin "4") (pinfunction "~{PRE}_4") (pintype "input"))
      (node (ref "R37") (pin "2") (pinfunction "2_2") (pintype "passive"))
      (node (ref "R40") (pin "1") (pinfunction "1_1") (pintype "passive"))
    )
    (net (code "151") (name "Net-(IC9A-~{Q})") (class "Default")
      (node (ref "IC9") (pin "6") (pinfunction "~{Q}_6") (pintype "output"))
      (node (ref "R56") (pin "1") (pinfunction "1_1") (pintype "passive"))
    )
    (net (code "152") (name "Net-(IC9C-VCC)") (class "Default")
      (node (ref "C34") (pin "1") (pinfunction "1_1") (pintype "passive"))
      (node (ref "IC9") (pin "16") (pinfunction "VCC_16") (pintype "input"))
      (node (ref "R76") (pin "1") (pinfunction "1_1") (pintype "passive"))
    )
    (net (code "153") (name "Net-(IC10-OUT)") (class "Default")
      (node (ref "IC10") (pin "5") (pinfunction "OUT_5") (pintype "output"))
      (node (ref "R59") (pin "1") (pinfunction "1_1") (pintype "passive"))
    )
    (net (code "154") (name "Net-(IC10-VDD)") (class "Default")
      (node (ref "C26") (pin "1") (pinfunction "1_1") (pintype "passive"))
      (node (ref "IC10") (pin "1") (pinfunction "VDD_1") (pintype "input"))
      (node (ref "R44") (pin "2") (pinfunction "2_2") (pintype "passive"))
    )
    (net (code "155") (name "Net-(IC11A-+IN)") (class "Default")
      (node (ref "IC11") (pin "3") (pinfunction "+IN_3") (pintype "input"))
      (node (ref "R63") (pin "2") (pinfunction "2_2") (pintype "passive"))
      (node (ref "R65") (pin "2") (pinfunction "2_2") (pintype "passive"))
    )
    (net (code "156") (name "Net-(IC11A--IN)") (class "Default")
      (node (ref "C31") (pin "1") (pinfunction "1_1") (pintype "passive"))
      (node (ref "IC11") (pin "2") (pinfunction "-IN_2") (pintype "input"))
      (node (ref "R61") (pin "2") (pinfunction "2_2") (pintype "passive"))
      (node (ref "R68") (pin "1") (pinfunction "1_1") (pintype "passive"))
      (node (ref "R86") (pin "2") (pinfunction "2_2") (pintype "passive"))
    )
    (net (code "157") (name "Net-(IC11B-+IN)") (class "Default")
      (node (ref "IC11") (pin "5") (pinfunction "+IN_5") (pintype "input"))
      (node (ref "R42") (pin "2") (pinfunction "2_2") (pintype "passive"))
      (node (ref "R45") (pin "2") (pinfunction "2_2") (pintype "passive"))
    )
    (net (code "158") (name "Net-(IC11B--IN)") (class "Default")
      (node (ref "IC11") (pin "6") (pinfunction "-IN_6") (pintype "input"))
      (node (ref "R41") (pin "2") (pinfunction "2_2") (pintype "passive"))
      (node (ref "R48") (pin "1") (pinfunction "1_1") (pintype "passive"))
      (node (ref "R85") (pin "2") (pinfunction "2_2") (pintype "passive"))
    )
    (net (code "159") (name "Net-(IC11B-OUT)") (class "Default")
      (node (ref "IC11") (pin "7") (pinfunction "OUT_7") (pintype "output"))
      (node (ref "R48") (pin "2") (pinfunction "2_2") (pintype "passive"))
      (node (ref "R58") (pin "1") (pinfunction "1_1") (pintype "passive"))
    )
    (net (code "160") (name "Net-(IC11C-VCC)") (class "Default")
      (node (ref "C35") (pin "1") (pinfunction "1_1") (pintype "passive"))
      (node (ref "IC11") (pin "8") (pinfunction "VCC_8") (pintype "input"))
      (node (ref "R74") (pin "1") (pinfunction "1_1") (pintype "passive"))
    )
    (net (code "161") (name "Net-(IC13-OUT)") (class "Default")
      (node (ref "IC13") (pin "5") (pinfunction "OUT_5") (pintype "output"))
      (node (ref "R80") (pin "1") (pinfunction "1_1") (pintype "passive"))
      (node (ref "TP18") (pin "TP") (pinfunction "TP_TP") (pintype "input"))
    )
    (net (code "162") (name "Net-(IC13-VDD)") (class "Default")
      (node (ref "C38") (pin "1") (pinfunction "1_1") (pintype "passive"))
      (node (ref "IC13") (pin "1") (pinfunction "VDD_1") (pintype "input"))
      (node (ref "R78") (pin "2") (pinfunction "2_2") (pintype "passive"))
    )
    (net (code "163") (name "Net-(IC15-SCL)") (class "Default")
      (node (ref "IC15") (pin "2") (pinfunction "SCL_2") (pintype "input"))
      (node (ref "IC24") (pin "1") (pinfunction "SCL_1") (pintype "input"))
      (node (ref "R82") (pin "1") (pinfunction "1_1") (pintype "passive"))
    )
    (net (code "164") (name "Net-(IC15-SDA)") (class "Default")
      (node (ref "IC15") (pin "1") (pinfunction "SDA_1") (pintype "open_collector"))
      (node (ref "IC24") (pin "6") (pinfunction "SDA_6") (pintype "open_collector"))
      (node (ref "R81") (pin "1") (pinfunction "1_1") (pintype "passive"))
    )
    (net (code "165") (name "Net-(IC15-VCC)") (class "Default")
      (node (ref "C40") (pin "1") (pinfunction "1_1") (pintype "passive"))
      (node (ref "IC15") (pin "8") (pinfunction "VCC_8") (pintype "input"))
      (node (ref "IC24") (pin "5") (pinfunction "V+_5") (pintype "input"))
      (node (ref "R79") (pin "1") (pinfunction "1_1") (pintype "passive"))
    )
    (net (code "166") (name "Net-(IC23-A0)") (class "Default")
      (node (ref "IC23") (pin "15") (pinfunction "A0_15") (pintype "input"))
      (node (ref "R50") (pin "2") (pinfunction "2_2") (pintype "passive"))
    )
    (net (code "167") (name "Net-(IC23-DA)") (class "Default")
      (node (ref "IC23") (pin "6") (pinfunction "DA_6") (pintype "passive"))
      (node (ref "R51") (pin "2") (pinfunction "2_2") (pintype "passive"))
    )
    (net (code "168") (name "Net-(IC25-DNC1)") (class "Default")
      (node (ref "IC25") (pin "4") (pinfunction "DNC1_4") (pintype "output"))
      (node (ref "R70") (pin "2") (pinfunction "2_2") (pintype "passive"))
    )
    (net (code "169") (name "Net-(IC25-SCL)") (class "Default")
      (node (ref "IC25") (pin "5") (pinfunction "SCL_5") (pintype "bidirectional"))
      (node (ref "R39") (pin "1") (pinfunction "1_1") (pintype "passive"))
    )
    (net (code "170") (name "Net-(IC25-SDA)") (class "Default")
      (node (ref "IC25") (pin "6") (pinfunction "SDA_6") (pintype "bidirectional"))
      (node (ref "R33") (pin "1") (pinfunction "1_1") (pintype "passive"))
    )
    (net (code "171") (name "Net-(IC25-TEST)") (class "Default")
      (node (ref "IC25") (pin "1") (pinfunction "TEST_1") (pintype "input"))
      (node (ref "R49") (pin "2") (pinfunction "2_2") (pintype "passive"))
      (node (ref "R71") (pin "1") (pinfunction "1_1") (pintype "passive"))
    )
    (net (code "172") (name "Net-(IC25-VCC)") (class "Default")
      (node (ref "C59") (pin "1") (pinfunction "1_1") (pintype "passive"))
      (node (ref "IC25") (pin "2") (pinfunction "VCC_2") (pintype "input"))
      (node (ref "R71") (pin "2") (pinfunction "2_2") (pintype "passive"))
      (node (ref "R72") (pin "2") (pinfunction "2_2") (pintype "passive"))
    )
    (net (code "173") (name "Net-(IC100-DOUT)") (class "Default")
      (node (ref "IC100") (pin "3") (pinfunction "DOUT_3") (pintype "output"))
      (node (ref "IC101") (pin "1") (pinfunction "DIN_1") (pintype "input"))
    )
    (net (code "174") (name "Net-(IC101-DOUT)") (class "Default")
      (node (ref "IC101") (pin "3") (pinfunction "DOUT_3") (pintype "output"))
      (node (ref "IC102") (pin "1") (pinfunction "DIN_1") (pintype "input"))
    )
    (net (code "175") (name "Net-(IC102-DOUT)") (class "Default")
      (node (ref "IC102") (pin "3") (pinfunction "DOUT_3") (pintype "output"))
      (node (ref "IC103") (pin "1") (pinfunction "DIN_1") (pintype "input"))
    )
    (net (code "176") (name "Net-(IC103-DOUT)") (class "Default")
      (node (ref "IC103") (pin "3") (pinfunction "DOUT_3") (pintype "output"))
      (node (ref "IC104") (pin "1") (pinfunction "DIN_1") (pintype "input"))
    )
    (net (code "177") (name "Net-(IC105-DOUT)") (class "Default")
      (node (ref "IC105") (pin "3") (pinfunction "DOUT_3") (pintype "output"))
      (node (ref "IC106") (pin "1") (pinfunction "DIN_1") (pintype "input"))
    )
    (net (code "178") (name "Net-(IC106-DOUT)") (class "Default")
      (node (ref "IC106") (pin "3") (pinfunction "DOUT_3") (pintype "output"))
      (node (ref "IC107") (pin "1") (pinfunction "DIN_1") (pintype "input"))
    )
    (net (code "179") (name "Net-(IC107-DOUT)") (class "Default")
      (node (ref "IC107") (pin "3") (pinfunction "DOUT_3") (pintype "output"))
      (node (ref "IC108") (pin "1") (pinfunction "DIN_1") (pintype "input"))
    )
    (net (code "180") (name "Net-(IC108-DOUT)") (class "Default")
      (node (ref "IC108") (pin "3") (pinfunction "DOUT_3") (pintype "output"))
      (node (ref "IC109") (pin "1") (pinfunction "DIN_1") (pintype "input"))
    )
    (net (code "181") (name "Net-(IC110-DOUT)") (class "Default")
      (node (ref "IC110") (pin "3") (pinfunction "DOUT_3") (pintype "output"))
      (node (ref "IC111") (pin "1") (pinfunction "DIN_1") (pintype "input"))
    )
    (net (code "182") (name "Net-(IC111-DOUT)") (class "Default")
      (node (ref "IC111") (pin "3") (pinfunction "DOUT_3") (pintype "output"))
      (node (ref "IC112") (pin "1") (pinfunction "DIN_1") (pintype "input"))
    )
    (net (code "183") (name "Net-(IC112-DOUT)") (class "Default")
      (node (ref "IC112") (pin "3") (pinfunction "DOUT_3") (pintype "output"))
      (node (ref "IC113") (pin "1") (pinfunction "DIN_1") (pintype "input"))
    )
    (net (code "184") (name "Net-(IC113-DOUT)") (class "Default")
      (node (ref "IC113") (pin "3") (pinfunction "DOUT_3") (pintype "output"))
      (node (ref "IC114") (pin "1") (pinfunction "DIN_1") (pintype "input"))
    )
    (net (code "185") (name "Net-(IC115-DOUT)") (class "Default")
      (node (ref "IC115") (pin "3") (pinfunction "DOUT_3") (pintype "output"))
      (node (ref "IC116") (pin "1") (pinfunction "DIN_1") (pintype "input"))
    )
    (net (code "186") (name "Net-(IC116-DOUT)") (class "Default")
      (node (ref "IC116") (pin "3") (pinfunction "DOUT_3") (pintype "output"))
      (node (ref "IC117") (pin "1") (pinfunction "DIN_1") (pintype "input"))
    )
    (net (code "187") (name "Net-(IC117-DOUT)") (class "Default")
      (node (ref "IC117") (pin "3") (pinfunction "DOUT_3") (pintype "output"))
      (node (ref "IC118") (pin "1") (pinfunction "DIN_1") (pintype "input"))
    )
    (net (code "188") (name "Net-(IC118-DOUT)") (class "Default")
      (node (ref "IC118") (pin "3") (pinfunction "DOUT_3") (pintype "output"))
      (node (ref "IC119") (pin "1") (pinfunction "DIN_1") (pintype "input"))
    )
    (net (code "189") (name "Net-(IC120-DOUT)") (class "Default")
      (node (ref "IC120") (pin "3") (pinfunction "DOUT_3") (pintype "output"))
      (node (ref "IC121") (pin "1") (pinfunction "DIN_1") (pintype "input"))
    )
    (net (code "190") (name "Net-(IC121-DOUT)") (class "Default")
      (node (ref "IC121") (pin "3") (pinfunction "DOUT_3") (pintype "output"))
      (node (ref "IC122") (pin "1") (pinfunction "DIN_1") (pintype "input"))
    )
    (net (code "191") (name "Net-(IC122-DOUT)") (class "Default")
      (node (ref "IC122") (pin "3") (pinfunction "DOUT_3") (pintype "output"))
      (node (ref "IC123") (pin "1") (pinfunction "DIN_1") (pintype "input"))
    )
    (net (code "192") (name "Net-(IC123-DOUT)") (class "Default")
      (node (ref "IC123") (pin "3") (pinfunction "DOUT_3") (pintype "output"))
      (node (ref "IC124") (pin "1") (pinfunction "DIN_1") (pintype "input"))
    )
    (net (code "193") (name "Net-(IC125-DOUT)") (class "Default")
      (node (ref "IC125") (pin "3") (pinfunction "DOUT_3") (pintype "output"))
      (node (ref "IC126") (pin "1") (pinfunction "DIN_1") (pintype "input"))
    )
    (net (code "194") (name "Net-(IC126-DOUT)") (class "Default")
      (node (ref "IC126") (pin "3") (pinfunction "DOUT_3") (pintype "output"))
      (node (ref "IC127") (pin "1") (pinfunction "DIN_1") (pintype "input"))
    )
    (net (code "195") (name "Net-(IC127-DOUT)") (class "Default")
      (node (ref "IC127") (pin "3") (pinfunction "DOUT_3") (pintype "output"))
      (node (ref "IC128") (pin "1") (pinfunction "DIN_1") (pintype "input"))
    )
    (net (code "196") (name "Net-(IC128-DOUT)") (class "Default")
      (node (ref "IC128") (pin "3") (pinfunction "DOUT_3") (pintype "output"))
      (node (ref "IC129") (pin "1") (pinfunction "DIN_1") (pintype "input"))
    )
    (net (code "197") (name "Net-(IC130-DOUT)") (class "Default")
      (node (ref "IC130") (pin "3") (pinfunction "DOUT_3") (pintype "output"))
      (node (ref "IC131") (pin "1") (pinfunction "DIN_1") (pintype "input"))
    )
    (net (code "198") (name "Net-(IC131-DOUT)") (class "Default")
      (node (ref "IC131") (pin "3") (pinfunction "DOUT_3") (pintype "output"))
      (node (ref "IC132") (pin "1") (pinfunction "DIN_1") (pintype "input"))
    )
    (net (code "199") (name "Net-(IC132-DOUT)") (class "Default")
      (node (ref "IC132") (pin "3") (pinfunction "DOUT_3") (pintype "output"))
      (node (ref "IC133") (pin "1") (pinfunction "DIN_1") (pintype "input"))
    )
    (net (code "200") (name "Net-(IC133-DOUT)") (class "Default")
      (node (ref "IC133") (pin "3") (pinfunction "DOUT_3") (pintype "output"))
      (node (ref "IC134") (pin "1") (pinfunction "DIN_1") (pintype "input"))
    )
    (net (code "201") (name "Net-(IC135-DOUT)") (class "Default")
      (node (ref "IC135") (pin "3") (pinfunction "DOUT_3") (pintype "output"))
      (node (ref "IC136") (pin "1") (pinfunction "DIN_1") (pintype "input"))
    )
    (net (code "202") (name "Net-(IC136-DOUT)") (class "Default")
      (node (ref "IC136") (pin "3") (pinfunction "DOUT_3") (pintype "output"))
      (node (ref "IC137") (pin "1") (pinfunction "DIN_1") (pintype "input"))
    )
    (net (code "203") (name "Net-(IC137-DOUT)") (class "Default")
      (node (ref "IC137") (pin "3") (pinfunction "DOUT_3") (pintype "output"))
      (node (ref "IC138") (pin "1") (pinfunction "DIN_1") (pintype "input"))
    )
    (net (code "204") (name "Net-(IC138-DOUT)") (class "Default")
      (node (ref "IC138") (pin "3") (pinfunction "DOUT_3") (pintype "output"))
      (node (ref "IC139") (pin "1") (pinfunction "DIN_1") (pintype "input"))
    )
    (net (code "205") (name "Net-(IC140-DOUT)") (class "Default")
      (node (ref "IC140") (pin "3") (pinfunction "DOUT_3") (pintype "output"))
      (node (ref "IC141") (pin "1") (pinfunction "DIN_1") (pintype "input"))
    )
    (net (code "206") (name "Net-(IC141-DOUT)") (class "Default")
      (node (ref "IC141") (pin "3") (pinfunction "DOUT_3") (pintype "output"))
      (node (ref "IC142") (pin "1") (pinfunction "DIN_1") (pintype "input"))
    )
    (net (code "207") (name "Net-(IC142-DOUT)") (class "Default")
      (node (ref "IC142") (pin "3") (pinfunction "DOUT_3") (pintype "output"))
      (node (ref "IC143") (pin "1") (pinfunction "DIN_1") (pintype "input"))
    )
    (net (code "208") (name "Net-(IC143-DOUT)") (class "Default")
      (node (ref "IC143") (pin "3") (pinfunction "DOUT_3") (pintype "output"))
      (node (ref "IC144") (pin "1") (pinfunction "DIN_1") (pintype "input"))
    )
    (net (code "209") (name "Net-(IC145-DOUT)") (class "Default")
      (node (ref "IC145") (pin "3") (pinfunction "DOUT_3") (pintype "output"))
      (node (ref "IC146") (pin "1") (pinfunction "DIN_1") (pintype "input"))
    )
    (net (code "210") (name "Net-(IC146-DOUT)") (class "Default")
      (node (ref "IC146") (pin "3") (pinfunction "DOUT_3") (pintype "output"))
      (node (ref "IC147") (pin "1") (pinfunction "DIN_1") (pintype "input"))
    )
    (net (code "211") (name "Net-(IC147-DOUT)") (class "Default")
      (node (ref "IC147") (pin "3") (pinfunction "DOUT_3") (pintype "output"))
      (node (ref "IC148") (pin "1") (pinfunction "DIN_1") (pintype "input"))
    )
    (net (code "212") (name "Net-(IC148-DOUT)") (class "Default")
      (node (ref "IC148") (pin "3") (pinfunction "DOUT_3") (pintype "output"))
      (node (ref "IC149") (pin "1") (pinfunction "DIN_1") (pintype "input"))
    )
    (net (code "213") (name "Net-(IC150-DOUT)") (class "Default")
      (node (ref "IC150") (pin "3") (pinfunction "DOUT_3") (pintype "output"))
      (node (ref "IC151") (pin "1") (pinfunction "DIN_1") (pintype "input"))
    )
    (net (code "214") (name "Net-(IC151-DOUT)") (class "Default")
      (node (ref "IC151") (pin "3") (pinfunction "DOUT_3") (pintype "output"))
      (node (ref "IC152") (pin "1") (pinfunction "DIN_1") (pintype "input"))
    )
    (net (code "215") (name "Net-(IC152-DOUT)") (class "Default")
      (node (ref "IC152") (pin "3") (pinfunction "DOUT_3") (pintype "output"))
      (node (ref "IC153") (pin "1") (pinfunction "DIN_1") (pintype "input"))
    )
    (net (code "216") (name "Net-(IC153-DOUT)") (class "Default")
      (node (ref "IC153") (pin "3") (pinfunction "DOUT_3") (pintype "output"))
      (node (ref "IC154") (pin "1") (pinfunction "DIN_1") (pintype "input"))
    )
    (net (code "217") (name "Net-(IC156-DOUT)") (class "Default")
      (node (ref "IC156") (pin "3") (pinfunction "DOUT_3") (pintype "output"))
      (node (ref "IC157") (pin "1") (pinfunction "DIN_1") (pintype "input"))
    )
    (net (code "218") (name "Net-(IC157-DOUT)") (class "Default")
      (node (ref "IC157") (pin "3") (pinfunction "DOUT_3") (pintype "output"))
      (node (ref "IC158") (pin "1") (pinfunction "DIN_1") (pintype "input"))
    )
    (net (code "219") (name "Net-(IC158-DOUT)") (class "Default")
      (node (ref "IC158") (pin "3") (pinfunction "DOUT_3") (pintype "output"))
      (node (ref "IC159") (pin "1") (pinfunction "DIN_1") (pintype "input"))
    )
    (net (code "220") (name "Net-(IC159-DOUT)") (class "Default")
      (node (ref "IC159") (pin "3") (pinfunction "DOUT_3") (pintype "output"))
      (node (ref "IC160") (pin "1") (pinfunction "DIN_1") (pintype "input"))
    )
    (net (code "221") (name "Net-(IC161-DOUT)") (class "Default")
      (node (ref "IC161") (pin "3") (pinfunction "DOUT_3") (pintype "output"))
      (node (ref "IC162") (pin "1") (pinfunction "DIN_1") (pintype "input"))
    )
    (net (code "222") (name "Net-(IC162-DOUT)") (class "Default")
      (node (ref "IC162") (pin "3") (pinfunction "DOUT_3") (pintype "output"))
      (node (ref "IC163") (pin "1") (pinfunction "DIN_1") (pintype "input"))
    )
    (net (code "223") (name "Net-(IC163-DOUT)") (class "Default")
      (node (ref "IC163") (pin "3") (pinfunction "DOUT_3") (pintype "output"))
      (node (ref "IC164") (pin "1") (pinfunction "DIN_1") (pintype "input"))
    )
    (net (code "224") (name "Net-(IC164-DOUT)") (class "Default")
      (node (ref "IC164") (pin "3") (pinfunction "DOUT_3") (pintype "output"))
      (node (ref "IC165") (pin "1") (pinfunction "DIN_1") (pintype "input"))
    )
    (net (code "225") (name "Net-(IC166-DOUT)") (class "Default")
      (node (ref "IC166") (pin "3") (pinfunction "DOUT_3") (pintype "output"))
      (node (ref "IC167") (pin "1") (pinfunction "DIN_1") (pintype "input"))
    )
    (net (code "226") (name "Net-(IC167-DOUT)") (class "Default")
      (node (ref "IC167") (pin "3") (pinfunction "DOUT_3") (pintype "output"))
      (node (ref "IC168") (pin "1") (pinfunction "DIN_1") (pintype "input"))
    )
    (net (code "227") (name "Net-(IC168-DOUT)") (class "Default")
      (node (ref "IC168") (pin "3") (pinfunction "DOUT_3") (pintype "output"))
      (node (ref "IC169") (pin "1") (pinfunction "DIN_1") (pintype "input"))
    )
    (net (code "228") (name "Net-(IC169-DOUT)") (class "Default")
      (node (ref "IC169") (pin "3") (pinfunction "DOUT_3") (pintype "output"))
      (node (ref "IC170") (pin "1") (pinfunction "DIN_1") (pintype "input"))
    )
    (net (code "229") (name "Net-(IC171-DOUT)") (class "Default")
      (node (ref "IC171") (pin "3") (pinfunction "DOUT_3") (pintype "output"))
      (node (ref "IC172") (pin "1") (pinfunction "DIN_1") (pintype "input"))
    )
    (net (code "230") (name "Net-(IC172-DOUT)") (class "Default")
      (node (ref "IC172") (pin "3") (pinfunction "DOUT_3") (pintype "output"))
      (node (ref "IC173") (pin "1") (pinfunction "DIN_1") (pintype "input"))
    )
    (net (code "231") (name "Net-(IC173-DOUT)") (class "Default")
      (node (ref "IC173") (pin "3") (pinfunction "DOUT_3") (pintype "output"))
      (node (ref "IC174") (pin "1") (pinfunction "DIN_1") (pintype "input"))
    )
    (net (code "232") (name "Net-(IC174-DOUT)") (class "Default")
      (node (ref "IC174") (pin "3") (pinfunction "DOUT_3") (pintype "output"))
      (node (ref "IC175") (pin "1") (pinfunction "DIN_1") (pintype "input"))
    )
    (net (code "233") (name "Net-(IC176-DOUT)") (class "Default")
      (node (ref "IC176") (pin "3") (pinfunction "DOUT_3") (pintype "output"))
      (node (ref "IC177") (pin "1") (pinfunction "DIN_1") (pintype "input"))
    )
    (net (code "234") (name "Net-(IC177-DOUT)") (class "Default")
      (node (ref "IC177") (pin "3") (pinfunction "DOUT_3") (pintype "output"))
      (node (ref "IC178") (pin "1") (pinfunction "DIN_1") (pintype "input"))
    )
    (net (code "235") (name "Net-(IC178-DOUT)") (class "Default")
      (node (ref "IC178") (pin "3") (pinfunction "DOUT_3") (pintype "output"))
      (node (ref "IC179") (pin "1") (pinfunction "DIN_1") (pintype "input"))
    )
    (net (code "236") (name "Net-(IC179-DOUT)") (class "Default")
      (node (ref "IC179") (pin "3") (pinfunction "DOUT_3") (pintype "output"))
      (node (ref "IC180") (pin "1") (pinfunction "DIN_1") (pintype "input"))
    )
    (net (code "237") (name "Net-(IC181-DOUT)") (class "Default")
      (node (ref "IC181") (pin "3") (pinfunction "DOUT_3") (pintype "output"))
      (node (ref "IC182") (pin "1") (pinfunction "DIN_1") (pintype "input"))
    )
    (net (code "238") (name "Net-(IC182-DOUT)") (class "Default")
      (node (ref "IC182") (pin "3") (pinfunction "DOUT_3") (pintype "output"))
      (node (ref "IC183") (pin "1") (pinfunction "DIN_1") (pintype "input"))
    )
    (net (code "239") (name "Net-(IC183-DOUT)") (class "Default")
      (node (ref "IC183") (pin "3") (pinfunction "DOUT_3") (pintype "output"))
      (node (ref "IC184") (pin "1") (pinfunction "DIN_1") (pintype "input"))
    )
    (net (code "240") (name "Net-(IC184-DOUT)") (class "Default")
      (node (ref "IC184") (pin "3") (pinfunction "DOUT_3") (pintype "output"))
      (node (ref "IC185") (pin "1") (pinfunction "DIN_1") (pintype "input"))
    )
    (net (code "241") (name "Net-(IC186-DOUT)") (class "Default")
      (node (ref "IC186") (pin "3") (pinfunction "DOUT_3") (pintype "output"))
      (node (ref "IC187") (pin "1") (pinfunction "DIN_1") (pintype "input"))
    )
    (net (code "242") (name "Net-(IC187-DOUT)") (class "Default")
      (node (ref "IC187") (pin "3") (pinfunction "DOUT_3") (pintype "output"))
      (node (ref "IC188") (pin "1") (pinfunction "DIN_1") (pintype "input"))
    )
    (net (code "243") (name "Net-(IC188-DOUT)") (class "Default")
      (node (ref "IC188") (pin "3") (pinfunction "DOUT_3") (pintype "output"))
      (node (ref "IC189") (pin "1") (pinfunction "DIN_1") (pintype "input"))
    )
    (net (code "244") (name "Net-(IC189-DOUT)") (class "Default")
      (node (ref "IC189") (pin "3") (pinfunction "DOUT_3") (pintype "output"))
      (node (ref "IC190") (pin "1") (pinfunction "DIN_1") (pintype "input"))
    )
    (net (code "245") (name "Net-(IC191-DOUT)") (class "Default")
      (node (ref "IC191") (pin "3") (pinfunction "DOUT_3") (pintype "output"))
      (node (ref "IC192") (pin "1") (pinfunction "DIN_1") (pintype "input"))
    )
    (net (code "246") (name "Net-(IC192-DOUT)") (class "Default")
      (node (ref "IC192") (pin "3") (pinfunction "DOUT_3") (pintype "output"))
      (node (ref "IC193") (pin "1") (pinfunction "DIN_1") (pintype "input"))
    )
    (net (code "247") (name "Net-(IC193-DOUT)") (class "Default")
      (node (ref "IC193") (pin "3") (pinfunction "DOUT_3") (pintype "output"))
      (node (ref "IC194") (pin "1") (pinfunction "DIN_1") (pintype "input"))
    )
    (net (code "248") (name "Net-(IC194-DOUT)") (class "Default")
      (node (ref "IC194") (pin "3") (pinfunction "DOUT_3") (pintype "output"))
      (node (ref "IC195") (pin "1") (pinfunction "DIN_1") (pintype "input"))
    )
    (net (code "249") (name "Net-(IC196-DOUT)") (class "Default")
      (node (ref "IC196") (pin "3") (pinfunction "DOUT_3") (pintype "output"))
      (node (ref "IC197") (pin "1") (pinfunction "DIN_1") (pintype "input"))
    )
    (net (code "250") (name "Net-(IC197-DOUT)") (class "Default")
      (node (ref "IC197") (pin "3") (pinfunction "DOUT_3") (pintype "output"))
      (node (ref "IC198") (pin "1") (pinfunction "DIN_1") (pintype "input"))
    )
    (net (code "251") (name "Net-(IC198-DOUT)") (class "Default")
      (node (ref "IC198") (pin "3") (pinfunction "DOUT_3") (pintype "output"))
      (node (ref "IC199") (pin "1") (pinfunction "DIN_1") (pintype "input"))
    )
    (net (code "252") (name "Net-(IC199-DOUT)") (class "Default")
      (node (ref "IC199") (pin "3") (pinfunction "DOUT_3") (pintype "output"))
      (node (ref "IC200") (pin "1") (pinfunction "DIN_1") (pintype "input"))
    )
    (net (code "253") (name "Net-(IC201-DOUT)") (class "Default")
      (node (ref "IC201") (pin "3") (pinfunction "DOUT_3") (pintype "output"))
      (node (ref "IC202") (pin "1") (pinfunction "DIN_1") (pintype "input"))
    )
    (net (code "254") (name "Net-(IC202-DOUT)") (class "Default")
      (node (ref "IC202") (pin "3") (pinfunction "DOUT_3") (pintype "output"))
      (node (ref "IC203") (pin "1") (pinfunction "DIN_1") (pintype "input"))
    )
    (net (code "255") (name "Net-(IC203-DOUT)") (class "Default")
      (node (ref "IC203") (pin "3") (pinfunction "DOUT_3") (pintype "output"))
      (node (ref "IC204") (pin "1") (pinfunction "DIN_1") (pintype "input"))
    )
    (net (code "256") (name "Net-(IC204-DOUT)") (class "Default")
      (node (ref "IC204") (pin "3") (pinfunction "DOUT_3") (pintype "output"))
      (node (ref "IC205") (pin "1") (pinfunction "DIN_1") (pintype "input"))
    )
    (net (code "257") (name "Net-(IC206-DOUT)") (class "Default")
      (node (ref "IC206") (pin "3") (pinfunction "DOUT_3") (pintype "output"))
      (node (ref "IC207") (pin "1") (pinfunction "DIN_1") (pintype "input"))
    )
    (net (code "258") (name "Net-(IC207-DOUT)") (class "Default")
      (node (ref "IC207") (pin "3") (pinfunction "DOUT_3") (pintype "output"))
      (node (ref "IC208") (pin "1") (pinfunction "DIN_1") (pintype "input"))
    )
    (net (code "259") (name "Net-(IC208-DOUT)") (class "Default")
      (node (ref "IC208") (pin "3") (pinfunction "DOUT_3") (pintype "output"))
      (node (ref "IC209") (pin "1") (pinfunction "DIN_1") (pintype "input"))
    )
    (net (code "260") (name "Net-(IC209-DOUT)") (class "Default")
      (node (ref "IC209") (pin "3") (pinfunction "DOUT_3") (pintype "output"))
      (node (ref "IC210") (pin "1") (pinfunction "DIN_1") (pintype "input"))
    )
    (net (code "261") (name "Net-(IC212-DOUT)") (class "Default")
      (node (ref "IC212") (pin "3") (pinfunction "DOUT_3") (pintype "output"))
      (node (ref "IC213") (pin "1") (pinfunction "DIN_1") (pintype "input"))
    )
    (net (code "262") (name "Net-(IC213-DOUT)") (class "Default")
      (node (ref "IC213") (pin "3") (pinfunction "DOUT_3") (pintype "output"))
      (node (ref "IC214") (pin "1") (pinfunction "DIN_1") (pintype "input"))
    )
    (net (code "263") (name "Net-(IC214-DOUT)") (class "Default")
      (node (ref "IC214") (pin "3") (pinfunction "DOUT_3") (pintype "output"))
      (node (ref "IC215") (pin "1") (pinfunction "DIN_1") (pintype "input"))
    )
    (net (code "264") (name "Net-(IC215-DOUT)") (class "Default")
      (node (ref "IC215") (pin "3") (pinfunction "DOUT_3") (pintype "output"))
      (node (ref "IC216") (pin "1") (pinfunction "DIN_1") (pintype "input"))
    )
    (net (code "265") (name "Net-(IC217-DOUT)") (class "Default")
      (node (ref "IC217") (pin "3") (pinfunction "DOUT_3") (pintype "output"))
      (node (ref "IC218") (pin "1") (pinfunction "DIN_1") (pintype "input"))
    )
    (net (code "266") (name "Net-(IC218-DOUT)") (class "Default")
      (node (ref "IC218") (pin "3") (pinfunction "DOUT_3") (pintype "output"))
      (node (ref "IC219") (pin "1") (pinfunction "DIN_1") (pintype "input"))
    )
    (net (code "267") (name "Net-(IC219-DOUT)") (class "Default")
      (node (ref "IC219") (pin "3") (pinfunction "DOUT_3") (pintype "output"))
      (node (ref "IC220") (pin "1") (pinfunction "DIN_1") (pintype "input"))
    )
    (net (code "268") (name "Net-(IC220-DOUT)") (class "Default")
      (node (ref "IC220") (pin "3") (pinfunction "DOUT_3") (pintype "output"))
      (node (ref "IC221") (pin "1") (pinfunction "DIN_1") (pintype "input"))
    )
    (net (code "269") (name "Net-(IC222-DOUT)") (class "Default")
      (node (ref "IC222") (pin "3") (pinfunction "DOUT_3") (pintype "output"))
      (node (ref "IC223") (pin "1") (pinfunction "DIN_1") (pintype "input"))
    )
    (net (code "270") (name "Net-(IC223-DOUT)") (class "Default")
      (node (ref "IC223") (pin "3") (pinfunction "DOUT_3") (pintype "output"))
      (node (ref "IC224") (pin "1") (pinfunction "DIN_1") (pintype "input"))
    )
    (net (code "271") (name "Net-(IC224-DOUT)") (class "Default")
      (node (ref "IC224") (pin "3") (pinfunction "DOUT_3") (pintype "output"))
      (node (ref "IC225") (pin "1") (pinfunction "DIN_1") (pintype "input"))
    )
    (net (code "272") (name "Net-(IC225-DOUT)") (class "Default")
      (node (ref "IC225") (pin "3") (pinfunction "DOUT_3") (pintype "output"))
      (node (ref "IC226") (pin "1") (pinfunction "DIN_1") (pintype "input"))
    )
    (net (code "273") (name "Net-(IC227-DOUT)") (class "Default")
      (node (ref "IC227") (pin "3") (pinfunction "DOUT_3") (pintype "output"))
      (node (ref "IC228") (pin "1") (pinfunction "DIN_1") (pintype "input"))
    )
    (net (code "274") (name "Net-(IC228-DOUT)") (class "Default")
      (node (ref "IC228") (pin "3") (pinfunction "DOUT_3") (pintype "output"))
      (node (ref "IC229") (pin "1") (pinfunction "DIN_1") (pintype "input"))
    )
    (net (code "275") (name "Net-(IC229-DOUT)") (class "Default")
      (node (ref "IC229") (pin "3") (pinfunction "DOUT_3") (pintype "output"))
      (node (ref "IC230") (pin "1") (pinfunction "DIN_1") (pintype "input"))
    )
    (net (code "276") (name "Net-(IC230-DOUT)") (class "Default")
      (node (ref "IC230") (pin "3") (pinfunction "DOUT_3") (pintype "output"))
      (node (ref "IC231") (pin "1") (pinfunction "DIN_1") (pintype "input"))
    )
    (net (code "277") (name "Net-(IC232-DOUT)") (class "Default")
      (node (ref "IC232") (pin "3") (pinfunction "DOUT_3") (pintype "output"))
      (node (ref "IC233") (pin "1") (pinfunction "DIN_1") (pintype "input"))
    )
    (net (code "278") (name "Net-(IC233-DOUT)") (class "Default")
      (node (ref "IC233") (pin "3") (pinfunction "DOUT_3") (pintype "output"))
      (node (ref "IC234") (pin "1") (pinfunction "DIN_1") (pintype "input"))
    )
    (net (code "279") (name "Net-(IC234-DOUT)") (class "Default")
      (node (ref "IC234") (pin "3") (pinfunction "DOUT_3") (pintype "output"))
      (node (ref "IC235") (pin "1") (pinfunction "DIN_1") (pintype "input"))
    )
    (net (code "280") (name "Net-(IC235-DOUT)") (class "Default")
      (node (ref "IC235") (pin "3") (pinfunction "DOUT_3") (pintype "output"))
      (node (ref "IC236") (pin "1") (pinfunction "DIN_1") (pintype "input"))
    )
    (net (code "281") (name "Net-(IC237-DOUT)") (class "Default")
      (node (ref "IC237") (pin "3") (pinfunction "DOUT_3") (pintype "output"))
      (node (ref "IC238") (pin "1") (pinfunction "DIN_1") (pintype "input"))
    )
    (net (code "282") (name "Net-(IC238-DOUT)") (class "Default")
      (node (ref "IC238") (pin "3") (pinfunction "DOUT_3") (pintype "output"))
      (node (ref "IC239") (pin "1") (pinfunction "DIN_1") (pintype "input"))
    )
    (net (code "283") (name "Net-(IC239-DOUT)") (class "Default")
      (node (ref "IC239") (pin "3") (pinfunction "DOUT_3") (pintype "output"))
      (node (ref "IC240") (pin "1") (pinfunction "DIN_1") (pintype "input"))
    )
    (net (code "284") (name "Net-(IC240-DOUT)") (class "Default")
      (node (ref "IC240") (pin "3") (pinfunction "DOUT_3") (pintype "output"))
      (node (ref "IC241") (pin "1") (pinfunction "DIN_1") (pintype "input"))
    )
    (net (code "285") (name "Net-(IC242-DOUT)") (class "Default")
      (node (ref "IC242") (pin "3") (pinfunction "DOUT_3") (pintype "output"))
      (node (ref "IC243") (pin "1") (pinfunction "DIN_1") (pintype "input"))
    )
    (net (code "286") (name "Net-(IC243-DOUT)") (class "Default")
      (node (ref "IC243") (pin "3") (pinfunction "DOUT_3") (pintype "output"))
      (node (ref "IC244") (pin "1") (pinfunction "DIN_1") (pintype "input"))
    )
    (net (code "287") (name "Net-(IC244-DOUT)") (class "Default")
      (node (ref "IC244") (pin "3") (pinfunction "DOUT_3") (pintype "output"))
      (node (ref "IC245") (pin "1") (pinfunction "DIN_1") (pintype "input"))
    )
    (net (code "288") (name "Net-(IC245-DOUT)") (class "Default")
      (node (ref "IC245") (pin "3") (pinfunction "DOUT_3") (pintype "output"))
      (node (ref "IC246") (pin "1") (pinfunction "DIN_1") (pintype "input"))
    )
    (net (code "289") (name "Net-(IC247-DOUT)") (class "Default")
      (node (ref "IC247") (pin "3") (pinfunction "DOUT_3") (pintype "output"))
      (node (ref "IC248") (pin "1") (pinfunction "DIN_1") (pintype "input"))
    )
    (net (code "290") (name "Net-(IC248-DOUT)") (class "Default")
      (node (ref "IC248") (pin "3") (pinfunction "DOUT_3") (pintype "output"))
      (node (ref "IC249") (pin "1") (pinfunction "DIN_1") (pintype "input"))
    )
    (net (code "291") (name "Net-(IC249-DOUT)") (class "Default")
      (node (ref "IC249") (pin "3") (pinfunction "DOUT_3") (pintype "output"))
      (node (ref "IC250") (pin "1") (pinfunction "DIN_1") (pintype "input"))
    )
    (net (code "292") (name "Net-(IC250-DOUT)") (class "Default")
      (node (ref "IC250") (pin "3") (pinfunction "DOUT_3") (pintype "output"))
      (node (ref "IC251") (pin "1") (pinfunction "DIN_1") (pintype "input"))
    )
    (net (code "293") (name "Net-(IC252-DOUT)") (class "Default")
      (node (ref "IC252") (pin "3") (pinfunction "DOUT_3") (pintype "output"))
      (node (ref "IC253") (pin "1") (pinfunction "DIN_1") (pintype "input"))
    )
    (net (code "294") (name "Net-(IC253-DOUT)") (class "Default")
      (node (ref "IC253") (pin "3") (pinfunction "DOUT_3") (pintype "output"))
      (node (ref "IC254") (pin "1") (pinfunction "DIN_1") (pintype "input"))
    )
    (net (code "295") (name "Net-(IC254-DOUT)") (class "Default")
      (node (ref "IC254") (pin "3") (pinfunction "DOUT_3") (pintype "output"))
      (node (ref "IC255") (pin "1") (pinfunction "DIN_1") (pintype "input"))
    )
    (net (code "296") (name "Net-(IC255-DOUT)") (class "Default")
      (node (ref "IC255") (pin "3") (pinfunction "DOUT_3") (pintype "output"))
      (node (ref "IC256") (pin "1") (pinfunction "DIN_1") (pintype "input"))
    )
    (net (code "297") (name "Net-(IC257-DOUT)") (class "Default")
      (node (ref "IC257") (pin "3") (pinfunction "DOUT_3") (pintype "output"))
      (node (ref "IC258") (pin "1") (pinfunction "DIN_1") (pintype "input"))
    )
    (net (code "298") (name "Net-(IC258-DOUT)") (class "Default")
      (node (ref "IC258") (pin "3") (pinfunction "DOUT_3") (pintype "output"))
      (node (ref "IC259") (pin "1") (pinfunction "DIN_1") (pintype "input"))
    )
    (net (code "299") (name "Net-(IC259-DOUT)") (class "Default")
      (node (ref "IC259") (pin "3") (pinfunction "DOUT_3") (pintype "output"))
      (node (ref "IC260") (pin "1") (pinfunction "DIN_1") (pintype "input"))
    )
    (net (code "300") (name "Net-(IC260-DOUT)") (class "Default")
      (node (ref "IC260") (pin "3") (pinfunction "DOUT_3") (pintype "output"))
      (node (ref "IC261") (pin "1") (pinfunction "DIN_1") (pintype "input"))
    )
    (net (code "301") (name "Net-(IC262-DOUT)") (class "Default")
      (node (ref "IC262") (pin "3") (pinfunction "DOUT_3") (pintype "output"))
      (node (ref "IC263") (pin "1") (pinfunction "DIN_1") (pintype "input"))
    )
    (net (code "302") (name "Net-(IC263-DOUT)") (class "Default")
      (node (ref "IC263") (pin "3") (pinfunction "DOUT_3") (pintype "output"))
      (node (ref "IC264") (pin "1") (pinfunction "DIN_1") (pintype "input"))
    )
    (net (code "303") (name "Net-(IC264-DOUT)") (class "Default")
      (node (ref "IC264") (pin "3") (pinfunction "DOUT_3") (pintype "output"))
      (node (ref "IC265") (pin "1") (pinfunction "DIN_1") (pintype "input"))
    )
    (net (code "304") (name "Net-(IC265-DOUT)") (class "Default")
      (node (ref "IC265") (pin "3") (pinfunction "DOUT_3") (pintype "output"))
      (node (ref "IC266") (pin "1") (pinfunction "DIN_1") (pintype "input"))
    )
    (net (code "305") (name "Net-(IC268-DOUT)") (class "Default")
      (node (ref "IC268") (pin "3") (pinfunction "DOUT_3") (pintype "output"))
      (node (ref "IC269") (pin "1") (pinfunction "DIN_1") (pintype "input"))
    )
    (net (code "306") (name "Net-(IC269-DOUT)") (class "Default")
      (node (ref "IC269") (pin "3") (pinfunction "DOUT_3") (pintype "output"))
      (node (ref "IC270") (pin "1") (pinfunction "DIN_1") (pintype "input"))
    )
    (net (code "307") (name "Net-(IC270-DOUT)") (class "Default")
      (node (ref "IC270") (pin "3") (pinfunction "DOUT_3") (pintype "output"))
      (node (ref "IC271") (pin "1") (pinfunction "DIN_1") (pintype "input"))
    )
    (net (code "308") (name "Net-(IC271-DOUT)") (class "Default")
      (node (ref "IC271") (pin "3") (pinfunction "DOUT_3") (pintype "output"))
      (node (ref "IC272") (pin "1") (pinfunction "DIN_1") (pintype "input"))
    )
    (net (code "309") (name "Net-(IC273-DOUT)") (class "Default")
      (node (ref "IC273") (pin "3") (pinfunction "DOUT_3") (pintype "output"))
      (node (ref "IC274") (pin "1") (pinfunction "DIN_1") (pintype "input"))
    )
    (net (code "310") (name "Net-(IC274-DOUT)") (class "Default")
      (node (ref "IC274") (pin "3") (pinfunction "DOUT_3") (pintype "output"))
      (node (ref "IC275") (pin "1") (pinfunction "DIN_1") (pintype "input"))
    )
    (net (code "311") (name "Net-(IC275-DOUT)") (class "Default")
      (node (ref "IC275") (pin "3") (pinfunction "DOUT_3") (pintype "output"))
      (node (ref "IC276") (pin "1") (pinfunction "DIN_1") (pintype "input"))
    )
    (net (code "312") (name "Net-(IC276-DOUT)") (class "Default")
      (node (ref "IC276") (pin "3") (pinfunction "DOUT_3") (pintype "output"))
      (node (ref "IC277") (pin "1") (pinfunction "DIN_1") (pintype "input"))
    )
    (net (code "313") (name "Net-(IC278-DOUT)") (class "Default")
      (node (ref "IC278") (pin "3") (pinfunction "DOUT_3") (pintype "output"))
      (node (ref "IC279") (pin "1") (pinfunction "DIN_1") (pintype "input"))
    )
    (net (code "314") (name "Net-(IC279-DOUT)") (class "Default")
      (node (ref "IC279") (pin "3") (pinfunction "DOUT_3") (pintype "output"))
      (node (ref "IC280") (pin "1") (pinfunction "DIN_1") (pintype "input"))
    )
    (net (code "315") (name "Net-(IC280-DOUT)") (class "Default")
      (node (ref "IC280") (pin "3") (pinfunction "DOUT_3") (pintype "output"))
      (node (ref "IC281") (pin "1") (pinfunction "DIN_1") (pintype "input"))
    )
    (net (code "316") (name "Net-(IC281-DOUT)") (class "Default")
      (node (ref "IC281") (pin "3") (pinfunction "DOUT_3") (pintype "output"))
      (node (ref "IC282") (pin "1") (pinfunction "DIN_1") (pintype "input"))
    )
    (net (code "317") (name "Net-(IC283-DOUT)") (class "Default")
      (node (ref "IC283") (pin "3") (pinfunction "DOUT_3") (pintype "output"))
      (node (ref "IC284") (pin "1") (pinfunction "DIN_1") (pintype "input"))
    )
    (net (code "318") (name "Net-(IC284-DOUT)") (class "Default")
      (node (ref "IC284") (pin "3") (pinfunction "DOUT_3") (pintype "output"))
      (node (ref "IC285") (pin "1") (pinfunction "DIN_1") (pintype "input"))
    )
    (net (code "319") (name "Net-(IC285-DOUT)") (class "Default")
      (node (ref "IC285") (pin "3") (pinfunction "DOUT_3") (pintype "output"))
      (node (ref "IC286") (pin "1") (pinfunction "DIN_1") (pintype "input"))
    )
    (net (code "320") (name "Net-(IC286-DOUT)") (class "Default")
      (node (ref "IC286") (pin "3") (pinfunction "DOUT_3") (pintype "output"))
      (node (ref "IC287") (pin "1") (pinfunction "DIN_1") (pintype "input"))
    )
    (net (code "321") (name "Net-(IC288-DOUT)") (class "Default")
      (node (ref "IC288") (pin "3") (pinfunction "DOUT_3") (pintype "output"))
      (node (ref "IC289") (pin "1") (pinfunction "DIN_1") (pintype "input"))
    )
    (net (code "322") (name "Net-(IC289-DOUT)") (class "Default")
      (node (ref "IC289") (pin "3") (pinfunction "DOUT_3") (pintype "output"))
      (node (ref "IC290") (pin "1") (pinfunction "DIN_1") (pintype "input"))
    )
    (net (code "323") (name "Net-(IC290-DOUT)") (class "Default")
      (node (ref "IC290") (pin "3") (pinfunction "DOUT_3") (pintype "output"))
      (node (ref "IC291") (pin "1") (pinfunction "DIN_1") (pintype "input"))
    )
    (net (code "324") (name "Net-(IC291-DOUT)") (class "Default")
      (node (ref "IC291") (pin "3") (pinfunction "DOUT_3") (pintype "output"))
      (node (ref "IC292") (pin "1") (pinfunction "DIN_1") (pintype "input"))
    )
    (net (code "325") (name "Net-(IC293-DOUT)") (class "Default")
      (node (ref "IC293") (pin "3") (pinfunction "DOUT_3") (pintype "output"))
      (node (ref "IC294") (pin "1") (pinfunction "DIN_1") (pintype "input"))
    )
    (net (code "326") (name "Net-(IC294-DOUT)") (class "Default")
      (node (ref "IC294") (pin "3") (pinfunction "DOUT_3") (pintype "output"))
      (node (ref "IC295") (pin "1") (pinfunction "DIN_1") (pintype "input"))
    )
    (net (code "327") (name "Net-(IC295-DOUT)") (class "Default")
      (node (ref "IC295") (pin "3") (pinfunction "DOUT_3") (pintype "output"))
      (node (ref "IC296") (pin "1") (pinfunction "DIN_1") (pintype "input"))
    )
    (net (code "328") (name "Net-(IC296-DOUT)") (class "Default")
      (node (ref "IC296") (pin "3") (pinfunction "DOUT_3") (pintype "output"))
      (node (ref "IC297") (pin "1") (pinfunction "DIN_1") (pintype "input"))
    )
    (net (code "329") (name "Net-(IC298-DOUT)") (class "Default")
      (node (ref "IC298") (pin "3") (pinfunction "DOUT_3") (pintype "output"))
      (node (ref "IC299") (pin "1") (pinfunction "DIN_1") (pintype "input"))
    )
    (net (code "330") (name "Net-(IC299-DOUT)") (class "Default")
      (node (ref "IC299") (pin "3") (pinfunction "DOUT_3") (pintype "output"))
      (node (ref "IC300") (pin "1") (pinfunction "DIN_1") (pintype "input"))
    )
    (net (code "331") (name "Net-(IC300-DOUT)") (class "Default")
      (node (ref "IC300") (pin "3") (pinfunction "DOUT_3") (pintype "output"))
      (node (ref "IC301") (pin "1") (pinfunction "DIN_1") (pintype "input"))
    )
    (net (code "332") (name "Net-(IC301-DOUT)") (class "Default")
      (node (ref "IC301") (pin "3") (pinfunction "DOUT_3") (pintype "output"))
      (node (ref "IC302") (pin "1") (pinfunction "DIN_1") (pintype "input"))
    )
    (net (code "333") (name "Net-(IC303-DOUT)") (class "Default")
      (node (ref "IC303") (pin "3") (pinfunction "DOUT_3") (pintype "output"))
      (node (ref "IC304") (pin "1") (pinfunction "DIN_1") (pintype "input"))
    )
    (net (code "334") (name "Net-(IC304-DOUT)") (class "Default")
      (node (ref "IC304") (pin "3") (pinfunction "DOUT_3") (pintype "output"))
      (node (ref "IC305") (pin "1") (pinfunction "DIN_1") (pintype "input"))
    )
    (net (code "335") (name "Net-(IC305-DOUT)") (class "Default")
      (node (ref "IC305") (pin "3") (pinfunction "DOUT_3") (pintype "output"))
      (node (ref "IC306") (pin "1") (pinfunction "DIN_1") (pintype "input"))
    )
    (net (code "336") (name "Net-(IC306-DOUT)") (class "Default")
      (node (ref "IC306") (pin "3") (pinfunction "DOUT_3") (pintype "output"))
      (node (ref "IC307") (pin "1") (pinfunction "DIN_1") (pintype "input"))
    )
    (net (code "337") (name "Net-(IC308-DOUT)") (class "Default")
      (node (ref "IC308") (pin "3") (pinfunction "DOUT_3") (pintype "output"))
      (node (ref "IC309") (pin "1") (pinfunction "DIN_1") (pintype "input"))
    )
    (net (code "338") (name "Net-(IC309-DOUT)") (class "Default")
      (node (ref "IC309") (pin "3") (pinfunction "DOUT_3") (pintype "output"))
      (node (ref "IC310") (pin "1") (pinfunction "DIN_1") (pintype "input"))
    )
    (net (code "339") (name "Net-(IC310-DOUT)") (class "Default")
      (node (ref "IC310") (pin "3") (pinfunction "DOUT_3") (pintype "output"))
      (node (ref "IC311") (pin "1") (pinfunction "DIN_1") (pintype "input"))
    )
    (net (code "340") (name "Net-(IC311-DOUT)") (class "Default")
      (node (ref "IC311") (pin "3") (pinfunction "DOUT_3") (pintype "output"))
      (node (ref "IC312") (pin "1") (pinfunction "DIN_1") (pintype "input"))
    )
    (net (code "341") (name "Net-(IC313-DOUT)") (class "Default")
      (node (ref "IC313") (pin "3") (pinfunction "DOUT_3") (pintype "output"))
      (node (ref "IC314") (pin "1") (pinfunction "DIN_1") (pintype "input"))
    )
    (net (code "342") (name "Net-(IC314-DOUT)") (class "Default")
      (node (ref "IC314") (pin "3") (pinfunction "DOUT_3") (pintype "output"))
      (node (ref "IC315") (pin "1") (pinfunction "DIN_1") (pintype "input"))
    )
    (net (code "343") (name "Net-(IC315-DOUT)") (class "Default")
      (node (ref "IC315") (pin "3") (pinfunction "DOUT_3") (pintype "output"))
      (node (ref "IC316") (pin "1") (pinfunction "DIN_1") (pintype "input"))
    )
    (net (code "344") (name "Net-(IC316-DOUT)") (class "Default")
      (node (ref "IC316") (pin "3") (pinfunction "DOUT_3") (pintype "output"))
      (node (ref "IC317") (pin "1") (pinfunction "DIN_1") (pintype "input"))
    )
    (net (code "345") (name "Net-(IC318-DOUT)") (class "Default")
      (node (ref "IC318") (pin "3") (pinfunction "DOUT_3") (pintype "output"))
      (node (ref "IC319") (pin "1") (pinfunction "DIN_1") (pintype "input"))
    )
    (net (code "346") (name "Net-(IC319-DOUT)") (class "Default")
      (node (ref "IC319") (pin "3") (pinfunction "DOUT_3") (pintype "output"))
      (node (ref "IC320") (pin "1") (pinfunction "DIN_1") (pintype "input"))
    )
    (net (code "347") (name "Net-(IC320-DOUT)") (class "Default")
      (node (ref "IC320") (pin "3") (pinfunction "DOUT_3") (pintype "output"))
      (node (ref "IC321") (pin "1") (pinfunction "DIN_1") (pintype "input"))
    )
    (net (code "348") (name "Net-(IC321-DOUT)") (class "Default")
      (node (ref "IC321") (pin "3") (pinfunction "DOUT_3") (pintype "output"))
      (node (ref "IC322") (pin "1") (pinfunction "DIN_1") (pintype "input"))
    )
    (net (code "349") (name "Net-(IC324-DOUT)") (class "Default")
      (node (ref "IC324") (pin "3") (pinfunction "DOUT_3") (pintype "output"))
      (node (ref "IC325") (pin "1") (pinfunction "DIN_1") (pintype "input"))
    )
    (net (code "350") (name "Net-(IC325-DOUT)") (class "Default")
      (node (ref "IC325") (pin "3") (pinfunction "DOUT_3") (pintype "output"))
      (node (ref "IC326") (pin "1") (pinfunction "DIN_1") (pintype "input"))
    )
    (net (code "351") (name "Net-(IC326-DOUT)") (class "Default")
      (node (ref "IC326") (pin "3") (pinfunction "DOUT_3") (pintype "output"))
      (node (ref "IC327") (pin "1") (pinfunction "DIN_1") (pintype "input"))
    )
    (net (code "352") (name "Net-(IC327-DOUT)") (class "Default")
      (node (ref "IC327") (pin "3") (pinfunction "DOUT_3") (pintype "output"))
      (node (ref "IC328") (pin "1") (pinfunction "DIN_1") (pintype "input"))
    )
    (net (code "353") (name "Net-(IC329-DOUT)") (class "Default")
      (node (ref "IC329") (pin "3") (pinfunction "DOUT_3") (pintype "output"))
      (node (ref "IC330") (pin "1") (pinfunction "DIN_1") (pintype "input"))
    )
    (net (code "354") (name "Net-(IC330-DOUT)") (class "Default")
      (node (ref "IC330") (pin "3") (pinfunction "DOUT_3") (pintype "output"))
      (node (ref "IC331") (pin "1") (pinfunction "DIN_1") (pintype "input"))
    )
    (net (code "355") (name "Net-(IC331-DOUT)") (class "Default")
      (node (ref "IC331") (pin "3") (pinfunction "DOUT_3") (pintype "output"))
      (node (ref "IC332") (pin "1") (pinfunction "DIN_1") (pintype "input"))
    )
    (net (code "356") (name "Net-(R47-Pad2)") (class "Default")
      (node (ref "R47") (pin "2") (pinfunction "2_2") (pintype "passive"))
      (node (ref "X5") (pin "11") (pinfunction "11_11") (pintype "passive"))
    )
    (net (code "357") (name "Net-(R87-Pad1)") (class "Default")
      (node (ref "R87") (pin "1") (pinfunction "1_1") (pintype "passive"))
      (node (ref "X4") (pin "7") (pinfunction "7_7") (pintype "passive"))
    )
    (net (code "358") (name "Net-(T2-D)") (class "Default")
      (node (ref "D306") (pin "C") (pinfunction "C_C") (pintype "passive"))
      (node (ref "D308") (pin "C") (pinfunction "C_C") (pintype "passive"))
      (node (ref "T2") (pin "3") (pinfunction "D_3") (pintype "passive"))
    )
    (net (code "359") (name "Net-(T2-G)") (class "Default")
      (node (ref "R21") (pin "2") (pinfunction "2_2") (pintype "passive"))
      (node (ref "T2") (pin "1") (pinfunction "G_1") (pintype "passive"))
      (node (ref "TP15") (pin "TP") (pinfunction "TP_TP") (pintype "input"))
    )
    (net (code "360") (name "Net-(T3-D)") (class "Default")
      (node (ref "D200") (pin "C") (pinfunction "C_C") (pintype "passive"))
      (node (ref "D207") (pin "C") (pinfunction "C_C") (pintype "passive"))
      (node (ref "T3") (pin "3") (pinfunction "D_3") (pintype "passive"))
    )
    (net (code "361") (name "Net-(T3-G)") (class "Default")
      (node (ref "R23") (pin "2") (pinfunction "2_2") (pintype "passive"))
      (node (ref "T3") (pin "1") (pinfunction "G_1") (pintype "passive"))
      (node (ref "TP6") (pin "TP") (pinfunction "TP_TP") (pintype "input"))
    )
    (net (code "362") (name "Net-(T6-D)") (class "Default")
      (node (ref "D356") (pin "C") (pinfunction "C_C") (pintype "passive"))
      (node (ref "D358") (pin "C") (pinfunction "C_C") (pintype "passive"))
      (node (ref "T6") (pin "3") (pinfunction "D_3") (pintype "passive"))
    )
    (net (code "363") (name "Net-(T6-G)") (class "Default")
      (node (ref "R54") (pin "2") (pinfunction "2_2") (pintype "passive"))
      (node (ref "T6") (pin "1") (pinfunction "G_1") (pintype "passive"))
    )
    (net (code "364") (name "Net-(T7-D)") (class "Default")
      (node (ref "D250") (pin "C") (pinfunction "C_C") (pintype "passive"))
      (node (ref "D257") (pin "C") (pinfunction "C_C") (pintype "passive"))
      (node (ref "T7") (pin "3") (pinfunction "D_3") (pintype "passive"))
    )
    (net (code "365") (name "Net-(T7-G)") (class "Default")
      (node (ref "R59") (pin "2") (pinfunction "2_2") (pintype "passive"))
      (node (ref "T7") (pin "1") (pinfunction "G_1") (pintype "passive"))
      (node (ref "TP16") (pin "TP") (pinfunction "TP_TP") (pintype "input"))
    )
    (net (code "366") (name "Net-(T10-D)") (class "Default")
      (node (ref "D105") (pin "1") (pinfunction "C_1") (pintype "passive"))
      (node (ref "D105") (pin "4") (pinfunction "C_4") (pintype "passive"))
      (node (ref "T10") (pin "3") (pinfunction "D_3") (pintype "passive"))
    )
    (net (code "367") (name "Net-(T10-G)") (class "Default")
      (node (ref "R80") (pin "2") (pinfunction "2_2") (pintype "passive"))
      (node (ref "T10") (pin "1") (pinfunction "G_1") (pintype "passive"))
    )
    (net (code "368") (name "PVCC_DISABLE") (class "Default")
      (node (ref "R56") (pin "2") (pinfunction "2_2") (pintype "passive"))
      (node (ref "R64") (pin "1") (pinfunction "1_1") (pintype "passive"))
      (node (ref "R67") (pin "1") (pinfunction "1_1") (pintype "passive"))
      (node (ref "TP12") (pin "TP") (pinfunction "TP_TP") (pintype "input"))
    )
    (net (code "369") (name "RBG_DOUT_END") (class "Default")
      (node (ref "IC323") (pin "3") (pinfunction "DOUT_3") (pintype "output"))
      (node (ref "TP9") (pin "TP") (pinfunction "TP_TP") (pintype "input"))
    )
    (net (code "370") (name "RGB_DOUT_4") (class "Default")
      (node (ref "IC104") (pin "3") (pinfunction "DOUT_3") (pintype "output"))
      (node (ref "IC105") (pin "1") (pinfunction "DIN_1") (pintype "input"))
    )
    (net (code "371") (name "RGB_DOUT_9") (class "Default")
      (node (ref "IC109") (pin "3") (pinfunction "DOUT_3") (pintype "output"))
      (node (ref "IC110") (pin "1") (pinfunction "DIN_1") (pintype "input"))
    )
    (net (code "372") (name "RGB_DOUT_14") (class "Default")
      (node (ref "IC114") (pin "3") (pinfunction "DOUT_3") (pintype "output"))
      (node (ref "IC115") (pin "1") (pinfunction "DIN_1") (pintype "input"))
    )
    (net (code "373") (name "RGB_DOUT_19") (class "Default")
      (node (ref "IC119") (pin "3") (pinfunction "DOUT_3") (pintype "output"))
      (node (ref "IC120") (pin "1") (pinfunction "DIN_1") (pintype "input"))
    )
    (net (code "374") (name "RGB_DOUT_24") (class "Default")
      (node (ref "IC124") (pin "3") (pinfunction "DOUT_3") (pintype "output"))
      (node (ref "IC125") (pin "1") (pinfunction "DIN_1") (pintype "input"))
    )
    (net (code "375") (name "RGB_DOUT_29") (class "Default")
      (node (ref "IC129") (pin "3") (pinfunction "DOUT_3") (pintype "output"))
      (node (ref "IC130") (pin "1") (pinfunction "DIN_1") (pintype "input"))
    )
    (net (code "376") (name "RGB_DOUT_34") (class "Default")
      (node (ref "IC134") (pin "3") (pinfunction "DOUT_3") (pintype "output"))
      (node (ref "IC135") (pin "1") (pinfunction "DIN_1") (pintype "input"))
    )
    (net (code "377") (name "RGB_DOUT_39") (class "Default")
      (node (ref "IC139") (pin "3") (pinfunction "DOUT_3") (pintype "output"))
      (node (ref "IC140") (pin "1") (pinfunction "DIN_1") (pintype "input"))
    )
    (net (code "378") (name "RGB_DOUT_44") (class "Default")
      (node (ref "IC144") (pin "3") (pinfunction "DOUT_3") (pintype "output"))
      (node (ref "IC145") (pin "1") (pinfunction "DIN_1") (pintype "input"))
    )
    (net (code "379") (name "RGB_DOUT_49") (class "Default")
      (node (ref "IC149") (pin "3") (pinfunction "DOUT_3") (pintype "output"))
      (node (ref "IC150") (pin "1") (pinfunction "DIN_1") (pintype "input"))
    )
    (net (code "380") (name "RGB_DOUT_54") (class "Default")
      (node (ref "IC154") (pin "3") (pinfunction "DOUT_3") (pintype "output"))
      (node (ref "IC155") (pin "1") (pinfunction "DIN_1") (pintype "input"))
    )
    (net (code "381") (name "RGB_DOUT_55") (class "Default")
      (node (ref "IC155") (pin "3") (pinfunction "DOUT_3") (pintype "output"))
      (node (ref "IC156") (pin "1") (pinfunction "DIN_1") (pintype "input"))
    )
    (net (code "382") (name "RGB_DOUT_60") (class "Default")
      (node (ref "IC160") (pin "3") (pinfunction "DOUT_3") (pintype "output"))
      (node (ref "IC161") (pin "1") (pinfunction "DIN_1") (pintype "input"))
    )
    (net (code "383") (name "RGB_DOUT_65") (class "Default")
      (node (ref "IC165") (pin "3") (pinfunction "DOUT_3") (pintype "output"))
      (node (ref "IC166") (pin "1") (pinfunction "DIN_1") (pintype "input"))
    )
    (net (code "384") (name "RGB_DOUT_70") (class "Default")
      (node (ref "IC170") (pin "3") (pinfunction "DOUT_3") (pintype "output"))
      (node (ref "IC171") (pin "1") (pinfunction "DIN_1") (pintype "input"))
    )
    (net (code "385") (name "RGB_DOUT_75") (class "Default")
      (node (ref "IC175") (pin "3") (pinfunction "DOUT_3") (pintype "output"))
      (node (ref "IC176") (pin "1") (pinfunction "DIN_1") (pintype "input"))
    )
    (net (code "386") (name "RGB_DOUT_80") (class "Default")
      (node (ref "IC180") (pin "3") (pinfunction "DOUT_3") (pintype "output"))
      (node (ref "IC181") (pin "1") (pinfunction "DIN_1") (pintype "input"))
    )
    (net (code "387") (name "RGB_DOUT_85") (class "Default")
      (node (ref "IC185") (pin "3") (pinfunction "DOUT_3") (pintype "output"))
      (node (ref "IC186") (pin "1") (pinfunction "DIN_1") (pintype "input"))
    )
    (net (code "388") (name "RGB_DOUT_90") (class "Default")
      (node (ref "IC190") (pin "3") (pinfunction "DOUT_3") (pintype "output"))
      (node (ref "IC191") (pin "1") (pinfunction "DIN_1") (pintype "input"))
    )
    (net (code "389") (name "RGB_DOUT_95") (class "Default")
      (node (ref "IC195") (pin "3") (pinfunction "DOUT_3") (pintype "output"))
      (node (ref "IC196") (pin "1") (pinfunction "DIN_1") (pintype "input"))
    )
    (net (code "390") (name "RGB_DOUT_100") (class "Default")
      (node (ref "IC200") (pin "3") (pinfunction "DOUT_3") (pintype "output"))
      (node (ref "IC201") (pin "1") (pinfunction "DIN_1") (pintype "input"))
    )
    (net (code "391") (name "RGB_DOUT_105") (class "Default")
      (node (ref "IC205") (pin "3") (pinfunction "DOUT_3") (pintype "output"))
      (node (ref "IC206") (pin "1") (pinfunction "DIN_1") (pintype "input"))
    )
    (net (code "392") (name "RGB_DOUT_110") (class "Default")
      (node (ref "IC210") (pin "3") (pinfunction "DOUT_3") (pintype "output"))
      (node (ref "IC211") (pin "1") (pinfunction "DIN_1") (pintype "input"))
    )
    (net (code "393") (name "RGB_DOUT_111") (class "Default")
      (node (ref "IC211") (pin "3") (pinfunction "DOUT_3") (pintype "output"))
      (node (ref "IC212") (pin "1") (pinfunction "DIN_1") (pintype "input"))
    )
    (net (code "394") (name "RGB_DOUT_116") (class "Default")
      (node (ref "IC216") (pin "3") (pinfunction "DOUT_3") (pintype "output"))
      (node (ref "IC217") (pin "1") (pinfunction "DIN_1") (pintype "input"))
    )
    (net (code "395") (name "RGB_DOUT_121") (class "Default")
      (node (ref "IC221") (pin "3") (pinfunction "DOUT_3") (pintype "output"))
      (node (ref "IC222") (pin "1") (pinfunction "DIN_1") (pintype "input"))
    )
    (net (code "396") (name "RGB_DOUT_126") (class "Default")
      (node (ref "IC226") (pin "3") (pinfunction "DOUT_3") (pintype "output"))
      (node (ref "IC227") (pin "1") (pinfunction "DIN_1") (pintype "input"))
    )
    (net (code "397") (name "RGB_DOUT_131") (class "Default")
      (node (ref "IC231") (pin "3") (pinfunction "DOUT_3") (pintype "output"))
      (node (ref "IC232") (pin "1") (pinfunction "DIN_1") (pintype "input"))
    )
    (net (code "398") (name "RGB_DOUT_136") (class "Default")
      (node (ref "IC236") (pin "3") (pinfunction "DOUT_3") (pintype "output"))
      (node (ref "IC237") (pin "1") (pinfunction "DIN_1") (pintype "input"))
    )
    (net (code "399") (name "RGB_DOUT_141") (class "Default")
      (node (ref "IC241") (pin "3") (pinfunction "DOUT_3") (pintype "output"))
      (node (ref "IC242") (pin "1") (pinfunction "DIN_1") (pintype "input"))
    )
    (net (code "400") (name "RGB_DOUT_146") (class "Default")
      (node (ref "IC246") (pin "3") (pinfunction "DOUT_3") (pintype "output"))
      (node (ref "IC247") (pin "1") (pinfunction "DIN_1") (pintype "input"))
    )
    (net (code "401") (name "RGB_DOUT_151") (class "Default")
      (node (ref "IC251") (pin "3") (pinfunction "DOUT_3") (pintype "output"))
      (node (ref "IC252") (pin "1") (pinfunction "DIN_1") (pintype "input"))
    )
    (net (code "402") (name "RGB_DOUT_156") (class "Default")
      (node (ref "IC256") (pin "3") (pinfunction "DOUT_3") (pintype "output"))
      (node (ref "IC257") (pin "1") (pinfunction "DIN_1") (pintype "input"))
    )
    (net (code "403") (name "RGB_DOUT_161") (class "Default")
      (node (ref "IC261") (pin "3") (pinfunction "DOUT_3") (pintype "output"))
      (node (ref "IC262") (pin "1") (pinfunction "DIN_1") (pintype "input"))
    )
    (net (code "404") (name "RGB_DOUT_166") (class "Default")
      (node (ref "IC266") (pin "3") (pinfunction "DOUT_3") (pintype "output"))
      (node (ref "IC267") (pin "1") (pinfunction "DIN_1") (pintype "input"))
    )
    (net (code "405") (name "RGB_DOUT_167") (class "Default")
      (node (ref "IC267") (pin "3") (pinfunction "DOUT_3") (pintype "output"))
      (node (ref "IC268") (pin "1") (pinfunction "DIN_1") (pintype "input"))
    )
    (net (code "406") (name "RGB_DOUT_172") (class "Default")
      (node (ref "IC272") (pin "3") (pinfunction "DOUT_3") (pintype "output"))
      (node (ref "IC273") (pin "1") (pinfunction "DIN_1") (pintype "input"))
    )
    (net (code "407") (name "RGB_DOUT_177") (class "Default")
      (node (ref "IC277") (pin "3") (pinfunction "DOUT_3") (pintype "output"))
      (node (ref "IC278") (pin "1") (pinfunction "DIN_1") (pintype "input"))
    )
    (net (code "408") (name "RGB_DOUT_182") (class "Default")
      (node (ref "IC282") (pin "3") (pinfunction "DOUT_3") (pintype "output"))
      (node (ref "IC283") (pin "1") (pinfunction "DIN_1") (pintype "input"))
    )
    (net (code "409") (name "RGB_DOUT_187") (class "Default")
      (node (ref "IC287") (pin "3") (pinfunction "DOUT_3") (pintype "output"))
      (node (ref "IC288") (pin "1") (pinfunction "DIN_1") (pintype "input"))
    )
    (net (code "410") (name "RGB_DOUT_192") (class "Default")
      (node (ref "IC292") (pin "3") (pinfunction "DOUT_3") (pintype "output"))
      (node (ref "IC293") (pin "1") (pinfunction "DIN_1") (pintype "input"))
    )
    (net (code "411") (name "RGB_DOUT_197") (class "Default")
      (node (ref "IC297") (pin "3") (pinfunction "DOUT_3") (pintype "output"))
      (node (ref "IC298") (pin "1") (pinfunction "DIN_1") (pintype "input"))
    )
    (net (code "412") (name "RGB_DOUT_202") (class "Default")
      (node (ref "IC302") (pin "3") (pinfunction "DOUT_3") (pintype "output"))
      (node (ref "IC303") (pin "1") (pinfunction "DIN_1") (pintype "input"))
    )
    (net (code "413") (name "RGB_DOUT_207") (class "Default")
      (node (ref "IC307") (pin "3") (pinfunction "DOUT_3") (pintype "output"))
      (node (ref "IC308") (pin "1") (pinfunction "DIN_1") (pintype "input"))
    )
    (net (code "414") (name "RGB_DOUT_212") (class "Default")
      (node (ref "IC312") (pin "3") (pinfunction "DOUT_3") (pintype "output"))
      (node (ref "IC313") (pin "1") (pinfunction "DIN_1") (pintype "input"))
    )
    (net (code "415") (name "RGB_DOUT_217") (class "Default")
      (node (ref "IC317") (pin "3") (pinfunction "DOUT_3") (pintype "output"))
      (node (ref "IC318") (pin "1") (pinfunction "DIN_1") (pintype "input"))
    )
    (net (code "416") (name "RGB_DOUT_222") (class "Default")
      (node (ref "IC322") (pin "3") (pinfunction "DOUT_3") (pintype "output"))
      (node (ref "IC323") (pin "1") (pinfunction "DIN_1") (pintype "input"))
    )
    (net (code "417") (name "RGB_DOUT_228") (class "Default")
      (node (ref "IC328") (pin "3") (pinfunction "DOUT_3") (pintype "output"))
      (node (ref "IC329") (pin "1") (pinfunction "DIN_1") (pintype "input"))
    )
    (net (code "418") (name "RGB_DOUT_232") (class "Default")
      (node (ref "IC100") (pin "1") (pinfunction "DIN_1") (pintype "input"))
      (node (ref "IC332") (pin "3") (pinfunction "DOUT_3") (pintype "output"))
    )
    (net (code "419") (name "RGB_LED_UC->FU_5V") (class "Default")
      (node (ref "IC17") (pin "4") (pinfunction "I/O3_4") (pintype "passive"))
      (node (ref "IC324") (pin "1") (pinfunction "DIN_1") (pintype "input"))
      (node (ref "TP8") (pin "TP") (pinfunction "TP_TP") (pintype "input"))
      (node (ref "X1") (pin "24") (pinfunction "24_24") (pintype "passive"))
    )
    (net (code "420") (name "UC_CAM3_TOF_TRIGGER_TO_SENSOR_1V8") (class "Default")
      (node (ref "IC16") (pin "1") (pinfunction "I/O1_1") (pintype "passive"))
      (node (ref "X2") (pin "26") (pinfunction "26_26") (pintype "passive"))
      (node (ref "X5") (pin "18") (pinfunction "18_18") (pintype "passive"))
    )
    (net (code "421") (name "UC_FU_740NM_3V3") (class "Default")
      (node (ref "IC13") (pin "3") (pinfunction "IN+_3") (pintype "input"))
      (node (ref "IC14") (pin "1") (pinfunction "I/O1_1") (pintype "passive"))
      (node (ref "TP19") (pin "TP") (pinfunction "TP_TP") (pintype "input"))
      (node (ref "X1") (pin "35") (pinfunction "35_35") (pintype "passive"))
    )
    (net (code "422") (name "UC_FU_850NM_LEFT_3V3") (class "Default")
      (node (ref "IC17") (pin "3") (pinfunction "I/O2_3") (pintype "passive"))
      (node (ref "IC2") (pin "3") (pinfunction "IN+_3") (pintype "input"))
      (node (ref "R12") (pin "1") (pinfunction "1_1") (pintype "passive"))
      (node (ref "R5") (pin "2") (pinfunction "2_2") (pintype "passive"))
      (node (ref "TP20") (pin "TP") (pinfunction "TP_TP") (pintype "input"))
      (node (ref "X1") (pin "37") (pinfunction "37_37") (pintype "passive"))
    )
    (net (code "423") (name "UC_FU_850NM_RIGHT_3V3") (class "Default")
      (node (ref "IC10") (pin "3") (pinfunction "IN+_3") (pintype "input"))
      (node (ref "IC20") (pin "3") (pinfunction "I/O2_3") (pintype "passive"))
      (node (ref "R13") (pin "1") (pinfunction "1_1") (pintype "passive"))
      (node (ref "R6") (pin "2") (pinfunction "2_2") (pintype "passive"))
      (node (ref "TP21") (pin "TP") (pinfunction "TP_TP") (pintype "input"))
      (node (ref "X2") (pin "12") (pinfunction "12_12") (pintype "passive"))
    )
    (net (code "424") (name "UC_FU_940NM_LEFT_3V3") (class "Default")
      (node (ref "IC1") (pin "3") (pinfunction "IN+_3") (pintype "input"))
      (node (ref "IC17") (pin "1") (pinfunction "I/O1_1") (pintype "passive"))
      (node (ref "R10") (pin "1") (pinfunction "1_1") (pintype "passive"))
      (node (ref "R3") (pin "2") (pinfunction "2_2") (pintype "passive"))
      (node (ref "R50") (pin "1") (pinfunction "1_1") (pintype "passive"))
      (node (ref "TP14") (pin "TP") (pinfunction "TP_TP") (pintype "input"))
      (node (ref "X1") (pin "38") (pinfunction "38_38") (pintype "passive"))
    )
    (net (code "425") (name "UC_FU_940NM_RIGHT_3V3") (class "Default")
      (node (ref "IC20") (pin "1") (pinfunction "I/O1_1") (pintype "passive"))
      (node (ref "IC8") (pin "3") (pinfunction "IN+_3") (pintype "input"))
      (node (ref "R11") (pin "1") (pinfunction "1_1") (pintype "passive"))
      (node (ref "R4") (pin "2") (pinfunction "2_2") (pintype "passive"))
      (node (ref "TP17") (pin "TP") (pinfunction "TP_TP") (pintype "input"))
      (node (ref "X2") (pin "14") (pinfunction "14_14") (pintype "passive"))
    )
    (net (code "426") (name "unconnected-(IC4B-OUT-Pad7)") (class "Default")
      (node (ref "IC4") (pin "7") (pinfunction "OUT_7") (pintype "output"))
    )
    (net (code "427") (name "unconnected-(IC6A-A-Pad1)") (class "Default")
      (node (ref "IC6") (pin "1") (pinfunction "A_1") (pintype "passive"))
    )
    (net (code "428") (name "unconnected-(IC7-DNC-Pad8)") (class "Default")
      (node (ref "IC7") (pin "8") (pinfunction "DNC_8") (pintype "output"))
    )
    (net (code "429") (name "unconnected-(IC7-GPIO1-Pad7)") (class "Default")
      (node (ref "IC7") (pin "7") (pinfunction "GPIO1_7") (pintype "open_collector"))
    )
    (net (code "430") (name "unconnected-(IC9B-Q-Pad9)") (class "Default")
      (node (ref "IC9") (pin "9") (pinfunction "Q_9") (pintype "output"))
    )
    (net (code "431") (name "unconnected-(IC9B-~{Q}-Pad7)") (class "Default")
      (node (ref "IC9") (pin "7") (pinfunction "~{Q}_7") (pintype "output"))
    )
    (net (code "432") (name "unconnected-(IC15-ALERT-Pad3)") (class "Default")
      (node (ref "IC15") (pin "3") (pinfunction "ALERT_3") (pintype "open_collector"))
    )
    (net (code "433") (name "unconnected-(IC16-I{slash}O2-Pad3)") (class "Default")
      (node (ref "IC16") (pin "3") (pinfunction "I/O2_3") (pintype "passive"))
    )
    (net (code "434") (name "unconnected-(IC16-I{slash}O3-Pad4)") (class "Default")
      (node (ref "IC16") (pin "4") (pinfunction "I/O3_4") (pintype "passive"))
    )
    (net (code "435") (name "unconnected-(IC16-I{slash}O4-Pad6)") (class "Default")
      (node (ref "IC16") (pin "6") (pinfunction "I/O4_6") (pintype "passive"))
    )
    (net (code "436") (name "unconnected-(IC17-I{slash}O4-Pad6)") (class "Default")
      (node (ref "IC17") (pin "6") (pinfunction "I/O4_6") (pintype "passive"))
    )
    (net (code "437") (name "unconnected-(IC23-S1B-Pad11)") (class "Default")
      (node (ref "IC23") (pin "11") (pinfunction "S1B_11") (pintype "passive"))
    )
    (net (code "438") (name "unconnected-(IC23-S2B-Pad10)") (class "Default")
      (node (ref "IC23") (pin "10") (pinfunction "S2B_10") (pintype "passive"))
    )
    (net (code "439") (name "unconnected-(IC23-S3A-Pad4)") (class "Default")
      (node (ref "IC23") (pin "4") (pinfunction "S3A_4") (pintype "passive"))
    )
    (net (code "440") (name "unconnected-(IC23-S3B-Pad9)") (class "Default")
      (node (ref "IC23") (pin "9") (pinfunction "S3B_9") (pintype "passive"))
    )
    (net (code "441") (name "unconnected-(IC23-S4A-Pad5)") (class "Default")
      (node (ref "IC23") (pin "5") (pinfunction "S4A_5") (pintype "passive"))
    )
    (net (code "442") (name "unconnected-(IC23-S4B-Pad8)") (class "Default")
      (node (ref "IC23") (pin "8") (pinfunction "S4B_8") (pintype "passive"))
    )
    (net (code "443") (name "unconnected-(IC24-ALERT-Pad3)") (class "Default")
      (node (ref "IC24") (pin "3") (pinfunction "ALERT_3") (pintype "open_collector"))
    )
    (net (code "444") (name "unconnected-(IC25-DNC2-Pad7)") (class "Default")
      (node (ref "IC25") (pin "7") (pinfunction "DNC2_7") (pintype "output"))
    )
    (net (code "445") (name "unconnected-(IC25-DNC3-Pad8)") (class "Default")
      (node (ref "IC25") (pin "8") (pinfunction "DNC3_8") (pintype "output"))
    )
    (net (code "446") (name "unconnected-(X3-Pad13)") (class "Default")
      (node (ref "X3") (pin "13") (pinfunction "13_13") (pintype "bidirectional"))
    )
    (net (code "447") (name "unconnected-(X3-Pad14)") (class "Default")
      (node (ref "X3") (pin "14") (pinfunction "14_14") (pintype "bidirectional"))
    )
    (net (code "448") (name "unconnected-(X3-Pad17)") (class "Default")
      (node (ref "X3") (pin "17") (pinfunction "17_17") (pintype "bidirectional"))
    )
    (net (code "449") (name "unconnected-(X3-Pad18)") (class "Default")
      (node (ref "X3") (pin "18") (pinfunction "18_18") (pintype "bidirectional"))
    )
    (net (code "450") (name "unconnected-(X3-Pad19)") (class "Default")
      (node (ref "X3") (pin "19") (pinfunction "19_19") (pintype "bidirectional"))
    )
    (net (code "451") (name "unconnected-(X3-Pad20)") (class "Default")
      (node (ref "X3") (pin "20") (pinfunction "20_20") (pintype "bidirectional"))
    )
    (net (code "452") (name "unconnected-(X3-Pad29)") (class "Default")
      (node (ref "X3") (pin "29") (pinfunction "29_29") (pintype "bidirectional"))
    )
    (net (code "453") (name "unconnected-(X3-Pad30)") (class "Default")
      (node (ref "X3") (pin "30") (pinfunction "30_30") (pintype "bidirectional"))
    )
    (net (code "454") (name "unconnected-(X5-Pad7)") (class "Default")
      (node (ref "X5") (pin "7") (pinfunction "7_7") (pintype "passive"))
    )
    (net (code "455") (name "unconnected-(X5-Pad20)") (class "Default")
      (node (ref "X5") (pin "20") (pinfunction "20_20") (pintype "passive"))
    )
  )
)
